# 4high.net
KiCad netlist of a schematic drawn in EAGLE
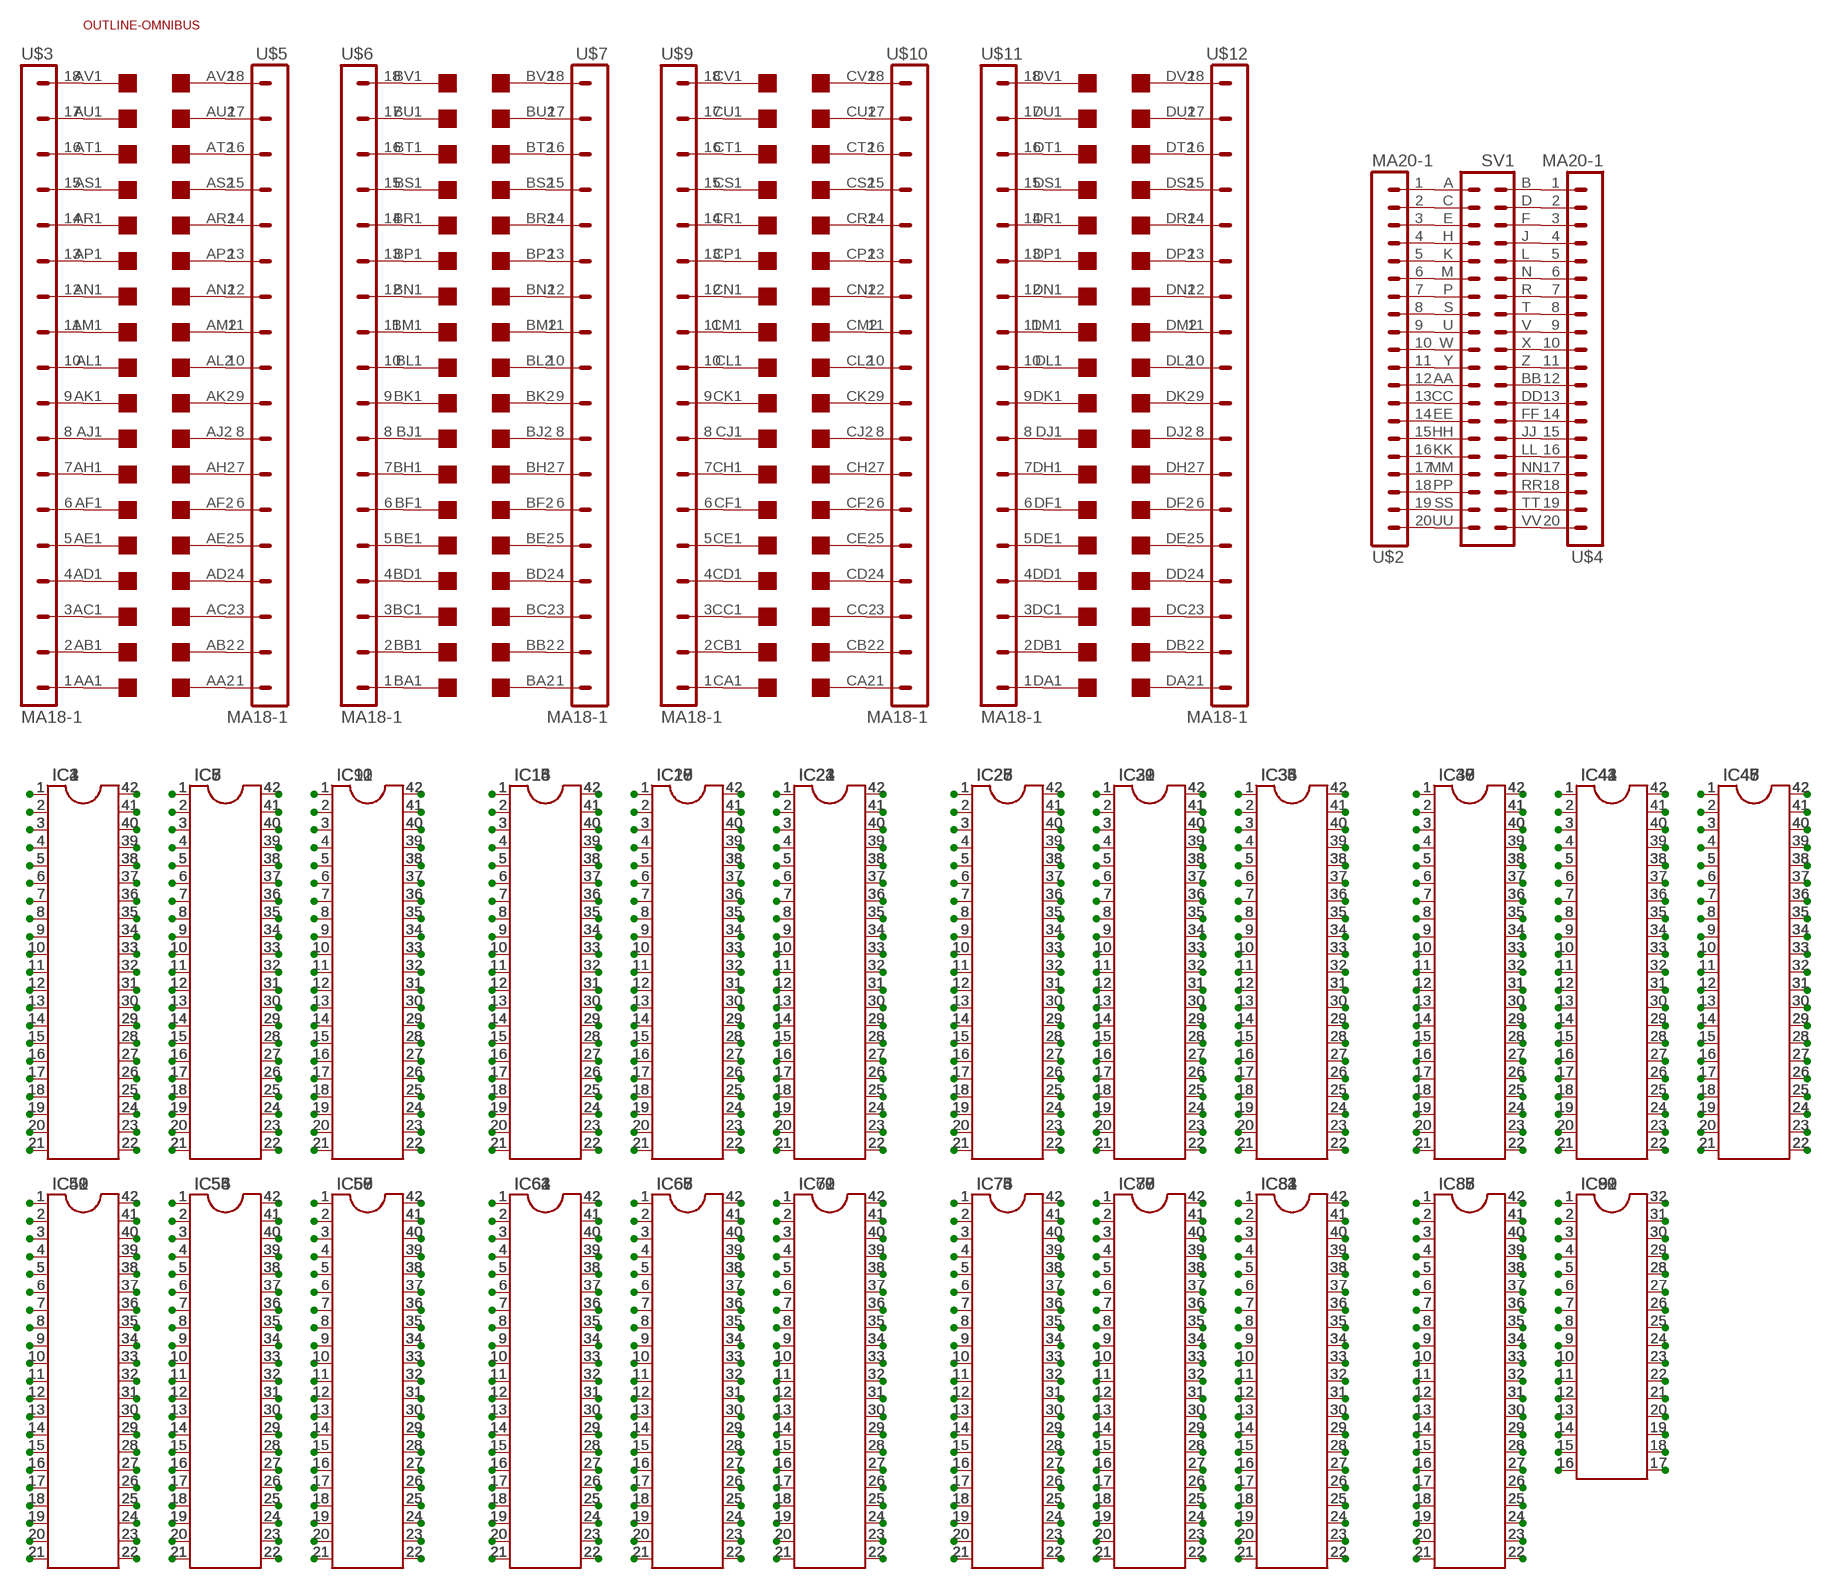
[diagram p0: schematic, sheet 1]

(export (version "E")
  (design (tool "Eeschema 10.0.6"))
  (components
    (comp (ref "IC1")
      (value "DIL42")
      (footprint "eagle-import:DIL42")
      (libsource (lib "eagle-import") (part "DIL42"))
    )
    (comp (ref "IC2")
      (value "DIL42")
      (footprint "eagle-import:DIL42")
      (libsource (lib "eagle-import") (part "DIL42"))
    )
    (comp (ref "IC3")
      (value "DIL42")
      (footprint "eagle-import:DIL42")
      (libsource (lib "eagle-import") (part "DIL42"))
    )
    (comp (ref "IC4")
      (value "DIL42")
      (footprint "eagle-import:DIL42")
      (libsource (lib "eagle-import") (part "DIL42"))
    )
    (comp (ref "IC5")
      (value "DIL42")
      (footprint "eagle-import:DIL42")
      (libsource (lib "eagle-import") (part "DIL42"))
    )
    (comp (ref "IC6")
      (value "DIL42")
      (footprint "eagle-import:DIL42")
      (libsource (lib "eagle-import") (part "DIL42"))
    )
    (comp (ref "IC7")
      (value "DIL42")
      (footprint "eagle-import:DIL42")
      (libsource (lib "eagle-import") (part "DIL42"))
    )
    (comp (ref "IC8")
      (value "DIL42")
      (footprint "eagle-import:DIL42")
      (libsource (lib "eagle-import") (part "DIL42"))
    )
    (comp (ref "IC9")
      (value "DIL42")
      (footprint "eagle-import:DIL42")
      (libsource (lib "eagle-import") (part "DIL42"))
    )
    (comp (ref "IC10")
      (value "DIL42")
      (footprint "eagle-import:DIL42")
      (libsource (lib "eagle-import") (part "DIL42"))
    )
    (comp (ref "IC11")
      (value "DIL42")
      (footprint "eagle-import:DIL42")
      (libsource (lib "eagle-import") (part "DIL42"))
    )
    (comp (ref "IC12")
      (value "DIL42")
      (footprint "eagle-import:DIL42")
      (libsource (lib "eagle-import") (part "DIL42"))
    )
    (comp (ref "IC13")
      (value "DIL42")
      (footprint "eagle-import:DIL42")
      (libsource (lib "eagle-import") (part "DIL42"))
    )
    (comp (ref "IC14")
      (value "DIL42")
      (footprint "eagle-import:DIL42")
      (libsource (lib "eagle-import") (part "DIL42"))
    )
    (comp (ref "IC15")
      (value "DIL42")
      (footprint "eagle-import:DIL42")
      (libsource (lib "eagle-import") (part "DIL42"))
    )
    (comp (ref "IC16")
      (value "DIL42")
      (footprint "eagle-import:DIL42")
      (libsource (lib "eagle-import") (part "DIL42"))
    )
    (comp (ref "IC17")
      (value "DIL42")
      (footprint "eagle-import:DIL42")
      (libsource (lib "eagle-import") (part "DIL42"))
    )
    (comp (ref "IC18")
      (value "DIL42")
      (footprint "eagle-import:DIL42")
      (libsource (lib "eagle-import") (part "DIL42"))
    )
    (comp (ref "IC19")
      (value "DIL42")
      (footprint "eagle-import:DIL42")
      (libsource (lib "eagle-import") (part "DIL42"))
    )
    (comp (ref "IC20")
      (value "DIL42")
      (footprint "eagle-import:DIL42")
      (libsource (lib "eagle-import") (part "DIL42"))
    )
    (comp (ref "IC21")
      (value "DIL42")
      (footprint "eagle-import:DIL42")
      (libsource (lib "eagle-import") (part "DIL42"))
    )
    (comp (ref "IC22")
      (value "DIL42")
      (footprint "eagle-import:DIL42")
      (libsource (lib "eagle-import") (part "DIL42"))
    )
    (comp (ref "IC23")
      (value "DIL42")
      (footprint "eagle-import:DIL42")
      (libsource (lib "eagle-import") (part "DIL42"))
    )
    (comp (ref "IC24")
      (value "DIL42")
      (footprint "eagle-import:DIL42")
      (libsource (lib "eagle-import") (part "DIL42"))
    )
    (comp (ref "IC25")
      (value "DIL42")
      (footprint "eagle-import:DIL42")
      (libsource (lib "eagle-import") (part "DIL42"))
    )
    (comp (ref "IC26")
      (value "DIL42")
      (footprint "eagle-import:DIL42")
      (libsource (lib "eagle-import") (part "DIL42"))
    )
    (comp (ref "IC27")
      (value "DIL42")
      (footprint "eagle-import:DIL42")
      (libsource (lib "eagle-import") (part "DIL42"))
    )
    (comp (ref "IC28")
      (value "DIL42")
      (footprint "eagle-import:DIL42")
      (libsource (lib "eagle-import") (part "DIL42"))
    )
    (comp (ref "IC29")
      (value "DIL42")
      (footprint "eagle-import:DIL42")
      (libsource (lib "eagle-import") (part "DIL42"))
    )
    (comp (ref "IC30")
      (value "DIL42")
      (footprint "eagle-import:DIL42")
      (libsource (lib "eagle-import") (part "DIL42"))
    )
    (comp (ref "IC31")
      (value "DIL42")
      (footprint "eagle-import:DIL42")
      (libsource (lib "eagle-import") (part "DIL42"))
    )
    (comp (ref "IC32")
      (value "DIL42")
      (footprint "eagle-import:DIL42")
      (libsource (lib "eagle-import") (part "DIL42"))
    )
    (comp (ref "IC33")
      (value "DIL42")
      (footprint "eagle-import:DIL42")
      (libsource (lib "eagle-import") (part "DIL42"))
    )
    (comp (ref "IC34")
      (value "DIL42")
      (footprint "eagle-import:DIL42")
      (libsource (lib "eagle-import") (part "DIL42"))
    )
    (comp (ref "IC35")
      (value "DIL42")
      (footprint "eagle-import:DIL42")
      (libsource (lib "eagle-import") (part "DIL42"))
    )
    (comp (ref "IC36")
      (value "DIL42")
      (footprint "eagle-import:DIL42")
      (libsource (lib "eagle-import") (part "DIL42"))
    )
    (comp (ref "IC37")
      (value "DIL42")
      (footprint "eagle-import:DIL42")
      (libsource (lib "eagle-import") (part "DIL42"))
    )
    (comp (ref "IC38")
      (value "DIL42")
      (footprint "eagle-import:DIL42")
      (libsource (lib "eagle-import") (part "DIL42"))
    )
    (comp (ref "IC39")
      (value "DIL42")
      (footprint "eagle-import:DIL42")
      (libsource (lib "eagle-import") (part "DIL42"))
    )
    (comp (ref "IC40")
      (value "DIL42")
      (footprint "eagle-import:DIL42")
      (libsource (lib "eagle-import") (part "DIL42"))
    )
    (comp (ref "IC41")
      (value "DIL42")
      (footprint "eagle-import:DIL42")
      (libsource (lib "eagle-import") (part "DIL42"))
    )
    (comp (ref "IC42")
      (value "DIL42")
      (footprint "eagle-import:DIL42")
      (libsource (lib "eagle-import") (part "DIL42"))
    )
    (comp (ref "IC43")
      (value "DIL42")
      (footprint "eagle-import:DIL42")
      (libsource (lib "eagle-import") (part "DIL42"))
    )
    (comp (ref "IC44")
      (value "DIL42")
      (footprint "eagle-import:DIL42")
      (libsource (lib "eagle-import") (part "DIL42"))
    )
    (comp (ref "IC45")
      (value "DIL42")
      (footprint "eagle-import:DIL42")
      (libsource (lib "eagle-import") (part "DIL42"))
    )
    (comp (ref "IC46")
      (value "DIL42")
      (footprint "eagle-import:DIL42")
      (libsource (lib "eagle-import") (part "DIL42"))
    )
    (comp (ref "IC47")
      (value "DIL42")
      (footprint "eagle-import:DIL42")
      (libsource (lib "eagle-import") (part "DIL42"))
    )
    (comp (ref "IC48")
      (value "DIL42")
      (footprint "eagle-import:DIL42")
      (libsource (lib "eagle-import") (part "DIL42"))
    )
    (comp (ref "IC49")
      (value "DIL42")
      (footprint "eagle-import:DIL42")
      (libsource (lib "eagle-import") (part "DIL42"))
    )
    (comp (ref "IC50")
      (value "DIL42")
      (footprint "eagle-import:DIL42")
      (libsource (lib "eagle-import") (part "DIL42"))
    )
    (comp (ref "IC51")
      (value "DIL42")
      (footprint "eagle-import:DIL42")
      (libsource (lib "eagle-import") (part "DIL42"))
    )
    (comp (ref "IC52")
      (value "DIL42")
      (footprint "eagle-import:DIL42")
      (libsource (lib "eagle-import") (part "DIL42"))
    )
    (comp (ref "IC53")
      (value "DIL42")
      (footprint "eagle-import:DIL42")
      (libsource (lib "eagle-import") (part "DIL42"))
    )
    (comp (ref "IC54")
      (value "DIL42")
      (footprint "eagle-import:DIL42")
      (libsource (lib "eagle-import") (part "DIL42"))
    )
    (comp (ref "IC55")
      (value "DIL42")
      (footprint "eagle-import:DIL42")
      (libsource (lib "eagle-import") (part "DIL42"))
    )
    (comp (ref "IC56")
      (value "DIL42")
      (footprint "eagle-import:DIL42")
      (libsource (lib "eagle-import") (part "DIL42"))
    )
    (comp (ref "IC57")
      (value "DIL42")
      (footprint "eagle-import:DIL42")
      (libsource (lib "eagle-import") (part "DIL42"))
    )
    (comp (ref "IC58")
      (value "DIL42")
      (footprint "eagle-import:DIL42")
      (libsource (lib "eagle-import") (part "DIL42"))
    )
    (comp (ref "IC59")
      (value "DIL42")
      (footprint "eagle-import:DIL42")
      (libsource (lib "eagle-import") (part "DIL42"))
    )
    (comp (ref "IC60")
      (value "DIL42")
      (footprint "eagle-import:DIL42")
      (libsource (lib "eagle-import") (part "DIL42"))
    )
    (comp (ref "IC61")
      (value "DIL42")
      (footprint "eagle-import:DIL42")
      (libsource (lib "eagle-import") (part "DIL42"))
    )
    (comp (ref "IC62")
      (value "DIL42")
      (footprint "eagle-import:DIL42")
      (libsource (lib "eagle-import") (part "DIL42"))
    )
    (comp (ref "IC63")
      (value "DIL42")
      (footprint "eagle-import:DIL42")
      (libsource (lib "eagle-import") (part "DIL42"))
    )
    (comp (ref "IC64")
      (value "DIL42")
      (footprint "eagle-import:DIL42")
      (libsource (lib "eagle-import") (part "DIL42"))
    )
    (comp (ref "IC65")
      (value "DIL42")
      (footprint "eagle-import:DIL42")
      (libsource (lib "eagle-import") (part "DIL42"))
    )
    (comp (ref "IC66")
      (value "DIL42")
      (footprint "eagle-import:DIL42")
      (libsource (lib "eagle-import") (part "DIL42"))
    )
    (comp (ref "IC67")
      (value "DIL42")
      (footprint "eagle-import:DIL42")
      (libsource (lib "eagle-import") (part "DIL42"))
    )
    (comp (ref "IC68")
      (value "DIL42")
      (footprint "eagle-import:DIL42")
      (libsource (lib "eagle-import") (part "DIL42"))
    )
    (comp (ref "IC69")
      (value "DIL42")
      (footprint "eagle-import:DIL42")
      (libsource (lib "eagle-import") (part "DIL42"))
    )
    (comp (ref "IC70")
      (value "DIL42")
      (footprint "eagle-import:DIL42")
      (libsource (lib "eagle-import") (part "DIL42"))
    )
    (comp (ref "IC71")
      (value "DIL42")
      (footprint "eagle-import:DIL42")
      (libsource (lib "eagle-import") (part "DIL42"))
    )
    (comp (ref "IC72")
      (value "DIL42")
      (footprint "eagle-import:DIL42")
      (libsource (lib "eagle-import") (part "DIL42"))
    )
    (comp (ref "IC73")
      (value "DIL42")
      (footprint "eagle-import:DIL42")
      (libsource (lib "eagle-import") (part "DIL42"))
    )
    (comp (ref "IC74")
      (value "DIL42")
      (footprint "eagle-import:DIL42")
      (libsource (lib "eagle-import") (part "DIL42"))
    )
    (comp (ref "IC75")
      (value "DIL42")
      (footprint "eagle-import:DIL42")
      (libsource (lib "eagle-import") (part "DIL42"))
    )
    (comp (ref "IC76")
      (value "DIL42")
      (footprint "eagle-import:DIL42")
      (libsource (lib "eagle-import") (part "DIL42"))
    )
    (comp (ref "IC77")
      (value "DIL42")
      (footprint "eagle-import:DIL42")
      (libsource (lib "eagle-import") (part "DIL42"))
    )
    (comp (ref "IC78")
      (value "DIL42")
      (footprint "eagle-import:DIL42")
      (libsource (lib "eagle-import") (part "DIL42"))
    )
    (comp (ref "IC79")
      (value "DIL42")
      (footprint "eagle-import:DIL42")
      (libsource (lib "eagle-import") (part "DIL42"))
    )
    (comp (ref "IC80")
      (value "DIL42")
      (footprint "eagle-import:DIL42")
      (libsource (lib "eagle-import") (part "DIL42"))
    )
    (comp (ref "IC81")
      (value "DIL42")
      (footprint "eagle-import:DIL42")
      (libsource (lib "eagle-import") (part "DIL42"))
    )
    (comp (ref "IC82")
      (value "DIL42")
      (footprint "eagle-import:DIL42")
      (libsource (lib "eagle-import") (part "DIL42"))
    )
    (comp (ref "IC83")
      (value "DIL42")
      (footprint "eagle-import:DIL42")
      (libsource (lib "eagle-import") (part "DIL42"))
    )
    (comp (ref "IC84")
      (value "DIL42")
      (footprint "eagle-import:DIL42")
      (libsource (lib "eagle-import") (part "DIL42"))
    )
    (comp (ref "IC85")
      (value "DIL42")
      (footprint "eagle-import:DIL42")
      (libsource (lib "eagle-import") (part "DIL42"))
    )
    (comp (ref "IC86")
      (value "DIL42")
      (footprint "eagle-import:DIL42")
      (libsource (lib "eagle-import") (part "DIL42"))
    )
    (comp (ref "IC87")
      (value "DIL42")
      (footprint "eagle-import:DIL42")
      (libsource (lib "eagle-import") (part "DIL42"))
    )
    (comp (ref "IC88")
      (value "DIL42")
      (footprint "eagle-import:DIL42")
      (libsource (lib "eagle-import") (part "DIL42"))
    )
    (comp (ref "IC89")
      (value "DIL32")
      (footprint "eagle-import:DIL32")
      (libsource (lib "eagle-import") (part "DIL32"))
    )
    (comp (ref "IC90")
      (value "DIL32")
      (footprint "eagle-import:DIL32")
      (libsource (lib "eagle-import") (part "DIL32"))
    )
    (comp (ref "IC91")
      (value "DIL32")
      (footprint "eagle-import:DIL32")
      (libsource (lib "eagle-import") (part "DIL32"))
    )
    (comp (ref "IC92")
      (value "DIL32")
      (footprint "eagle-import:DIL32")
      (libsource (lib "eagle-import") (part "DIL32"))
    )
    (comp (ref "SV1")
      (value "DEC40PINH")
      (footprint "eagle-import:DEC40PINH")
      (libsource (lib "eagle-import") (part "DEC40PINH"))
    )
    (comp (ref "U$1")
      (value "QUAD")
      (footprint "eagle-import:EDGE-CON8")
      (libsource (lib "eagle-import") (part "QUAD"))
    )
    (comp (ref "U$2")
      (value "MA20-1")
      (footprint "eagle-import:MA20-1")
      (libsource (lib "eagle-import") (part "MA20-1"))
    )
    (comp (ref "U$3")
      (value "MA18-1")
      (footprint "eagle-import:MA18-1")
      (libsource (lib "eagle-import") (part "MA18-1"))
    )
    (comp (ref "U$4")
      (value "MA20-1")
      (footprint "eagle-import:MA20-1")
      (libsource (lib "eagle-import") (part "MA20-1"))
    )
    (comp (ref "U$5")
      (value "MA18-1")
      (footprint "eagle-import:MA18-1")
      (libsource (lib "eagle-import") (part "MA18-1"))
    )
    (comp (ref "U$6")
      (value "MA18-1")
      (footprint "eagle-import:MA18-1")
      (libsource (lib "eagle-import") (part "MA18-1"))
    )
    (comp (ref "U$7")
      (value "MA18-1")
      (footprint "eagle-import:MA18-1")
      (libsource (lib "eagle-import") (part "MA18-1"))
    )
    (comp (ref "U$8")
      (value "OUTLINE-OMNIBUS")
      (footprint "eagle-import:OMNIBUS")
      (libsource (lib "eagle-import") (part "OUTLINE-OMNIBUS"))
    )
    (comp (ref "U$9")
      (value "MA18-1")
      (footprint "eagle-import:MA18-1")
      (libsource (lib "eagle-import") (part "MA18-1"))
    )
    (comp (ref "U$10")
      (value "MA18-1")
      (footprint "eagle-import:MA18-1")
      (libsource (lib "eagle-import") (part "MA18-1"))
    )
    (comp (ref "U$11")
      (value "MA18-1")
      (footprint "eagle-import:MA18-1")
      (libsource (lib "eagle-import") (part "MA18-1"))
    )
    (comp (ref "U$12")
      (value "MA18-1")
      (footprint "eagle-import:MA18-1")
      (libsource (lib "eagle-import") (part "MA18-1"))
    )
  )
  (nets
    (net (code "1") (name "Net-(IC1-Pad1)") (class "Default")
      (node (ref "IC1") (pin "1") (pinfunction "1_1") (pintype "passive"))
      (node (ref "IC2") (pin "1") (pinfunction "1_1") (pintype "passive"))
      (node (ref "IC3") (pin "1") (pinfunction "1_1") (pintype "passive"))
      (node (ref "IC4") (pin "1") (pinfunction "1_1") (pintype "passive"))
    )
    (net (code "2") (name "Net-(IC1-Pad2)") (class "Default")
      (node (ref "IC1") (pin "2") (pinfunction "2_2") (pintype "passive"))
      (node (ref "IC2") (pin "2") (pinfunction "2_2") (pintype "passive"))
      (node (ref "IC3") (pin "2") (pinfunction "2_2") (pintype "passive"))
      (node (ref "IC4") (pin "2") (pinfunction "2_2") (pintype "passive"))
    )
    (net (code "3") (name "Net-(IC1-Pad3)") (class "Default")
      (node (ref "IC1") (pin "3") (pinfunction "3_3") (pintype "passive"))
      (node (ref "IC2") (pin "3") (pinfunction "3_3") (pintype "passive"))
      (node (ref "IC3") (pin "3") (pinfunction "3_3") (pintype "passive"))
      (node (ref "IC4") (pin "3") (pinfunction "3_3") (pintype "passive"))
    )
    (net (code "4") (name "Net-(IC1-Pad4)") (class "Default")
      (node (ref "IC1") (pin "4") (pinfunction "4_4") (pintype "passive"))
      (node (ref "IC2") (pin "4") (pinfunction "4_4") (pintype "passive"))
      (node (ref "IC3") (pin "4") (pinfunction "4_4") (pintype "passive"))
      (node (ref "IC4") (pin "4") (pinfunction "4_4") (pintype "passive"))
    )
    (net (code "5") (name "Net-(IC1-Pad5)") (class "Default")
      (node (ref "IC1") (pin "5") (pinfunction "5_5") (pintype "passive"))
      (node (ref "IC2") (pin "5") (pinfunction "5_5") (pintype "passive"))
      (node (ref "IC3") (pin "5") (pinfunction "5_5") (pintype "passive"))
      (node (ref "IC4") (pin "5") (pinfunction "5_5") (pintype "passive"))
    )
    (net (code "6") (name "Net-(IC1-Pad6)") (class "Default")
      (node (ref "IC1") (pin "6") (pinfunction "6_6") (pintype "passive"))
      (node (ref "IC2") (pin "6") (pinfunction "6_6") (pintype "passive"))
      (node (ref "IC3") (pin "6") (pinfunction "6_6") (pintype "passive"))
      (node (ref "IC4") (pin "6") (pinfunction "6_6") (pintype "passive"))
    )
    (net (code "7") (name "Net-(IC1-Pad7)") (class "Default")
      (node (ref "IC1") (pin "7") (pinfunction "7_7") (pintype "passive"))
      (node (ref "IC2") (pin "7") (pinfunction "7_7") (pintype "passive"))
      (node (ref "IC3") (pin "7") (pinfunction "7_7") (pintype "passive"))
      (node (ref "IC4") (pin "7") (pinfunction "7_7") (pintype "passive"))
    )
    (net (code "8") (name "Net-(IC1-Pad8)") (class "Default")
      (node (ref "IC1") (pin "8") (pinfunction "8_8") (pintype "passive"))
      (node (ref "IC2") (pin "8") (pinfunction "8_8") (pintype "passive"))
      (node (ref "IC3") (pin "8") (pinfunction "8_8") (pintype "passive"))
      (node (ref "IC4") (pin "8") (pinfunction "8_8") (pintype "passive"))
    )
    (net (code "9") (name "Net-(IC1-Pad9)") (class "Default")
      (node (ref "IC1") (pin "9") (pinfunction "9_9") (pintype "passive"))
      (node (ref "IC2") (pin "9") (pinfunction "9_9") (pintype "passive"))
      (node (ref "IC3") (pin "9") (pinfunction "9_9") (pintype "passive"))
      (node (ref "IC4") (pin "9") (pinfunction "9_9") (pintype "passive"))
    )
    (net (code "10") (name "Net-(IC1-Pad10)") (class "Default")
      (node (ref "IC1") (pin "10") (pinfunction "10_10") (pintype "passive"))
      (node (ref "IC2") (pin "10") (pinfunction "10_10") (pintype "passive"))
      (node (ref "IC3") (pin "10") (pinfunction "10_10") (pintype "passive"))
      (node (ref "IC4") (pin "10") (pinfunction "10_10") (pintype "passive"))
    )
    (net (code "11") (name "Net-(IC1-Pad11)") (class "Default")
      (node (ref "IC1") (pin "11") (pinfunction "11_11") (pintype "passive"))
      (node (ref "IC2") (pin "11") (pinfunction "11_11") (pintype "passive"))
      (node (ref "IC3") (pin "11") (pinfunction "11_11") (pintype "passive"))
      (node (ref "IC4") (pin "11") (pinfunction "11_11") (pintype "passive"))
    )
    (net (code "12") (name "Net-(IC1-Pad12)") (class "Default")
      (node (ref "IC1") (pin "12") (pinfunction "12_12") (pintype "passive"))
      (node (ref "IC2") (pin "12") (pinfunction "12_12") (pintype "passive"))
      (node (ref "IC3") (pin "12") (pinfunction "12_12") (pintype "passive"))
      (node (ref "IC4") (pin "12") (pinfunction "12_12") (pintype "passive"))
    )
    (net (code "13") (name "Net-(IC1-Pad13)") (class "Default")
      (node (ref "IC1") (pin "13") (pinfunction "13_13") (pintype "passive"))
      (node (ref "IC2") (pin "13") (pinfunction "13_13") (pintype "passive"))
      (node (ref "IC3") (pin "13") (pinfunction "13_13") (pintype "passive"))
      (node (ref "IC4") (pin "13") (pinfunction "13_13") (pintype "passive"))
    )
    (net (code "14") (name "Net-(IC1-Pad14)") (class "Default")
      (node (ref "IC1") (pin "14") (pinfunction "14_14") (pintype "passive"))
      (node (ref "IC2") (pin "14") (pinfunction "14_14") (pintype "passive"))
      (node (ref "IC3") (pin "14") (pinfunction "14_14") (pintype "passive"))
      (node (ref "IC4") (pin "14") (pinfunction "14_14") (pintype "passive"))
    )
    (net (code "15") (name "Net-(IC1-Pad15)") (class "Default")
      (node (ref "IC1") (pin "15") (pinfunction "15_15") (pintype "passive"))
      (node (ref "IC2") (pin "15") (pinfunction "15_15") (pintype "passive"))
      (node (ref "IC3") (pin "15") (pinfunction "15_15") (pintype "passive"))
      (node (ref "IC4") (pin "15") (pinfunction "15_15") (pintype "passive"))
    )
    (net (code "16") (name "Net-(IC1-Pad16)") (class "Default")
      (node (ref "IC1") (pin "16") (pinfunction "16_16") (pintype "passive"))
      (node (ref "IC2") (pin "16") (pinfunction "16_16") (pintype "passive"))
      (node (ref "IC3") (pin "16") (pinfunction "16_16") (pintype "passive"))
      (node (ref "IC4") (pin "16") (pinfunction "16_16") (pintype "passive"))
    )
    (net (code "17") (name "Net-(IC1-Pad17)") (class "Default")
      (node (ref "IC1") (pin "17") (pinfunction "17_17") (pintype "passive"))
      (node (ref "IC2") (pin "17") (pinfunction "17_17") (pintype "passive"))
      (node (ref "IC3") (pin "17") (pinfunction "17_17") (pintype "passive"))
      (node (ref "IC4") (pin "17") (pinfunction "17_17") (pintype "passive"))
    )
    (net (code "18") (name "Net-(IC1-Pad18)") (class "Default")
      (node (ref "IC1") (pin "18") (pinfunction "18_18") (pintype "passive"))
      (node (ref "IC2") (pin "18") (pinfunction "18_18") (pintype "passive"))
      (node (ref "IC3") (pin "18") (pinfunction "18_18") (pintype "passive"))
      (node (ref "IC4") (pin "18") (pinfunction "18_18") (pintype "passive"))
    )
    (net (code "19") (name "Net-(IC1-Pad19)") (class "Default")
      (node (ref "IC1") (pin "19") (pinfunction "19_19") (pintype "passive"))
      (node (ref "IC2") (pin "19") (pinfunction "19_19") (pintype "passive"))
      (node (ref "IC3") (pin "19") (pinfunction "19_19") (pintype "passive"))
      (node (ref "IC4") (pin "19") (pinfunction "19_19") (pintype "passive"))
    )
    (net (code "20") (name "Net-(IC1-Pad20)") (class "Default")
      (node (ref "IC1") (pin "20") (pinfunction "20_20") (pintype "passive"))
      (node (ref "IC2") (pin "20") (pinfunction "20_20") (pintype "passive"))
      (node (ref "IC3") (pin "20") (pinfunction "20_20") (pintype "passive"))
      (node (ref "IC4") (pin "20") (pinfunction "20_20") (pintype "passive"))
    )
    (net (code "21") (name "Net-(IC1-Pad21)") (class "Default")
      (node (ref "IC1") (pin "21") (pinfunction "21_21") (pintype "passive"))
      (node (ref "IC2") (pin "21") (pinfunction "21_21") (pintype "passive"))
      (node (ref "IC3") (pin "21") (pinfunction "21_21") (pintype "passive"))
      (node (ref "IC4") (pin "21") (pinfunction "21_21") (pintype "passive"))
    )
    (net (code "22") (name "Net-(IC1-Pad22)") (class "Default")
      (node (ref "IC1") (pin "22") (pinfunction "22_22") (pintype "passive"))
      (node (ref "IC2") (pin "22") (pinfunction "22_22") (pintype "passive"))
      (node (ref "IC3") (pin "22") (pinfunction "22_22") (pintype "passive"))
      (node (ref "IC4") (pin "22") (pinfunction "22_22") (pintype "passive"))
    )
    (net (code "23") (name "Net-(IC1-Pad23)") (class "Default")
      (node (ref "IC1") (pin "23") (pinfunction "23_23") (pintype "passive"))
      (node (ref "IC2") (pin "23") (pinfunction "23_23") (pintype "passive"))
      (node (ref "IC3") (pin "23") (pinfunction "23_23") (pintype "passive"))
      (node (ref "IC4") (pin "23") (pinfunction "23_23") (pintype "passive"))
    )
    (net (code "24") (name "Net-(IC1-Pad24)") (class "Default")
      (node (ref "IC1") (pin "24") (pinfunction "24_24") (pintype "passive"))
      (node (ref "IC2") (pin "24") (pinfunction "24_24") (pintype "passive"))
      (node (ref "IC3") (pin "24") (pinfunction "24_24") (pintype "passive"))
      (node (ref "IC4") (pin "24") (pinfunction "24_24") (pintype "passive"))
    )
    (net (code "25") (name "Net-(IC1-Pad25)") (class "Default")
      (node (ref "IC1") (pin "25") (pinfunction "25_25") (pintype "passive"))
      (node (ref "IC2") (pin "25") (pinfunction "25_25") (pintype "passive"))
      (node (ref "IC3") (pin "25") (pinfunction "25_25") (pintype "passive"))
      (node (ref "IC4") (pin "25") (pinfunction "25_25") (pintype "passive"))
    )
    (net (code "26") (name "Net-(IC1-Pad26)") (class "Default")
      (node (ref "IC1") (pin "26") (pinfunction "26_26") (pintype "passive"))
      (node (ref "IC2") (pin "26") (pinfunction "26_26") (pintype "passive"))
      (node (ref "IC3") (pin "26") (pinfunction "26_26") (pintype "passive"))
      (node (ref "IC4") (pin "26") (pinfunction "26_26") (pintype "passive"))
    )
    (net (code "27") (name "Net-(IC1-Pad27)") (class "Default")
      (node (ref "IC1") (pin "27") (pinfunction "27_27") (pintype "passive"))
      (node (ref "IC2") (pin "27") (pinfunction "27_27") (pintype "passive"))
      (node (ref "IC3") (pin "27") (pinfunction "27_27") (pintype "passive"))
      (node (ref "IC4") (pin "27") (pinfunction "27_27") (pintype "passive"))
    )
    (net (code "28") (name "Net-(IC1-Pad28)") (class "Default")
      (node (ref "IC1") (pin "28") (pinfunction "28_28") (pintype "passive"))
      (node (ref "IC2") (pin "28") (pinfunction "28_28") (pintype "passive"))
      (node (ref "IC3") (pin "28") (pinfunction "28_28") (pintype "passive"))
      (node (ref "IC4") (pin "28") (pinfunction "28_28") (pintype "passive"))
    )
    (net (code "29") (name "Net-(IC1-Pad29)") (class "Default")
      (node (ref "IC1") (pin "29") (pinfunction "29_29") (pintype "passive"))
      (node (ref "IC2") (pin "29") (pinfunction "29_29") (pintype "passive"))
      (node (ref "IC3") (pin "29") (pinfunction "29_29") (pintype "passive"))
      (node (ref "IC4") (pin "29") (pinfunction "29_29") (pintype "passive"))
    )
    (net (code "30") (name "Net-(IC1-Pad30)") (class "Default")
      (node (ref "IC1") (pin "30") (pinfunction "30_30") (pintype "passive"))
      (node (ref "IC2") (pin "30") (pinfunction "30_30") (pintype "passive"))
      (node (ref "IC3") (pin "30") (pinfunction "30_30") (pintype "passive"))
      (node (ref "IC4") (pin "30") (pinfunction "30_30") (pintype "passive"))
    )
    (net (code "31") (name "Net-(IC1-Pad31)") (class "Default")
      (node (ref "IC1") (pin "31") (pinfunction "31_31") (pintype "passive"))
      (node (ref "IC2") (pin "31") (pinfunction "31_31") (pintype "passive"))
      (node (ref "IC3") (pin "31") (pinfunction "31_31") (pintype "passive"))
      (node (ref "IC4") (pin "31") (pinfunction "31_31") (pintype "passive"))
    )
    (net (code "32") (name "Net-(IC1-Pad32)") (class "Default")
      (node (ref "IC1") (pin "32") (pinfunction "32_32") (pintype "passive"))
      (node (ref "IC2") (pin "32") (pinfunction "32_32") (pintype "passive"))
      (node (ref "IC3") (pin "32") (pinfunction "32_32") (pintype "passive"))
      (node (ref "IC4") (pin "32") (pinfunction "32_32") (pintype "passive"))
    )
    (net (code "33") (name "Net-(IC1-Pad33)") (class "Default")
      (node (ref "IC1") (pin "33") (pinfunction "33_33") (pintype "passive"))
      (node (ref "IC2") (pin "33") (pinfunction "33_33") (pintype "passive"))
      (node (ref "IC3") (pin "33") (pinfunction "33_33") (pintype "passive"))
      (node (ref "IC4") (pin "33") (pinfunction "33_33") (pintype "passive"))
    )
    (net (code "34") (name "Net-(IC1-Pad34)") (class "Default")
      (node (ref "IC1") (pin "34") (pinfunction "34_34") (pintype "passive"))
      (node (ref "IC2") (pin "34") (pinfunction "34_34") (pintype "passive"))
      (node (ref "IC3") (pin "34") (pinfunction "34_34") (pintype "passive"))
      (node (ref "IC4") (pin "34") (pinfunction "34_34") (pintype "passive"))
    )
    (net (code "35") (name "Net-(IC1-Pad35)") (class "Default")
      (node (ref "IC1") (pin "35") (pinfunction "35_35") (pintype "passive"))
      (node (ref "IC2") (pin "35") (pinfunction "35_35") (pintype "passive"))
      (node (ref "IC3") (pin "35") (pinfunction "35_35") (pintype "passive"))
      (node (ref "IC4") (pin "35") (pinfunction "35_35") (pintype "passive"))
    )
    (net (code "36") (name "Net-(IC1-Pad36)") (class "Default")
      (node (ref "IC1") (pin "36") (pinfunction "36_36") (pintype "passive"))
      (node (ref "IC2") (pin "36") (pinfunction "36_36") (pintype "passive"))
      (node (ref "IC3") (pin "36") (pinfunction "36_36") (pintype "passive"))
      (node (ref "IC4") (pin "36") (pinfunction "36_36") (pintype "passive"))
    )
    (net (code "37") (name "Net-(IC1-Pad37)") (class "Default")
      (node (ref "IC1") (pin "37") (pinfunction "37_37") (pintype "passive"))
      (node (ref "IC2") (pin "37") (pinfunction "37_37") (pintype "passive"))
      (node (ref "IC3") (pin "37") (pinfunction "37_37") (pintype "passive"))
      (node (ref "IC4") (pin "37") (pinfunction "37_37") (pintype "passive"))
    )
    (net (code "38") (name "Net-(IC1-Pad38)") (class "Default")
      (node (ref "IC1") (pin "38") (pinfunction "38_38") (pintype "passive"))
      (node (ref "IC2") (pin "38") (pinfunction "38_38") (pintype "passive"))
      (node (ref "IC3") (pin "38") (pinfunction "38_38") (pintype "passive"))
      (node (ref "IC4") (pin "38") (pinfunction "38_38") (pintype "passive"))
    )
    (net (code "39") (name "Net-(IC1-Pad39)") (class "Default")
      (node (ref "IC1") (pin "39") (pinfunction "39_39") (pintype "passive"))
      (node (ref "IC2") (pin "39") (pinfunction "39_39") (pintype "passive"))
      (node (ref "IC3") (pin "39") (pinfunction "39_39") (pintype "passive"))
      (node (ref "IC4") (pin "39") (pinfunction "39_39") (pintype "passive"))
    )
    (net (code "40") (name "Net-(IC1-Pad40)") (class "Default")
      (node (ref "IC1") (pin "40") (pinfunction "40_40") (pintype "passive"))
      (node (ref "IC2") (pin "40") (pinfunction "40_40") (pintype "passive"))
      (node (ref "IC3") (pin "40") (pinfunction "40_40") (pintype "passive"))
      (node (ref "IC4") (pin "40") (pinfunction "40_40") (pintype "passive"))
    )
    (net (code "41") (name "Net-(IC1-Pad41)") (class "Default")
      (node (ref "IC1") (pin "41") (pinfunction "41_41") (pintype "passive"))
      (node (ref "IC2") (pin "41") (pinfunction "41_41") (pintype "passive"))
      (node (ref "IC3") (pin "41") (pinfunction "41_41") (pintype "passive"))
      (node (ref "IC4") (pin "41") (pinfunction "41_41") (pintype "passive"))
    )
    (net (code "42") (name "Net-(IC1-Pad42)") (class "Default")
      (node (ref "IC1") (pin "42") (pinfunction "42_42") (pintype "passive"))
      (node (ref "IC2") (pin "42") (pinfunction "42_42") (pintype "passive"))
      (node (ref "IC3") (pin "42") (pinfunction "42_42") (pintype "passive"))
      (node (ref "IC4") (pin "42") (pinfunction "42_42") (pintype "passive"))
    )
    (net (code "43") (name "Net-(IC5-Pad1)") (class "Default")
      (node (ref "IC5") (pin "1") (pinfunction "1_1") (pintype "passive"))
      (node (ref "IC6") (pin "1") (pinfunction "1_1") (pintype "passive"))
      (node (ref "IC7") (pin "1") (pinfunction "1_1") (pintype "passive"))
      (node (ref "IC8") (pin "1") (pinfunction "1_1") (pintype "passive"))
    )
    (net (code "44") (name "Net-(IC5-Pad2)") (class "Default")
      (node (ref "IC5") (pin "2") (pinfunction "2_2") (pintype "passive"))
      (node (ref "IC6") (pin "2") (pinfunction "2_2") (pintype "passive"))
      (node (ref "IC7") (pin "2") (pinfunction "2_2") (pintype "passive"))
      (node (ref "IC8") (pin "2") (pinfunction "2_2") (pintype "passive"))
    )
    (net (code "45") (name "Net-(IC5-Pad3)") (class "Default")
      (node (ref "IC5") (pin "3") (pinfunction "3_3") (pintype "passive"))
      (node (ref "IC6") (pin "3") (pinfunction "3_3") (pintype "passive"))
      (node (ref "IC7") (pin "3") (pinfunction "3_3") (pintype "passive"))
      (node (ref "IC8") (pin "3") (pinfunction "3_3") (pintype "passive"))
    )
    (net (code "46") (name "Net-(IC5-Pad4)") (class "Default")
      (node (ref "IC5") (pin "4") (pinfunction "4_4") (pintype "passive"))
      (node (ref "IC6") (pin "4") (pinfunction "4_4") (pintype "passive"))
      (node (ref "IC7") (pin "4") (pinfunction "4_4") (pintype "passive"))
      (node (ref "IC8") (pin "4") (pinfunction "4_4") (pintype "passive"))
    )
    (net (code "47") (name "Net-(IC5-Pad5)") (class "Default")
      (node (ref "IC5") (pin "5") (pinfunction "5_5") (pintype "passive"))
      (node (ref "IC6") (pin "5") (pinfunction "5_5") (pintype "passive"))
      (node (ref "IC7") (pin "5") (pinfunction "5_5") (pintype "passive"))
      (node (ref "IC8") (pin "5") (pinfunction "5_5") (pintype "passive"))
    )
    (net (code "48") (name "Net-(IC5-Pad6)") (class "Default")
      (node (ref "IC5") (pin "6") (pinfunction "6_6") (pintype "passive"))
      (node (ref "IC6") (pin "6") (pinfunction "6_6") (pintype "passive"))
      (node (ref "IC7") (pin "6") (pinfunction "6_6") (pintype "passive"))
      (node (ref "IC8") (pin "6") (pinfunction "6_6") (pintype "passive"))
    )
    (net (code "49") (name "Net-(IC5-Pad7)") (class "Default")
      (node (ref "IC5") (pin "7") (pinfunction "7_7") (pintype "passive"))
      (node (ref "IC6") (pin "7") (pinfunction "7_7") (pintype "passive"))
      (node (ref "IC7") (pin "7") (pinfunction "7_7") (pintype "passive"))
      (node (ref "IC8") (pin "7") (pinfunction "7_7") (pintype "passive"))
    )
    (net (code "50") (name "Net-(IC5-Pad8)") (class "Default")
      (node (ref "IC5") (pin "8") (pinfunction "8_8") (pintype "passive"))
      (node (ref "IC6") (pin "8") (pinfunction "8_8") (pintype "passive"))
      (node (ref "IC7") (pin "8") (pinfunction "8_8") (pintype "passive"))
      (node (ref "IC8") (pin "8") (pinfunction "8_8") (pintype "passive"))
    )
    (net (code "51") (name "Net-(IC5-Pad9)") (class "Default")
      (node (ref "IC5") (pin "9") (pinfunction "9_9") (pintype "passive"))
      (node (ref "IC6") (pin "9") (pinfunction "9_9") (pintype "passive"))
      (node (ref "IC7") (pin "9") (pinfunction "9_9") (pintype "passive"))
      (node (ref "IC8") (pin "9") (pinfunction "9_9") (pintype "passive"))
    )
    (net (code "52") (name "Net-(IC5-Pad10)") (class "Default")
      (node (ref "IC5") (pin "10") (pinfunction "10_10") (pintype "passive"))
      (node (ref "IC6") (pin "10") (pinfunction "10_10") (pintype "passive"))
      (node (ref "IC7") (pin "10") (pinfunction "10_10") (pintype "passive"))
      (node (ref "IC8") (pin "10") (pinfunction "10_10") (pintype "passive"))
    )
    (net (code "53") (name "Net-(IC5-Pad11)") (class "Default")
      (node (ref "IC5") (pin "11") (pinfunction "11_11") (pintype "passive"))
      (node (ref "IC6") (pin "11") (pinfunction "11_11") (pintype "passive"))
      (node (ref "IC7") (pin "11") (pinfunction "11_11") (pintype "passive"))
      (node (ref "IC8") (pin "11") (pinfunction "11_11") (pintype "passive"))
    )
    (net (code "54") (name "Net-(IC5-Pad12)") (class "Default")
      (node (ref "IC5") (pin "12") (pinfunction "12_12") (pintype "passive"))
      (node (ref "IC6") (pin "12") (pinfunction "12_12") (pintype "passive"))
      (node (ref "IC7") (pin "12") (pinfunction "12_12") (pintype "passive"))
      (node (ref "IC8") (pin "12") (pinfunction "12_12") (pintype "passive"))
    )
    (net (code "55") (name "Net-(IC5-Pad13)") (class "Default")
      (node (ref "IC5") (pin "13") (pinfunction "13_13") (pintype "passive"))
      (node (ref "IC6") (pin "13") (pinfunction "13_13") (pintype "passive"))
      (node (ref "IC7") (pin "13") (pinfunction "13_13") (pintype "passive"))
      (node (ref "IC8") (pin "13") (pinfunction "13_13") (pintype "passive"))
    )
    (net (code "56") (name "Net-(IC5-Pad14)") (class "Default")
      (node (ref "IC5") (pin "14") (pinfunction "14_14") (pintype "passive"))
      (node (ref "IC6") (pin "14") (pinfunction "14_14") (pintype "passive"))
      (node (ref "IC7") (pin "14") (pinfunction "14_14") (pintype "passive"))
      (node (ref "IC8") (pin "14") (pinfunction "14_14") (pintype "passive"))
    )
    (net (code "57") (name "Net-(IC5-Pad15)") (class "Default")
      (node (ref "IC5") (pin "15") (pinfunction "15_15") (pintype "passive"))
      (node (ref "IC6") (pin "15") (pinfunction "15_15") (pintype "passive"))
      (node (ref "IC7") (pin "15") (pinfunction "15_15") (pintype "passive"))
      (node (ref "IC8") (pin "15") (pinfunction "15_15") (pintype "passive"))
    )
    (net (code "58") (name "Net-(IC5-Pad16)") (class "Default")
      (node (ref "IC5") (pin "16") (pinfunction "16_16") (pintype "passive"))
      (node (ref "IC6") (pin "16") (pinfunction "16_16") (pintype "passive"))
      (node (ref "IC7") (pin "16") (pinfunction "16_16") (pintype "passive"))
      (node (ref "IC8") (pin "16") (pinfunction "16_16") (pintype "passive"))
    )
    (net (code "59") (name "Net-(IC5-Pad17)") (class "Default")
      (node (ref "IC5") (pin "17") (pinfunction "17_17") (pintype "passive"))
      (node (ref "IC6") (pin "17") (pinfunction "17_17") (pintype "passive"))
      (node (ref "IC7") (pin "17") (pinfunction "17_17") (pintype "passive"))
      (node (ref "IC8") (pin "17") (pinfunction "17_17") (pintype "passive"))
    )
    (net (code "60") (name "Net-(IC5-Pad18)") (class "Default")
      (node (ref "IC5") (pin "18") (pinfunction "18_18") (pintype "passive"))
      (node (ref "IC6") (pin "18") (pinfunction "18_18") (pintype "passive"))
      (node (ref "IC7") (pin "18") (pinfunction "18_18") (pintype "passive"))
      (node (ref "IC8") (pin "18") (pinfunction "18_18") (pintype "passive"))
    )
    (net (code "61") (name "Net-(IC5-Pad19)") (class "Default")
      (node (ref "IC5") (pin "19") (pinfunction "19_19") (pintype "passive"))
      (node (ref "IC6") (pin "19") (pinfunction "19_19") (pintype "passive"))
      (node (ref "IC7") (pin "19") (pinfunction "19_19") (pintype "passive"))
      (node (ref "IC8") (pin "19") (pinfunction "19_19") (pintype "passive"))
    )
    (net (code "62") (name "Net-(IC5-Pad20)") (class "Default")
      (node (ref "IC5") (pin "20") (pinfunction "20_20") (pintype "passive"))
      (node (ref "IC6") (pin "20") (pinfunction "20_20") (pintype "passive"))
      (node (ref "IC7") (pin "20") (pinfunction "20_20") (pintype "passive"))
      (node (ref "IC8") (pin "20") (pinfunction "20_20") (pintype "passive"))
    )
    (net (code "63") (name "Net-(IC5-Pad21)") (class "Default")
      (node (ref "IC5") (pin "21") (pinfunction "21_21") (pintype "passive"))
      (node (ref "IC6") (pin "21") (pinfunction "21_21") (pintype "passive"))
      (node (ref "IC7") (pin "21") (pinfunction "21_21") (pintype "passive"))
      (node (ref "IC8") (pin "21") (pinfunction "21_21") (pintype "passive"))
    )
    (net (code "64") (name "Net-(IC5-Pad22)") (class "Default")
      (node (ref "IC5") (pin "22") (pinfunction "22_22") (pintype "passive"))
      (node (ref "IC6") (pin "22") (pinfunction "22_22") (pintype "passive"))
      (node (ref "IC7") (pin "22") (pinfunction "22_22") (pintype "passive"))
      (node (ref "IC8") (pin "22") (pinfunction "22_22") (pintype "passive"))
    )
    (net (code "65") (name "Net-(IC5-Pad23)") (class "Default")
      (node (ref "IC5") (pin "23") (pinfunction "23_23") (pintype "passive"))
      (node (ref "IC6") (pin "23") (pinfunction "23_23") (pintype "passive"))
      (node (ref "IC7") (pin "23") (pinfunction "23_23") (pintype "passive"))
      (node (ref "IC8") (pin "23") (pinfunction "23_23") (pintype "passive"))
    )
    (net (code "66") (name "Net-(IC5-Pad24)") (class "Default")
      (node (ref "IC5") (pin "24") (pinfunction "24_24") (pintype "passive"))
      (node (ref "IC6") (pin "24") (pinfunction "24_24") (pintype "passive"))
      (node (ref "IC7") (pin "24") (pinfunction "24_24") (pintype "passive"))
      (node (ref "IC8") (pin "24") (pinfunction "24_24") (pintype "passive"))
    )
    (net (code "67") (name "Net-(IC5-Pad25)") (class "Default")
      (node (ref "IC5") (pin "25") (pinfunction "25_25") (pintype "passive"))
      (node (ref "IC6") (pin "25") (pinfunction "25_25") (pintype "passive"))
      (node (ref "IC7") (pin "25") (pinfunction "25_25") (pintype "passive"))
      (node (ref "IC8") (pin "25") (pinfunction "25_25") (pintype "passive"))
    )
    (net (code "68") (name "Net-(IC5-Pad26)") (class "Default")
      (node (ref "IC5") (pin "26") (pinfunction "26_26") (pintype "passive"))
      (node (ref "IC6") (pin "26") (pinfunction "26_26") (pintype "passive"))
      (node (ref "IC7") (pin "26") (pinfunction "26_26") (pintype "passive"))
      (node (ref "IC8") (pin "26") (pinfunction "26_26") (pintype "passive"))
    )
    (net (code "69") (name "Net-(IC5-Pad27)") (class "Default")
      (node (ref "IC5") (pin "27") (pinfunction "27_27") (pintype "passive"))
      (node (ref "IC6") (pin "27") (pinfunction "27_27") (pintype "passive"))
      (node (ref "IC7") (pin "27") (pinfunction "27_27") (pintype "passive"))
      (node (ref "IC8") (pin "27") (pinfunction "27_27") (pintype "passive"))
    )
    (net (code "70") (name "Net-(IC5-Pad28)") (class "Default")
      (node (ref "IC5") (pin "28") (pinfunction "28_28") (pintype "passive"))
      (node (ref "IC6") (pin "28") (pinfunction "28_28") (pintype "passive"))
      (node (ref "IC7") (pin "28") (pinfunction "28_28") (pintype "passive"))
      (node (ref "IC8") (pin "28") (pinfunction "28_28") (pintype "passive"))
    )
    (net (code "71") (name "Net-(IC5-Pad29)") (class "Default")
      (node (ref "IC5") (pin "29") (pinfunction "29_29") (pintype "passive"))
      (node (ref "IC6") (pin "29") (pinfunction "29_29") (pintype "passive"))
      (node (ref "IC7") (pin "29") (pinfunction "29_29") (pintype "passive"))
      (node (ref "IC8") (pin "29") (pinfunction "29_29") (pintype "passive"))
    )
    (net (code "72") (name "Net-(IC5-Pad30)") (class "Default")
      (node (ref "IC5") (pin "30") (pinfunction "30_30") (pintype "passive"))
      (node (ref "IC6") (pin "30") (pinfunction "30_30") (pintype "passive"))
      (node (ref "IC7") (pin "30") (pinfunction "30_30") (pintype "passive"))
      (node (ref "IC8") (pin "30") (pinfunction "30_30") (pintype "passive"))
    )
    (net (code "73") (name "Net-(IC5-Pad31)") (class "Default")
      (node (ref "IC5") (pin "31") (pinfunction "31_31") (pintype "passive"))
      (node (ref "IC6") (pin "31") (pinfunction "31_31") (pintype "passive"))
      (node (ref "IC7") (pin "31") (pinfunction "31_31") (pintype "passive"))
      (node (ref "IC8") (pin "31") (pinfunction "31_31") (pintype "passive"))
    )
    (net (code "74") (name "Net-(IC5-Pad32)") (class "Default")
      (node (ref "IC5") (pin "32") (pinfunction "32_32") (pintype "passive"))
      (node (ref "IC6") (pin "32") (pinfunction "32_32") (pintype "passive"))
      (node (ref "IC7") (pin "32") (pinfunction "32_32") (pintype "passive"))
      (node (ref "IC8") (pin "32") (pinfunction "32_32") (pintype "passive"))
    )
    (net (code "75") (name "Net-(IC5-Pad33)") (class "Default")
      (node (ref "IC5") (pin "33") (pinfunction "33_33") (pintype "passive"))
      (node (ref "IC6") (pin "33") (pinfunction "33_33") (pintype "passive"))
      (node (ref "IC7") (pin "33") (pinfunction "33_33") (pintype "passive"))
      (node (ref "IC8") (pin "33") (pinfunction "33_33") (pintype "passive"))
    )
    (net (code "76") (name "Net-(IC5-Pad34)") (class "Default")
      (node (ref "IC5") (pin "34") (pinfunction "34_34") (pintype "passive"))
      (node (ref "IC6") (pin "34") (pinfunction "34_34") (pintype "passive"))
      (node (ref "IC7") (pin "34") (pinfunction "34_34") (pintype "passive"))
      (node (ref "IC8") (pin "34") (pinfunction "34_34") (pintype "passive"))
    )
    (net (code "77") (name "Net-(IC5-Pad35)") (class "Default")
      (node (ref "IC5") (pin "35") (pinfunction "35_35") (pintype "passive"))
      (node (ref "IC6") (pin "35") (pinfunction "35_35") (pintype "passive"))
      (node (ref "IC7") (pin "35") (pinfunction "35_35") (pintype "passive"))
      (node (ref "IC8") (pin "35") (pinfunction "35_35") (pintype "passive"))
    )
    (net (code "78") (name "Net-(IC5-Pad36)") (class "Default")
      (node (ref "IC5") (pin "36") (pinfunction "36_36") (pintype "passive"))
      (node (ref "IC6") (pin "36") (pinfunction "36_36") (pintype "passive"))
      (node (ref "IC7") (pin "36") (pinfunction "36_36") (pintype "passive"))
      (node (ref "IC8") (pin "36") (pinfunction "36_36") (pintype "passive"))
    )
    (net (code "79") (name "Net-(IC5-Pad37)") (class "Default")
      (node (ref "IC5") (pin "37") (pinfunction "37_37") (pintype "passive"))
      (node (ref "IC6") (pin "37") (pinfunction "37_37") (pintype "passive"))
      (node (ref "IC7") (pin "37") (pinfunction "37_37") (pintype "passive"))
      (node (ref "IC8") (pin "37") (pinfunction "37_37") (pintype "passive"))
    )
    (net (code "80") (name "Net-(IC5-Pad38)") (class "Default")
      (node (ref "IC5") (pin "38") (pinfunction "38_38") (pintype "passive"))
      (node (ref "IC6") (pin "38") (pinfunction "38_38") (pintype "passive"))
      (node (ref "IC7") (pin "38") (pinfunction "38_38") (pintype "passive"))
      (node (ref "IC8") (pin "38") (pinfunction "38_38") (pintype "passive"))
    )
    (net (code "81") (name "Net-(IC5-Pad39)") (class "Default")
      (node (ref "IC5") (pin "39") (pinfunction "39_39") (pintype "passive"))
      (node (ref "IC6") (pin "39") (pinfunction "39_39") (pintype "passive"))
      (node (ref "IC7") (pin "39") (pinfunction "39_39") (pintype "passive"))
      (node (ref "IC8") (pin "39") (pinfunction "39_39") (pintype "passive"))
    )
    (net (code "82") (name "Net-(IC5-Pad40)") (class "Default")
      (node (ref "IC5") (pin "40") (pinfunction "40_40") (pintype "passive"))
      (node (ref "IC6") (pin "40") (pinfunction "40_40") (pintype "passive"))
      (node (ref "IC7") (pin "40") (pinfunction "40_40") (pintype "passive"))
      (node (ref "IC8") (pin "40") (pinfunction "40_40") (pintype "passive"))
    )
    (net (code "83") (name "Net-(IC5-Pad41)") (class "Default")
      (node (ref "IC5") (pin "41") (pinfunction "41_41") (pintype "passive"))
      (node (ref "IC6") (pin "41") (pinfunction "41_41") (pintype "passive"))
      (node (ref "IC7") (pin "41") (pinfunction "41_41") (pintype "passive"))
      (node (ref "IC8") (pin "41") (pinfunction "41_41") (pintype "passive"))
    )
    (net (code "84") (name "Net-(IC5-Pad42)") (class "Default")
      (node (ref "IC5") (pin "42") (pinfunction "42_42") (pintype "passive"))
      (node (ref "IC6") (pin "42") (pinfunction "42_42") (pintype "passive"))
      (node (ref "IC7") (pin "42") (pinfunction "42_42") (pintype "passive"))
      (node (ref "IC8") (pin "42") (pinfunction "42_42") (pintype "passive"))
    )
    (net (code "85") (name "Net-(IC10-Pad1)") (class "Default")
      (node (ref "IC10") (pin "1") (pinfunction "1_1") (pintype "passive"))
      (node (ref "IC11") (pin "1") (pinfunction "1_1") (pintype "passive"))
      (node (ref "IC12") (pin "1") (pinfunction "1_1") (pintype "passive"))
      (node (ref "IC9") (pin "1") (pinfunction "1_1") (pintype "passive"))
    )
    (net (code "86") (name "Net-(IC10-Pad2)") (class "Default")
      (node (ref "IC10") (pin "2") (pinfunction "2_2") (pintype "passive"))
      (node (ref "IC11") (pin "2") (pinfunction "2_2") (pintype "passive"))
      (node (ref "IC12") (pin "2") (pinfunction "2_2") (pintype "passive"))
      (node (ref "IC9") (pin "2") (pinfunction "2_2") (pintype "passive"))
    )
    (net (code "87") (name "Net-(IC10-Pad3)") (class "Default")
      (node (ref "IC10") (pin "3") (pinfunction "3_3") (pintype "passive"))
      (node (ref "IC11") (pin "3") (pinfunction "3_3") (pintype "passive"))
      (node (ref "IC12") (pin "3") (pinfunction "3_3") (pintype "passive"))
      (node (ref "IC9") (pin "3") (pinfunction "3_3") (pintype "passive"))
    )
    (net (code "88") (name "Net-(IC10-Pad4)") (class "Default")
      (node (ref "IC10") (pin "4") (pinfunction "4_4") (pintype "passive"))
      (node (ref "IC11") (pin "4") (pinfunction "4_4") (pintype "passive"))
      (node (ref "IC12") (pin "4") (pinfunction "4_4") (pintype "passive"))
      (node (ref "IC9") (pin "4") (pinfunction "4_4") (pintype "passive"))
    )
    (net (code "89") (name "Net-(IC10-Pad5)") (class "Default")
      (node (ref "IC10") (pin "5") (pinfunction "5_5") (pintype "passive"))
      (node (ref "IC11") (pin "5") (pinfunction "5_5") (pintype "passive"))
      (node (ref "IC12") (pin "5") (pinfunction "5_5") (pintype "passive"))
      (node (ref "IC9") (pin "5") (pinfunction "5_5") (pintype "passive"))
    )
    (net (code "90") (name "Net-(IC10-Pad6)") (class "Default")
      (node (ref "IC10") (pin "6") (pinfunction "6_6") (pintype "passive"))
      (node (ref "IC11") (pin "6") (pinfunction "6_6") (pintype "passive"))
      (node (ref "IC12") (pin "6") (pinfunction "6_6") (pintype "passive"))
      (node (ref "IC9") (pin "6") (pinfunction "6_6") (pintype "passive"))
    )
    (net (code "91") (name "Net-(IC10-Pad7)") (class "Default")
      (node (ref "IC10") (pin "7") (pinfunction "7_7") (pintype "passive"))
      (node (ref "IC11") (pin "7") (pinfunction "7_7") (pintype "passive"))
      (node (ref "IC12") (pin "7") (pinfunction "7_7") (pintype "passive"))
      (node (ref "IC9") (pin "7") (pinfunction "7_7") (pintype "passive"))
    )
    (net (code "92") (name "Net-(IC10-Pad8)") (class "Default")
      (node (ref "IC10") (pin "8") (pinfunction "8_8") (pintype "passive"))
      (node (ref "IC11") (pin "8") (pinfunction "8_8") (pintype "passive"))
      (node (ref "IC12") (pin "8") (pinfunction "8_8") (pintype "passive"))
      (node (ref "IC9") (pin "8") (pinfunction "8_8") (pintype "passive"))
    )
    (net (code "93") (name "Net-(IC10-Pad9)") (class "Default")
      (node (ref "IC10") (pin "9") (pinfunction "9_9") (pintype "passive"))
      (node (ref "IC11") (pin "9") (pinfunction "9_9") (pintype "passive"))
      (node (ref "IC12") (pin "9") (pinfunction "9_9") (pintype "passive"))
      (node (ref "IC9") (pin "9") (pinfunction "9_9") (pintype "passive"))
    )
    (net (code "94") (name "Net-(IC10-Pad10)") (class "Default")
      (node (ref "IC10") (pin "10") (pinfunction "10_10") (pintype "passive"))
      (node (ref "IC11") (pin "10") (pinfunction "10_10") (pintype "passive"))
      (node (ref "IC12") (pin "10") (pinfunction "10_10") (pintype "passive"))
      (node (ref "IC9") (pin "10") (pinfunction "10_10") (pintype "passive"))
    )
    (net (code "95") (name "Net-(IC10-Pad11)") (class "Default")
      (node (ref "IC10") (pin "11") (pinfunction "11_11") (pintype "passive"))
      (node (ref "IC11") (pin "11") (pinfunction "11_11") (pintype "passive"))
      (node (ref "IC12") (pin "11") (pinfunction "11_11") (pintype "passive"))
      (node (ref "IC9") (pin "11") (pinfunction "11_11") (pintype "passive"))
    )
    (net (code "96") (name "Net-(IC10-Pad12)") (class "Default")
      (node (ref "IC10") (pin "12") (pinfunction "12_12") (pintype "passive"))
      (node (ref "IC11") (pin "12") (pinfunction "12_12") (pintype "passive"))
      (node (ref "IC12") (pin "12") (pinfunction "12_12") (pintype "passive"))
      (node (ref "IC9") (pin "12") (pinfunction "12_12") (pintype "passive"))
    )
    (net (code "97") (name "Net-(IC10-Pad13)") (class "Default")
      (node (ref "IC10") (pin "13") (pinfunction "13_13") (pintype "passive"))
      (node (ref "IC11") (pin "13") (pinfunction "13_13") (pintype "passive"))
      (node (ref "IC12") (pin "13") (pinfunction "13_13") (pintype "passive"))
      (node (ref "IC9") (pin "13") (pinfunction "13_13") (pintype "passive"))
    )
    (net (code "98") (name "Net-(IC10-Pad14)") (class "Default")
      (node (ref "IC10") (pin "14") (pinfunction "14_14") (pintype "passive"))
      (node (ref "IC11") (pin "14") (pinfunction "14_14") (pintype "passive"))
      (node (ref "IC12") (pin "14") (pinfunction "14_14") (pintype "passive"))
      (node (ref "IC9") (pin "14") (pinfunction "14_14") (pintype "passive"))
    )
    (net (code "99") (name "Net-(IC10-Pad15)") (class "Default")
      (node (ref "IC10") (pin "15") (pinfunction "15_15") (pintype "passive"))
      (node (ref "IC11") (pin "15") (pinfunction "15_15") (pintype "passive"))
      (node (ref "IC12") (pin "15") (pinfunction "15_15") (pintype "passive"))
      (node (ref "IC9") (pin "15") (pinfunction "15_15") (pintype "passive"))
    )
    (net (code "100") (name "Net-(IC10-Pad16)") (class "Default")
      (node (ref "IC10") (pin "16") (pinfunction "16_16") (pintype "passive"))
      (node (ref "IC11") (pin "16") (pinfunction "16_16") (pintype "passive"))
      (node (ref "IC12") (pin "16") (pinfunction "16_16") (pintype "passive"))
      (node (ref "IC9") (pin "16") (pinfunction "16_16") (pintype "passive"))
    )
    (net (code "101") (name "Net-(IC10-Pad17)") (class "Default")
      (node (ref "IC10") (pin "17") (pinfunction "17_17") (pintype "passive"))
      (node (ref "IC11") (pin "17") (pinfunction "17_17") (pintype "passive"))
      (node (ref "IC12") (pin "17") (pinfunction "17_17") (pintype "passive"))
      (node (ref "IC9") (pin "17") (pinfunction "17_17") (pintype "passive"))
    )
    (net (code "102") (name "Net-(IC10-Pad18)") (class "Default")
      (node (ref "IC10") (pin "18") (pinfunction "18_18") (pintype "passive"))
      (node (ref "IC11") (pin "18") (pinfunction "18_18") (pintype "passive"))
      (node (ref "IC12") (pin "18") (pinfunction "18_18") (pintype "passive"))
      (node (ref "IC9") (pin "18") (pinfunction "18_18") (pintype "passive"))
    )
    (net (code "103") (name "Net-(IC10-Pad19)") (class "Default")
      (node (ref "IC10") (pin "19") (pinfunction "19_19") (pintype "passive"))
      (node (ref "IC11") (pin "19") (pinfunction "19_19") (pintype "passive"))
      (node (ref "IC12") (pin "19") (pinfunction "19_19") (pintype "passive"))
      (node (ref "IC9") (pin "19") (pinfunction "19_19") (pintype "passive"))
    )
    (net (code "104") (name "Net-(IC10-Pad20)") (class "Default")
      (node (ref "IC10") (pin "20") (pinfunction "20_20") (pintype "passive"))
      (node (ref "IC11") (pin "20") (pinfunction "20_20") (pintype "passive"))
      (node (ref "IC12") (pin "20") (pinfunction "20_20") (pintype "passive"))
      (node (ref "IC9") (pin "20") (pinfunction "20_20") (pintype "passive"))
    )
    (net (code "105") (name "Net-(IC10-Pad21)") (class "Default")
      (node (ref "IC10") (pin "21") (pinfunction "21_21") (pintype "passive"))
      (node (ref "IC11") (pin "21") (pinfunction "21_21") (pintype "passive"))
      (node (ref "IC12") (pin "21") (pinfunction "21_21") (pintype "passive"))
      (node (ref "IC9") (pin "21") (pinfunction "21_21") (pintype "passive"))
    )
    (net (code "106") (name "Net-(IC10-Pad22)") (class "Default")
      (node (ref "IC10") (pin "22") (pinfunction "22_22") (pintype "passive"))
      (node (ref "IC11") (pin "22") (pinfunction "22_22") (pintype "passive"))
      (node (ref "IC12") (pin "22") (pinfunction "22_22") (pintype "passive"))
      (node (ref "IC9") (pin "22") (pinfunction "22_22") (pintype "passive"))
    )
    (net (code "107") (name "Net-(IC10-Pad23)") (class "Default")
      (node (ref "IC10") (pin "23") (pinfunction "23_23") (pintype "passive"))
      (node (ref "IC11") (pin "23") (pinfunction "23_23") (pintype "passive"))
      (node (ref "IC12") (pin "23") (pinfunction "23_23") (pintype "passive"))
      (node (ref "IC9") (pin "23") (pinfunction "23_23") (pintype "passive"))
    )
    (net (code "108") (name "Net-(IC10-Pad24)") (class "Default")
      (node (ref "IC10") (pin "24") (pinfunction "24_24") (pintype "passive"))
      (node (ref "IC11") (pin "24") (pinfunction "24_24") (pintype "passive"))
      (node (ref "IC12") (pin "24") (pinfunction "24_24") (pintype "passive"))
      (node (ref "IC9") (pin "24") (pinfunction "24_24") (pintype "passive"))
    )
    (net (code "109") (name "Net-(IC10-Pad25)") (class "Default")
      (node (ref "IC10") (pin "25") (pinfunction "25_25") (pintype "passive"))
      (node (ref "IC11") (pin "25") (pinfunction "25_25") (pintype "passive"))
      (node (ref "IC12") (pin "25") (pinfunction "25_25") (pintype "passive"))
      (node (ref "IC9") (pin "25") (pinfunction "25_25") (pintype "passive"))
    )
    (net (code "110") (name "Net-(IC10-Pad26)") (class "Default")
      (node (ref "IC10") (pin "26") (pinfunction "26_26") (pintype "passive"))
      (node (ref "IC11") (pin "26") (pinfunction "26_26") (pintype "passive"))
      (node (ref "IC12") (pin "26") (pinfunction "26_26") (pintype "passive"))
      (node (ref "IC9") (pin "26") (pinfunction "26_26") (pintype "passive"))
    )
    (net (code "111") (name "Net-(IC10-Pad27)") (class "Default")
      (node (ref "IC10") (pin "27") (pinfunction "27_27") (pintype "passive"))
      (node (ref "IC11") (pin "27") (pinfunction "27_27") (pintype "passive"))
      (node (ref "IC12") (pin "27") (pinfunction "27_27") (pintype "passive"))
      (node (ref "IC9") (pin "27") (pinfunction "27_27") (pintype "passive"))
    )
    (net (code "112") (name "Net-(IC10-Pad28)") (class "Default")
      (node (ref "IC10") (pin "28") (pinfunction "28_28") (pintype "passive"))
      (node (ref "IC11") (pin "28") (pinfunction "28_28") (pintype "passive"))
      (node (ref "IC12") (pin "28") (pinfunction "28_28") (pintype "passive"))
      (node (ref "IC9") (pin "28") (pinfunction "28_28") (pintype "passive"))
    )
    (net (code "113") (name "Net-(IC10-Pad29)") (class "Default")
      (node (ref "IC10") (pin "29") (pinfunction "29_29") (pintype "passive"))
      (node (ref "IC11") (pin "29") (pinfunction "29_29") (pintype "passive"))
      (node (ref "IC12") (pin "29") (pinfunction "29_29") (pintype "passive"))
      (node (ref "IC9") (pin "29") (pinfunction "29_29") (pintype "passive"))
    )
    (net (code "114") (name "Net-(IC10-Pad30)") (class "Default")
      (node (ref "IC10") (pin "30") (pinfunction "30_30") (pintype "passive"))
      (node (ref "IC11") (pin "30") (pinfunction "30_30") (pintype "passive"))
      (node (ref "IC12") (pin "30") (pinfunction "30_30") (pintype "passive"))
      (node (ref "IC9") (pin "30") (pinfunction "30_30") (pintype "passive"))
    )
    (net (code "115") (name "Net-(IC10-Pad31)") (class "Default")
      (node (ref "IC10") (pin "31") (pinfunction "31_31") (pintype "passive"))
      (node (ref "IC11") (pin "31") (pinfunction "31_31") (pintype "passive"))
      (node (ref "IC12") (pin "31") (pinfunction "31_31") (pintype "passive"))
      (node (ref "IC9") (pin "31") (pinfunction "31_31") (pintype "passive"))
    )
    (net (code "116") (name "Net-(IC10-Pad32)") (class "Default")
      (node (ref "IC10") (pin "32") (pinfunction "32_32") (pintype "passive"))
      (node (ref "IC11") (pin "32") (pinfunction "32_32") (pintype "passive"))
      (node (ref "IC12") (pin "32") (pinfunction "32_32") (pintype "passive"))
      (node (ref "IC9") (pin "32") (pinfunction "32_32") (pintype "passive"))
    )
    (net (code "117") (name "Net-(IC10-Pad33)") (class "Default")
      (node (ref "IC10") (pin "33") (pinfunction "33_33") (pintype "passive"))
      (node (ref "IC11") (pin "33") (pinfunction "33_33") (pintype "passive"))
      (node (ref "IC12") (pin "33") (pinfunction "33_33") (pintype "passive"))
      (node (ref "IC9") (pin "33") (pinfunction "33_33") (pintype "passive"))
    )
    (net (code "118") (name "Net-(IC10-Pad34)") (class "Default")
      (node (ref "IC10") (pin "34") (pinfunction "34_34") (pintype "passive"))
      (node (ref "IC11") (pin "34") (pinfunction "34_34") (pintype "passive"))
      (node (ref "IC12") (pin "34") (pinfunction "34_34") (pintype "passive"))
      (node (ref "IC9") (pin "34") (pinfunction "34_34") (pintype "passive"))
    )
    (net (code "119") (name "Net-(IC10-Pad35)") (class "Default")
      (node (ref "IC10") (pin "35") (pinfunction "35_35") (pintype "passive"))
      (node (ref "IC11") (pin "35") (pinfunction "35_35") (pintype "passive"))
      (node (ref "IC12") (pin "35") (pinfunction "35_35") (pintype "passive"))
      (node (ref "IC9") (pin "35") (pinfunction "35_35") (pintype "passive"))
    )
    (net (code "120") (name "Net-(IC10-Pad36)") (class "Default")
      (node (ref "IC10") (pin "36") (pinfunction "36_36") (pintype "passive"))
      (node (ref "IC11") (pin "36") (pinfunction "36_36") (pintype "passive"))
      (node (ref "IC12") (pin "36") (pinfunction "36_36") (pintype "passive"))
      (node (ref "IC9") (pin "36") (pinfunction "36_36") (pintype "passive"))
    )
    (net (code "121") (name "Net-(IC10-Pad37)") (class "Default")
      (node (ref "IC10") (pin "37") (pinfunction "37_37") (pintype "passive"))
      (node (ref "IC11") (pin "37") (pinfunction "37_37") (pintype "passive"))
      (node (ref "IC12") (pin "37") (pinfunction "37_37") (pintype "passive"))
      (node (ref "IC9") (pin "37") (pinfunction "37_37") (pintype "passive"))
    )
    (net (code "122") (name "Net-(IC10-Pad38)") (class "Default")
      (node (ref "IC10") (pin "38") (pinfunction "38_38") (pintype "passive"))
      (node (ref "IC11") (pin "38") (pinfunction "38_38") (pintype "passive"))
      (node (ref "IC12") (pin "38") (pinfunction "38_38") (pintype "passive"))
      (node (ref "IC9") (pin "38") (pinfunction "38_38") (pintype "passive"))
    )
    (net (code "123") (name "Net-(IC10-Pad39)") (class "Default")
      (node (ref "IC10") (pin "39") (pinfunction "39_39") (pintype "passive"))
      (node (ref "IC11") (pin "39") (pinfunction "39_39") (pintype "passive"))
      (node (ref "IC12") (pin "39") (pinfunction "39_39") (pintype "passive"))
      (node (ref "IC9") (pin "39") (pinfunction "39_39") (pintype "passive"))
    )
    (net (code "124") (name "Net-(IC10-Pad40)") (class "Default")
      (node (ref "IC10") (pin "40") (pinfunction "40_40") (pintype "passive"))
      (node (ref "IC11") (pin "40") (pinfunction "40_40") (pintype "passive"))
      (node (ref "IC12") (pin "40") (pinfunction "40_40") (pintype "passive"))
      (node (ref "IC9") (pin "40") (pinfunction "40_40") (pintype "passive"))
    )
    (net (code "125") (name "Net-(IC10-Pad41)") (class "Default")
      (node (ref "IC10") (pin "41") (pinfunction "41_41") (pintype "passive"))
      (node (ref "IC11") (pin "41") (pinfunction "41_41") (pintype "passive"))
      (node (ref "IC12") (pin "41") (pinfunction "41_41") (pintype "passive"))
      (node (ref "IC9") (pin "41") (pinfunction "41_41") (pintype "passive"))
    )
    (net (code "126") (name "Net-(IC10-Pad42)") (class "Default")
      (node (ref "IC10") (pin "42") (pinfunction "42_42") (pintype "passive"))
      (node (ref "IC11") (pin "42") (pinfunction "42_42") (pintype "passive"))
      (node (ref "IC12") (pin "42") (pinfunction "42_42") (pintype "passive"))
      (node (ref "IC9") (pin "42") (pinfunction "42_42") (pintype "passive"))
    )
    (net (code "127") (name "Net-(IC13-Pad1)") (class "Default")
      (node (ref "IC13") (pin "1") (pinfunction "1_1") (pintype "passive"))
      (node (ref "IC14") (pin "1") (pinfunction "1_1") (pintype "passive"))
      (node (ref "IC15") (pin "1") (pinfunction "1_1") (pintype "passive"))
      (node (ref "IC16") (pin "1") (pinfunction "1_1") (pintype "passive"))
    )
    (net (code "128") (name "Net-(IC13-Pad2)") (class "Default")
      (node (ref "IC13") (pin "2") (pinfunction "2_2") (pintype "passive"))
      (node (ref "IC14") (pin "2") (pinfunction "2_2") (pintype "passive"))
      (node (ref "IC15") (pin "2") (pinfunction "2_2") (pintype "passive"))
      (node (ref "IC16") (pin "2") (pinfunction "2_2") (pintype "passive"))
    )
    (net (code "129") (name "Net-(IC13-Pad3)") (class "Default")
      (node (ref "IC13") (pin "3") (pinfunction "3_3") (pintype "passive"))
      (node (ref "IC14") (pin "3") (pinfunction "3_3") (pintype "passive"))
      (node (ref "IC15") (pin "3") (pinfunction "3_3") (pintype "passive"))
      (node (ref "IC16") (pin "3") (pinfunction "3_3") (pintype "passive"))
    )
    (net (code "130") (name "Net-(IC13-Pad4)") (class "Default")
      (node (ref "IC13") (pin "4") (pinfunction "4_4") (pintype "passive"))
      (node (ref "IC14") (pin "4") (pinfunction "4_4") (pintype "passive"))
      (node (ref "IC15") (pin "4") (pinfunction "4_4") (pintype "passive"))
      (node (ref "IC16") (pin "4") (pinfunction "4_4") (pintype "passive"))
    )
    (net (code "131") (name "Net-(IC13-Pad5)") (class "Default")
      (node (ref "IC13") (pin "5") (pinfunction "5_5") (pintype "passive"))
      (node (ref "IC14") (pin "5") (pinfunction "5_5") (pintype "passive"))
      (node (ref "IC15") (pin "5") (pinfunction "5_5") (pintype "passive"))
      (node (ref "IC16") (pin "5") (pinfunction "5_5") (pintype "passive"))
    )
    (net (code "132") (name "Net-(IC13-Pad6)") (class "Default")
      (node (ref "IC13") (pin "6") (pinfunction "6_6") (pintype "passive"))
      (node (ref "IC14") (pin "6") (pinfunction "6_6") (pintype "passive"))
      (node (ref "IC15") (pin "6") (pinfunction "6_6") (pintype "passive"))
      (node (ref "IC16") (pin "6") (pinfunction "6_6") (pintype "passive"))
    )
    (net (code "133") (name "Net-(IC13-Pad7)") (class "Default")
      (node (ref "IC13") (pin "7") (pinfunction "7_7") (pintype "passive"))
      (node (ref "IC14") (pin "7") (pinfunction "7_7") (pintype "passive"))
      (node (ref "IC15") (pin "7") (pinfunction "7_7") (pintype "passive"))
      (node (ref "IC16") (pin "7") (pinfunction "7_7") (pintype "passive"))
    )
    (net (code "134") (name "Net-(IC13-Pad8)") (class "Default")
      (node (ref "IC13") (pin "8") (pinfunction "8_8") (pintype "passive"))
      (node (ref "IC14") (pin "8") (pinfunction "8_8") (pintype "passive"))
      (node (ref "IC15") (pin "8") (pinfunction "8_8") (pintype "passive"))
      (node (ref "IC16") (pin "8") (pinfunction "8_8") (pintype "passive"))
    )
    (net (code "135") (name "Net-(IC13-Pad9)") (class "Default")
      (node (ref "IC13") (pin "9") (pinfunction "9_9") (pintype "passive"))
      (node (ref "IC14") (pin "9") (pinfunction "9_9") (pintype "passive"))
      (node (ref "IC15") (pin "9") (pinfunction "9_9") (pintype "passive"))
      (node (ref "IC16") (pin "9") (pinfunction "9_9") (pintype "passive"))
    )
    (net (code "136") (name "Net-(IC13-Pad10)") (class "Default")
      (node (ref "IC13") (pin "10") (pinfunction "10_10") (pintype "passive"))
      (node (ref "IC14") (pin "10") (pinfunction "10_10") (pintype "passive"))
      (node (ref "IC15") (pin "10") (pinfunction "10_10") (pintype "passive"))
      (node (ref "IC16") (pin "10") (pinfunction "10_10") (pintype "passive"))
    )
    (net (code "137") (name "Net-(IC13-Pad11)") (class "Default")
      (node (ref "IC13") (pin "11") (pinfunction "11_11") (pintype "passive"))
      (node (ref "IC14") (pin "11") (pinfunction "11_11") (pintype "passive"))
      (node (ref "IC15") (pin "11") (pinfunction "11_11") (pintype "passive"))
      (node (ref "IC16") (pin "11") (pinfunction "11_11") (pintype "passive"))
    )
    (net (code "138") (name "Net-(IC13-Pad12)") (class "Default")
      (node (ref "IC13") (pin "12") (pinfunction "12_12") (pintype "passive"))
      (node (ref "IC14") (pin "12") (pinfunction "12_12") (pintype "passive"))
      (node (ref "IC15") (pin "12") (pinfunction "12_12") (pintype "passive"))
      (node (ref "IC16") (pin "12") (pinfunction "12_12") (pintype "passive"))
    )
    (net (code "139") (name "Net-(IC13-Pad13)") (class "Default")
      (node (ref "IC13") (pin "13") (pinfunction "13_13") (pintype "passive"))
      (node (ref "IC14") (pin "13") (pinfunction "13_13") (pintype "passive"))
      (node (ref "IC15") (pin "13") (pinfunction "13_13") (pintype "passive"))
      (node (ref "IC16") (pin "13") (pinfunction "13_13") (pintype "passive"))
    )
    (net (code "140") (name "Net-(IC13-Pad14)") (class "Default")
      (node (ref "IC13") (pin "14") (pinfunction "14_14") (pintype "passive"))
      (node (ref "IC14") (pin "14") (pinfunction "14_14") (pintype "passive"))
      (node (ref "IC15") (pin "14") (pinfunction "14_14") (pintype "passive"))
      (node (ref "IC16") (pin "14") (pinfunction "14_14") (pintype "passive"))
    )
    (net (code "141") (name "Net-(IC13-Pad15)") (class "Default")
      (node (ref "IC13") (pin "15") (pinfunction "15_15") (pintype "passive"))
      (node (ref "IC14") (pin "15") (pinfunction "15_15") (pintype "passive"))
      (node (ref "IC15") (pin "15") (pinfunction "15_15") (pintype "passive"))
      (node (ref "IC16") (pin "15") (pinfunction "15_15") (pintype "passive"))
    )
    (net (code "142") (name "Net-(IC13-Pad16)") (class "Default")
      (node (ref "IC13") (pin "16") (pinfunction "16_16") (pintype "passive"))
      (node (ref "IC14") (pin "16") (pinfunction "16_16") (pintype "passive"))
      (node (ref "IC15") (pin "16") (pinfunction "16_16") (pintype "passive"))
      (node (ref "IC16") (pin "16") (pinfunction "16_16") (pintype "passive"))
    )
    (net (code "143") (name "Net-(IC13-Pad17)") (class "Default")
      (node (ref "IC13") (pin "17") (pinfunction "17_17") (pintype "passive"))
      (node (ref "IC14") (pin "17") (pinfunction "17_17") (pintype "passive"))
      (node (ref "IC15") (pin "17") (pinfunction "17_17") (pintype "passive"))
      (node (ref "IC16") (pin "17") (pinfunction "17_17") (pintype "passive"))
    )
    (net (code "144") (name "Net-(IC13-Pad18)") (class "Default")
      (node (ref "IC13") (pin "18") (pinfunction "18_18") (pintype "passive"))
      (node (ref "IC14") (pin "18") (pinfunction "18_18") (pintype "passive"))
      (node (ref "IC15") (pin "18") (pinfunction "18_18") (pintype "passive"))
      (node (ref "IC16") (pin "18") (pinfunction "18_18") (pintype "passive"))
    )
    (net (code "145") (name "Net-(IC13-Pad19)") (class "Default")
      (node (ref "IC13") (pin "19") (pinfunction "19_19") (pintype "passive"))
      (node (ref "IC14") (pin "19") (pinfunction "19_19") (pintype "passive"))
      (node (ref "IC15") (pin "19") (pinfunction "19_19") (pintype "passive"))
      (node (ref "IC16") (pin "19") (pinfunction "19_19") (pintype "passive"))
    )
    (net (code "146") (name "Net-(IC13-Pad20)") (class "Default")
      (node (ref "IC13") (pin "20") (pinfunction "20_20") (pintype "passive"))
      (node (ref "IC14") (pin "20") (pinfunction "20_20") (pintype "passive"))
      (node (ref "IC15") (pin "20") (pinfunction "20_20") (pintype "passive"))
      (node (ref "IC16") (pin "20") (pinfunction "20_20") (pintype "passive"))
    )
    (net (code "147") (name "Net-(IC13-Pad21)") (class "Default")
      (node (ref "IC13") (pin "21") (pinfunction "21_21") (pintype "passive"))
      (node (ref "IC14") (pin "21") (pinfunction "21_21") (pintype "passive"))
      (node (ref "IC15") (pin "21") (pinfunction "21_21") (pintype "passive"))
      (node (ref "IC16") (pin "21") (pinfunction "21_21") (pintype "passive"))
    )
    (net (code "148") (name "Net-(IC13-Pad22)") (class "Default")
      (node (ref "IC13") (pin "22") (pinfunction "22_22") (pintype "passive"))
      (node (ref "IC14") (pin "22") (pinfunction "22_22") (pintype "passive"))
      (node (ref "IC15") (pin "22") (pinfunction "22_22") (pintype "passive"))
      (node (ref "IC16") (pin "22") (pinfunction "22_22") (pintype "passive"))
    )
    (net (code "149") (name "Net-(IC13-Pad23)") (class "Default")
      (node (ref "IC13") (pin "23") (pinfunction "23_23") (pintype "passive"))
      (node (ref "IC14") (pin "23") (pinfunction "23_23") (pintype "passive"))
      (node (ref "IC15") (pin "23") (pinfunction "23_23") (pintype "passive"))
      (node (ref "IC16") (pin "23") (pinfunction "23_23") (pintype "passive"))
    )
    (net (code "150") (name "Net-(IC13-Pad24)") (class "Default")
      (node (ref "IC13") (pin "24") (pinfunction "24_24") (pintype "passive"))
      (node (ref "IC14") (pin "24") (pinfunction "24_24") (pintype "passive"))
      (node (ref "IC15") (pin "24") (pinfunction "24_24") (pintype "passive"))
      (node (ref "IC16") (pin "24") (pinfunction "24_24") (pintype "passive"))
    )
    (net (code "151") (name "Net-(IC13-Pad25)") (class "Default")
      (node (ref "IC13") (pin "25") (pinfunction "25_25") (pintype "passive"))
      (node (ref "IC14") (pin "25") (pinfunction "25_25") (pintype "passive"))
      (node (ref "IC15") (pin "25") (pinfunction "25_25") (pintype "passive"))
      (node (ref "IC16") (pin "25") (pinfunction "25_25") (pintype "passive"))
    )
    (net (code "152") (name "Net-(IC13-Pad26)") (class "Default")
      (node (ref "IC13") (pin "26") (pinfunction "26_26") (pintype "passive"))
      (node (ref "IC14") (pin "26") (pinfunction "26_26") (pintype "passive"))
      (node (ref "IC15") (pin "26") (pinfunction "26_26") (pintype "passive"))
      (node (ref "IC16") (pin "26") (pinfunction "26_26") (pintype "passive"))
    )
    (net (code "153") (name "Net-(IC13-Pad27)") (class "Default")
      (node (ref "IC13") (pin "27") (pinfunction "27_27") (pintype "passive"))
      (node (ref "IC14") (pin "27") (pinfunction "27_27") (pintype "passive"))
      (node (ref "IC15") (pin "27") (pinfunction "27_27") (pintype "passive"))
      (node (ref "IC16") (pin "27") (pinfunction "27_27") (pintype "passive"))
    )
    (net (code "154") (name "Net-(IC13-Pad28)") (class "Default")
      (node (ref "IC13") (pin "28") (pinfunction "28_28") (pintype "passive"))
      (node (ref "IC14") (pin "28") (pinfunction "28_28") (pintype "passive"))
      (node (ref "IC15") (pin "28") (pinfunction "28_28") (pintype "passive"))
      (node (ref "IC16") (pin "28") (pinfunction "28_28") (pintype "passive"))
    )
    (net (code "155") (name "Net-(IC13-Pad29)") (class "Default")
      (node (ref "IC13") (pin "29") (pinfunction "29_29") (pintype "passive"))
      (node (ref "IC14") (pin "29") (pinfunction "29_29") (pintype "passive"))
      (node (ref "IC15") (pin "29") (pinfunction "29_29") (pintype "passive"))
      (node (ref "IC16") (pin "29") (pinfunction "29_29") (pintype "passive"))
    )
    (net (code "156") (name "Net-(IC13-Pad30)") (class "Default")
      (node (ref "IC13") (pin "30") (pinfunction "30_30") (pintype "passive"))
      (node (ref "IC14") (pin "30") (pinfunction "30_30") (pintype "passive"))
      (node (ref "IC15") (pin "30") (pinfunction "30_30") (pintype "passive"))
      (node (ref "IC16") (pin "30") (pinfunction "30_30") (pintype "passive"))
    )
    (net (code "157") (name "Net-(IC13-Pad31)") (class "Default")
      (node (ref "IC13") (pin "31") (pinfunction "31_31") (pintype "passive"))
      (node (ref "IC14") (pin "31") (pinfunction "31_31") (pintype "passive"))
      (node (ref "IC15") (pin "31") (pinfunction "31_31") (pintype "passive"))
      (node (ref "IC16") (pin "31") (pinfunction "31_31") (pintype "passive"))
    )
    (net (code "158") (name "Net-(IC13-Pad32)") (class "Default")
      (node (ref "IC13") (pin "32") (pinfunction "32_32") (pintype "passive"))
      (node (ref "IC14") (pin "32") (pinfunction "32_32") (pintype "passive"))
      (node (ref "IC15") (pin "32") (pinfunction "32_32") (pintype "passive"))
      (node (ref "IC16") (pin "32") (pinfunction "32_32") (pintype "passive"))
    )
    (net (code "159") (name "Net-(IC13-Pad33)") (class "Default")
      (node (ref "IC13") (pin "33") (pinfunction "33_33") (pintype "passive"))
      (node (ref "IC14") (pin "33") (pinfunction "33_33") (pintype "passive"))
      (node (ref "IC15") (pin "33") (pinfunction "33_33") (pintype "passive"))
      (node (ref "IC16") (pin "33") (pinfunction "33_33") (pintype "passive"))
    )
    (net (code "160") (name "Net-(IC13-Pad34)") (class "Default")
      (node (ref "IC13") (pin "34") (pinfunction "34_34") (pintype "passive"))
      (node (ref "IC14") (pin "34") (pinfunction "34_34") (pintype "passive"))
      (node (ref "IC15") (pin "34") (pinfunction "34_34") (pintype "passive"))
      (node (ref "IC16") (pin "34") (pinfunction "34_34") (pintype "passive"))
    )
    (net (code "161") (name "Net-(IC13-Pad35)") (class "Default")
      (node (ref "IC13") (pin "35") (pinfunction "35_35") (pintype "passive"))
      (node (ref "IC14") (pin "35") (pinfunction "35_35") (pintype "passive"))
      (node (ref "IC15") (pin "35") (pinfunction "35_35") (pintype "passive"))
      (node (ref "IC16") (pin "35") (pinfunction "35_35") (pintype "passive"))
    )
    (net (code "162") (name "Net-(IC13-Pad36)") (class "Default")
      (node (ref "IC13") (pin "36") (pinfunction "36_36") (pintype "passive"))
      (node (ref "IC14") (pin "36") (pinfunction "36_36") (pintype "passive"))
      (node (ref "IC15") (pin "36") (pinfunction "36_36") (pintype "passive"))
      (node (ref "IC16") (pin "36") (pinfunction "36_36") (pintype "passive"))
    )
    (net (code "163") (name "Net-(IC13-Pad37)") (class "Default")
      (node (ref "IC13") (pin "37") (pinfunction "37_37") (pintype "passive"))
      (node (ref "IC14") (pin "37") (pinfunction "37_37") (pintype "passive"))
      (node (ref "IC15") (pin "37") (pinfunction "37_37") (pintype "passive"))
      (node (ref "IC16") (pin "37") (pinfunction "37_37") (pintype "passive"))
    )
    (net (code "164") (name "Net-(IC13-Pad38)") (class "Default")
      (node (ref "IC13") (pin "38") (pinfunction "38_38") (pintype "passive"))
      (node (ref "IC14") (pin "38") (pinfunction "38_38") (pintype "passive"))
      (node (ref "IC15") (pin "38") (pinfunction "38_38") (pintype "passive"))
      (node (ref "IC16") (pin "38") (pinfunction "38_38") (pintype "passive"))
    )
    (net (code "165") (name "Net-(IC13-Pad39)") (class "Default")
      (node (ref "IC13") (pin "39") (pinfunction "39_39") (pintype "passive"))
      (node (ref "IC14") (pin "39") (pinfunction "39_39") (pintype "passive"))
      (node (ref "IC15") (pin "39") (pinfunction "39_39") (pintype "passive"))
      (node (ref "IC16") (pin "39") (pinfunction "39_39") (pintype "passive"))
    )
    (net (code "166") (name "Net-(IC13-Pad40)") (class "Default")
      (node (ref "IC13") (pin "40") (pinfunction "40_40") (pintype "passive"))
      (node (ref "IC14") (pin "40") (pinfunction "40_40") (pintype "passive"))
      (node (ref "IC15") (pin "40") (pinfunction "40_40") (pintype "passive"))
      (node (ref "IC16") (pin "40") (pinfunction "40_40") (pintype "passive"))
    )
    (net (code "167") (name "Net-(IC13-Pad41)") (class "Default")
      (node (ref "IC13") (pin "41") (pinfunction "41_41") (pintype "passive"))
      (node (ref "IC14") (pin "41") (pinfunction "41_41") (pintype "passive"))
      (node (ref "IC15") (pin "41") (pinfunction "41_41") (pintype "passive"))
      (node (ref "IC16") (pin "41") (pinfunction "41_41") (pintype "passive"))
    )
    (net (code "168") (name "Net-(IC13-Pad42)") (class "Default")
      (node (ref "IC13") (pin "42") (pinfunction "42_42") (pintype "passive"))
      (node (ref "IC14") (pin "42") (pinfunction "42_42") (pintype "passive"))
      (node (ref "IC15") (pin "42") (pinfunction "42_42") (pintype "passive"))
      (node (ref "IC16") (pin "42") (pinfunction "42_42") (pintype "passive"))
    )
    (net (code "169") (name "Net-(IC17-Pad1)") (class "Default")
      (node (ref "IC17") (pin "1") (pinfunction "1_1") (pintype "passive"))
      (node (ref "IC18") (pin "1") (pinfunction "1_1") (pintype "passive"))
      (node (ref "IC19") (pin "1") (pinfunction "1_1") (pintype "passive"))
      (node (ref "IC20") (pin "1") (pinfunction "1_1") (pintype "passive"))
    )
    (net (code "170") (name "Net-(IC17-Pad2)") (class "Default")
      (node (ref "IC17") (pin "2") (pinfunction "2_2") (pintype "passive"))
      (node (ref "IC18") (pin "2") (pinfunction "2_2") (pintype "passive"))
      (node (ref "IC19") (pin "2") (pinfunction "2_2") (pintype "passive"))
      (node (ref "IC20") (pin "2") (pinfunction "2_2") (pintype "passive"))
    )
    (net (code "171") (name "Net-(IC17-Pad3)") (class "Default")
      (node (ref "IC17") (pin "3") (pinfunction "3_3") (pintype "passive"))
      (node (ref "IC18") (pin "3") (pinfunction "3_3") (pintype "passive"))
      (node (ref "IC19") (pin "3") (pinfunction "3_3") (pintype "passive"))
      (node (ref "IC20") (pin "3") (pinfunction "3_3") (pintype "passive"))
    )
    (net (code "172") (name "Net-(IC17-Pad4)") (class "Default")
      (node (ref "IC17") (pin "4") (pinfunction "4_4") (pintype "passive"))
      (node (ref "IC18") (pin "4") (pinfunction "4_4") (pintype "passive"))
      (node (ref "IC19") (pin "4") (pinfunction "4_4") (pintype "passive"))
      (node (ref "IC20") (pin "4") (pinfunction "4_4") (pintype "passive"))
    )
    (net (code "173") (name "Net-(IC17-Pad5)") (class "Default")
      (node (ref "IC17") (pin "5") (pinfunction "5_5") (pintype "passive"))
      (node (ref "IC18") (pin "5") (pinfunction "5_5") (pintype "passive"))
      (node (ref "IC19") (pin "5") (pinfunction "5_5") (pintype "passive"))
      (node (ref "IC20") (pin "5") (pinfunction "5_5") (pintype "passive"))
    )
    (net (code "174") (name "Net-(IC17-Pad6)") (class "Default")
      (node (ref "IC17") (pin "6") (pinfunction "6_6") (pintype "passive"))
      (node (ref "IC18") (pin "6") (pinfunction "6_6") (pintype "passive"))
      (node (ref "IC19") (pin "6") (pinfunction "6_6") (pintype "passive"))
      (node (ref "IC20") (pin "6") (pinfunction "6_6") (pintype "passive"))
    )
    (net (code "175") (name "Net-(IC17-Pad7)") (class "Default")
      (node (ref "IC17") (pin "7") (pinfunction "7_7") (pintype "passive"))
      (node (ref "IC18") (pin "7") (pinfunction "7_7") (pintype "passive"))
      (node (ref "IC19") (pin "7") (pinfunction "7_7") (pintype "passive"))
      (node (ref "IC20") (pin "7") (pinfunction "7_7") (pintype "passive"))
    )
    (net (code "176") (name "Net-(IC17-Pad8)") (class "Default")
      (node (ref "IC17") (pin "8") (pinfunction "8_8") (pintype "passive"))
      (node (ref "IC18") (pin "8") (pinfunction "8_8") (pintype "passive"))
      (node (ref "IC19") (pin "8") (pinfunction "8_8") (pintype "passive"))
      (node (ref "IC20") (pin "8") (pinfunction "8_8") (pintype "passive"))
    )
    (net (code "177") (name "Net-(IC17-Pad9)") (class "Default")
      (node (ref "IC17") (pin "9") (pinfunction "9_9") (pintype "passive"))
      (node (ref "IC18") (pin "9") (pinfunction "9_9") (pintype "passive"))
      (node (ref "IC19") (pin "9") (pinfunction "9_9") (pintype "passive"))
      (node (ref "IC20") (pin "9") (pinfunction "9_9") (pintype "passive"))
    )
    (net (code "178") (name "Net-(IC17-Pad10)") (class "Default")
      (node (ref "IC17") (pin "10") (pinfunction "10_10") (pintype "passive"))
      (node (ref "IC18") (pin "10") (pinfunction "10_10") (pintype "passive"))
      (node (ref "IC19") (pin "10") (pinfunction "10_10") (pintype "passive"))
      (node (ref "IC20") (pin "10") (pinfunction "10_10") (pintype "passive"))
    )
    (net (code "179") (name "Net-(IC17-Pad11)") (class "Default")
      (node (ref "IC17") (pin "11") (pinfunction "11_11") (pintype "passive"))
      (node (ref "IC18") (pin "11") (pinfunction "11_11") (pintype "passive"))
      (node (ref "IC19") (pin "11") (pinfunction "11_11") (pintype "passive"))
      (node (ref "IC20") (pin "11") (pinfunction "11_11") (pintype "passive"))
    )
    (net (code "180") (name "Net-(IC17-Pad12)") (class "Default")
      (node (ref "IC17") (pin "12") (pinfunction "12_12") (pintype "passive"))
      (node (ref "IC18") (pin "12") (pinfunction "12_12") (pintype "passive"))
      (node (ref "IC19") (pin "12") (pinfunction "12_12") (pintype "passive"))
      (node (ref "IC20") (pin "12") (pinfunction "12_12") (pintype "passive"))
    )
    (net (code "181") (name "Net-(IC17-Pad13)") (class "Default")
      (node (ref "IC17") (pin "13") (pinfunction "13_13") (pintype "passive"))
      (node (ref "IC18") (pin "13") (pinfunction "13_13") (pintype "passive"))
      (node (ref "IC19") (pin "13") (pinfunction "13_13") (pintype "passive"))
      (node (ref "IC20") (pin "13") (pinfunction "13_13") (pintype "passive"))
    )
    (net (code "182") (name "Net-(IC17-Pad14)") (class "Default")
      (node (ref "IC17") (pin "14") (pinfunction "14_14") (pintype "passive"))
      (node (ref "IC18") (pin "14") (pinfunction "14_14") (pintype "passive"))
      (node (ref "IC19") (pin "14") (pinfunction "14_14") (pintype "passive"))
      (node (ref "IC20") (pin "14") (pinfunction "14_14") (pintype "passive"))
    )
    (net (code "183") (name "Net-(IC17-Pad15)") (class "Default")
      (node (ref "IC17") (pin "15") (pinfunction "15_15") (pintype "passive"))
      (node (ref "IC18") (pin "15") (pinfunction "15_15") (pintype "passive"))
      (node (ref "IC19") (pin "15") (pinfunction "15_15") (pintype "passive"))
      (node (ref "IC20") (pin "15") (pinfunction "15_15") (pintype "passive"))
    )
    (net (code "184") (name "Net-(IC17-Pad16)") (class "Default")
      (node (ref "IC17") (pin "16") (pinfunction "16_16") (pintype "passive"))
      (node (ref "IC18") (pin "16") (pinfunction "16_16") (pintype "passive"))
      (node (ref "IC19") (pin "16") (pinfunction "16_16") (pintype "passive"))
      (node (ref "IC20") (pin "16") (pinfunction "16_16") (pintype "passive"))
    )
    (net (code "185") (name "Net-(IC17-Pad17)") (class "Default")
      (node (ref "IC17") (pin "17") (pinfunction "17_17") (pintype "passive"))
      (node (ref "IC18") (pin "17") (pinfunction "17_17") (pintype "passive"))
      (node (ref "IC19") (pin "17") (pinfunction "17_17") (pintype "passive"))
      (node (ref "IC20") (pin "17") (pinfunction "17_17") (pintype "passive"))
    )
    (net (code "186") (name "Net-(IC17-Pad18)") (class "Default")
      (node (ref "IC17") (pin "18") (pinfunction "18_18") (pintype "passive"))
      (node (ref "IC18") (pin "18") (pinfunction "18_18") (pintype "passive"))
      (node (ref "IC19") (pin "18") (pinfunction "18_18") (pintype "passive"))
      (node (ref "IC20") (pin "18") (pinfunction "18_18") (pintype "passive"))
    )
    (net (code "187") (name "Net-(IC17-Pad19)") (class "Default")
      (node (ref "IC17") (pin "19") (pinfunction "19_19") (pintype "passive"))
      (node (ref "IC18") (pin "19") (pinfunction "19_19") (pintype "passive"))
      (node (ref "IC19") (pin "19") (pinfunction "19_19") (pintype "passive"))
      (node (ref "IC20") (pin "19") (pinfunction "19_19") (pintype "passive"))
    )
    (net (code "188") (name "Net-(IC17-Pad20)") (class "Default")
      (node (ref "IC17") (pin "20") (pinfunction "20_20") (pintype "passive"))
      (node (ref "IC18") (pin "20") (pinfunction "20_20") (pintype "passive"))
      (node (ref "IC19") (pin "20") (pinfunction "20_20") (pintype "passive"))
      (node (ref "IC20") (pin "20") (pinfunction "20_20") (pintype "passive"))
    )
    (net (code "189") (name "Net-(IC17-Pad21)") (class "Default")
      (node (ref "IC17") (pin "21") (pinfunction "21_21") (pintype "passive"))
      (node (ref "IC18") (pin "21") (pinfunction "21_21") (pintype "passive"))
      (node (ref "IC19") (pin "21") (pinfunction "21_21") (pintype "passive"))
      (node (ref "IC20") (pin "21") (pinfunction "21_21") (pintype "passive"))
    )
    (net (code "190") (name "Net-(IC17-Pad22)") (class "Default")
      (node (ref "IC17") (pin "22") (pinfunction "22_22") (pintype "passive"))
      (node (ref "IC18") (pin "22") (pinfunction "22_22") (pintype "passive"))
      (node (ref "IC19") (pin "22") (pinfunction "22_22") (pintype "passive"))
      (node (ref "IC20") (pin "22") (pinfunction "22_22") (pintype "passive"))
    )
    (net (code "191") (name "Net-(IC17-Pad23)") (class "Default")
      (node (ref "IC17") (pin "23") (pinfunction "23_23") (pintype "passive"))
      (node (ref "IC18") (pin "23") (pinfunction "23_23") (pintype "passive"))
      (node (ref "IC19") (pin "23") (pinfunction "23_23") (pintype "passive"))
      (node (ref "IC20") (pin "23") (pinfunction "23_23") (pintype "passive"))
    )
    (net (code "192") (name "Net-(IC17-Pad24)") (class "Default")
      (node (ref "IC17") (pin "24") (pinfunction "24_24") (pintype "passive"))
      (node (ref "IC18") (pin "24") (pinfunction "24_24") (pintype "passive"))
      (node (ref "IC19") (pin "24") (pinfunction "24_24") (pintype "passive"))
      (node (ref "IC20") (pin "24") (pinfunction "24_24") (pintype "passive"))
    )
    (net (code "193") (name "Net-(IC17-Pad25)") (class "Default")
      (node (ref "IC17") (pin "25") (pinfunction "25_25") (pintype "passive"))
      (node (ref "IC18") (pin "25") (pinfunction "25_25") (pintype "passive"))
      (node (ref "IC19") (pin "25") (pinfunction "25_25") (pintype "passive"))
      (node (ref "IC20") (pin "25") (pinfunction "25_25") (pintype "passive"))
    )
    (net (code "194") (name "Net-(IC17-Pad26)") (class "Default")
      (node (ref "IC17") (pin "26") (pinfunction "26_26") (pintype "passive"))
      (node (ref "IC18") (pin "26") (pinfunction "26_26") (pintype "passive"))
      (node (ref "IC19") (pin "26") (pinfunction "26_26") (pintype "passive"))
      (node (ref "IC20") (pin "26") (pinfunction "26_26") (pintype "passive"))
    )
    (net (code "195") (name "Net-(IC17-Pad27)") (class "Default")
      (node (ref "IC17") (pin "27") (pinfunction "27_27") (pintype "passive"))
      (node (ref "IC18") (pin "27") (pinfunction "27_27") (pintype "passive"))
      (node (ref "IC19") (pin "27") (pinfunction "27_27") (pintype "passive"))
      (node (ref "IC20") (pin "27") (pinfunction "27_27") (pintype "passive"))
    )
    (net (code "196") (name "Net-(IC17-Pad28)") (class "Default")
      (node (ref "IC17") (pin "28") (pinfunction "28_28") (pintype "passive"))
      (node (ref "IC18") (pin "28") (pinfunction "28_28") (pintype "passive"))
      (node (ref "IC19") (pin "28") (pinfunction "28_28") (pintype "passive"))
      (node (ref "IC20") (pin "28") (pinfunction "28_28") (pintype "passive"))
    )
    (net (code "197") (name "Net-(IC17-Pad29)") (class "Default")
      (node (ref "IC17") (pin "29") (pinfunction "29_29") (pintype "passive"))
      (node (ref "IC18") (pin "29") (pinfunction "29_29") (pintype "passive"))
      (node (ref "IC19") (pin "29") (pinfunction "29_29") (pintype "passive"))
      (node (ref "IC20") (pin "29") (pinfunction "29_29") (pintype "passive"))
    )
    (net (code "198") (name "Net-(IC17-Pad30)") (class "Default")
      (node (ref "IC17") (pin "30") (pinfunction "30_30") (pintype "passive"))
      (node (ref "IC18") (pin "30") (pinfunction "30_30") (pintype "passive"))
      (node (ref "IC19") (pin "30") (pinfunction "30_30") (pintype "passive"))
      (node (ref "IC20") (pin "30") (pinfunction "30_30") (pintype "passive"))
    )
    (net (code "199") (name "Net-(IC17-Pad31)") (class "Default")
      (node (ref "IC17") (pin "31") (pinfunction "31_31") (pintype "passive"))
      (node (ref "IC18") (pin "31") (pinfunction "31_31") (pintype "passive"))
      (node (ref "IC19") (pin "31") (pinfunction "31_31") (pintype "passive"))
      (node (ref "IC20") (pin "31") (pinfunction "31_31") (pintype "passive"))
    )
    (net (code "200") (name "Net-(IC17-Pad32)") (class "Default")
      (node (ref "IC17") (pin "32") (pinfunction "32_32") (pintype "passive"))
      (node (ref "IC18") (pin "32") (pinfunction "32_32") (pintype "passive"))
      (node (ref "IC19") (pin "32") (pinfunction "32_32") (pintype "passive"))
      (node (ref "IC20") (pin "32") (pinfunction "32_32") (pintype "passive"))
    )
    (net (code "201") (name "Net-(IC17-Pad33)") (class "Default")
      (node (ref "IC17") (pin "33") (pinfunction "33_33") (pintype "passive"))
      (node (ref "IC18") (pin "33") (pinfunction "33_33") (pintype "passive"))
      (node (ref "IC19") (pin "33") (pinfunction "33_33") (pintype "passive"))
      (node (ref "IC20") (pin "33") (pinfunction "33_33") (pintype "passive"))
    )
    (net (code "202") (name "Net-(IC17-Pad34)") (class "Default")
      (node (ref "IC17") (pin "34") (pinfunction "34_34") (pintype "passive"))
      (node (ref "IC18") (pin "34") (pinfunction "34_34") (pintype "passive"))
      (node (ref "IC19") (pin "34") (pinfunction "34_34") (pintype "passive"))
      (node (ref "IC20") (pin "34") (pinfunction "34_34") (pintype "passive"))
    )
    (net (code "203") (name "Net-(IC17-Pad35)") (class "Default")
      (node (ref "IC17") (pin "35") (pinfunction "35_35") (pintype "passive"))
      (node (ref "IC18") (pin "35") (pinfunction "35_35") (pintype "passive"))
      (node (ref "IC19") (pin "35") (pinfunction "35_35") (pintype "passive"))
      (node (ref "IC20") (pin "35") (pinfunction "35_35") (pintype "passive"))
    )
    (net (code "204") (name "Net-(IC17-Pad36)") (class "Default")
      (node (ref "IC17") (pin "36") (pinfunction "36_36") (pintype "passive"))
      (node (ref "IC18") (pin "36") (pinfunction "36_36") (pintype "passive"))
      (node (ref "IC19") (pin "36") (pinfunction "36_36") (pintype "passive"))
      (node (ref "IC20") (pin "36") (pinfunction "36_36") (pintype "passive"))
    )
    (net (code "205") (name "Net-(IC17-Pad37)") (class "Default")
      (node (ref "IC17") (pin "37") (pinfunction "37_37") (pintype "passive"))
      (node (ref "IC18") (pin "37") (pinfunction "37_37") (pintype "passive"))
      (node (ref "IC19") (pin "37") (pinfunction "37_37") (pintype "passive"))
      (node (ref "IC20") (pin "37") (pinfunction "37_37") (pintype "passive"))
    )
    (net (code "206") (name "Net-(IC17-Pad38)") (class "Default")
      (node (ref "IC17") (pin "38") (pinfunction "38_38") (pintype "passive"))
      (node (ref "IC18") (pin "38") (pinfunction "38_38") (pintype "passive"))
      (node (ref "IC19") (pin "38") (pinfunction "38_38") (pintype "passive"))
      (node (ref "IC20") (pin "38") (pinfunction "38_38") (pintype "passive"))
    )
    (net (code "207") (name "Net-(IC17-Pad39)") (class "Default")
      (node (ref "IC17") (pin "39") (pinfunction "39_39") (pintype "passive"))
      (node (ref "IC18") (pin "39") (pinfunction "39_39") (pintype "passive"))
      (node (ref "IC19") (pin "39") (pinfunction "39_39") (pintype "passive"))
      (node (ref "IC20") (pin "39") (pinfunction "39_39") (pintype "passive"))
    )
    (net (code "208") (name "Net-(IC17-Pad40)") (class "Default")
      (node (ref "IC17") (pin "40") (pinfunction "40_40") (pintype "passive"))
      (node (ref "IC18") (pin "40") (pinfunction "40_40") (pintype "passive"))
      (node (ref "IC19") (pin "40") (pinfunction "40_40") (pintype "passive"))
      (node (ref "IC20") (pin "40") (pinfunction "40_40") (pintype "passive"))
    )
    (net (code "209") (name "Net-(IC17-Pad41)") (class "Default")
      (node (ref "IC17") (pin "41") (pinfunction "41_41") (pintype "passive"))
      (node (ref "IC18") (pin "41") (pinfunction "41_41") (pintype "passive"))
      (node (ref "IC19") (pin "41") (pinfunction "41_41") (pintype "passive"))
      (node (ref "IC20") (pin "41") (pinfunction "41_41") (pintype "passive"))
    )
    (net (code "210") (name "Net-(IC17-Pad42)") (class "Default")
      (node (ref "IC17") (pin "42") (pinfunction "42_42") (pintype "passive"))
      (node (ref "IC18") (pin "42") (pinfunction "42_42") (pintype "passive"))
      (node (ref "IC19") (pin "42") (pinfunction "42_42") (pintype "passive"))
      (node (ref "IC20") (pin "42") (pinfunction "42_42") (pintype "passive"))
    )
    (net (code "211") (name "Net-(IC21-Pad1)") (class "Default")
      (node (ref "IC21") (pin "1") (pinfunction "1_1") (pintype "passive"))
      (node (ref "IC22") (pin "1") (pinfunction "1_1") (pintype "passive"))
      (node (ref "IC23") (pin "1") (pinfunction "1_1") (pintype "passive"))
      (node (ref "IC24") (pin "1") (pinfunction "1_1") (pintype "passive"))
    )
    (net (code "212") (name "Net-(IC21-Pad2)") (class "Default")
      (node (ref "IC21") (pin "2") (pinfunction "2_2") (pintype "passive"))
      (node (ref "IC22") (pin "2") (pinfunction "2_2") (pintype "passive"))
      (node (ref "IC23") (pin "2") (pinfunction "2_2") (pintype "passive"))
      (node (ref "IC24") (pin "2") (pinfunction "2_2") (pintype "passive"))
    )
    (net (code "213") (name "Net-(IC21-Pad3)") (class "Default")
      (node (ref "IC21") (pin "3") (pinfunction "3_3") (pintype "passive"))
      (node (ref "IC22") (pin "3") (pinfunction "3_3") (pintype "passive"))
      (node (ref "IC23") (pin "3") (pinfunction "3_3") (pintype "passive"))
      (node (ref "IC24") (pin "3") (pinfunction "3_3") (pintype "passive"))
    )
    (net (code "214") (name "Net-(IC21-Pad4)") (class "Default")
      (node (ref "IC21") (pin "4") (pinfunction "4_4") (pintype "passive"))
      (node (ref "IC22") (pin "4") (pinfunction "4_4") (pintype "passive"))
      (node (ref "IC23") (pin "4") (pinfunction "4_4") (pintype "passive"))
      (node (ref "IC24") (pin "4") (pinfunction "4_4") (pintype "passive"))
    )
    (net (code "215") (name "Net-(IC21-Pad5)") (class "Default")
      (node (ref "IC21") (pin "5") (pinfunction "5_5") (pintype "passive"))
      (node (ref "IC22") (pin "5") (pinfunction "5_5") (pintype "passive"))
      (node (ref "IC23") (pin "5") (pinfunction "5_5") (pintype "passive"))
      (node (ref "IC24") (pin "5") (pinfunction "5_5") (pintype "passive"))
    )
    (net (code "216") (name "Net-(IC21-Pad6)") (class "Default")
      (node (ref "IC21") (pin "6") (pinfunction "6_6") (pintype "passive"))
      (node (ref "IC22") (pin "6") (pinfunction "6_6") (pintype "passive"))
      (node (ref "IC23") (pin "6") (pinfunction "6_6") (pintype "passive"))
      (node (ref "IC24") (pin "6") (pinfunction "6_6") (pintype "passive"))
    )
    (net (code "217") (name "Net-(IC21-Pad7)") (class "Default")
      (node (ref "IC21") (pin "7") (pinfunction "7_7") (pintype "passive"))
      (node (ref "IC22") (pin "7") (pinfunction "7_7") (pintype "passive"))
      (node (ref "IC23") (pin "7") (pinfunction "7_7") (pintype "passive"))
      (node (ref "IC24") (pin "7") (pinfunction "7_7") (pintype "passive"))
    )
    (net (code "218") (name "Net-(IC21-Pad8)") (class "Default")
      (node (ref "IC21") (pin "8") (pinfunction "8_8") (pintype "passive"))
      (node (ref "IC22") (pin "8") (pinfunction "8_8") (pintype "passive"))
      (node (ref "IC23") (pin "8") (pinfunction "8_8") (pintype "passive"))
      (node (ref "IC24") (pin "8") (pinfunction "8_8") (pintype "passive"))
    )
    (net (code "219") (name "Net-(IC21-Pad9)") (class "Default")
      (node (ref "IC21") (pin "9") (pinfunction "9_9") (pintype "passive"))
      (node (ref "IC22") (pin "9") (pinfunction "9_9") (pintype "passive"))
      (node (ref "IC23") (pin "9") (pinfunction "9_9") (pintype "passive"))
      (node (ref "IC24") (pin "9") (pinfunction "9_9") (pintype "passive"))
    )
    (net (code "220") (name "Net-(IC21-Pad10)") (class "Default")
      (node (ref "IC21") (pin "10") (pinfunction "10_10") (pintype "passive"))
      (node (ref "IC22") (pin "10") (pinfunction "10_10") (pintype "passive"))
      (node (ref "IC23") (pin "10") (pinfunction "10_10") (pintype "passive"))
      (node (ref "IC24") (pin "10") (pinfunction "10_10") (pintype "passive"))
    )
    (net (code "221") (name "Net-(IC21-Pad11)") (class "Default")
      (node (ref "IC21") (pin "11") (pinfunction "11_11") (pintype "passive"))
      (node (ref "IC22") (pin "11") (pinfunction "11_11") (pintype "passive"))
      (node (ref "IC23") (pin "11") (pinfunction "11_11") (pintype "passive"))
      (node (ref "IC24") (pin "11") (pinfunction "11_11") (pintype "passive"))
    )
    (net (code "222") (name "Net-(IC21-Pad12)") (class "Default")
      (node (ref "IC21") (pin "12") (pinfunction "12_12") (pintype "passive"))
      (node (ref "IC22") (pin "12") (pinfunction "12_12") (pintype "passive"))
      (node (ref "IC23") (pin "12") (pinfunction "12_12") (pintype "passive"))
      (node (ref "IC24") (pin "12") (pinfunction "12_12") (pintype "passive"))
    )
    (net (code "223") (name "Net-(IC21-Pad13)") (class "Default")
      (node (ref "IC21") (pin "13") (pinfunction "13_13") (pintype "passive"))
      (node (ref "IC22") (pin "13") (pinfunction "13_13") (pintype "passive"))
      (node (ref "IC23") (pin "13") (pinfunction "13_13") (pintype "passive"))
      (node (ref "IC24") (pin "13") (pinfunction "13_13") (pintype "passive"))
    )
    (net (code "224") (name "Net-(IC21-Pad14)") (class "Default")
      (node (ref "IC21") (pin "14") (pinfunction "14_14") (pintype "passive"))
      (node (ref "IC22") (pin "14") (pinfunction "14_14") (pintype "passive"))
      (node (ref "IC23") (pin "14") (pinfunction "14_14") (pintype "passive"))
      (node (ref "IC24") (pin "14") (pinfunction "14_14") (pintype "passive"))
    )
    (net (code "225") (name "Net-(IC21-Pad15)") (class "Default")
      (node (ref "IC21") (pin "15") (pinfunction "15_15") (pintype "passive"))
      (node (ref "IC22") (pin "15") (pinfunction "15_15") (pintype "passive"))
      (node (ref "IC23") (pin "15") (pinfunction "15_15") (pintype "passive"))
      (node (ref "IC24") (pin "15") (pinfunction "15_15") (pintype "passive"))
    )
    (net (code "226") (name "Net-(IC21-Pad16)") (class "Default")
      (node (ref "IC21") (pin "16") (pinfunction "16_16") (pintype "passive"))
      (node (ref "IC22") (pin "16") (pinfunction "16_16") (pintype "passive"))
      (node (ref "IC23") (pin "16") (pinfunction "16_16") (pintype "passive"))
      (node (ref "IC24") (pin "16") (pinfunction "16_16") (pintype "passive"))
    )
    (net (code "227") (name "Net-(IC21-Pad17)") (class "Default")
      (node (ref "IC21") (pin "17") (pinfunction "17_17") (pintype "passive"))
      (node (ref "IC22") (pin "17") (pinfunction "17_17") (pintype "passive"))
      (node (ref "IC23") (pin "17") (pinfunction "17_17") (pintype "passive"))
      (node (ref "IC24") (pin "17") (pinfunction "17_17") (pintype "passive"))
    )
    (net (code "228") (name "Net-(IC21-Pad18)") (class "Default")
      (node (ref "IC21") (pin "18") (pinfunction "18_18") (pintype "passive"))
      (node (ref "IC22") (pin "18") (pinfunction "18_18") (pintype "passive"))
      (node (ref "IC23") (pin "18") (pinfunction "18_18") (pintype "passive"))
      (node (ref "IC24") (pin "18") (pinfunction "18_18") (pintype "passive"))
    )
    (net (code "229") (name "Net-(IC21-Pad19)") (class "Default")
      (node (ref "IC21") (pin "19") (pinfunction "19_19") (pintype "passive"))
      (node (ref "IC22") (pin "19") (pinfunction "19_19") (pintype "passive"))
      (node (ref "IC23") (pin "19") (pinfunction "19_19") (pintype "passive"))
      (node (ref "IC24") (pin "19") (pinfunction "19_19") (pintype "passive"))
    )
    (net (code "230") (name "Net-(IC21-Pad20)") (class "Default")
      (node (ref "IC21") (pin "20") (pinfunction "20_20") (pintype "passive"))
      (node (ref "IC22") (pin "20") (pinfunction "20_20") (pintype "passive"))
      (node (ref "IC23") (pin "20") (pinfunction "20_20") (pintype "passive"))
      (node (ref "IC24") (pin "20") (pinfunction "20_20") (pintype "passive"))
    )
    (net (code "231") (name "Net-(IC21-Pad21)") (class "Default")
      (node (ref "IC21") (pin "21") (pinfunction "21_21") (pintype "passive"))
      (node (ref "IC22") (pin "21") (pinfunction "21_21") (pintype "passive"))
      (node (ref "IC23") (pin "21") (pinfunction "21_21") (pintype "passive"))
      (node (ref "IC24") (pin "21") (pinfunction "21_21") (pintype "passive"))
    )
    (net (code "232") (name "Net-(IC21-Pad22)") (class "Default")
      (node (ref "IC21") (pin "22") (pinfunction "22_22") (pintype "passive"))
      (node (ref "IC22") (pin "22") (pinfunction "22_22") (pintype "passive"))
      (node (ref "IC23") (pin "22") (pinfunction "22_22") (pintype "passive"))
      (node (ref "IC24") (pin "22") (pinfunction "22_22") (pintype "passive"))
    )
    (net (code "233") (name "Net-(IC21-Pad23)") (class "Default")
      (node (ref "IC21") (pin "23") (pinfunction "23_23") (pintype "passive"))
      (node (ref "IC22") (pin "23") (pinfunction "23_23") (pintype "passive"))
      (node (ref "IC23") (pin "23") (pinfunction "23_23") (pintype "passive"))
      (node (ref "IC24") (pin "23") (pinfunction "23_23") (pintype "passive"))
    )
    (net (code "234") (name "Net-(IC21-Pad24)") (class "Default")
      (node (ref "IC21") (pin "24") (pinfunction "24_24") (pintype "passive"))
      (node (ref "IC22") (pin "24") (pinfunction "24_24") (pintype "passive"))
      (node (ref "IC23") (pin "24") (pinfunction "24_24") (pintype "passive"))
      (node (ref "IC24") (pin "24") (pinfunction "24_24") (pintype "passive"))
    )
    (net (code "235") (name "Net-(IC21-Pad25)") (class "Default")
      (node (ref "IC21") (pin "25") (pinfunction "25_25") (pintype "passive"))
      (node (ref "IC22") (pin "25") (pinfunction "25_25") (pintype "passive"))
      (node (ref "IC23") (pin "25") (pinfunction "25_25") (pintype "passive"))
      (node (ref "IC24") (pin "25") (pinfunction "25_25") (pintype "passive"))
    )
    (net (code "236") (name "Net-(IC21-Pad26)") (class "Default")
      (node (ref "IC21") (pin "26") (pinfunction "26_26") (pintype "passive"))
      (node (ref "IC22") (pin "26") (pinfunction "26_26") (pintype "passive"))
      (node (ref "IC23") (pin "26") (pinfunction "26_26") (pintype "passive"))
      (node (ref "IC24") (pin "26") (pinfunction "26_26") (pintype "passive"))
    )
    (net (code "237") (name "Net-(IC21-Pad27)") (class "Default")
      (node (ref "IC21") (pin "27") (pinfunction "27_27") (pintype "passive"))
      (node (ref "IC22") (pin "27") (pinfunction "27_27") (pintype "passive"))
      (node (ref "IC23") (pin "27") (pinfunction "27_27") (pintype "passive"))
      (node (ref "IC24") (pin "27") (pinfunction "27_27") (pintype "passive"))
    )
    (net (code "238") (name "Net-(IC21-Pad28)") (class "Default")
      (node (ref "IC21") (pin "28") (pinfunction "28_28") (pintype "passive"))
      (node (ref "IC22") (pin "28") (pinfunction "28_28") (pintype "passive"))
      (node (ref "IC23") (pin "28") (pinfunction "28_28") (pintype "passive"))
      (node (ref "IC24") (pin "28") (pinfunction "28_28") (pintype "passive"))
    )
    (net (code "239") (name "Net-(IC21-Pad29)") (class "Default")
      (node (ref "IC21") (pin "29") (pinfunction "29_29") (pintype "passive"))
      (node (ref "IC22") (pin "29") (pinfunction "29_29") (pintype "passive"))
      (node (ref "IC23") (pin "29") (pinfunction "29_29") (pintype "passive"))
      (node (ref "IC24") (pin "29") (pinfunction "29_29") (pintype "passive"))
    )
    (net (code "240") (name "Net-(IC21-Pad30)") (class "Default")
      (node (ref "IC21") (pin "30") (pinfunction "30_30") (pintype "passive"))
      (node (ref "IC22") (pin "30") (pinfunction "30_30") (pintype "passive"))
      (node (ref "IC23") (pin "30") (pinfunction "30_30") (pintype "passive"))
      (node (ref "IC24") (pin "30") (pinfunction "30_30") (pintype "passive"))
    )
    (net (code "241") (name "Net-(IC21-Pad31)") (class "Default")
      (node (ref "IC21") (pin "31") (pinfunction "31_31") (pintype "passive"))
      (node (ref "IC22") (pin "31") (pinfunction "31_31") (pintype "passive"))
      (node (ref "IC23") (pin "31") (pinfunction "31_31") (pintype "passive"))
      (node (ref "IC24") (pin "31") (pinfunction "31_31") (pintype "passive"))
    )
    (net (code "242") (name "Net-(IC21-Pad32)") (class "Default")
      (node (ref "IC21") (pin "32") (pinfunction "32_32") (pintype "passive"))
      (node (ref "IC22") (pin "32") (pinfunction "32_32") (pintype "passive"))
      (node (ref "IC23") (pin "32") (pinfunction "32_32") (pintype "passive"))
      (node (ref "IC24") (pin "32") (pinfunction "32_32") (pintype "passive"))
    )
    (net (code "243") (name "Net-(IC21-Pad33)") (class "Default")
      (node (ref "IC21") (pin "33") (pinfunction "33_33") (pintype "passive"))
      (node (ref "IC22") (pin "33") (pinfunction "33_33") (pintype "passive"))
      (node (ref "IC23") (pin "33") (pinfunction "33_33") (pintype "passive"))
      (node (ref "IC24") (pin "33") (pinfunction "33_33") (pintype "passive"))
    )
    (net (code "244") (name "Net-(IC21-Pad34)") (class "Default")
      (node (ref "IC21") (pin "34") (pinfunction "34_34") (pintype "passive"))
      (node (ref "IC22") (pin "34") (pinfunction "34_34") (pintype "passive"))
      (node (ref "IC23") (pin "34") (pinfunction "34_34") (pintype "passive"))
      (node (ref "IC24") (pin "34") (pinfunction "34_34") (pintype "passive"))
    )
    (net (code "245") (name "Net-(IC21-Pad35)") (class "Default")
      (node (ref "IC21") (pin "35") (pinfunction "35_35") (pintype "passive"))
      (node (ref "IC22") (pin "35") (pinfunction "35_35") (pintype "passive"))
      (node (ref "IC23") (pin "35") (pinfunction "35_35") (pintype "passive"))
      (node (ref "IC24") (pin "35") (pinfunction "35_35") (pintype "passive"))
    )
    (net (code "246") (name "Net-(IC21-Pad36)") (class "Default")
      (node (ref "IC21") (pin "36") (pinfunction "36_36") (pintype "passive"))
      (node (ref "IC22") (pin "36") (pinfunction "36_36") (pintype "passive"))
      (node (ref "IC23") (pin "36") (pinfunction "36_36") (pintype "passive"))
      (node (ref "IC24") (pin "36") (pinfunction "36_36") (pintype "passive"))
    )
    (net (code "247") (name "Net-(IC21-Pad37)") (class "Default")
      (node (ref "IC21") (pin "37") (pinfunction "37_37") (pintype "passive"))
      (node (ref "IC22") (pin "37") (pinfunction "37_37") (pintype "passive"))
      (node (ref "IC23") (pin "37") (pinfunction "37_37") (pintype "passive"))
      (node (ref "IC24") (pin "37") (pinfunction "37_37") (pintype "passive"))
    )
    (net (code "248") (name "Net-(IC21-Pad38)") (class "Default")
      (node (ref "IC21") (pin "38") (pinfunction "38_38") (pintype "passive"))
      (node (ref "IC22") (pin "38") (pinfunction "38_38") (pintype "passive"))
      (node (ref "IC23") (pin "38") (pinfunction "38_38") (pintype "passive"))
      (node (ref "IC24") (pin "38") (pinfunction "38_38") (pintype "passive"))
    )
    (net (code "249") (name "Net-(IC21-Pad39)") (class "Default")
      (node (ref "IC21") (pin "39") (pinfunction "39_39") (pintype "passive"))
      (node (ref "IC22") (pin "39") (pinfunction "39_39") (pintype "passive"))
      (node (ref "IC23") (pin "39") (pinfunction "39_39") (pintype "passive"))
      (node (ref "IC24") (pin "39") (pinfunction "39_39") (pintype "passive"))
    )
    (net (code "250") (name "Net-(IC21-Pad40)") (class "Default")
      (node (ref "IC21") (pin "40") (pinfunction "40_40") (pintype "passive"))
      (node (ref "IC22") (pin "40") (pinfunction "40_40") (pintype "passive"))
      (node (ref "IC23") (pin "40") (pinfunction "40_40") (pintype "passive"))
      (node (ref "IC24") (pin "40") (pinfunction "40_40") (pintype "passive"))
    )
    (net (code "251") (name "Net-(IC21-Pad41)") (class "Default")
      (node (ref "IC21") (pin "41") (pinfunction "41_41") (pintype "passive"))
      (node (ref "IC22") (pin "41") (pinfunction "41_41") (pintype "passive"))
      (node (ref "IC23") (pin "41") (pinfunction "41_41") (pintype "passive"))
      (node (ref "IC24") (pin "41") (pinfunction "41_41") (pintype "passive"))
    )
    (net (code "252") (name "Net-(IC21-Pad42)") (class "Default")
      (node (ref "IC21") (pin "42") (pinfunction "42_42") (pintype "passive"))
      (node (ref "IC22") (pin "42") (pinfunction "42_42") (pintype "passive"))
      (node (ref "IC23") (pin "42") (pinfunction "42_42") (pintype "passive"))
      (node (ref "IC24") (pin "42") (pinfunction "42_42") (pintype "passive"))
    )
    (net (code "253") (name "Net-(IC25-Pad1)") (class "Default")
      (node (ref "IC25") (pin "1") (pinfunction "1_1") (pintype "passive"))
      (node (ref "IC26") (pin "1") (pinfunction "1_1") (pintype "passive"))
      (node (ref "IC27") (pin "1") (pinfunction "1_1") (pintype "passive"))
      (node (ref "IC28") (pin "1") (pinfunction "1_1") (pintype "passive"))
    )
    (net (code "254") (name "Net-(IC25-Pad2)") (class "Default")
      (node (ref "IC25") (pin "2") (pinfunction "2_2") (pintype "passive"))
      (node (ref "IC26") (pin "2") (pinfunction "2_2") (pintype "passive"))
      (node (ref "IC27") (pin "2") (pinfunction "2_2") (pintype "passive"))
      (node (ref "IC28") (pin "2") (pinfunction "2_2") (pintype "passive"))
    )
    (net (code "255") (name "Net-(IC25-Pad3)") (class "Default")
      (node (ref "IC25") (pin "3") (pinfunction "3_3") (pintype "passive"))
      (node (ref "IC26") (pin "3") (pinfunction "3_3") (pintype "passive"))
      (node (ref "IC27") (pin "3") (pinfunction "3_3") (pintype "passive"))
      (node (ref "IC28") (pin "3") (pinfunction "3_3") (pintype "passive"))
    )
    (net (code "256") (name "Net-(IC25-Pad4)") (class "Default")
      (node (ref "IC25") (pin "4") (pinfunction "4_4") (pintype "passive"))
      (node (ref "IC26") (pin "4") (pinfunction "4_4") (pintype "passive"))
      (node (ref "IC27") (pin "4") (pinfunction "4_4") (pintype "passive"))
      (node (ref "IC28") (pin "4") (pinfunction "4_4") (pintype "passive"))
    )
    (net (code "257") (name "Net-(IC25-Pad5)") (class "Default")
      (node (ref "IC25") (pin "5") (pinfunction "5_5") (pintype "passive"))
      (node (ref "IC26") (pin "5") (pinfunction "5_5") (pintype "passive"))
      (node (ref "IC27") (pin "5") (pinfunction "5_5") (pintype "passive"))
      (node (ref "IC28") (pin "5") (pinfunction "5_5") (pintype "passive"))
    )
    (net (code "258") (name "Net-(IC25-Pad6)") (class "Default")
      (node (ref "IC25") (pin "6") (pinfunction "6_6") (pintype "passive"))
      (node (ref "IC26") (pin "6") (pinfunction "6_6") (pintype "passive"))
      (node (ref "IC27") (pin "6") (pinfunction "6_6") (pintype "passive"))
      (node (ref "IC28") (pin "6") (pinfunction "6_6") (pintype "passive"))
    )
    (net (code "259") (name "Net-(IC25-Pad7)") (class "Default")
      (node (ref "IC25") (pin "7") (pinfunction "7_7") (pintype "passive"))
      (node (ref "IC26") (pin "7") (pinfunction "7_7") (pintype "passive"))
      (node (ref "IC27") (pin "7") (pinfunction "7_7") (pintype "passive"))
      (node (ref "IC28") (pin "7") (pinfunction "7_7") (pintype "passive"))
    )
    (net (code "260") (name "Net-(IC25-Pad8)") (class "Default")
      (node (ref "IC25") (pin "8") (pinfunction "8_8") (pintype "passive"))
      (node (ref "IC26") (pin "8") (pinfunction "8_8") (pintype "passive"))
      (node (ref "IC27") (pin "8") (pinfunction "8_8") (pintype "passive"))
      (node (ref "IC28") (pin "8") (pinfunction "8_8") (pintype "passive"))
    )
    (net (code "261") (name "Net-(IC25-Pad9)") (class "Default")
      (node (ref "IC25") (pin "9") (pinfunction "9_9") (pintype "passive"))
      (node (ref "IC26") (pin "9") (pinfunction "9_9") (pintype "passive"))
      (node (ref "IC27") (pin "9") (pinfunction "9_9") (pintype "passive"))
      (node (ref "IC28") (pin "9") (pinfunction "9_9") (pintype "passive"))
    )
    (net (code "262") (name "Net-(IC25-Pad10)") (class "Default")
      (node (ref "IC25") (pin "10") (pinfunction "10_10") (pintype "passive"))
      (node (ref "IC26") (pin "10") (pinfunction "10_10") (pintype "passive"))
      (node (ref "IC27") (pin "10") (pinfunction "10_10") (pintype "passive"))
      (node (ref "IC28") (pin "10") (pinfunction "10_10") (pintype "passive"))
    )
    (net (code "263") (name "Net-(IC25-Pad11)") (class "Default")
      (node (ref "IC25") (pin "11") (pinfunction "11_11") (pintype "passive"))
      (node (ref "IC26") (pin "11") (pinfunction "11_11") (pintype "passive"))
      (node (ref "IC27") (pin "11") (pinfunction "11_11") (pintype "passive"))
      (node (ref "IC28") (pin "11") (pinfunction "11_11") (pintype "passive"))
    )
    (net (code "264") (name "Net-(IC25-Pad12)") (class "Default")
      (node (ref "IC25") (pin "12") (pinfunction "12_12") (pintype "passive"))
      (node (ref "IC26") (pin "12") (pinfunction "12_12") (pintype "passive"))
      (node (ref "IC27") (pin "12") (pinfunction "12_12") (pintype "passive"))
      (node (ref "IC28") (pin "12") (pinfunction "12_12") (pintype "passive"))
    )
    (net (code "265") (name "Net-(IC25-Pad13)") (class "Default")
      (node (ref "IC25") (pin "13") (pinfunction "13_13") (pintype "passive"))
      (node (ref "IC26") (pin "13") (pinfunction "13_13") (pintype "passive"))
      (node (ref "IC27") (pin "13") (pinfunction "13_13") (pintype "passive"))
      (node (ref "IC28") (pin "13") (pinfunction "13_13") (pintype "passive"))
    )
    (net (code "266") (name "Net-(IC25-Pad14)") (class "Default")
      (node (ref "IC25") (pin "14") (pinfunction "14_14") (pintype "passive"))
      (node (ref "IC26") (pin "14") (pinfunction "14_14") (pintype "passive"))
      (node (ref "IC27") (pin "14") (pinfunction "14_14") (pintype "passive"))
      (node (ref "IC28") (pin "14") (pinfunction "14_14") (pintype "passive"))
    )
    (net (code "267") (name "Net-(IC25-Pad15)") (class "Default")
      (node (ref "IC25") (pin "15") (pinfunction "15_15") (pintype "passive"))
      (node (ref "IC26") (pin "15") (pinfunction "15_15") (pintype "passive"))
      (node (ref "IC27") (pin "15") (pinfunction "15_15") (pintype "passive"))
      (node (ref "IC28") (pin "15") (pinfunction "15_15") (pintype "passive"))
    )
    (net (code "268") (name "Net-(IC25-Pad16)") (class "Default")
      (node (ref "IC25") (pin "16") (pinfunction "16_16") (pintype "passive"))
      (node (ref "IC26") (pin "16") (pinfunction "16_16") (pintype "passive"))
      (node (ref "IC27") (pin "16") (pinfunction "16_16") (pintype "passive"))
      (node (ref "IC28") (pin "16") (pinfunction "16_16") (pintype "passive"))
    )
    (net (code "269") (name "Net-(IC25-Pad17)") (class "Default")
      (node (ref "IC25") (pin "17") (pinfunction "17_17") (pintype "passive"))
      (node (ref "IC26") (pin "17") (pinfunction "17_17") (pintype "passive"))
      (node (ref "IC27") (pin "17") (pinfunction "17_17") (pintype "passive"))
      (node (ref "IC28") (pin "17") (pinfunction "17_17") (pintype "passive"))
    )
    (net (code "270") (name "Net-(IC25-Pad18)") (class "Default")
      (node (ref "IC25") (pin "18") (pinfunction "18_18") (pintype "passive"))
      (node (ref "IC26") (pin "18") (pinfunction "18_18") (pintype "passive"))
      (node (ref "IC27") (pin "18") (pinfunction "18_18") (pintype "passive"))
      (node (ref "IC28") (pin "18") (pinfunction "18_18") (pintype "passive"))
    )
    (net (code "271") (name "Net-(IC25-Pad19)") (class "Default")
      (node (ref "IC25") (pin "19") (pinfunction "19_19") (pintype "passive"))
      (node (ref "IC26") (pin "19") (pinfunction "19_19") (pintype "passive"))
      (node (ref "IC27") (pin "19") (pinfunction "19_19") (pintype "passive"))
      (node (ref "IC28") (pin "19") (pinfunction "19_19") (pintype "passive"))
    )
    (net (code "272") (name "Net-(IC25-Pad20)") (class "Default")
      (node (ref "IC25") (pin "20") (pinfunction "20_20") (pintype "passive"))
      (node (ref "IC26") (pin "20") (pinfunction "20_20") (pintype "passive"))
      (node (ref "IC27") (pin "20") (pinfunction "20_20") (pintype "passive"))
      (node (ref "IC28") (pin "20") (pinfunction "20_20") (pintype "passive"))
    )
    (net (code "273") (name "Net-(IC25-Pad21)") (class "Default")
      (node (ref "IC25") (pin "21") (pinfunction "21_21") (pintype "passive"))
      (node (ref "IC26") (pin "21") (pinfunction "21_21") (pintype "passive"))
      (node (ref "IC27") (pin "21") (pinfunction "21_21") (pintype "passive"))
      (node (ref "IC28") (pin "21") (pinfunction "21_21") (pintype "passive"))
    )
    (net (code "274") (name "Net-(IC25-Pad22)") (class "Default")
      (node (ref "IC25") (pin "22") (pinfunction "22_22") (pintype "passive"))
      (node (ref "IC26") (pin "22") (pinfunction "22_22") (pintype "passive"))
      (node (ref "IC27") (pin "22") (pinfunction "22_22") (pintype "passive"))
      (node (ref "IC28") (pin "22") (pinfunction "22_22") (pintype "passive"))
    )
    (net (code "275") (name "Net-(IC25-Pad23)") (class "Default")
      (node (ref "IC25") (pin "23") (pinfunction "23_23") (pintype "passive"))
      (node (ref "IC26") (pin "23") (pinfunction "23_23") (pintype "passive"))
      (node (ref "IC27") (pin "23") (pinfunction "23_23") (pintype "passive"))
      (node (ref "IC28") (pin "23") (pinfunction "23_23") (pintype "passive"))
    )
    (net (code "276") (name "Net-(IC25-Pad24)") (class "Default")
      (node (ref "IC25") (pin "24") (pinfunction "24_24") (pintype "passive"))
      (node (ref "IC26") (pin "24") (pinfunction "24_24") (pintype "passive"))
      (node (ref "IC27") (pin "24") (pinfunction "24_24") (pintype "passive"))
      (node (ref "IC28") (pin "24") (pinfunction "24_24") (pintype "passive"))
    )
    (net (code "277") (name "Net-(IC25-Pad25)") (class "Default")
      (node (ref "IC25") (pin "25") (pinfunction "25_25") (pintype "passive"))
      (node (ref "IC26") (pin "25") (pinfunction "25_25") (pintype "passive"))
      (node (ref "IC27") (pin "25") (pinfunction "25_25") (pintype "passive"))
      (node (ref "IC28") (pin "25") (pinfunction "25_25") (pintype "passive"))
    )
    (net (code "278") (name "Net-(IC25-Pad26)") (class "Default")
      (node (ref "IC25") (pin "26") (pinfunction "26_26") (pintype "passive"))
      (node (ref "IC26") (pin "26") (pinfunction "26_26") (pintype "passive"))
      (node (ref "IC27") (pin "26") (pinfunction "26_26") (pintype "passive"))
      (node (ref "IC28") (pin "26") (pinfunction "26_26") (pintype "passive"))
    )
    (net (code "279") (name "Net-(IC25-Pad27)") (class "Default")
      (node (ref "IC25") (pin "27") (pinfunction "27_27") (pintype "passive"))
      (node (ref "IC26") (pin "27") (pinfunction "27_27") (pintype "passive"))
      (node (ref "IC27") (pin "27") (pinfunction "27_27") (pintype "passive"))
      (node (ref "IC28") (pin "27") (pinfunction "27_27") (pintype "passive"))
    )
    (net (code "280") (name "Net-(IC25-Pad28)") (class "Default")
      (node (ref "IC25") (pin "28") (pinfunction "28_28") (pintype "passive"))
      (node (ref "IC26") (pin "28") (pinfunction "28_28") (pintype "passive"))
      (node (ref "IC27") (pin "28") (pinfunction "28_28") (pintype "passive"))
      (node (ref "IC28") (pin "28") (pinfunction "28_28") (pintype "passive"))
    )
    (net (code "281") (name "Net-(IC25-Pad29)") (class "Default")
      (node (ref "IC25") (pin "29") (pinfunction "29_29") (pintype "passive"))
      (node (ref "IC26") (pin "29") (pinfunction "29_29") (pintype "passive"))
      (node (ref "IC27") (pin "29") (pinfunction "29_29") (pintype "passive"))
      (node (ref "IC28") (pin "29") (pinfunction "29_29") (pintype "passive"))
    )
    (net (code "282") (name "Net-(IC25-Pad30)") (class "Default")
      (node (ref "IC25") (pin "30") (pinfunction "30_30") (pintype "passive"))
      (node (ref "IC26") (pin "30") (pinfunction "30_30") (pintype "passive"))
      (node (ref "IC27") (pin "30") (pinfunction "30_30") (pintype "passive"))
      (node (ref "IC28") (pin "30") (pinfunction "30_30") (pintype "passive"))
    )
    (net (code "283") (name "Net-(IC25-Pad31)") (class "Default")
      (node (ref "IC25") (pin "31") (pinfunction "31_31") (pintype "passive"))
      (node (ref "IC26") (pin "31") (pinfunction "31_31") (pintype "passive"))
      (node (ref "IC27") (pin "31") (pinfunction "31_31") (pintype "passive"))
      (node (ref "IC28") (pin "31") (pinfunction "31_31") (pintype "passive"))
    )
    (net (code "284") (name "Net-(IC25-Pad32)") (class "Default")
      (node (ref "IC25") (pin "32") (pinfunction "32_32") (pintype "passive"))
      (node (ref "IC26") (pin "32") (pinfunction "32_32") (pintype "passive"))
      (node (ref "IC27") (pin "32") (pinfunction "32_32") (pintype "passive"))
      (node (ref "IC28") (pin "32") (pinfunction "32_32") (pintype "passive"))
    )
    (net (code "285") (name "Net-(IC25-Pad33)") (class "Default")
      (node (ref "IC25") (pin "33") (pinfunction "33_33") (pintype "passive"))
      (node (ref "IC26") (pin "33") (pinfunction "33_33") (pintype "passive"))
      (node (ref "IC27") (pin "33") (pinfunction "33_33") (pintype "passive"))
      (node (ref "IC28") (pin "33") (pinfunction "33_33") (pintype "passive"))
    )
    (net (code "286") (name "Net-(IC25-Pad34)") (class "Default")
      (node (ref "IC25") (pin "34") (pinfunction "34_34") (pintype "passive"))
      (node (ref "IC26") (pin "34") (pinfunction "34_34") (pintype "passive"))
      (node (ref "IC27") (pin "34") (pinfunction "34_34") (pintype "passive"))
      (node (ref "IC28") (pin "34") (pinfunction "34_34") (pintype "passive"))
    )
    (net (code "287") (name "Net-(IC25-Pad35)") (class "Default")
      (node (ref "IC25") (pin "35") (pinfunction "35_35") (pintype "passive"))
      (node (ref "IC26") (pin "35") (pinfunction "35_35") (pintype "passive"))
      (node (ref "IC27") (pin "35") (pinfunction "35_35") (pintype "passive"))
      (node (ref "IC28") (pin "35") (pinfunction "35_35") (pintype "passive"))
    )
    (net (code "288") (name "Net-(IC25-Pad36)") (class "Default")
      (node (ref "IC25") (pin "36") (pinfunction "36_36") (pintype "passive"))
      (node (ref "IC26") (pin "36") (pinfunction "36_36") (pintype "passive"))
      (node (ref "IC27") (pin "36") (pinfunction "36_36") (pintype "passive"))
      (node (ref "IC28") (pin "36") (pinfunction "36_36") (pintype "passive"))
    )
    (net (code "289") (name "Net-(IC25-Pad37)") (class "Default")
      (node (ref "IC25") (pin "37") (pinfunction "37_37") (pintype "passive"))
      (node (ref "IC26") (pin "37") (pinfunction "37_37") (pintype "passive"))
      (node (ref "IC27") (pin "37") (pinfunction "37_37") (pintype "passive"))
      (node (ref "IC28") (pin "37") (pinfunction "37_37") (pintype "passive"))
    )
    (net (code "290") (name "Net-(IC25-Pad38)") (class "Default")
      (node (ref "IC25") (pin "38") (pinfunction "38_38") (pintype "passive"))
      (node (ref "IC26") (pin "38") (pinfunction "38_38") (pintype "passive"))
      (node (ref "IC27") (pin "38") (pinfunction "38_38") (pintype "passive"))
      (node (ref "IC28") (pin "38") (pinfunction "38_38") (pintype "passive"))
    )
    (net (code "291") (name "Net-(IC25-Pad39)") (class "Default")
      (node (ref "IC25") (pin "39") (pinfunction "39_39") (pintype "passive"))
      (node (ref "IC26") (pin "39") (pinfunction "39_39") (pintype "passive"))
      (node (ref "IC27") (pin "39") (pinfunction "39_39") (pintype "passive"))
      (node (ref "IC28") (pin "39") (pinfunction "39_39") (pintype "passive"))
    )
    (net (code "292") (name "Net-(IC25-Pad40)") (class "Default")
      (node (ref "IC25") (pin "40") (pinfunction "40_40") (pintype "passive"))
      (node (ref "IC26") (pin "40") (pinfunction "40_40") (pintype "passive"))
      (node (ref "IC27") (pin "40") (pinfunction "40_40") (pintype "passive"))
      (node (ref "IC28") (pin "40") (pinfunction "40_40") (pintype "passive"))
    )
    (net (code "293") (name "Net-(IC25-Pad41)") (class "Default")
      (node (ref "IC25") (pin "41") (pinfunction "41_41") (pintype "passive"))
      (node (ref "IC26") (pin "41") (pinfunction "41_41") (pintype "passive"))
      (node (ref "IC27") (pin "41") (pinfunction "41_41") (pintype "passive"))
      (node (ref "IC28") (pin "41") (pinfunction "41_41") (pintype "passive"))
    )
    (net (code "294") (name "Net-(IC25-Pad42)") (class "Default")
      (node (ref "IC25") (pin "42") (pinfunction "42_42") (pintype "passive"))
      (node (ref "IC26") (pin "42") (pinfunction "42_42") (pintype "passive"))
      (node (ref "IC27") (pin "42") (pinfunction "42_42") (pintype "passive"))
      (node (ref "IC28") (pin "42") (pinfunction "42_42") (pintype "passive"))
    )
    (net (code "295") (name "Net-(IC29-Pad1)") (class "Default")
      (node (ref "IC29") (pin "1") (pinfunction "1_1") (pintype "passive"))
      (node (ref "IC30") (pin "1") (pinfunction "1_1") (pintype "passive"))
      (node (ref "IC31") (pin "1") (pinfunction "1_1") (pintype "passive"))
      (node (ref "IC32") (pin "1") (pinfunction "1_1") (pintype "passive"))
    )
    (net (code "296") (name "Net-(IC29-Pad2)") (class "Default")
      (node (ref "IC29") (pin "2") (pinfunction "2_2") (pintype "passive"))
      (node (ref "IC30") (pin "2") (pinfunction "2_2") (pintype "passive"))
      (node (ref "IC31") (pin "2") (pinfunction "2_2") (pintype "passive"))
      (node (ref "IC32") (pin "2") (pinfunction "2_2") (pintype "passive"))
    )
    (net (code "297") (name "Net-(IC29-Pad3)") (class "Default")
      (node (ref "IC29") (pin "3") (pinfunction "3_3") (pintype "passive"))
      (node (ref "IC30") (pin "3") (pinfunction "3_3") (pintype "passive"))
      (node (ref "IC31") (pin "3") (pinfunction "3_3") (pintype "passive"))
      (node (ref "IC32") (pin "3") (pinfunction "3_3") (pintype "passive"))
    )
    (net (code "298") (name "Net-(IC29-Pad4)") (class "Default")
      (node (ref "IC29") (pin "4") (pinfunction "4_4") (pintype "passive"))
      (node (ref "IC30") (pin "4") (pinfunction "4_4") (pintype "passive"))
      (node (ref "IC31") (pin "4") (pinfunction "4_4") (pintype "passive"))
      (node (ref "IC32") (pin "4") (pinfunction "4_4") (pintype "passive"))
    )
    (net (code "299") (name "Net-(IC29-Pad5)") (class "Default")
      (node (ref "IC29") (pin "5") (pinfunction "5_5") (pintype "passive"))
      (node (ref "IC30") (pin "5") (pinfunction "5_5") (pintype "passive"))
      (node (ref "IC31") (pin "5") (pinfunction "5_5") (pintype "passive"))
      (node (ref "IC32") (pin "5") (pinfunction "5_5") (pintype "passive"))
    )
    (net (code "300") (name "Net-(IC29-Pad6)") (class "Default")
      (node (ref "IC29") (pin "6") (pinfunction "6_6") (pintype "passive"))
      (node (ref "IC30") (pin "6") (pinfunction "6_6") (pintype "passive"))
      (node (ref "IC31") (pin "6") (pinfunction "6_6") (pintype "passive"))
      (node (ref "IC32") (pin "6") (pinfunction "6_6") (pintype "passive"))
    )
    (net (code "301") (name "Net-(IC29-Pad7)") (class "Default")
      (node (ref "IC29") (pin "7") (pinfunction "7_7") (pintype "passive"))
      (node (ref "IC30") (pin "7") (pinfunction "7_7") (pintype "passive"))
      (node (ref "IC31") (pin "7") (pinfunction "7_7") (pintype "passive"))
      (node (ref "IC32") (pin "7") (pinfunction "7_7") (pintype "passive"))
    )
    (net (code "302") (name "Net-(IC29-Pad8)") (class "Default")
      (node (ref "IC29") (pin "8") (pinfunction "8_8") (pintype "passive"))
      (node (ref "IC30") (pin "8") (pinfunction "8_8") (pintype "passive"))
      (node (ref "IC31") (pin "8") (pinfunction "8_8") (pintype "passive"))
      (node (ref "IC32") (pin "8") (pinfunction "8_8") (pintype "passive"))
    )
    (net (code "303") (name "Net-(IC29-Pad9)") (class "Default")
      (node (ref "IC29") (pin "9") (pinfunction "9_9") (pintype "passive"))
      (node (ref "IC30") (pin "9") (pinfunction "9_9") (pintype "passive"))
      (node (ref "IC31") (pin "9") (pinfunction "9_9") (pintype "passive"))
      (node (ref "IC32") (pin "9") (pinfunction "9_9") (pintype "passive"))
    )
    (net (code "304") (name "Net-(IC29-Pad10)") (class "Default")
      (node (ref "IC29") (pin "10") (pinfunction "10_10") (pintype "passive"))
      (node (ref "IC30") (pin "10") (pinfunction "10_10") (pintype "passive"))
      (node (ref "IC31") (pin "10") (pinfunction "10_10") (pintype "passive"))
      (node (ref "IC32") (pin "10") (pinfunction "10_10") (pintype "passive"))
    )
    (net (code "305") (name "Net-(IC29-Pad11)") (class "Default")
      (node (ref "IC29") (pin "11") (pinfunction "11_11") (pintype "passive"))
      (node (ref "IC30") (pin "11") (pinfunction "11_11") (pintype "passive"))
      (node (ref "IC31") (pin "11") (pinfunction "11_11") (pintype "passive"))
      (node (ref "IC32") (pin "11") (pinfunction "11_11") (pintype "passive"))
    )
    (net (code "306") (name "Net-(IC29-Pad12)") (class "Default")
      (node (ref "IC29") (pin "12") (pinfunction "12_12") (pintype "passive"))
      (node (ref "IC30") (pin "12") (pinfunction "12_12") (pintype "passive"))
      (node (ref "IC31") (pin "12") (pinfunction "12_12") (pintype "passive"))
      (node (ref "IC32") (pin "12") (pinfunction "12_12") (pintype "passive"))
    )
    (net (code "307") (name "Net-(IC29-Pad13)") (class "Default")
      (node (ref "IC29") (pin "13") (pinfunction "13_13") (pintype "passive"))
      (node (ref "IC30") (pin "13") (pinfunction "13_13") (pintype "passive"))
      (node (ref "IC31") (pin "13") (pinfunction "13_13") (pintype "passive"))
      (node (ref "IC32") (pin "13") (pinfunction "13_13") (pintype "passive"))
    )
    (net (code "308") (name "Net-(IC29-Pad14)") (class "Default")
      (node (ref "IC29") (pin "14") (pinfunction "14_14") (pintype "passive"))
      (node (ref "IC30") (pin "14") (pinfunction "14_14") (pintype "passive"))
      (node (ref "IC31") (pin "14") (pinfunction "14_14") (pintype "passive"))
      (node (ref "IC32") (pin "14") (pinfunction "14_14") (pintype "passive"))
    )
    (net (code "309") (name "Net-(IC29-Pad15)") (class "Default")
      (node (ref "IC29") (pin "15") (pinfunction "15_15") (pintype "passive"))
      (node (ref "IC30") (pin "15") (pinfunction "15_15") (pintype "passive"))
      (node (ref "IC31") (pin "15") (pinfunction "15_15") (pintype "passive"))
      (node (ref "IC32") (pin "15") (pinfunction "15_15") (pintype "passive"))
    )
    (net (code "310") (name "Net-(IC29-Pad16)") (class "Default")
      (node (ref "IC29") (pin "16") (pinfunction "16_16") (pintype "passive"))
      (node (ref "IC30") (pin "16") (pinfunction "16_16") (pintype "passive"))
      (node (ref "IC31") (pin "16") (pinfunction "16_16") (pintype "passive"))
      (node (ref "IC32") (pin "16") (pinfunction "16_16") (pintype "passive"))
    )
    (net (code "311") (name "Net-(IC29-Pad17)") (class "Default")
      (node (ref "IC29") (pin "17") (pinfunction "17_17") (pintype "passive"))
      (node (ref "IC30") (pin "17") (pinfunction "17_17") (pintype "passive"))
      (node (ref "IC31") (pin "17") (pinfunction "17_17") (pintype "passive"))
      (node (ref "IC32") (pin "17") (pinfunction "17_17") (pintype "passive"))
    )
    (net (code "312") (name "Net-(IC29-Pad18)") (class "Default")
      (node (ref "IC29") (pin "18") (pinfunction "18_18") (pintype "passive"))
      (node (ref "IC30") (pin "18") (pinfunction "18_18") (pintype "passive"))
      (node (ref "IC31") (pin "18") (pinfunction "18_18") (pintype "passive"))
      (node (ref "IC32") (pin "18") (pinfunction "18_18") (pintype "passive"))
    )
    (net (code "313") (name "Net-(IC29-Pad19)") (class "Default")
      (node (ref "IC29") (pin "19") (pinfunction "19_19") (pintype "passive"))
      (node (ref "IC30") (pin "19") (pinfunction "19_19") (pintype "passive"))
      (node (ref "IC31") (pin "19") (pinfunction "19_19") (pintype "passive"))
      (node (ref "IC32") (pin "19") (pinfunction "19_19") (pintype "passive"))
    )
    (net (code "314") (name "Net-(IC29-Pad20)") (class "Default")
      (node (ref "IC29") (pin "20") (pinfunction "20_20") (pintype "passive"))
      (node (ref "IC30") (pin "20") (pinfunction "20_20") (pintype "passive"))
      (node (ref "IC31") (pin "20") (pinfunction "20_20") (pintype "passive"))
      (node (ref "IC32") (pin "20") (pinfunction "20_20") (pintype "passive"))
    )
    (net (code "315") (name "Net-(IC29-Pad21)") (class "Default")
      (node (ref "IC29") (pin "21") (pinfunction "21_21") (pintype "passive"))
      (node (ref "IC30") (pin "21") (pinfunction "21_21") (pintype "passive"))
      (node (ref "IC31") (pin "21") (pinfunction "21_21") (pintype "passive"))
      (node (ref "IC32") (pin "21") (pinfunction "21_21") (pintype "passive"))
    )
    (net (code "316") (name "Net-(IC29-Pad22)") (class "Default")
      (node (ref "IC29") (pin "22") (pinfunction "22_22") (pintype "passive"))
      (node (ref "IC30") (pin "22") (pinfunction "22_22") (pintype "passive"))
      (node (ref "IC31") (pin "22") (pinfunction "22_22") (pintype "passive"))
      (node (ref "IC32") (pin "22") (pinfunction "22_22") (pintype "passive"))
    )
    (net (code "317") (name "Net-(IC29-Pad23)") (class "Default")
      (node (ref "IC29") (pin "23") (pinfunction "23_23") (pintype "passive"))
      (node (ref "IC30") (pin "23") (pinfunction "23_23") (pintype "passive"))
      (node (ref "IC31") (pin "23") (pinfunction "23_23") (pintype "passive"))
      (node (ref "IC32") (pin "23") (pinfunction "23_23") (pintype "passive"))
    )
    (net (code "318") (name "Net-(IC29-Pad24)") (class "Default")
      (node (ref "IC29") (pin "24") (pinfunction "24_24") (pintype "passive"))
      (node (ref "IC30") (pin "24") (pinfunction "24_24") (pintype "passive"))
      (node (ref "IC31") (pin "24") (pinfunction "24_24") (pintype "passive"))
      (node (ref "IC32") (pin "24") (pinfunction "24_24") (pintype "passive"))
    )
    (net (code "319") (name "Net-(IC29-Pad25)") (class "Default")
      (node (ref "IC29") (pin "25") (pinfunction "25_25") (pintype "passive"))
      (node (ref "IC30") (pin "25") (pinfunction "25_25") (pintype "passive"))
      (node (ref "IC31") (pin "25") (pinfunction "25_25") (pintype "passive"))
      (node (ref "IC32") (pin "25") (pinfunction "25_25") (pintype "passive"))
    )
    (net (code "320") (name "Net-(IC29-Pad26)") (class "Default")
      (node (ref "IC29") (pin "26") (pinfunction "26_26") (pintype "passive"))
      (node (ref "IC30") (pin "26") (pinfunction "26_26") (pintype "passive"))
      (node (ref "IC31") (pin "26") (pinfunction "26_26") (pintype "passive"))
      (node (ref "IC32") (pin "26") (pinfunction "26_26") (pintype "passive"))
    )
    (net (code "321") (name "Net-(IC29-Pad27)") (class "Default")
      (node (ref "IC29") (pin "27") (pinfunction "27_27") (pintype "passive"))
      (node (ref "IC30") (pin "27") (pinfunction "27_27") (pintype "passive"))
      (node (ref "IC31") (pin "27") (pinfunction "27_27") (pintype "passive"))
      (node (ref "IC32") (pin "27") (pinfunction "27_27") (pintype "passive"))
    )
    (net (code "322") (name "Net-(IC29-Pad28)") (class "Default")
      (node (ref "IC29") (pin "28") (pinfunction "28_28") (pintype "passive"))
      (node (ref "IC30") (pin "28") (pinfunction "28_28") (pintype "passive"))
      (node (ref "IC31") (pin "28") (pinfunction "28_28") (pintype "passive"))
      (node (ref "IC32") (pin "28") (pinfunction "28_28") (pintype "passive"))
    )
    (net (code "323") (name "Net-(IC29-Pad29)") (class "Default")
      (node (ref "IC29") (pin "29") (pinfunction "29_29") (pintype "passive"))
      (node (ref "IC30") (pin "29") (pinfunction "29_29") (pintype "passive"))
      (node (ref "IC31") (pin "29") (pinfunction "29_29") (pintype "passive"))
      (node (ref "IC32") (pin "29") (pinfunction "29_29") (pintype "passive"))
    )
    (net (code "324") (name "Net-(IC29-Pad30)") (class "Default")
      (node (ref "IC29") (pin "30") (pinfunction "30_30") (pintype "passive"))
      (node (ref "IC30") (pin "30") (pinfunction "30_30") (pintype "passive"))
      (node (ref "IC31") (pin "30") (pinfunction "30_30") (pintype "passive"))
      (node (ref "IC32") (pin "30") (pinfunction "30_30") (pintype "passive"))
    )
    (net (code "325") (name "Net-(IC29-Pad31)") (class "Default")
      (node (ref "IC29") (pin "31") (pinfunction "31_31") (pintype "passive"))
      (node (ref "IC30") (pin "31") (pinfunction "31_31") (pintype "passive"))
      (node (ref "IC31") (pin "31") (pinfunction "31_31") (pintype "passive"))
      (node (ref "IC32") (pin "31") (pinfunction "31_31") (pintype "passive"))
    )
    (net (code "326") (name "Net-(IC29-Pad32)") (class "Default")
      (node (ref "IC29") (pin "32") (pinfunction "32_32") (pintype "passive"))
      (node (ref "IC30") (pin "32") (pinfunction "32_32") (pintype "passive"))
      (node (ref "IC31") (pin "32") (pinfunction "32_32") (pintype "passive"))
      (node (ref "IC32") (pin "32") (pinfunction "32_32") (pintype "passive"))
    )
    (net (code "327") (name "Net-(IC29-Pad33)") (class "Default")
      (node (ref "IC29") (pin "33") (pinfunction "33_33") (pintype "passive"))
      (node (ref "IC30") (pin "33") (pinfunction "33_33") (pintype "passive"))
      (node (ref "IC31") (pin "33") (pinfunction "33_33") (pintype "passive"))
      (node (ref "IC32") (pin "33") (pinfunction "33_33") (pintype "passive"))
    )
    (net (code "328") (name "Net-(IC29-Pad34)") (class "Default")
      (node (ref "IC29") (pin "34") (pinfunction "34_34") (pintype "passive"))
      (node (ref "IC30") (pin "34") (pinfunction "34_34") (pintype "passive"))
      (node (ref "IC31") (pin "34") (pinfunction "34_34") (pintype "passive"))
      (node (ref "IC32") (pin "34") (pinfunction "34_34") (pintype "passive"))
    )
    (net (code "329") (name "Net-(IC29-Pad35)") (class "Default")
      (node (ref "IC29") (pin "35") (pinfunction "35_35") (pintype "passive"))
      (node (ref "IC30") (pin "35") (pinfunction "35_35") (pintype "passive"))
      (node (ref "IC31") (pin "35") (pinfunction "35_35") (pintype "passive"))
      (node (ref "IC32") (pin "35") (pinfunction "35_35") (pintype "passive"))
    )
    (net (code "330") (name "Net-(IC29-Pad36)") (class "Default")
      (node (ref "IC29") (pin "36") (pinfunction "36_36") (pintype "passive"))
      (node (ref "IC30") (pin "36") (pinfunction "36_36") (pintype "passive"))
      (node (ref "IC31") (pin "36") (pinfunction "36_36") (pintype "passive"))
      (node (ref "IC32") (pin "36") (pinfunction "36_36") (pintype "passive"))
    )
    (net (code "331") (name "Net-(IC29-Pad37)") (class "Default")
      (node (ref "IC29") (pin "37") (pinfunction "37_37") (pintype "passive"))
      (node (ref "IC30") (pin "37") (pinfunction "37_37") (pintype "passive"))
      (node (ref "IC31") (pin "37") (pinfunction "37_37") (pintype "passive"))
      (node (ref "IC32") (pin "37") (pinfunction "37_37") (pintype "passive"))
    )
    (net (code "332") (name "Net-(IC29-Pad38)") (class "Default")
      (node (ref "IC29") (pin "38") (pinfunction "38_38") (pintype "passive"))
      (node (ref "IC30") (pin "38") (pinfunction "38_38") (pintype "passive"))
      (node (ref "IC31") (pin "38") (pinfunction "38_38") (pintype "passive"))
      (node (ref "IC32") (pin "38") (pinfunction "38_38") (pintype "passive"))
    )
    (net (code "333") (name "Net-(IC29-Pad39)") (class "Default")
      (node (ref "IC29") (pin "39") (pinfunction "39_39") (pintype "passive"))
      (node (ref "IC30") (pin "39") (pinfunction "39_39") (pintype "passive"))
      (node (ref "IC31") (pin "39") (pinfunction "39_39") (pintype "passive"))
      (node (ref "IC32") (pin "39") (pinfunction "39_39") (pintype "passive"))
    )
    (net (code "334") (name "Net-(IC29-Pad40)") (class "Default")
      (node (ref "IC29") (pin "40") (pinfunction "40_40") (pintype "passive"))
      (node (ref "IC30") (pin "40") (pinfunction "40_40") (pintype "passive"))
      (node (ref "IC31") (pin "40") (pinfunction "40_40") (pintype "passive"))
      (node (ref "IC32") (pin "40") (pinfunction "40_40") (pintype "passive"))
    )
    (net (code "335") (name "Net-(IC29-Pad41)") (class "Default")
      (node (ref "IC29") (pin "41") (pinfunction "41_41") (pintype "passive"))
      (node (ref "IC30") (pin "41") (pinfunction "41_41") (pintype "passive"))
      (node (ref "IC31") (pin "41") (pinfunction "41_41") (pintype "passive"))
      (node (ref "IC32") (pin "41") (pinfunction "41_41") (pintype "passive"))
    )
    (net (code "336") (name "Net-(IC29-Pad42)") (class "Default")
      (node (ref "IC29") (pin "42") (pinfunction "42_42") (pintype "passive"))
      (node (ref "IC30") (pin "42") (pinfunction "42_42") (pintype "passive"))
      (node (ref "IC31") (pin "42") (pinfunction "42_42") (pintype "passive"))
      (node (ref "IC32") (pin "42") (pinfunction "42_42") (pintype "passive"))
    )
    (net (code "337") (name "Net-(IC33-Pad1)") (class "Default")
      (node (ref "IC33") (pin "1") (pinfunction "1_1") (pintype "passive"))
      (node (ref "IC34") (pin "1") (pinfunction "1_1") (pintype "passive"))
      (node (ref "IC35") (pin "1") (pinfunction "1_1") (pintype "passive"))
      (node (ref "IC36") (pin "1") (pinfunction "1_1") (pintype "passive"))
    )
    (net (code "338") (name "Net-(IC33-Pad2)") (class "Default")
      (node (ref "IC33") (pin "2") (pinfunction "2_2") (pintype "passive"))
      (node (ref "IC34") (pin "2") (pinfunction "2_2") (pintype "passive"))
      (node (ref "IC35") (pin "2") (pinfunction "2_2") (pintype "passive"))
      (node (ref "IC36") (pin "2") (pinfunction "2_2") (pintype "passive"))
    )
    (net (code "339") (name "Net-(IC33-Pad3)") (class "Default")
      (node (ref "IC33") (pin "3") (pinfunction "3_3") (pintype "passive"))
      (node (ref "IC34") (pin "3") (pinfunction "3_3") (pintype "passive"))
      (node (ref "IC35") (pin "3") (pinfunction "3_3") (pintype "passive"))
      (node (ref "IC36") (pin "3") (pinfunction "3_3") (pintype "passive"))
    )
    (net (code "340") (name "Net-(IC33-Pad4)") (class "Default")
      (node (ref "IC33") (pin "4") (pinfunction "4_4") (pintype "passive"))
      (node (ref "IC34") (pin "4") (pinfunction "4_4") (pintype "passive"))
      (node (ref "IC35") (pin "4") (pinfunction "4_4") (pintype "passive"))
      (node (ref "IC36") (pin "4") (pinfunction "4_4") (pintype "passive"))
    )
    (net (code "341") (name "Net-(IC33-Pad5)") (class "Default")
      (node (ref "IC33") (pin "5") (pinfunction "5_5") (pintype "passive"))
      (node (ref "IC34") (pin "5") (pinfunction "5_5") (pintype "passive"))
      (node (ref "IC35") (pin "5") (pinfunction "5_5") (pintype "passive"))
      (node (ref "IC36") (pin "5") (pinfunction "5_5") (pintype "passive"))
    )
    (net (code "342") (name "Net-(IC33-Pad6)") (class "Default")
      (node (ref "IC33") (pin "6") (pinfunction "6_6") (pintype "passive"))
      (node (ref "IC34") (pin "6") (pinfunction "6_6") (pintype "passive"))
      (node (ref "IC35") (pin "6") (pinfunction "6_6") (pintype "passive"))
      (node (ref "IC36") (pin "6") (pinfunction "6_6") (pintype "passive"))
    )
    (net (code "343") (name "Net-(IC33-Pad7)") (class "Default")
      (node (ref "IC33") (pin "7") (pinfunction "7_7") (pintype "passive"))
      (node (ref "IC34") (pin "7") (pinfunction "7_7") (pintype "passive"))
      (node (ref "IC35") (pin "7") (pinfunction "7_7") (pintype "passive"))
      (node (ref "IC36") (pin "7") (pinfunction "7_7") (pintype "passive"))
    )
    (net (code "344") (name "Net-(IC33-Pad8)") (class "Default")
      (node (ref "IC33") (pin "8") (pinfunction "8_8") (pintype "passive"))
      (node (ref "IC34") (pin "8") (pinfunction "8_8") (pintype "passive"))
      (node (ref "IC35") (pin "8") (pinfunction "8_8") (pintype "passive"))
      (node (ref "IC36") (pin "8") (pinfunction "8_8") (pintype "passive"))
    )
    (net (code "345") (name "Net-(IC33-Pad9)") (class "Default")
      (node (ref "IC33") (pin "9") (pinfunction "9_9") (pintype "passive"))
      (node (ref "IC34") (pin "9") (pinfunction "9_9") (pintype "passive"))
      (node (ref "IC35") (pin "9") (pinfunction "9_9") (pintype "passive"))
      (node (ref "IC36") (pin "9") (pinfunction "9_9") (pintype "passive"))
    )
    (net (code "346") (name "Net-(IC33-Pad10)") (class "Default")
      (node (ref "IC33") (pin "10") (pinfunction "10_10") (pintype "passive"))
      (node (ref "IC34") (pin "10") (pinfunction "10_10") (pintype "passive"))
      (node (ref "IC35") (pin "10") (pinfunction "10_10") (pintype "passive"))
      (node (ref "IC36") (pin "10") (pinfunction "10_10") (pintype "passive"))
    )
    (net (code "347") (name "Net-(IC33-Pad11)") (class "Default")
      (node (ref "IC33") (pin "11") (pinfunction "11_11") (pintype "passive"))
      (node (ref "IC34") (pin "11") (pinfunction "11_11") (pintype "passive"))
      (node (ref "IC35") (pin "11") (pinfunction "11_11") (pintype "passive"))
      (node (ref "IC36") (pin "11") (pinfunction "11_11") (pintype "passive"))
    )
    (net (code "348") (name "Net-(IC33-Pad12)") (class "Default")
      (node (ref "IC33") (pin "12") (pinfunction "12_12") (pintype "passive"))
      (node (ref "IC34") (pin "12") (pinfunction "12_12") (pintype "passive"))
      (node (ref "IC35") (pin "12") (pinfunction "12_12") (pintype "passive"))
      (node (ref "IC36") (pin "12") (pinfunction "12_12") (pintype "passive"))
    )
    (net (code "349") (name "Net-(IC33-Pad13)") (class "Default")
      (node (ref "IC33") (pin "13") (pinfunction "13_13") (pintype "passive"))
      (node (ref "IC34") (pin "13") (pinfunction "13_13") (pintype "passive"))
      (node (ref "IC35") (pin "13") (pinfunction "13_13") (pintype "passive"))
      (node (ref "IC36") (pin "13") (pinfunction "13_13") (pintype "passive"))
    )
    (net (code "350") (name "Net-(IC33-Pad14)") (class "Default")
      (node (ref "IC33") (pin "14") (pinfunction "14_14") (pintype "passive"))
      (node (ref "IC34") (pin "14") (pinfunction "14_14") (pintype "passive"))
      (node (ref "IC35") (pin "14") (pinfunction "14_14") (pintype "passive"))
      (node (ref "IC36") (pin "14") (pinfunction "14_14") (pintype "passive"))
    )
    (net (code "351") (name "Net-(IC33-Pad15)") (class "Default")
      (node (ref "IC33") (pin "15") (pinfunction "15_15") (pintype "passive"))
      (node (ref "IC34") (pin "15") (pinfunction "15_15") (pintype "passive"))
      (node (ref "IC35") (pin "15") (pinfunction "15_15") (pintype "passive"))
      (node (ref "IC36") (pin "15") (pinfunction "15_15") (pintype "passive"))
    )
    (net (code "352") (name "Net-(IC33-Pad16)") (class "Default")
      (node (ref "IC33") (pin "16") (pinfunction "16_16") (pintype "passive"))
      (node (ref "IC34") (pin "16") (pinfunction "16_16") (pintype "passive"))
      (node (ref "IC35") (pin "16") (pinfunction "16_16") (pintype "passive"))
      (node (ref "IC36") (pin "16") (pinfunction "16_16") (pintype "passive"))
    )
    (net (code "353") (name "Net-(IC33-Pad17)") (class "Default")
      (node (ref "IC33") (pin "17") (pinfunction "17_17") (pintype "passive"))
      (node (ref "IC34") (pin "17") (pinfunction "17_17") (pintype "passive"))
      (node (ref "IC35") (pin "17") (pinfunction "17_17") (pintype "passive"))
      (node (ref "IC36") (pin "17") (pinfunction "17_17") (pintype "passive"))
    )
    (net (code "354") (name "Net-(IC33-Pad18)") (class "Default")
      (node (ref "IC33") (pin "18") (pinfunction "18_18") (pintype "passive"))
      (node (ref "IC34") (pin "18") (pinfunction "18_18") (pintype "passive"))
      (node (ref "IC35") (pin "18") (pinfunction "18_18") (pintype "passive"))
      (node (ref "IC36") (pin "18") (pinfunction "18_18") (pintype "passive"))
    )
    (net (code "355") (name "Net-(IC33-Pad19)") (class "Default")
      (node (ref "IC33") (pin "19") (pinfunction "19_19") (pintype "passive"))
      (node (ref "IC34") (pin "19") (pinfunction "19_19") (pintype "passive"))
      (node (ref "IC35") (pin "19") (pinfunction "19_19") (pintype "passive"))
      (node (ref "IC36") (pin "19") (pinfunction "19_19") (pintype "passive"))
    )
    (net (code "356") (name "Net-(IC33-Pad20)") (class "Default")
      (node (ref "IC33") (pin "20") (pinfunction "20_20") (pintype "passive"))
      (node (ref "IC34") (pin "20") (pinfunction "20_20") (pintype "passive"))
      (node (ref "IC35") (pin "20") (pinfunction "20_20") (pintype "passive"))
      (node (ref "IC36") (pin "20") (pinfunction "20_20") (pintype "passive"))
    )
    (net (code "357") (name "Net-(IC33-Pad21)") (class "Default")
      (node (ref "IC33") (pin "21") (pinfunction "21_21") (pintype "passive"))
      (node (ref "IC34") (pin "21") (pinfunction "21_21") (pintype "passive"))
      (node (ref "IC35") (pin "21") (pinfunction "21_21") (pintype "passive"))
      (node (ref "IC36") (pin "21") (pinfunction "21_21") (pintype "passive"))
    )
    (net (code "358") (name "Net-(IC33-Pad22)") (class "Default")
      (node (ref "IC33") (pin "22") (pinfunction "22_22") (pintype "passive"))
      (node (ref "IC34") (pin "22") (pinfunction "22_22") (pintype "passive"))
      (node (ref "IC35") (pin "22") (pinfunction "22_22") (pintype "passive"))
      (node (ref "IC36") (pin "22") (pinfunction "22_22") (pintype "passive"))
    )
    (net (code "359") (name "Net-(IC33-Pad23)") (class "Default")
      (node (ref "IC33") (pin "23") (pinfunction "23_23") (pintype "passive"))
      (node (ref "IC34") (pin "23") (pinfunction "23_23") (pintype "passive"))
      (node (ref "IC35") (pin "23") (pinfunction "23_23") (pintype "passive"))
      (node (ref "IC36") (pin "23") (pinfunction "23_23") (pintype "passive"))
    )
    (net (code "360") (name "Net-(IC33-Pad24)") (class "Default")
      (node (ref "IC33") (pin "24") (pinfunction "24_24") (pintype "passive"))
      (node (ref "IC34") (pin "24") (pinfunction "24_24") (pintype "passive"))
      (node (ref "IC35") (pin "24") (pinfunction "24_24") (pintype "passive"))
      (node (ref "IC36") (pin "24") (pinfunction "24_24") (pintype "passive"))
    )
    (net (code "361") (name "Net-(IC33-Pad25)") (class "Default")
      (node (ref "IC33") (pin "25") (pinfunction "25_25") (pintype "passive"))
      (node (ref "IC34") (pin "25") (pinfunction "25_25") (pintype "passive"))
      (node (ref "IC35") (pin "25") (pinfunction "25_25") (pintype "passive"))
      (node (ref "IC36") (pin "25") (pinfunction "25_25") (pintype "passive"))
    )
    (net (code "362") (name "Net-(IC33-Pad26)") (class "Default")
      (node (ref "IC33") (pin "26") (pinfunction "26_26") (pintype "passive"))
      (node (ref "IC34") (pin "26") (pinfunction "26_26") (pintype "passive"))
      (node (ref "IC35") (pin "26") (pinfunction "26_26") (pintype "passive"))
      (node (ref "IC36") (pin "26") (pinfunction "26_26") (pintype "passive"))
    )
    (net (code "363") (name "Net-(IC33-Pad27)") (class "Default")
      (node (ref "IC33") (pin "27") (pinfunction "27_27") (pintype "passive"))
      (node (ref "IC34") (pin "27") (pinfunction "27_27") (pintype "passive"))
      (node (ref "IC35") (pin "27") (pinfunction "27_27") (pintype "passive"))
      (node (ref "IC36") (pin "27") (pinfunction "27_27") (pintype "passive"))
    )
    (net (code "364") (name "Net-(IC33-Pad28)") (class "Default")
      (node (ref "IC33") (pin "28") (pinfunction "28_28") (pintype "passive"))
      (node (ref "IC34") (pin "28") (pinfunction "28_28") (pintype "passive"))
      (node (ref "IC35") (pin "28") (pinfunction "28_28") (pintype "passive"))
      (node (ref "IC36") (pin "28") (pinfunction "28_28") (pintype "passive"))
    )
    (net (code "365") (name "Net-(IC33-Pad29)") (class "Default")
      (node (ref "IC33") (pin "29") (pinfunction "29_29") (pintype "passive"))
      (node (ref "IC34") (pin "29") (pinfunction "29_29") (pintype "passive"))
      (node (ref "IC35") (pin "29") (pinfunction "29_29") (pintype "passive"))
      (node (ref "IC36") (pin "29") (pinfunction "29_29") (pintype "passive"))
    )
    (net (code "366") (name "Net-(IC33-Pad30)") (class "Default")
      (node (ref "IC33") (pin "30") (pinfunction "30_30") (pintype "passive"))
      (node (ref "IC34") (pin "30") (pinfunction "30_30") (pintype "passive"))
      (node (ref "IC35") (pin "30") (pinfunction "30_30") (pintype "passive"))
      (node (ref "IC36") (pin "30") (pinfunction "30_30") (pintype "passive"))
    )
    (net (code "367") (name "Net-(IC33-Pad31)") (class "Default")
      (node (ref "IC33") (pin "31") (pinfunction "31_31") (pintype "passive"))
      (node (ref "IC34") (pin "31") (pinfunction "31_31") (pintype "passive"))
      (node (ref "IC35") (pin "31") (pinfunction "31_31") (pintype "passive"))
      (node (ref "IC36") (pin "31") (pinfunction "31_31") (pintype "passive"))
    )
    (net (code "368") (name "Net-(IC33-Pad32)") (class "Default")
      (node (ref "IC33") (pin "32") (pinfunction "32_32") (pintype "passive"))
      (node (ref "IC34") (pin "32") (pinfunction "32_32") (pintype "passive"))
      (node (ref "IC35") (pin "32") (pinfunction "32_32") (pintype "passive"))
      (node (ref "IC36") (pin "32") (pinfunction "32_32") (pintype "passive"))
    )
    (net (code "369") (name "Net-(IC33-Pad33)") (class "Default")
      (node (ref "IC33") (pin "33") (pinfunction "33_33") (pintype "passive"))
      (node (ref "IC34") (pin "33") (pinfunction "33_33") (pintype "passive"))
      (node (ref "IC35") (pin "33") (pinfunction "33_33") (pintype "passive"))
      (node (ref "IC36") (pin "33") (pinfunction "33_33") (pintype "passive"))
    )
    (net (code "370") (name "Net-(IC33-Pad34)") (class "Default")
      (node (ref "IC33") (pin "34") (pinfunction "34_34") (pintype "passive"))
      (node (ref "IC34") (pin "34") (pinfunction "34_34") (pintype "passive"))
      (node (ref "IC35") (pin "34") (pinfunction "34_34") (pintype "passive"))
      (node (ref "IC36") (pin "34") (pinfunction "34_34") (pintype "passive"))
    )
    (net (code "371") (name "Net-(IC33-Pad35)") (class "Default")
      (node (ref "IC33") (pin "35") (pinfunction "35_35") (pintype "passive"))
      (node (ref "IC34") (pin "35") (pinfunction "35_35") (pintype "passive"))
      (node (ref "IC35") (pin "35") (pinfunction "35_35") (pintype "passive"))
      (node (ref "IC36") (pin "35") (pinfunction "35_35") (pintype "passive"))
    )
    (net (code "372") (name "Net-(IC33-Pad36)") (class "Default")
      (node (ref "IC33") (pin "36") (pinfunction "36_36") (pintype "passive"))
      (node (ref "IC34") (pin "36") (pinfunction "36_36") (pintype "passive"))
      (node (ref "IC35") (pin "36") (pinfunction "36_36") (pintype "passive"))
      (node (ref "IC36") (pin "36") (pinfunction "36_36") (pintype "passive"))
    )
    (net (code "373") (name "Net-(IC33-Pad37)") (class "Default")
      (node (ref "IC33") (pin "37") (pinfunction "37_37") (pintype "passive"))
      (node (ref "IC34") (pin "37") (pinfunction "37_37") (pintype "passive"))
      (node (ref "IC35") (pin "37") (pinfunction "37_37") (pintype "passive"))
      (node (ref "IC36") (pin "37") (pinfunction "37_37") (pintype "passive"))
    )
    (net (code "374") (name "Net-(IC33-Pad38)") (class "Default")
      (node (ref "IC33") (pin "38") (pinfunction "38_38") (pintype "passive"))
      (node (ref "IC34") (pin "38") (pinfunction "38_38") (pintype "passive"))
      (node (ref "IC35") (pin "38") (pinfunction "38_38") (pintype "passive"))
      (node (ref "IC36") (pin "38") (pinfunction "38_38") (pintype "passive"))
    )
    (net (code "375") (name "Net-(IC33-Pad39)") (class "Default")
      (node (ref "IC33") (pin "39") (pinfunction "39_39") (pintype "passive"))
      (node (ref "IC34") (pin "39") (pinfunction "39_39") (pintype "passive"))
      (node (ref "IC35") (pin "39") (pinfunction "39_39") (pintype "passive"))
      (node (ref "IC36") (pin "39") (pinfunction "39_39") (pintype "passive"))
    )
    (net (code "376") (name "Net-(IC33-Pad40)") (class "Default")
      (node (ref "IC33") (pin "40") (pinfunction "40_40") (pintype "passive"))
      (node (ref "IC34") (pin "40") (pinfunction "40_40") (pintype "passive"))
      (node (ref "IC35") (pin "40") (pinfunction "40_40") (pintype "passive"))
      (node (ref "IC36") (pin "40") (pinfunction "40_40") (pintype "passive"))
    )
    (net (code "377") (name "Net-(IC33-Pad41)") (class "Default")
      (node (ref "IC33") (pin "41") (pinfunction "41_41") (pintype "passive"))
      (node (ref "IC34") (pin "41") (pinfunction "41_41") (pintype "passive"))
      (node (ref "IC35") (pin "41") (pinfunction "41_41") (pintype "passive"))
      (node (ref "IC36") (pin "41") (pinfunction "41_41") (pintype "passive"))
    )
    (net (code "378") (name "Net-(IC33-Pad42)") (class "Default")
      (node (ref "IC33") (pin "42") (pinfunction "42_42") (pintype "passive"))
      (node (ref "IC34") (pin "42") (pinfunction "42_42") (pintype "passive"))
      (node (ref "IC35") (pin "42") (pinfunction "42_42") (pintype "passive"))
      (node (ref "IC36") (pin "42") (pinfunction "42_42") (pintype "passive"))
    )
    (net (code "379") (name "Net-(IC37-Pad1)") (class "Default")
      (node (ref "IC37") (pin "1") (pinfunction "1_1") (pintype "passive"))
      (node (ref "IC38") (pin "1") (pinfunction "1_1") (pintype "passive"))
      (node (ref "IC39") (pin "1") (pinfunction "1_1") (pintype "passive"))
      (node (ref "IC40") (pin "1") (pinfunction "1_1") (pintype "passive"))
    )
    (net (code "380") (name "Net-(IC37-Pad2)") (class "Default")
      (node (ref "IC37") (pin "2") (pinfunction "2_2") (pintype "passive"))
      (node (ref "IC38") (pin "2") (pinfunction "2_2") (pintype "passive"))
      (node (ref "IC39") (pin "2") (pinfunction "2_2") (pintype "passive"))
      (node (ref "IC40") (pin "2") (pinfunction "2_2") (pintype "passive"))
    )
    (net (code "381") (name "Net-(IC37-Pad3)") (class "Default")
      (node (ref "IC37") (pin "3") (pinfunction "3_3") (pintype "passive"))
      (node (ref "IC38") (pin "3") (pinfunction "3_3") (pintype "passive"))
      (node (ref "IC39") (pin "3") (pinfunction "3_3") (pintype "passive"))
      (node (ref "IC40") (pin "3") (pinfunction "3_3") (pintype "passive"))
    )
    (net (code "382") (name "Net-(IC37-Pad4)") (class "Default")
      (node (ref "IC37") (pin "4") (pinfunction "4_4") (pintype "passive"))
      (node (ref "IC38") (pin "4") (pinfunction "4_4") (pintype "passive"))
      (node (ref "IC39") (pin "4") (pinfunction "4_4") (pintype "passive"))
      (node (ref "IC40") (pin "4") (pinfunction "4_4") (pintype "passive"))
    )
    (net (code "383") (name "Net-(IC37-Pad5)") (class "Default")
      (node (ref "IC37") (pin "5") (pinfunction "5_5") (pintype "passive"))
      (node (ref "IC38") (pin "5") (pinfunction "5_5") (pintype "passive"))
      (node (ref "IC39") (pin "5") (pinfunction "5_5") (pintype "passive"))
      (node (ref "IC40") (pin "5") (pinfunction "5_5") (pintype "passive"))
    )
    (net (code "384") (name "Net-(IC37-Pad6)") (class "Default")
      (node (ref "IC37") (pin "6") (pinfunction "6_6") (pintype "passive"))
      (node (ref "IC38") (pin "6") (pinfunction "6_6") (pintype "passive"))
      (node (ref "IC39") (pin "6") (pinfunction "6_6") (pintype "passive"))
      (node (ref "IC40") (pin "6") (pinfunction "6_6") (pintype "passive"))
    )
    (net (code "385") (name "Net-(IC37-Pad7)") (class "Default")
      (node (ref "IC37") (pin "7") (pinfunction "7_7") (pintype "passive"))
      (node (ref "IC38") (pin "7") (pinfunction "7_7") (pintype "passive"))
      (node (ref "IC39") (pin "7") (pinfunction "7_7") (pintype "passive"))
      (node (ref "IC40") (pin "7") (pinfunction "7_7") (pintype "passive"))
    )
    (net (code "386") (name "Net-(IC37-Pad8)") (class "Default")
      (node (ref "IC37") (pin "8") (pinfunction "8_8") (pintype "passive"))
      (node (ref "IC38") (pin "8") (pinfunction "8_8") (pintype "passive"))
      (node (ref "IC39") (pin "8") (pinfunction "8_8") (pintype "passive"))
      (node (ref "IC40") (pin "8") (pinfunction "8_8") (pintype "passive"))
    )
    (net (code "387") (name "Net-(IC37-Pad9)") (class "Default")
      (node (ref "IC37") (pin "9") (pinfunction "9_9") (pintype "passive"))
      (node (ref "IC38") (pin "9") (pinfunction "9_9") (pintype "passive"))
      (node (ref "IC39") (pin "9") (pinfunction "9_9") (pintype "passive"))
      (node (ref "IC40") (pin "9") (pinfunction "9_9") (pintype "passive"))
    )
    (net (code "388") (name "Net-(IC37-Pad10)") (class "Default")
      (node (ref "IC37") (pin "10") (pinfunction "10_10") (pintype "passive"))
      (node (ref "IC38") (pin "10") (pinfunction "10_10") (pintype "passive"))
      (node (ref "IC39") (pin "10") (pinfunction "10_10") (pintype "passive"))
      (node (ref "IC40") (pin "10") (pinfunction "10_10") (pintype "passive"))
    )
    (net (code "389") (name "Net-(IC37-Pad11)") (class "Default")
      (node (ref "IC37") (pin "11") (pinfunction "11_11") (pintype "passive"))
      (node (ref "IC38") (pin "11") (pinfunction "11_11") (pintype "passive"))
      (node (ref "IC39") (pin "11") (pinfunction "11_11") (pintype "passive"))
      (node (ref "IC40") (pin "11") (pinfunction "11_11") (pintype "passive"))
    )
    (net (code "390") (name "Net-(IC37-Pad12)") (class "Default")
      (node (ref "IC37") (pin "12") (pinfunction "12_12") (pintype "passive"))
      (node (ref "IC38") (pin "12") (pinfunction "12_12") (pintype "passive"))
      (node (ref "IC39") (pin "12") (pinfunction "12_12") (pintype "passive"))
      (node (ref "IC40") (pin "12") (pinfunction "12_12") (pintype "passive"))
    )
    (net (code "391") (name "Net-(IC37-Pad13)") (class "Default")
      (node (ref "IC37") (pin "13") (pinfunction "13_13") (pintype "passive"))
      (node (ref "IC38") (pin "13") (pinfunction "13_13") (pintype "passive"))
      (node (ref "IC39") (pin "13") (pinfunction "13_13") (pintype "passive"))
      (node (ref "IC40") (pin "13") (pinfunction "13_13") (pintype "passive"))
    )
    (net (code "392") (name "Net-(IC37-Pad14)") (class "Default")
      (node (ref "IC37") (pin "14") (pinfunction "14_14") (pintype "passive"))
      (node (ref "IC38") (pin "14") (pinfunction "14_14") (pintype "passive"))
      (node (ref "IC39") (pin "14") (pinfunction "14_14") (pintype "passive"))
      (node (ref "IC40") (pin "14") (pinfunction "14_14") (pintype "passive"))
    )
    (net (code "393") (name "Net-(IC37-Pad15)") (class "Default")
      (node (ref "IC37") (pin "15") (pinfunction "15_15") (pintype "passive"))
      (node (ref "IC38") (pin "15") (pinfunction "15_15") (pintype "passive"))
      (node (ref "IC39") (pin "15") (pinfunction "15_15") (pintype "passive"))
      (node (ref "IC40") (pin "15") (pinfunction "15_15") (pintype "passive"))
    )
    (net (code "394") (name "Net-(IC37-Pad16)") (class "Default")
      (node (ref "IC37") (pin "16") (pinfunction "16_16") (pintype "passive"))
      (node (ref "IC38") (pin "16") (pinfunction "16_16") (pintype "passive"))
      (node (ref "IC39") (pin "16") (pinfunction "16_16") (pintype "passive"))
      (node (ref "IC40") (pin "16") (pinfunction "16_16") (pintype "passive"))
    )
    (net (code "395") (name "Net-(IC37-Pad17)") (class "Default")
      (node (ref "IC37") (pin "17") (pinfunction "17_17") (pintype "passive"))
      (node (ref "IC38") (pin "17") (pinfunction "17_17") (pintype "passive"))
      (node (ref "IC39") (pin "17") (pinfunction "17_17") (pintype "passive"))
      (node (ref "IC40") (pin "17") (pinfunction "17_17") (pintype "passive"))
    )
    (net (code "396") (name "Net-(IC37-Pad18)") (class "Default")
      (node (ref "IC37") (pin "18") (pinfunction "18_18") (pintype "passive"))
      (node (ref "IC38") (pin "18") (pinfunction "18_18") (pintype "passive"))
      (node (ref "IC39") (pin "18") (pinfunction "18_18") (pintype "passive"))
      (node (ref "IC40") (pin "18") (pinfunction "18_18") (pintype "passive"))
    )
    (net (code "397") (name "Net-(IC37-Pad19)") (class "Default")
      (node (ref "IC37") (pin "19") (pinfunction "19_19") (pintype "passive"))
      (node (ref "IC38") (pin "19") (pinfunction "19_19") (pintype "passive"))
      (node (ref "IC39") (pin "19") (pinfunction "19_19") (pintype "passive"))
      (node (ref "IC40") (pin "19") (pinfunction "19_19") (pintype "passive"))
    )
    (net (code "398") (name "Net-(IC37-Pad20)") (class "Default")
      (node (ref "IC37") (pin "20") (pinfunction "20_20") (pintype "passive"))
      (node (ref "IC38") (pin "20") (pinfunction "20_20") (pintype "passive"))
      (node (ref "IC39") (pin "20") (pinfunction "20_20") (pintype "passive"))
      (node (ref "IC40") (pin "20") (pinfunction "20_20") (pintype "passive"))
    )
    (net (code "399") (name "Net-(IC37-Pad21)") (class "Default")
      (node (ref "IC37") (pin "21") (pinfunction "21_21") (pintype "passive"))
      (node (ref "IC38") (pin "21") (pinfunction "21_21") (pintype "passive"))
      (node (ref "IC39") (pin "21") (pinfunction "21_21") (pintype "passive"))
      (node (ref "IC40") (pin "21") (pinfunction "21_21") (pintype "passive"))
    )
    (net (code "400") (name "Net-(IC37-Pad22)") (class "Default")
      (node (ref "IC37") (pin "22") (pinfunction "22_22") (pintype "passive"))
      (node (ref "IC38") (pin "22") (pinfunction "22_22") (pintype "passive"))
      (node (ref "IC39") (pin "22") (pinfunction "22_22") (pintype "passive"))
      (node (ref "IC40") (pin "22") (pinfunction "22_22") (pintype "passive"))
    )
    (net (code "401") (name "Net-(IC37-Pad23)") (class "Default")
      (node (ref "IC37") (pin "23") (pinfunction "23_23") (pintype "passive"))
      (node (ref "IC38") (pin "23") (pinfunction "23_23") (pintype "passive"))
      (node (ref "IC39") (pin "23") (pinfunction "23_23") (pintype "passive"))
      (node (ref "IC40") (pin "23") (pinfunction "23_23") (pintype "passive"))
    )
    (net (code "402") (name "Net-(IC37-Pad24)") (class "Default")
      (node (ref "IC37") (pin "24") (pinfunction "24_24") (pintype "passive"))
      (node (ref "IC38") (pin "24") (pinfunction "24_24") (pintype "passive"))
      (node (ref "IC39") (pin "24") (pinfunction "24_24") (pintype "passive"))
      (node (ref "IC40") (pin "24") (pinfunction "24_24") (pintype "passive"))
    )
    (net (code "403") (name "Net-(IC37-Pad25)") (class "Default")
      (node (ref "IC37") (pin "25") (pinfunction "25_25") (pintype "passive"))
      (node (ref "IC38") (pin "25") (pinfunction "25_25") (pintype "passive"))
      (node (ref "IC39") (pin "25") (pinfunction "25_25") (pintype "passive"))
      (node (ref "IC40") (pin "25") (pinfunction "25_25") (pintype "passive"))
    )
    (net (code "404") (name "Net-(IC37-Pad26)") (class "Default")
      (node (ref "IC37") (pin "26") (pinfunction "26_26") (pintype "passive"))
      (node (ref "IC38") (pin "26") (pinfunction "26_26") (pintype "passive"))
      (node (ref "IC39") (pin "26") (pinfunction "26_26") (pintype "passive"))
      (node (ref "IC40") (pin "26") (pinfunction "26_26") (pintype "passive"))
    )
    (net (code "405") (name "Net-(IC37-Pad27)") (class "Default")
      (node (ref "IC37") (pin "27") (pinfunction "27_27") (pintype "passive"))
      (node (ref "IC38") (pin "27") (pinfunction "27_27") (pintype "passive"))
      (node (ref "IC39") (pin "27") (pinfunction "27_27") (pintype "passive"))
      (node (ref "IC40") (pin "27") (pinfunction "27_27") (pintype "passive"))
    )
    (net (code "406") (name "Net-(IC37-Pad28)") (class "Default")
      (node (ref "IC37") (pin "28") (pinfunction "28_28") (pintype "passive"))
      (node (ref "IC38") (pin "28") (pinfunction "28_28") (pintype "passive"))
      (node (ref "IC39") (pin "28") (pinfunction "28_28") (pintype "passive"))
      (node (ref "IC40") (pin "28") (pinfunction "28_28") (pintype "passive"))
    )
    (net (code "407") (name "Net-(IC37-Pad29)") (class "Default")
      (node (ref "IC37") (pin "29") (pinfunction "29_29") (pintype "passive"))
      (node (ref "IC38") (pin "29") (pinfunction "29_29") (pintype "passive"))
      (node (ref "IC39") (pin "29") (pinfunction "29_29") (pintype "passive"))
      (node (ref "IC40") (pin "29") (pinfunction "29_29") (pintype "passive"))
    )
    (net (code "408") (name "Net-(IC37-Pad30)") (class "Default")
      (node (ref "IC37") (pin "30") (pinfunction "30_30") (pintype "passive"))
      (node (ref "IC38") (pin "30") (pinfunction "30_30") (pintype "passive"))
      (node (ref "IC39") (pin "30") (pinfunction "30_30") (pintype "passive"))
      (node (ref "IC40") (pin "30") (pinfunction "30_30") (pintype "passive"))
    )
    (net (code "409") (name "Net-(IC37-Pad31)") (class "Default")
      (node (ref "IC37") (pin "31") (pinfunction "31_31") (pintype "passive"))
      (node (ref "IC38") (pin "31") (pinfunction "31_31") (pintype "passive"))
      (node (ref "IC39") (pin "31") (pinfunction "31_31") (pintype "passive"))
      (node (ref "IC40") (pin "31") (pinfunction "31_31") (pintype "passive"))
    )
    (net (code "410") (name "Net-(IC37-Pad32)") (class "Default")
      (node (ref "IC37") (pin "32") (pinfunction "32_32") (pintype "passive"))
      (node (ref "IC38") (pin "32") (pinfunction "32_32") (pintype "passive"))
      (node (ref "IC39") (pin "32") (pinfunction "32_32") (pintype "passive"))
      (node (ref "IC40") (pin "32") (pinfunction "32_32") (pintype "passive"))
    )
    (net (code "411") (name "Net-(IC37-Pad33)") (class "Default")
      (node (ref "IC37") (pin "33") (pinfunction "33_33") (pintype "passive"))
      (node (ref "IC38") (pin "33") (pinfunction "33_33") (pintype "passive"))
      (node (ref "IC39") (pin "33") (pinfunction "33_33") (pintype "passive"))
      (node (ref "IC40") (pin "33") (pinfunction "33_33") (pintype "passive"))
    )
    (net (code "412") (name "Net-(IC37-Pad34)") (class "Default")
      (node (ref "IC37") (pin "34") (pinfunction "34_34") (pintype "passive"))
      (node (ref "IC38") (pin "34") (pinfunction "34_34") (pintype "passive"))
      (node (ref "IC39") (pin "34") (pinfunction "34_34") (pintype "passive"))
      (node (ref "IC40") (pin "34") (pinfunction "34_34") (pintype "passive"))
    )
    (net (code "413") (name "Net-(IC37-Pad35)") (class "Default")
      (node (ref "IC37") (pin "35") (pinfunction "35_35") (pintype "passive"))
      (node (ref "IC38") (pin "35") (pinfunction "35_35") (pintype "passive"))
      (node (ref "IC39") (pin "35") (pinfunction "35_35") (pintype "passive"))
      (node (ref "IC40") (pin "35") (pinfunction "35_35") (pintype "passive"))
    )
    (net (code "414") (name "Net-(IC37-Pad36)") (class "Default")
      (node (ref "IC37") (pin "36") (pinfunction "36_36") (pintype "passive"))
      (node (ref "IC38") (pin "36") (pinfunction "36_36") (pintype "passive"))
      (node (ref "IC39") (pin "36") (pinfunction "36_36") (pintype "passive"))
      (node (ref "IC40") (pin "36") (pinfunction "36_36") (pintype "passive"))
    )
    (net (code "415") (name "Net-(IC37-Pad37)") (class "Default")
      (node (ref "IC37") (pin "37") (pinfunction "37_37") (pintype "passive"))
      (node (ref "IC38") (pin "37") (pinfunction "37_37") (pintype "passive"))
      (node (ref "IC39") (pin "37") (pinfunction "37_37") (pintype "passive"))
      (node (ref "IC40") (pin "37") (pinfunction "37_37") (pintype "passive"))
    )
    (net (code "416") (name "Net-(IC37-Pad38)") (class "Default")
      (node (ref "IC37") (pin "38") (pinfunction "38_38") (pintype "passive"))
      (node (ref "IC38") (pin "38") (pinfunction "38_38") (pintype "passive"))
      (node (ref "IC39") (pin "38") (pinfunction "38_38") (pintype "passive"))
      (node (ref "IC40") (pin "38") (pinfunction "38_38") (pintype "passive"))
    )
    (net (code "417") (name "Net-(IC37-Pad39)") (class "Default")
      (node (ref "IC37") (pin "39") (pinfunction "39_39") (pintype "passive"))
      (node (ref "IC38") (pin "39") (pinfunction "39_39") (pintype "passive"))
      (node (ref "IC39") (pin "39") (pinfunction "39_39") (pintype "passive"))
      (node (ref "IC40") (pin "39") (pinfunction "39_39") (pintype "passive"))
    )
    (net (code "418") (name "Net-(IC37-Pad40)") (class "Default")
      (node (ref "IC37") (pin "40") (pinfunction "40_40") (pintype "passive"))
      (node (ref "IC38") (pin "40") (pinfunction "40_40") (pintype "passive"))
      (node (ref "IC39") (pin "40") (pinfunction "40_40") (pintype "passive"))
      (node (ref "IC40") (pin "40") (pinfunction "40_40") (pintype "passive"))
    )
    (net (code "419") (name "Net-(IC37-Pad41)") (class "Default")
      (node (ref "IC37") (pin "41") (pinfunction "41_41") (pintype "passive"))
      (node (ref "IC38") (pin "41") (pinfunction "41_41") (pintype "passive"))
      (node (ref "IC39") (pin "41") (pinfunction "41_41") (pintype "passive"))
      (node (ref "IC40") (pin "41") (pinfunction "41_41") (pintype "passive"))
    )
    (net (code "420") (name "Net-(IC37-Pad42)") (class "Default")
      (node (ref "IC37") (pin "42") (pinfunction "42_42") (pintype "passive"))
      (node (ref "IC38") (pin "42") (pinfunction "42_42") (pintype "passive"))
      (node (ref "IC39") (pin "42") (pinfunction "42_42") (pintype "passive"))
      (node (ref "IC40") (pin "42") (pinfunction "42_42") (pintype "passive"))
    )
    (net (code "421") (name "Net-(IC41-Pad1)") (class "Default")
      (node (ref "IC41") (pin "1") (pinfunction "1_1") (pintype "passive"))
      (node (ref "IC42") (pin "1") (pinfunction "1_1") (pintype "passive"))
      (node (ref "IC43") (pin "1") (pinfunction "1_1") (pintype "passive"))
      (node (ref "IC44") (pin "1") (pinfunction "1_1") (pintype "passive"))
    )
    (net (code "422") (name "Net-(IC41-Pad2)") (class "Default")
      (node (ref "IC41") (pin "2") (pinfunction "2_2") (pintype "passive"))
      (node (ref "IC42") (pin "2") (pinfunction "2_2") (pintype "passive"))
      (node (ref "IC43") (pin "2") (pinfunction "2_2") (pintype "passive"))
      (node (ref "IC44") (pin "2") (pinfunction "2_2") (pintype "passive"))
    )
    (net (code "423") (name "Net-(IC41-Pad3)") (class "Default")
      (node (ref "IC41") (pin "3") (pinfunction "3_3") (pintype "passive"))
      (node (ref "IC42") (pin "3") (pinfunction "3_3") (pintype "passive"))
      (node (ref "IC43") (pin "3") (pinfunction "3_3") (pintype "passive"))
      (node (ref "IC44") (pin "3") (pinfunction "3_3") (pintype "passive"))
    )
    (net (code "424") (name "Net-(IC41-Pad4)") (class "Default")
      (node (ref "IC41") (pin "4") (pinfunction "4_4") (pintype "passive"))
      (node (ref "IC42") (pin "4") (pinfunction "4_4") (pintype "passive"))
      (node (ref "IC43") (pin "4") (pinfunction "4_4") (pintype "passive"))
      (node (ref "IC44") (pin "4") (pinfunction "4_4") (pintype "passive"))
    )
    (net (code "425") (name "Net-(IC41-Pad5)") (class "Default")
      (node (ref "IC41") (pin "5") (pinfunction "5_5") (pintype "passive"))
      (node (ref "IC42") (pin "5") (pinfunction "5_5") (pintype "passive"))
      (node (ref "IC43") (pin "5") (pinfunction "5_5") (pintype "passive"))
      (node (ref "IC44") (pin "5") (pinfunction "5_5") (pintype "passive"))
    )
    (net (code "426") (name "Net-(IC41-Pad6)") (class "Default")
      (node (ref "IC41") (pin "6") (pinfunction "6_6") (pintype "passive"))
      (node (ref "IC42") (pin "6") (pinfunction "6_6") (pintype "passive"))
      (node (ref "IC43") (pin "6") (pinfunction "6_6") (pintype "passive"))
      (node (ref "IC44") (pin "6") (pinfunction "6_6") (pintype "passive"))
    )
    (net (code "427") (name "Net-(IC41-Pad7)") (class "Default")
      (node (ref "IC41") (pin "7") (pinfunction "7_7") (pintype "passive"))
      (node (ref "IC42") (pin "7") (pinfunction "7_7") (pintype "passive"))
      (node (ref "IC43") (pin "7") (pinfunction "7_7") (pintype "passive"))
      (node (ref "IC44") (pin "7") (pinfunction "7_7") (pintype "passive"))
    )
    (net (code "428") (name "Net-(IC41-Pad8)") (class "Default")
      (node (ref "IC41") (pin "8") (pinfunction "8_8") (pintype "passive"))
      (node (ref "IC42") (pin "8") (pinfunction "8_8") (pintype "passive"))
      (node (ref "IC43") (pin "8") (pinfunction "8_8") (pintype "passive"))
      (node (ref "IC44") (pin "8") (pinfunction "8_8") (pintype "passive"))
    )
    (net (code "429") (name "Net-(IC41-Pad9)") (class "Default")
      (node (ref "IC41") (pin "9") (pinfunction "9_9") (pintype "passive"))
      (node (ref "IC42") (pin "9") (pinfunction "9_9") (pintype "passive"))
      (node (ref "IC43") (pin "9") (pinfunction "9_9") (pintype "passive"))
      (node (ref "IC44") (pin "9") (pinfunction "9_9") (pintype "passive"))
    )
    (net (code "430") (name "Net-(IC41-Pad10)") (class "Default")
      (node (ref "IC41") (pin "10") (pinfunction "10_10") (pintype "passive"))
      (node (ref "IC42") (pin "10") (pinfunction "10_10") (pintype "passive"))
      (node (ref "IC43") (pin "10") (pinfunction "10_10") (pintype "passive"))
      (node (ref "IC44") (pin "10") (pinfunction "10_10") (pintype "passive"))
    )
    (net (code "431") (name "Net-(IC41-Pad11)") (class "Default")
      (node (ref "IC41") (pin "11") (pinfunction "11_11") (pintype "passive"))
      (node (ref "IC42") (pin "11") (pinfunction "11_11") (pintype "passive"))
      (node (ref "IC43") (pin "11") (pinfunction "11_11") (pintype "passive"))
      (node (ref "IC44") (pin "11") (pinfunction "11_11") (pintype "passive"))
    )
    (net (code "432") (name "Net-(IC41-Pad12)") (class "Default")
      (node (ref "IC41") (pin "12") (pinfunction "12_12") (pintype "passive"))
      (node (ref "IC42") (pin "12") (pinfunction "12_12") (pintype "passive"))
      (node (ref "IC43") (pin "12") (pinfunction "12_12") (pintype "passive"))
      (node (ref "IC44") (pin "12") (pinfunction "12_12") (pintype "passive"))
    )
    (net (code "433") (name "Net-(IC41-Pad13)") (class "Default")
      (node (ref "IC41") (pin "13") (pinfunction "13_13") (pintype "passive"))
      (node (ref "IC42") (pin "13") (pinfunction "13_13") (pintype "passive"))
      (node (ref "IC43") (pin "13") (pinfunction "13_13") (pintype "passive"))
      (node (ref "IC44") (pin "13") (pinfunction "13_13") (pintype "passive"))
    )
    (net (code "434") (name "Net-(IC41-Pad14)") (class "Default")
      (node (ref "IC41") (pin "14") (pinfunction "14_14") (pintype "passive"))
      (node (ref "IC42") (pin "14") (pinfunction "14_14") (pintype "passive"))
      (node (ref "IC43") (pin "14") (pinfunction "14_14") (pintype "passive"))
      (node (ref "IC44") (pin "14") (pinfunction "14_14") (pintype "passive"))
    )
    (net (code "435") (name "Net-(IC41-Pad15)") (class "Default")
      (node (ref "IC41") (pin "15") (pinfunction "15_15") (pintype "passive"))
      (node (ref "IC42") (pin "15") (pinfunction "15_15") (pintype "passive"))
      (node (ref "IC43") (pin "15") (pinfunction "15_15") (pintype "passive"))
      (node (ref "IC44") (pin "15") (pinfunction "15_15") (pintype "passive"))
    )
    (net (code "436") (name "Net-(IC41-Pad16)") (class "Default")
      (node (ref "IC41") (pin "16") (pinfunction "16_16") (pintype "passive"))
      (node (ref "IC42") (pin "16") (pinfunction "16_16") (pintype "passive"))
      (node (ref "IC43") (pin "16") (pinfunction "16_16") (pintype "passive"))
      (node (ref "IC44") (pin "16") (pinfunction "16_16") (pintype "passive"))
    )
    (net (code "437") (name "Net-(IC41-Pad17)") (class "Default")
      (node (ref "IC41") (pin "17") (pinfunction "17_17") (pintype "passive"))
      (node (ref "IC42") (pin "17") (pinfunction "17_17") (pintype "passive"))
      (node (ref "IC43") (pin "17") (pinfunction "17_17") (pintype "passive"))
      (node (ref "IC44") (pin "17") (pinfunction "17_17") (pintype "passive"))
    )
    (net (code "438") (name "Net-(IC41-Pad18)") (class "Default")
      (node (ref "IC41") (pin "18") (pinfunction "18_18") (pintype "passive"))
      (node (ref "IC42") (pin "18") (pinfunction "18_18") (pintype "passive"))
      (node (ref "IC43") (pin "18") (pinfunction "18_18") (pintype "passive"))
      (node (ref "IC44") (pin "18") (pinfunction "18_18") (pintype "passive"))
    )
    (net (code "439") (name "Net-(IC41-Pad19)") (class "Default")
      (node (ref "IC41") (pin "19") (pinfunction "19_19") (pintype "passive"))
      (node (ref "IC42") (pin "19") (pinfunction "19_19") (pintype "passive"))
      (node (ref "IC43") (pin "19") (pinfunction "19_19") (pintype "passive"))
      (node (ref "IC44") (pin "19") (pinfunction "19_19") (pintype "passive"))
    )
    (net (code "440") (name "Net-(IC41-Pad20)") (class "Default")
      (node (ref "IC41") (pin "20") (pinfunction "20_20") (pintype "passive"))
      (node (ref "IC42") (pin "20") (pinfunction "20_20") (pintype "passive"))
      (node (ref "IC43") (pin "20") (pinfunction "20_20") (pintype "passive"))
      (node (ref "IC44") (pin "20") (pinfunction "20_20") (pintype "passive"))
    )
    (net (code "441") (name "Net-(IC41-Pad21)") (class "Default")
      (node (ref "IC41") (pin "21") (pinfunction "21_21") (pintype "passive"))
      (node (ref "IC42") (pin "21") (pinfunction "21_21") (pintype "passive"))
      (node (ref "IC43") (pin "21") (pinfunction "21_21") (pintype "passive"))
      (node (ref "IC44") (pin "21") (pinfunction "21_21") (pintype "passive"))
    )
    (net (code "442") (name "Net-(IC41-Pad22)") (class "Default")
      (node (ref "IC41") (pin "22") (pinfunction "22_22") (pintype "passive"))
      (node (ref "IC42") (pin "22") (pinfunction "22_22") (pintype "passive"))
      (node (ref "IC43") (pin "22") (pinfunction "22_22") (pintype "passive"))
      (node (ref "IC44") (pin "22") (pinfunction "22_22") (pintype "passive"))
    )
    (net (code "443") (name "Net-(IC41-Pad23)") (class "Default")
      (node (ref "IC41") (pin "23") (pinfunction "23_23") (pintype "passive"))
      (node (ref "IC42") (pin "23") (pinfunction "23_23") (pintype "passive"))
      (node (ref "IC43") (pin "23") (pinfunction "23_23") (pintype "passive"))
      (node (ref "IC44") (pin "23") (pinfunction "23_23") (pintype "passive"))
    )
    (net (code "444") (name "Net-(IC41-Pad24)") (class "Default")
      (node (ref "IC41") (pin "24") (pinfunction "24_24") (pintype "passive"))
      (node (ref "IC42") (pin "24") (pinfunction "24_24") (pintype "passive"))
      (node (ref "IC43") (pin "24") (pinfunction "24_24") (pintype "passive"))
      (node (ref "IC44") (pin "24") (pinfunction "24_24") (pintype "passive"))
    )
    (net (code "445") (name "Net-(IC41-Pad25)") (class "Default")
      (node (ref "IC41") (pin "25") (pinfunction "25_25") (pintype "passive"))
      (node (ref "IC42") (pin "25") (pinfunction "25_25") (pintype "passive"))
      (node (ref "IC43") (pin "25") (pinfunction "25_25") (pintype "passive"))
      (node (ref "IC44") (pin "25") (pinfunction "25_25") (pintype "passive"))
    )
    (net (code "446") (name "Net-(IC41-Pad26)") (class "Default")
      (node (ref "IC41") (pin "26") (pinfunction "26_26") (pintype "passive"))
      (node (ref "IC42") (pin "26") (pinfunction "26_26") (pintype "passive"))
      (node (ref "IC43") (pin "26") (pinfunction "26_26") (pintype "passive"))
      (node (ref "IC44") (pin "26") (pinfunction "26_26") (pintype "passive"))
    )
    (net (code "447") (name "Net-(IC41-Pad27)") (class "Default")
      (node (ref "IC41") (pin "27") (pinfunction "27_27") (pintype "passive"))
      (node (ref "IC42") (pin "27") (pinfunction "27_27") (pintype "passive"))
      (node (ref "IC43") (pin "27") (pinfunction "27_27") (pintype "passive"))
      (node (ref "IC44") (pin "27") (pinfunction "27_27") (pintype "passive"))
    )
    (net (code "448") (name "Net-(IC41-Pad28)") (class "Default")
      (node (ref "IC41") (pin "28") (pinfunction "28_28") (pintype "passive"))
      (node (ref "IC42") (pin "28") (pinfunction "28_28") (pintype "passive"))
      (node (ref "IC43") (pin "28") (pinfunction "28_28") (pintype "passive"))
      (node (ref "IC44") (pin "28") (pinfunction "28_28") (pintype "passive"))
    )
    (net (code "449") (name "Net-(IC41-Pad29)") (class "Default")
      (node (ref "IC41") (pin "29") (pinfunction "29_29") (pintype "passive"))
      (node (ref "IC42") (pin "29") (pinfunction "29_29") (pintype "passive"))
      (node (ref "IC43") (pin "29") (pinfunction "29_29") (pintype "passive"))
      (node (ref "IC44") (pin "29") (pinfunction "29_29") (pintype "passive"))
    )
    (net (code "450") (name "Net-(IC41-Pad30)") (class "Default")
      (node (ref "IC41") (pin "30") (pinfunction "30_30") (pintype "passive"))
      (node (ref "IC42") (pin "30") (pinfunction "30_30") (pintype "passive"))
      (node (ref "IC43") (pin "30") (pinfunction "30_30") (pintype "passive"))
      (node (ref "IC44") (pin "30") (pinfunction "30_30") (pintype "passive"))
    )
    (net (code "451") (name "Net-(IC41-Pad31)") (class "Default")
      (node (ref "IC41") (pin "31") (pinfunction "31_31") (pintype "passive"))
      (node (ref "IC42") (pin "31") (pinfunction "31_31") (pintype "passive"))
      (node (ref "IC43") (pin "31") (pinfunction "31_31") (pintype "passive"))
      (node (ref "IC44") (pin "31") (pinfunction "31_31") (pintype "passive"))
    )
    (net (code "452") (name "Net-(IC41-Pad32)") (class "Default")
      (node (ref "IC41") (pin "32") (pinfunction "32_32") (pintype "passive"))
      (node (ref "IC42") (pin "32") (pinfunction "32_32") (pintype "passive"))
      (node (ref "IC43") (pin "32") (pinfunction "32_32") (pintype "passive"))
      (node (ref "IC44") (pin "32") (pinfunction "32_32") (pintype "passive"))
    )
    (net (code "453") (name "Net-(IC41-Pad33)") (class "Default")
      (node (ref "IC41") (pin "33") (pinfunction "33_33") (pintype "passive"))
      (node (ref "IC42") (pin "33") (pinfunction "33_33") (pintype "passive"))
      (node (ref "IC43") (pin "33") (pinfunction "33_33") (pintype "passive"))
      (node (ref "IC44") (pin "33") (pinfunction "33_33") (pintype "passive"))
    )
    (net (code "454") (name "Net-(IC41-Pad34)") (class "Default")
      (node (ref "IC41") (pin "34") (pinfunction "34_34") (pintype "passive"))
      (node (ref "IC42") (pin "34") (pinfunction "34_34") (pintype "passive"))
      (node (ref "IC43") (pin "34") (pinfunction "34_34") (pintype "passive"))
      (node (ref "IC44") (pin "34") (pinfunction "34_34") (pintype "passive"))
    )
    (net (code "455") (name "Net-(IC41-Pad35)") (class "Default")
      (node (ref "IC41") (pin "35") (pinfunction "35_35") (pintype "passive"))
      (node (ref "IC42") (pin "35") (pinfunction "35_35") (pintype "passive"))
      (node (ref "IC43") (pin "35") (pinfunction "35_35") (pintype "passive"))
      (node (ref "IC44") (pin "35") (pinfunction "35_35") (pintype "passive"))
    )
    (net (code "456") (name "Net-(IC41-Pad36)") (class "Default")
      (node (ref "IC41") (pin "36") (pinfunction "36_36") (pintype "passive"))
      (node (ref "IC42") (pin "36") (pinfunction "36_36") (pintype "passive"))
      (node (ref "IC43") (pin "36") (pinfunction "36_36") (pintype "passive"))
      (node (ref "IC44") (pin "36") (pinfunction "36_36") (pintype "passive"))
    )
    (net (code "457") (name "Net-(IC41-Pad37)") (class "Default")
      (node (ref "IC41") (pin "37") (pinfunction "37_37") (pintype "passive"))
      (node (ref "IC42") (pin "37") (pinfunction "37_37") (pintype "passive"))
      (node (ref "IC43") (pin "37") (pinfunction "37_37") (pintype "passive"))
      (node (ref "IC44") (pin "37") (pinfunction "37_37") (pintype "passive"))
    )
    (net (code "458") (name "Net-(IC41-Pad38)") (class "Default")
      (node (ref "IC41") (pin "38") (pinfunction "38_38") (pintype "passive"))
      (node (ref "IC42") (pin "38") (pinfunction "38_38") (pintype "passive"))
      (node (ref "IC43") (pin "38") (pinfunction "38_38") (pintype "passive"))
      (node (ref "IC44") (pin "38") (pinfunction "38_38") (pintype "passive"))
    )
    (net (code "459") (name "Net-(IC41-Pad39)") (class "Default")
      (node (ref "IC41") (pin "39") (pinfunction "39_39") (pintype "passive"))
      (node (ref "IC42") (pin "39") (pinfunction "39_39") (pintype "passive"))
      (node (ref "IC43") (pin "39") (pinfunction "39_39") (pintype "passive"))
      (node (ref "IC44") (pin "39") (pinfunction "39_39") (pintype "passive"))
    )
    (net (code "460") (name "Net-(IC41-Pad40)") (class "Default")
      (node (ref "IC41") (pin "40") (pinfunction "40_40") (pintype "passive"))
      (node (ref "IC42") (pin "40") (pinfunction "40_40") (pintype "passive"))
      (node (ref "IC43") (pin "40") (pinfunction "40_40") (pintype "passive"))
      (node (ref "IC44") (pin "40") (pinfunction "40_40") (pintype "passive"))
    )
    (net (code "461") (name "Net-(IC41-Pad41)") (class "Default")
      (node (ref "IC41") (pin "41") (pinfunction "41_41") (pintype "passive"))
      (node (ref "IC42") (pin "41") (pinfunction "41_41") (pintype "passive"))
      (node (ref "IC43") (pin "41") (pinfunction "41_41") (pintype "passive"))
      (node (ref "IC44") (pin "41") (pinfunction "41_41") (pintype "passive"))
    )
    (net (code "462") (name "Net-(IC41-Pad42)") (class "Default")
      (node (ref "IC41") (pin "42") (pinfunction "42_42") (pintype "passive"))
      (node (ref "IC42") (pin "42") (pinfunction "42_42") (pintype "passive"))
      (node (ref "IC43") (pin "42") (pinfunction "42_42") (pintype "passive"))
      (node (ref "IC44") (pin "42") (pinfunction "42_42") (pintype "passive"))
    )
    (net (code "463") (name "Net-(IC45-Pad1)") (class "Default")
      (node (ref "IC45") (pin "1") (pinfunction "1_1") (pintype "passive"))
      (node (ref "IC46") (pin "1") (pinfunction "1_1") (pintype "passive"))
      (node (ref "IC47") (pin "1") (pinfunction "1_1") (pintype "passive"))
      (node (ref "IC48") (pin "1") (pinfunction "1_1") (pintype "passive"))
    )
    (net (code "464") (name "Net-(IC45-Pad2)") (class "Default")
      (node (ref "IC45") (pin "2") (pinfunction "2_2") (pintype "passive"))
      (node (ref "IC46") (pin "2") (pinfunction "2_2") (pintype "passive"))
      (node (ref "IC47") (pin "2") (pinfunction "2_2") (pintype "passive"))
      (node (ref "IC48") (pin "2") (pinfunction "2_2") (pintype "passive"))
    )
    (net (code "465") (name "Net-(IC45-Pad3)") (class "Default")
      (node (ref "IC45") (pin "3") (pinfunction "3_3") (pintype "passive"))
      (node (ref "IC46") (pin "3") (pinfunction "3_3") (pintype "passive"))
      (node (ref "IC47") (pin "3") (pinfunction "3_3") (pintype "passive"))
      (node (ref "IC48") (pin "3") (pinfunction "3_3") (pintype "passive"))
    )
    (net (code "466") (name "Net-(IC45-Pad4)") (class "Default")
      (node (ref "IC45") (pin "4") (pinfunction "4_4") (pintype "passive"))
      (node (ref "IC46") (pin "4") (pinfunction "4_4") (pintype "passive"))
      (node (ref "IC47") (pin "4") (pinfunction "4_4") (pintype "passive"))
      (node (ref "IC48") (pin "4") (pinfunction "4_4") (pintype "passive"))
    )
    (net (code "467") (name "Net-(IC45-Pad5)") (class "Default")
      (node (ref "IC45") (pin "5") (pinfunction "5_5") (pintype "passive"))
      (node (ref "IC46") (pin "5") (pinfunction "5_5") (pintype "passive"))
      (node (ref "IC47") (pin "5") (pinfunction "5_5") (pintype "passive"))
      (node (ref "IC48") (pin "5") (pinfunction "5_5") (pintype "passive"))
    )
    (net (code "468") (name "Net-(IC45-Pad6)") (class "Default")
      (node (ref "IC45") (pin "6") (pinfunction "6_6") (pintype "passive"))
      (node (ref "IC46") (pin "6") (pinfunction "6_6") (pintype "passive"))
      (node (ref "IC47") (pin "6") (pinfunction "6_6") (pintype "passive"))
      (node (ref "IC48") (pin "6") (pinfunction "6_6") (pintype "passive"))
    )
    (net (code "469") (name "Net-(IC45-Pad7)") (class "Default")
      (node (ref "IC45") (pin "7") (pinfunction "7_7") (pintype "passive"))
      (node (ref "IC46") (pin "7") (pinfunction "7_7") (pintype "passive"))
      (node (ref "IC47") (pin "7") (pinfunction "7_7") (pintype "passive"))
      (node (ref "IC48") (pin "7") (pinfunction "7_7") (pintype "passive"))
    )
    (net (code "470") (name "Net-(IC45-Pad8)") (class "Default")
      (node (ref "IC45") (pin "8") (pinfunction "8_8") (pintype "passive"))
      (node (ref "IC46") (pin "8") (pinfunction "8_8") (pintype "passive"))
      (node (ref "IC47") (pin "8") (pinfunction "8_8") (pintype "passive"))
      (node (ref "IC48") (pin "8") (pinfunction "8_8") (pintype "passive"))
    )
    (net (code "471") (name "Net-(IC45-Pad9)") (class "Default")
      (node (ref "IC45") (pin "9") (pinfunction "9_9") (pintype "passive"))
      (node (ref "IC46") (pin "9") (pinfunction "9_9") (pintype "passive"))
      (node (ref "IC47") (pin "9") (pinfunction "9_9") (pintype "passive"))
      (node (ref "IC48") (pin "9") (pinfunction "9_9") (pintype "passive"))
    )
    (net (code "472") (name "Net-(IC45-Pad10)") (class "Default")
      (node (ref "IC45") (pin "10") (pinfunction "10_10") (pintype "passive"))
      (node (ref "IC46") (pin "10") (pinfunction "10_10") (pintype "passive"))
      (node (ref "IC47") (pin "10") (pinfunction "10_10") (pintype "passive"))
      (node (ref "IC48") (pin "10") (pinfunction "10_10") (pintype "passive"))
    )
    (net (code "473") (name "Net-(IC45-Pad11)") (class "Default")
      (node (ref "IC45") (pin "11") (pinfunction "11_11") (pintype "passive"))
      (node (ref "IC46") (pin "11") (pinfunction "11_11") (pintype "passive"))
      (node (ref "IC47") (pin "11") (pinfunction "11_11") (pintype "passive"))
      (node (ref "IC48") (pin "11") (pinfunction "11_11") (pintype "passive"))
    )
    (net (code "474") (name "Net-(IC45-Pad12)") (class "Default")
      (node (ref "IC45") (pin "12") (pinfunction "12_12") (pintype "passive"))
      (node (ref "IC46") (pin "12") (pinfunction "12_12") (pintype "passive"))
      (node (ref "IC47") (pin "12") (pinfunction "12_12") (pintype "passive"))
      (node (ref "IC48") (pin "12") (pinfunction "12_12") (pintype "passive"))
    )
    (net (code "475") (name "Net-(IC45-Pad13)") (class "Default")
      (node (ref "IC45") (pin "13") (pinfunction "13_13") (pintype "passive"))
      (node (ref "IC46") (pin "13") (pinfunction "13_13") (pintype "passive"))
      (node (ref "IC47") (pin "13") (pinfunction "13_13") (pintype "passive"))
      (node (ref "IC48") (pin "13") (pinfunction "13_13") (pintype "passive"))
    )
    (net (code "476") (name "Net-(IC45-Pad14)") (class "Default")
      (node (ref "IC45") (pin "14") (pinfunction "14_14") (pintype "passive"))
      (node (ref "IC46") (pin "14") (pinfunction "14_14") (pintype "passive"))
      (node (ref "IC47") (pin "14") (pinfunction "14_14") (pintype "passive"))
      (node (ref "IC48") (pin "14") (pinfunction "14_14") (pintype "passive"))
    )
    (net (code "477") (name "Net-(IC45-Pad15)") (class "Default")
      (node (ref "IC45") (pin "15") (pinfunction "15_15") (pintype "passive"))
      (node (ref "IC46") (pin "15") (pinfunction "15_15") (pintype "passive"))
      (node (ref "IC47") (pin "15") (pinfunction "15_15") (pintype "passive"))
      (node (ref "IC48") (pin "15") (pinfunction "15_15") (pintype "passive"))
    )
    (net (code "478") (name "Net-(IC45-Pad16)") (class "Default")
      (node (ref "IC45") (pin "16") (pinfunction "16_16") (pintype "passive"))
      (node (ref "IC46") (pin "16") (pinfunction "16_16") (pintype "passive"))
      (node (ref "IC47") (pin "16") (pinfunction "16_16") (pintype "passive"))
      (node (ref "IC48") (pin "16") (pinfunction "16_16") (pintype "passive"))
    )
    (net (code "479") (name "Net-(IC45-Pad17)") (class "Default")
      (node (ref "IC45") (pin "17") (pinfunction "17_17") (pintype "passive"))
      (node (ref "IC46") (pin "17") (pinfunction "17_17") (pintype "passive"))
      (node (ref "IC47") (pin "17") (pinfunction "17_17") (pintype "passive"))
      (node (ref "IC48") (pin "17") (pinfunction "17_17") (pintype "passive"))
    )
    (net (code "480") (name "Net-(IC45-Pad18)") (class "Default")
      (node (ref "IC45") (pin "18") (pinfunction "18_18") (pintype "passive"))
      (node (ref "IC46") (pin "18") (pinfunction "18_18") (pintype "passive"))
      (node (ref "IC47") (pin "18") (pinfunction "18_18") (pintype "passive"))
      (node (ref "IC48") (pin "18") (pinfunction "18_18") (pintype "passive"))
    )
    (net (code "481") (name "Net-(IC45-Pad19)") (class "Default")
      (node (ref "IC45") (pin "19") (pinfunction "19_19") (pintype "passive"))
      (node (ref "IC46") (pin "19") (pinfunction "19_19") (pintype "passive"))
      (node (ref "IC47") (pin "19") (pinfunction "19_19") (pintype "passive"))
      (node (ref "IC48") (pin "19") (pinfunction "19_19") (pintype "passive"))
    )
    (net (code "482") (name "Net-(IC45-Pad20)") (class "Default")
      (node (ref "IC45") (pin "20") (pinfunction "20_20") (pintype "passive"))
      (node (ref "IC46") (pin "20") (pinfunction "20_20") (pintype "passive"))
      (node (ref "IC47") (pin "20") (pinfunction "20_20") (pintype "passive"))
      (node (ref "IC48") (pin "20") (pinfunction "20_20") (pintype "passive"))
    )
    (net (code "483") (name "Net-(IC45-Pad21)") (class "Default")
      (node (ref "IC45") (pin "21") (pinfunction "21_21") (pintype "passive"))
      (node (ref "IC46") (pin "21") (pinfunction "21_21") (pintype "passive"))
      (node (ref "IC47") (pin "21") (pinfunction "21_21") (pintype "passive"))
      (node (ref "IC48") (pin "21") (pinfunction "21_21") (pintype "passive"))
    )
    (net (code "484") (name "Net-(IC45-Pad22)") (class "Default")
      (node (ref "IC45") (pin "22") (pinfunction "22_22") (pintype "passive"))
      (node (ref "IC46") (pin "22") (pinfunction "22_22") (pintype "passive"))
      (node (ref "IC47") (pin "22") (pinfunction "22_22") (pintype "passive"))
      (node (ref "IC48") (pin "22") (pinfunction "22_22") (pintype "passive"))
    )
    (net (code "485") (name "Net-(IC45-Pad23)") (class "Default")
      (node (ref "IC45") (pin "23") (pinfunction "23_23") (pintype "passive"))
      (node (ref "IC46") (pin "23") (pinfunction "23_23") (pintype "passive"))
      (node (ref "IC47") (pin "23") (pinfunction "23_23") (pintype "passive"))
      (node (ref "IC48") (pin "23") (pinfunction "23_23") (pintype "passive"))
    )
    (net (code "486") (name "Net-(IC45-Pad24)") (class "Default")
      (node (ref "IC45") (pin "24") (pinfunction "24_24") (pintype "passive"))
      (node (ref "IC46") (pin "24") (pinfunction "24_24") (pintype "passive"))
      (node (ref "IC47") (pin "24") (pinfunction "24_24") (pintype "passive"))
      (node (ref "IC48") (pin "24") (pinfunction "24_24") (pintype "passive"))
    )
    (net (code "487") (name "Net-(IC45-Pad25)") (class "Default")
      (node (ref "IC45") (pin "25") (pinfunction "25_25") (pintype "passive"))
      (node (ref "IC46") (pin "25") (pinfunction "25_25") (pintype "passive"))
      (node (ref "IC47") (pin "25") (pinfunction "25_25") (pintype "passive"))
      (node (ref "IC48") (pin "25") (pinfunction "25_25") (pintype "passive"))
    )
    (net (code "488") (name "Net-(IC45-Pad26)") (class "Default")
      (node (ref "IC45") (pin "26") (pinfunction "26_26") (pintype "passive"))
      (node (ref "IC46") (pin "26") (pinfunction "26_26") (pintype "passive"))
      (node (ref "IC47") (pin "26") (pinfunction "26_26") (pintype "passive"))
      (node (ref "IC48") (pin "26") (pinfunction "26_26") (pintype "passive"))
    )
    (net (code "489") (name "Net-(IC45-Pad27)") (class "Default")
      (node (ref "IC45") (pin "27") (pinfunction "27_27") (pintype "passive"))
      (node (ref "IC46") (pin "27") (pinfunction "27_27") (pintype "passive"))
      (node (ref "IC47") (pin "27") (pinfunction "27_27") (pintype "passive"))
      (node (ref "IC48") (pin "27") (pinfunction "27_27") (pintype "passive"))
    )
    (net (code "490") (name "Net-(IC45-Pad28)") (class "Default")
      (node (ref "IC45") (pin "28") (pinfunction "28_28") (pintype "passive"))
      (node (ref "IC46") (pin "28") (pinfunction "28_28") (pintype "passive"))
      (node (ref "IC47") (pin "28") (pinfunction "28_28") (pintype "passive"))
      (node (ref "IC48") (pin "28") (pinfunction "28_28") (pintype "passive"))
    )
    (net (code "491") (name "Net-(IC45-Pad29)") (class "Default")
      (node (ref "IC45") (pin "29") (pinfunction "29_29") (pintype "passive"))
      (node (ref "IC46") (pin "29") (pinfunction "29_29") (pintype "passive"))
      (node (ref "IC47") (pin "29") (pinfunction "29_29") (pintype "passive"))
      (node (ref "IC48") (pin "29") (pinfunction "29_29") (pintype "passive"))
    )
    (net (code "492") (name "Net-(IC45-Pad30)") (class "Default")
      (node (ref "IC45") (pin "30") (pinfunction "30_30") (pintype "passive"))
      (node (ref "IC46") (pin "30") (pinfunction "30_30") (pintype "passive"))
      (node (ref "IC47") (pin "30") (pinfunction "30_30") (pintype "passive"))
      (node (ref "IC48") (pin "30") (pinfunction "30_30") (pintype "passive"))
    )
    (net (code "493") (name "Net-(IC45-Pad31)") (class "Default")
      (node (ref "IC45") (pin "31") (pinfunction "31_31") (pintype "passive"))
      (node (ref "IC46") (pin "31") (pinfunction "31_31") (pintype "passive"))
      (node (ref "IC47") (pin "31") (pinfunction "31_31") (pintype "passive"))
      (node (ref "IC48") (pin "31") (pinfunction "31_31") (pintype "passive"))
    )
    (net (code "494") (name "Net-(IC45-Pad32)") (class "Default")
      (node (ref "IC45") (pin "32") (pinfunction "32_32") (pintype "passive"))
      (node (ref "IC46") (pin "32") (pinfunction "32_32") (pintype "passive"))
      (node (ref "IC47") (pin "32") (pinfunction "32_32") (pintype "passive"))
      (node (ref "IC48") (pin "32") (pinfunction "32_32") (pintype "passive"))
    )
    (net (code "495") (name "Net-(IC45-Pad33)") (class "Default")
      (node (ref "IC45") (pin "33") (pinfunction "33_33") (pintype "passive"))
      (node (ref "IC46") (pin "33") (pinfunction "33_33") (pintype "passive"))
      (node (ref "IC47") (pin "33") (pinfunction "33_33") (pintype "passive"))
      (node (ref "IC48") (pin "33") (pinfunction "33_33") (pintype "passive"))
    )
    (net (code "496") (name "Net-(IC45-Pad34)") (class "Default")
      (node (ref "IC45") (pin "34") (pinfunction "34_34") (pintype "passive"))
      (node (ref "IC46") (pin "34") (pinfunction "34_34") (pintype "passive"))
      (node (ref "IC47") (pin "34") (pinfunction "34_34") (pintype "passive"))
      (node (ref "IC48") (pin "34") (pinfunction "34_34") (pintype "passive"))
    )
    (net (code "497") (name "Net-(IC45-Pad35)") (class "Default")
      (node (ref "IC45") (pin "35") (pinfunction "35_35") (pintype "passive"))
      (node (ref "IC46") (pin "35") (pinfunction "35_35") (pintype "passive"))
      (node (ref "IC47") (pin "35") (pinfunction "35_35") (pintype "passive"))
      (node (ref "IC48") (pin "35") (pinfunction "35_35") (pintype "passive"))
    )
    (net (code "498") (name "Net-(IC45-Pad36)") (class "Default")
      (node (ref "IC45") (pin "36") (pinfunction "36_36") (pintype "passive"))
      (node (ref "IC46") (pin "36") (pinfunction "36_36") (pintype "passive"))
      (node (ref "IC47") (pin "36") (pinfunction "36_36") (pintype "passive"))
      (node (ref "IC48") (pin "36") (pinfunction "36_36") (pintype "passive"))
    )
    (net (code "499") (name "Net-(IC45-Pad37)") (class "Default")
      (node (ref "IC45") (pin "37") (pinfunction "37_37") (pintype "passive"))
      (node (ref "IC46") (pin "37") (pinfunction "37_37") (pintype "passive"))
      (node (ref "IC47") (pin "37") (pinfunction "37_37") (pintype "passive"))
      (node (ref "IC48") (pin "37") (pinfunction "37_37") (pintype "passive"))
    )
    (net (code "500") (name "Net-(IC45-Pad38)") (class "Default")
      (node (ref "IC45") (pin "38") (pinfunction "38_38") (pintype "passive"))
      (node (ref "IC46") (pin "38") (pinfunction "38_38") (pintype "passive"))
      (node (ref "IC47") (pin "38") (pinfunction "38_38") (pintype "passive"))
      (node (ref "IC48") (pin "38") (pinfunction "38_38") (pintype "passive"))
    )
    (net (code "501") (name "Net-(IC45-Pad39)") (class "Default")
      (node (ref "IC45") (pin "39") (pinfunction "39_39") (pintype "passive"))
      (node (ref "IC46") (pin "39") (pinfunction "39_39") (pintype "passive"))
      (node (ref "IC47") (pin "39") (pinfunction "39_39") (pintype "passive"))
      (node (ref "IC48") (pin "39") (pinfunction "39_39") (pintype "passive"))
    )
    (net (code "502") (name "Net-(IC45-Pad40)") (class "Default")
      (node (ref "IC45") (pin "40") (pinfunction "40_40") (pintype "passive"))
      (node (ref "IC46") (pin "40") (pinfunction "40_40") (pintype "passive"))
      (node (ref "IC47") (pin "40") (pinfunction "40_40") (pintype "passive"))
      (node (ref "IC48") (pin "40") (pinfunction "40_40") (pintype "passive"))
    )
    (net (code "503") (name "Net-(IC45-Pad41)") (class "Default")
      (node (ref "IC45") (pin "41") (pinfunction "41_41") (pintype "passive"))
      (node (ref "IC46") (pin "41") (pinfunction "41_41") (pintype "passive"))
      (node (ref "IC47") (pin "41") (pinfunction "41_41") (pintype "passive"))
      (node (ref "IC48") (pin "41") (pinfunction "41_41") (pintype "passive"))
    )
    (net (code "504") (name "Net-(IC45-Pad42)") (class "Default")
      (node (ref "IC45") (pin "42") (pinfunction "42_42") (pintype "passive"))
      (node (ref "IC46") (pin "42") (pinfunction "42_42") (pintype "passive"))
      (node (ref "IC47") (pin "42") (pinfunction "42_42") (pintype "passive"))
      (node (ref "IC48") (pin "42") (pinfunction "42_42") (pintype "passive"))
    )
    (net (code "505") (name "Net-(IC49-Pad1)") (class "Default")
      (node (ref "IC49") (pin "1") (pinfunction "1_1") (pintype "passive"))
      (node (ref "IC50") (pin "1") (pinfunction "1_1") (pintype "passive"))
      (node (ref "IC51") (pin "1") (pinfunction "1_1") (pintype "passive"))
      (node (ref "IC52") (pin "1") (pinfunction "1_1") (pintype "passive"))
    )
    (net (code "506") (name "Net-(IC49-Pad2)") (class "Default")
      (node (ref "IC49") (pin "2") (pinfunction "2_2") (pintype "passive"))
      (node (ref "IC50") (pin "2") (pinfunction "2_2") (pintype "passive"))
      (node (ref "IC51") (pin "2") (pinfunction "2_2") (pintype "passive"))
      (node (ref "IC52") (pin "2") (pinfunction "2_2") (pintype "passive"))
    )
    (net (code "507") (name "Net-(IC49-Pad3)") (class "Default")
      (node (ref "IC49") (pin "3") (pinfunction "3_3") (pintype "passive"))
      (node (ref "IC50") (pin "3") (pinfunction "3_3") (pintype "passive"))
      (node (ref "IC51") (pin "3") (pinfunction "3_3") (pintype "passive"))
      (node (ref "IC52") (pin "3") (pinfunction "3_3") (pintype "passive"))
    )
    (net (code "508") (name "Net-(IC49-Pad4)") (class "Default")
      (node (ref "IC49") (pin "4") (pinfunction "4_4") (pintype "passive"))
      (node (ref "IC50") (pin "4") (pinfunction "4_4") (pintype "passive"))
      (node (ref "IC51") (pin "4") (pinfunction "4_4") (pintype "passive"))
      (node (ref "IC52") (pin "4") (pinfunction "4_4") (pintype "passive"))
    )
    (net (code "509") (name "Net-(IC49-Pad5)") (class "Default")
      (node (ref "IC49") (pin "5") (pinfunction "5_5") (pintype "passive"))
      (node (ref "IC50") (pin "5") (pinfunction "5_5") (pintype "passive"))
      (node (ref "IC51") (pin "5") (pinfunction "5_5") (pintype "passive"))
      (node (ref "IC52") (pin "5") (pinfunction "5_5") (pintype "passive"))
    )
    (net (code "510") (name "Net-(IC49-Pad6)") (class "Default")
      (node (ref "IC49") (pin "6") (pinfunction "6_6") (pintype "passive"))
      (node (ref "IC50") (pin "6") (pinfunction "6_6") (pintype "passive"))
      (node (ref "IC51") (pin "6") (pinfunction "6_6") (pintype "passive"))
      (node (ref "IC52") (pin "6") (pinfunction "6_6") (pintype "passive"))
    )
    (net (code "511") (name "Net-(IC49-Pad7)") (class "Default")
      (node (ref "IC49") (pin "7") (pinfunction "7_7") (pintype "passive"))
      (node (ref "IC50") (pin "7") (pinfunction "7_7") (pintype "passive"))
      (node (ref "IC51") (pin "7") (pinfunction "7_7") (pintype "passive"))
      (node (ref "IC52") (pin "7") (pinfunction "7_7") (pintype "passive"))
    )
    (net (code "512") (name "Net-(IC49-Pad8)") (class "Default")
      (node (ref "IC49") (pin "8") (pinfunction "8_8") (pintype "passive"))
      (node (ref "IC50") (pin "8") (pinfunction "8_8") (pintype "passive"))
      (node (ref "IC51") (pin "8") (pinfunction "8_8") (pintype "passive"))
      (node (ref "IC52") (pin "8") (pinfunction "8_8") (pintype "passive"))
    )
    (net (code "513") (name "Net-(IC49-Pad9)") (class "Default")
      (node (ref "IC49") (pin "9") (pinfunction "9_9") (pintype "passive"))
      (node (ref "IC50") (pin "9") (pinfunction "9_9") (pintype "passive"))
      (node (ref "IC51") (pin "9") (pinfunction "9_9") (pintype "passive"))
      (node (ref "IC52") (pin "9") (pinfunction "9_9") (pintype "passive"))
    )
    (net (code "514") (name "Net-(IC49-Pad10)") (class "Default")
      (node (ref "IC49") (pin "10") (pinfunction "10_10") (pintype "passive"))
      (node (ref "IC50") (pin "10") (pinfunction "10_10") (pintype "passive"))
      (node (ref "IC51") (pin "10") (pinfunction "10_10") (pintype "passive"))
      (node (ref "IC52") (pin "10") (pinfunction "10_10") (pintype "passive"))
    )
    (net (code "515") (name "Net-(IC49-Pad11)") (class "Default")
      (node (ref "IC49") (pin "11") (pinfunction "11_11") (pintype "passive"))
      (node (ref "IC50") (pin "11") (pinfunction "11_11") (pintype "passive"))
      (node (ref "IC51") (pin "11") (pinfunction "11_11") (pintype "passive"))
      (node (ref "IC52") (pin "11") (pinfunction "11_11") (pintype "passive"))
    )
    (net (code "516") (name "Net-(IC49-Pad12)") (class "Default")
      (node (ref "IC49") (pin "12") (pinfunction "12_12") (pintype "passive"))
      (node (ref "IC50") (pin "12") (pinfunction "12_12") (pintype "passive"))
      (node (ref "IC51") (pin "12") (pinfunction "12_12") (pintype "passive"))
      (node (ref "IC52") (pin "12") (pinfunction "12_12") (pintype "passive"))
    )
    (net (code "517") (name "Net-(IC49-Pad13)") (class "Default")
      (node (ref "IC49") (pin "13") (pinfunction "13_13") (pintype "passive"))
      (node (ref "IC50") (pin "13") (pinfunction "13_13") (pintype "passive"))
      (node (ref "IC51") (pin "13") (pinfunction "13_13") (pintype "passive"))
      (node (ref "IC52") (pin "13") (pinfunction "13_13") (pintype "passive"))
    )
    (net (code "518") (name "Net-(IC49-Pad14)") (class "Default")
      (node (ref "IC49") (pin "14") (pinfunction "14_14") (pintype "passive"))
      (node (ref "IC50") (pin "14") (pinfunction "14_14") (pintype "passive"))
      (node (ref "IC51") (pin "14") (pinfunction "14_14") (pintype "passive"))
      (node (ref "IC52") (pin "14") (pinfunction "14_14") (pintype "passive"))
    )
    (net (code "519") (name "Net-(IC49-Pad15)") (class "Default")
      (node (ref "IC49") (pin "15") (pinfunction "15_15") (pintype "passive"))
      (node (ref "IC50") (pin "15") (pinfunction "15_15") (pintype "passive"))
      (node (ref "IC51") (pin "15") (pinfunction "15_15") (pintype "passive"))
      (node (ref "IC52") (pin "15") (pinfunction "15_15") (pintype "passive"))
    )
    (net (code "520") (name "Net-(IC49-Pad16)") (class "Default")
      (node (ref "IC49") (pin "16") (pinfunction "16_16") (pintype "passive"))
      (node (ref "IC50") (pin "16") (pinfunction "16_16") (pintype "passive"))
      (node (ref "IC51") (pin "16") (pinfunction "16_16") (pintype "passive"))
      (node (ref "IC52") (pin "16") (pinfunction "16_16") (pintype "passive"))
    )
    (net (code "521") (name "Net-(IC49-Pad17)") (class "Default")
      (node (ref "IC49") (pin "17") (pinfunction "17_17") (pintype "passive"))
      (node (ref "IC50") (pin "17") (pinfunction "17_17") (pintype "passive"))
      (node (ref "IC51") (pin "17") (pinfunction "17_17") (pintype "passive"))
      (node (ref "IC52") (pin "17") (pinfunction "17_17") (pintype "passive"))
    )
    (net (code "522") (name "Net-(IC49-Pad18)") (class "Default")
      (node (ref "IC49") (pin "18") (pinfunction "18_18") (pintype "passive"))
      (node (ref "IC50") (pin "18") (pinfunction "18_18") (pintype "passive"))
      (node (ref "IC51") (pin "18") (pinfunction "18_18") (pintype "passive"))
      (node (ref "IC52") (pin "18") (pinfunction "18_18") (pintype "passive"))
    )
    (net (code "523") (name "Net-(IC49-Pad19)") (class "Default")
      (node (ref "IC49") (pin "19") (pinfunction "19_19") (pintype "passive"))
      (node (ref "IC50") (pin "19") (pinfunction "19_19") (pintype "passive"))
      (node (ref "IC51") (pin "19") (pinfunction "19_19") (pintype "passive"))
      (node (ref "IC52") (pin "19") (pinfunction "19_19") (pintype "passive"))
    )
    (net (code "524") (name "Net-(IC49-Pad20)") (class "Default")
      (node (ref "IC49") (pin "20") (pinfunction "20_20") (pintype "passive"))
      (node (ref "IC50") (pin "20") (pinfunction "20_20") (pintype "passive"))
      (node (ref "IC51") (pin "20") (pinfunction "20_20") (pintype "passive"))
      (node (ref "IC52") (pin "20") (pinfunction "20_20") (pintype "passive"))
    )
    (net (code "525") (name "Net-(IC49-Pad21)") (class "Default")
      (node (ref "IC49") (pin "21") (pinfunction "21_21") (pintype "passive"))
      (node (ref "IC50") (pin "21") (pinfunction "21_21") (pintype "passive"))
      (node (ref "IC51") (pin "21") (pinfunction "21_21") (pintype "passive"))
      (node (ref "IC52") (pin "21") (pinfunction "21_21") (pintype "passive"))
    )
    (net (code "526") (name "Net-(IC49-Pad22)") (class "Default")
      (node (ref "IC49") (pin "22") (pinfunction "22_22") (pintype "passive"))
      (node (ref "IC50") (pin "22") (pinfunction "22_22") (pintype "passive"))
      (node (ref "IC51") (pin "22") (pinfunction "22_22") (pintype "passive"))
      (node (ref "IC52") (pin "22") (pinfunction "22_22") (pintype "passive"))
    )
    (net (code "527") (name "Net-(IC49-Pad23)") (class "Default")
      (node (ref "IC49") (pin "23") (pinfunction "23_23") (pintype "passive"))
      (node (ref "IC50") (pin "23") (pinfunction "23_23") (pintype "passive"))
      (node (ref "IC51") (pin "23") (pinfunction "23_23") (pintype "passive"))
      (node (ref "IC52") (pin "23") (pinfunction "23_23") (pintype "passive"))
    )
    (net (code "528") (name "Net-(IC49-Pad24)") (class "Default")
      (node (ref "IC49") (pin "24") (pinfunction "24_24") (pintype "passive"))
      (node (ref "IC50") (pin "24") (pinfunction "24_24") (pintype "passive"))
      (node (ref "IC51") (pin "24") (pinfunction "24_24") (pintype "passive"))
      (node (ref "IC52") (pin "24") (pinfunction "24_24") (pintype "passive"))
    )
    (net (code "529") (name "Net-(IC49-Pad25)") (class "Default")
      (node (ref "IC49") (pin "25") (pinfunction "25_25") (pintype "passive"))
      (node (ref "IC50") (pin "25") (pinfunction "25_25") (pintype "passive"))
      (node (ref "IC51") (pin "25") (pinfunction "25_25") (pintype "passive"))
      (node (ref "IC52") (pin "25") (pinfunction "25_25") (pintype "passive"))
    )
    (net (code "530") (name "Net-(IC49-Pad26)") (class "Default")
      (node (ref "IC49") (pin "26") (pinfunction "26_26") (pintype "passive"))
      (node (ref "IC50") (pin "26") (pinfunction "26_26") (pintype "passive"))
      (node (ref "IC51") (pin "26") (pinfunction "26_26") (pintype "passive"))
      (node (ref "IC52") (pin "26") (pinfunction "26_26") (pintype "passive"))
    )
    (net (code "531") (name "Net-(IC49-Pad27)") (class "Default")
      (node (ref "IC49") (pin "27") (pinfunction "27_27") (pintype "passive"))
      (node (ref "IC50") (pin "27") (pinfunction "27_27") (pintype "passive"))
      (node (ref "IC51") (pin "27") (pinfunction "27_27") (pintype "passive"))
      (node (ref "IC52") (pin "27") (pinfunction "27_27") (pintype "passive"))
    )
    (net (code "532") (name "Net-(IC49-Pad28)") (class "Default")
      (node (ref "IC49") (pin "28") (pinfunction "28_28") (pintype "passive"))
      (node (ref "IC50") (pin "28") (pinfunction "28_28") (pintype "passive"))
      (node (ref "IC51") (pin "28") (pinfunction "28_28") (pintype "passive"))
      (node (ref "IC52") (pin "28") (pinfunction "28_28") (pintype "passive"))
    )
    (net (code "533") (name "Net-(IC49-Pad29)") (class "Default")
      (node (ref "IC49") (pin "29") (pinfunction "29_29") (pintype "passive"))
      (node (ref "IC50") (pin "29") (pinfunction "29_29") (pintype "passive"))
      (node (ref "IC51") (pin "29") (pinfunction "29_29") (pintype "passive"))
      (node (ref "IC52") (pin "29") (pinfunction "29_29") (pintype "passive"))
    )
    (net (code "534") (name "Net-(IC49-Pad30)") (class "Default")
      (node (ref "IC49") (pin "30") (pinfunction "30_30") (pintype "passive"))
      (node (ref "IC50") (pin "30") (pinfunction "30_30") (pintype "passive"))
      (node (ref "IC51") (pin "30") (pinfunction "30_30") (pintype "passive"))
      (node (ref "IC52") (pin "30") (pinfunction "30_30") (pintype "passive"))
    )
    (net (code "535") (name "Net-(IC49-Pad31)") (class "Default")
      (node (ref "IC49") (pin "31") (pinfunction "31_31") (pintype "passive"))
      (node (ref "IC50") (pin "31") (pinfunction "31_31") (pintype "passive"))
      (node (ref "IC51") (pin "31") (pinfunction "31_31") (pintype "passive"))
      (node (ref "IC52") (pin "31") (pinfunction "31_31") (pintype "passive"))
    )
    (net (code "536") (name "Net-(IC49-Pad32)") (class "Default")
      (node (ref "IC49") (pin "32") (pinfunction "32_32") (pintype "passive"))
      (node (ref "IC50") (pin "32") (pinfunction "32_32") (pintype "passive"))
      (node (ref "IC51") (pin "32") (pinfunction "32_32") (pintype "passive"))
      (node (ref "IC52") (pin "32") (pinfunction "32_32") (pintype "passive"))
    )
    (net (code "537") (name "Net-(IC49-Pad33)") (class "Default")
      (node (ref "IC49") (pin "33") (pinfunction "33_33") (pintype "passive"))
      (node (ref "IC50") (pin "33") (pinfunction "33_33") (pintype "passive"))
      (node (ref "IC51") (pin "33") (pinfunction "33_33") (pintype "passive"))
      (node (ref "IC52") (pin "33") (pinfunction "33_33") (pintype "passive"))
    )
    (net (code "538") (name "Net-(IC49-Pad34)") (class "Default")
      (node (ref "IC49") (pin "34") (pinfunction "34_34") (pintype "passive"))
      (node (ref "IC50") (pin "34") (pinfunction "34_34") (pintype "passive"))
      (node (ref "IC51") (pin "34") (pinfunction "34_34") (pintype "passive"))
      (node (ref "IC52") (pin "34") (pinfunction "34_34") (pintype "passive"))
    )
    (net (code "539") (name "Net-(IC49-Pad35)") (class "Default")
      (node (ref "IC49") (pin "35") (pinfunction "35_35") (pintype "passive"))
      (node (ref "IC50") (pin "35") (pinfunction "35_35") (pintype "passive"))
      (node (ref "IC51") (pin "35") (pinfunction "35_35") (pintype "passive"))
      (node (ref "IC52") (pin "35") (pinfunction "35_35") (pintype "passive"))
    )
    (net (code "540") (name "Net-(IC49-Pad36)") (class "Default")
      (node (ref "IC49") (pin "36") (pinfunction "36_36") (pintype "passive"))
      (node (ref "IC50") (pin "36") (pinfunction "36_36") (pintype "passive"))
      (node (ref "IC51") (pin "36") (pinfunction "36_36") (pintype "passive"))
      (node (ref "IC52") (pin "36") (pinfunction "36_36") (pintype "passive"))
    )
    (net (code "541") (name "Net-(IC49-Pad37)") (class "Default")
      (node (ref "IC49") (pin "37") (pinfunction "37_37") (pintype "passive"))
      (node (ref "IC50") (pin "37") (pinfunction "37_37") (pintype "passive"))
      (node (ref "IC51") (pin "37") (pinfunction "37_37") (pintype "passive"))
      (node (ref "IC52") (pin "37") (pinfunction "37_37") (pintype "passive"))
    )
    (net (code "542") (name "Net-(IC49-Pad38)") (class "Default")
      (node (ref "IC49") (pin "38") (pinfunction "38_38") (pintype "passive"))
      (node (ref "IC50") (pin "38") (pinfunction "38_38") (pintype "passive"))
      (node (ref "IC51") (pin "38") (pinfunction "38_38") (pintype "passive"))
      (node (ref "IC52") (pin "38") (pinfunction "38_38") (pintype "passive"))
    )
    (net (code "543") (name "Net-(IC49-Pad39)") (class "Default")
      (node (ref "IC49") (pin "39") (pinfunction "39_39") (pintype "passive"))
      (node (ref "IC50") (pin "39") (pinfunction "39_39") (pintype "passive"))
      (node (ref "IC51") (pin "39") (pinfunction "39_39") (pintype "passive"))
      (node (ref "IC52") (pin "39") (pinfunction "39_39") (pintype "passive"))
    )
    (net (code "544") (name "Net-(IC49-Pad40)") (class "Default")
      (node (ref "IC49") (pin "40") (pinfunction "40_40") (pintype "passive"))
      (node (ref "IC50") (pin "40") (pinfunction "40_40") (pintype "passive"))
      (node (ref "IC51") (pin "40") (pinfunction "40_40") (pintype "passive"))
      (node (ref "IC52") (pin "40") (pinfunction "40_40") (pintype "passive"))
    )
    (net (code "545") (name "Net-(IC49-Pad41)") (class "Default")
      (node (ref "IC49") (pin "41") (pinfunction "41_41") (pintype "passive"))
      (node (ref "IC50") (pin "41") (pinfunction "41_41") (pintype "passive"))
      (node (ref "IC51") (pin "41") (pinfunction "41_41") (pintype "passive"))
      (node (ref "IC52") (pin "41") (pinfunction "41_41") (pintype "passive"))
    )
    (net (code "546") (name "Net-(IC49-Pad42)") (class "Default")
      (node (ref "IC49") (pin "42") (pinfunction "42_42") (pintype "passive"))
      (node (ref "IC50") (pin "42") (pinfunction "42_42") (pintype "passive"))
      (node (ref "IC51") (pin "42") (pinfunction "42_42") (pintype "passive"))
      (node (ref "IC52") (pin "42") (pinfunction "42_42") (pintype "passive"))
    )
    (net (code "547") (name "Net-(IC53-Pad1)") (class "Default")
      (node (ref "IC53") (pin "1") (pinfunction "1_1") (pintype "passive"))
      (node (ref "IC54") (pin "1") (pinfunction "1_1") (pintype "passive"))
      (node (ref "IC55") (pin "1") (pinfunction "1_1") (pintype "passive"))
      (node (ref "IC56") (pin "1") (pinfunction "1_1") (pintype "passive"))
    )
    (net (code "548") (name "Net-(IC53-Pad2)") (class "Default")
      (node (ref "IC53") (pin "2") (pinfunction "2_2") (pintype "passive"))
      (node (ref "IC54") (pin "2") (pinfunction "2_2") (pintype "passive"))
      (node (ref "IC55") (pin "2") (pinfunction "2_2") (pintype "passive"))
      (node (ref "IC56") (pin "2") (pinfunction "2_2") (pintype "passive"))
    )
    (net (code "549") (name "Net-(IC53-Pad3)") (class "Default")
      (node (ref "IC53") (pin "3") (pinfunction "3_3") (pintype "passive"))
      (node (ref "IC54") (pin "3") (pinfunction "3_3") (pintype "passive"))
      (node (ref "IC55") (pin "3") (pinfunction "3_3") (pintype "passive"))
      (node (ref "IC56") (pin "3") (pinfunction "3_3") (pintype "passive"))
    )
    (net (code "550") (name "Net-(IC53-Pad4)") (class "Default")
      (node (ref "IC53") (pin "4") (pinfunction "4_4") (pintype "passive"))
      (node (ref "IC54") (pin "4") (pinfunction "4_4") (pintype "passive"))
      (node (ref "IC55") (pin "4") (pinfunction "4_4") (pintype "passive"))
      (node (ref "IC56") (pin "4") (pinfunction "4_4") (pintype "passive"))
    )
    (net (code "551") (name "Net-(IC53-Pad5)") (class "Default")
      (node (ref "IC53") (pin "5") (pinfunction "5_5") (pintype "passive"))
      (node (ref "IC54") (pin "5") (pinfunction "5_5") (pintype "passive"))
      (node (ref "IC55") (pin "5") (pinfunction "5_5") (pintype "passive"))
      (node (ref "IC56") (pin "5") (pinfunction "5_5") (pintype "passive"))
    )
    (net (code "552") (name "Net-(IC53-Pad6)") (class "Default")
      (node (ref "IC53") (pin "6") (pinfunction "6_6") (pintype "passive"))
      (node (ref "IC54") (pin "6") (pinfunction "6_6") (pintype "passive"))
      (node (ref "IC55") (pin "6") (pinfunction "6_6") (pintype "passive"))
      (node (ref "IC56") (pin "6") (pinfunction "6_6") (pintype "passive"))
    )
    (net (code "553") (name "Net-(IC53-Pad7)") (class "Default")
      (node (ref "IC53") (pin "7") (pinfunction "7_7") (pintype "passive"))
      (node (ref "IC54") (pin "7") (pinfunction "7_7") (pintype "passive"))
      (node (ref "IC55") (pin "7") (pinfunction "7_7") (pintype "passive"))
      (node (ref "IC56") (pin "7") (pinfunction "7_7") (pintype "passive"))
    )
    (net (code "554") (name "Net-(IC53-Pad8)") (class "Default")
      (node (ref "IC53") (pin "8") (pinfunction "8_8") (pintype "passive"))
      (node (ref "IC54") (pin "8") (pinfunction "8_8") (pintype "passive"))
      (node (ref "IC55") (pin "8") (pinfunction "8_8") (pintype "passive"))
      (node (ref "IC56") (pin "8") (pinfunction "8_8") (pintype "passive"))
    )
    (net (code "555") (name "Net-(IC53-Pad9)") (class "Default")
      (node (ref "IC53") (pin "9") (pinfunction "9_9") (pintype "passive"))
      (node (ref "IC54") (pin "9") (pinfunction "9_9") (pintype "passive"))
      (node (ref "IC55") (pin "9") (pinfunction "9_9") (pintype "passive"))
      (node (ref "IC56") (pin "9") (pinfunction "9_9") (pintype "passive"))
    )
    (net (code "556") (name "Net-(IC53-Pad10)") (class "Default")
      (node (ref "IC53") (pin "10") (pinfunction "10_10") (pintype "passive"))
      (node (ref "IC54") (pin "10") (pinfunction "10_10") (pintype "passive"))
      (node (ref "IC55") (pin "10") (pinfunction "10_10") (pintype "passive"))
      (node (ref "IC56") (pin "10") (pinfunction "10_10") (pintype "passive"))
    )
    (net (code "557") (name "Net-(IC53-Pad11)") (class "Default")
      (node (ref "IC53") (pin "11") (pinfunction "11_11") (pintype "passive"))
      (node (ref "IC54") (pin "11") (pinfunction "11_11") (pintype "passive"))
      (node (ref "IC55") (pin "11") (pinfunction "11_11") (pintype "passive"))
      (node (ref "IC56") (pin "11") (pinfunction "11_11") (pintype "passive"))
    )
    (net (code "558") (name "Net-(IC53-Pad12)") (class "Default")
      (node (ref "IC53") (pin "12") (pinfunction "12_12") (pintype "passive"))
      (node (ref "IC54") (pin "12") (pinfunction "12_12") (pintype "passive"))
      (node (ref "IC55") (pin "12") (pinfunction "12_12") (pintype "passive"))
      (node (ref "IC56") (pin "12") (pinfunction "12_12") (pintype "passive"))
    )
    (net (code "559") (name "Net-(IC53-Pad13)") (class "Default")
      (node (ref "IC53") (pin "13") (pinfunction "13_13") (pintype "passive"))
      (node (ref "IC54") (pin "13") (pinfunction "13_13") (pintype "passive"))
      (node (ref "IC55") (pin "13") (pinfunction "13_13") (pintype "passive"))
      (node (ref "IC56") (pin "13") (pinfunction "13_13") (pintype "passive"))
    )
    (net (code "560") (name "Net-(IC53-Pad14)") (class "Default")
      (node (ref "IC53") (pin "14") (pinfunction "14_14") (pintype "passive"))
      (node (ref "IC54") (pin "14") (pinfunction "14_14") (pintype "passive"))
      (node (ref "IC55") (pin "14") (pinfunction "14_14") (pintype "passive"))
      (node (ref "IC56") (pin "14") (pinfunction "14_14") (pintype "passive"))
    )
    (net (code "561") (name "Net-(IC53-Pad15)") (class "Default")
      (node (ref "IC53") (pin "15") (pinfunction "15_15") (pintype "passive"))
      (node (ref "IC54") (pin "15") (pinfunction "15_15") (pintype "passive"))
      (node (ref "IC55") (pin "15") (pinfunction "15_15") (pintype "passive"))
      (node (ref "IC56") (pin "15") (pinfunction "15_15") (pintype "passive"))
    )
    (net (code "562") (name "Net-(IC53-Pad16)") (class "Default")
      (node (ref "IC53") (pin "16") (pinfunction "16_16") (pintype "passive"))
      (node (ref "IC54") (pin "16") (pinfunction "16_16") (pintype "passive"))
      (node (ref "IC55") (pin "16") (pinfunction "16_16") (pintype "passive"))
      (node (ref "IC56") (pin "16") (pinfunction "16_16") (pintype "passive"))
    )
    (net (code "563") (name "Net-(IC53-Pad17)") (class "Default")
      (node (ref "IC53") (pin "17") (pinfunction "17_17") (pintype "passive"))
      (node (ref "IC54") (pin "17") (pinfunction "17_17") (pintype "passive"))
      (node (ref "IC55") (pin "17") (pinfunction "17_17") (pintype "passive"))
      (node (ref "IC56") (pin "17") (pinfunction "17_17") (pintype "passive"))
    )
    (net (code "564") (name "Net-(IC53-Pad18)") (class "Default")
      (node (ref "IC53") (pin "18") (pinfunction "18_18") (pintype "passive"))
      (node (ref "IC54") (pin "18") (pinfunction "18_18") (pintype "passive"))
      (node (ref "IC55") (pin "18") (pinfunction "18_18") (pintype "passive"))
      (node (ref "IC56") (pin "18") (pinfunction "18_18") (pintype "passive"))
    )
    (net (code "565") (name "Net-(IC53-Pad19)") (class "Default")
      (node (ref "IC53") (pin "19") (pinfunction "19_19") (pintype "passive"))
      (node (ref "IC54") (pin "19") (pinfunction "19_19") (pintype "passive"))
      (node (ref "IC55") (pin "19") (pinfunction "19_19") (pintype "passive"))
      (node (ref "IC56") (pin "19") (pinfunction "19_19") (pintype "passive"))
    )
    (net (code "566") (name "Net-(IC53-Pad20)") (class "Default")
      (node (ref "IC53") (pin "20") (pinfunction "20_20") (pintype "passive"))
      (node (ref "IC54") (pin "20") (pinfunction "20_20") (pintype "passive"))
      (node (ref "IC55") (pin "20") (pinfunction "20_20") (pintype "passive"))
      (node (ref "IC56") (pin "20") (pinfunction "20_20") (pintype "passive"))
    )
    (net (code "567") (name "Net-(IC53-Pad21)") (class "Default")
      (node (ref "IC53") (pin "21") (pinfunction "21_21") (pintype "passive"))
      (node (ref "IC54") (pin "21") (pinfunction "21_21") (pintype "passive"))
      (node (ref "IC55") (pin "21") (pinfunction "21_21") (pintype "passive"))
      (node (ref "IC56") (pin "21") (pinfunction "21_21") (pintype "passive"))
    )
    (net (code "568") (name "Net-(IC53-Pad22)") (class "Default")
      (node (ref "IC53") (pin "22") (pinfunction "22_22") (pintype "passive"))
      (node (ref "IC54") (pin "22") (pinfunction "22_22") (pintype "passive"))
      (node (ref "IC55") (pin "22") (pinfunction "22_22") (pintype "passive"))
      (node (ref "IC56") (pin "22") (pinfunction "22_22") (pintype "passive"))
    )
    (net (code "569") (name "Net-(IC53-Pad23)") (class "Default")
      (node (ref "IC53") (pin "23") (pinfunction "23_23") (pintype "passive"))
      (node (ref "IC54") (pin "23") (pinfunction "23_23") (pintype "passive"))
      (node (ref "IC55") (pin "23") (pinfunction "23_23") (pintype "passive"))
      (node (ref "IC56") (pin "23") (pinfunction "23_23") (pintype "passive"))
    )
    (net (code "570") (name "Net-(IC53-Pad24)") (class "Default")
      (node (ref "IC53") (pin "24") (pinfunction "24_24") (pintype "passive"))
      (node (ref "IC54") (pin "24") (pinfunction "24_24") (pintype "passive"))
      (node (ref "IC55") (pin "24") (pinfunction "24_24") (pintype "passive"))
      (node (ref "IC56") (pin "24") (pinfunction "24_24") (pintype "passive"))
    )
    (net (code "571") (name "Net-(IC53-Pad25)") (class "Default")
      (node (ref "IC53") (pin "25") (pinfunction "25_25") (pintype "passive"))
      (node (ref "IC54") (pin "25") (pinfunction "25_25") (pintype "passive"))
      (node (ref "IC55") (pin "25") (pinfunction "25_25") (pintype "passive"))
      (node (ref "IC56") (pin "25") (pinfunction "25_25") (pintype "passive"))
    )
    (net (code "572") (name "Net-(IC53-Pad26)") (class "Default")
      (node (ref "IC53") (pin "26") (pinfunction "26_26") (pintype "passive"))
      (node (ref "IC54") (pin "26") (pinfunction "26_26") (pintype "passive"))
      (node (ref "IC55") (pin "26") (pinfunction "26_26") (pintype "passive"))
      (node (ref "IC56") (pin "26") (pinfunction "26_26") (pintype "passive"))
    )
    (net (code "573") (name "Net-(IC53-Pad27)") (class "Default")
      (node (ref "IC53") (pin "27") (pinfunction "27_27") (pintype "passive"))
      (node (ref "IC54") (pin "27") (pinfunction "27_27") (pintype "passive"))
      (node (ref "IC55") (pin "27") (pinfunction "27_27") (pintype "passive"))
      (node (ref "IC56") (pin "27") (pinfunction "27_27") (pintype "passive"))
    )
    (net (code "574") (name "Net-(IC53-Pad28)") (class "Default")
      (node (ref "IC53") (pin "28") (pinfunction "28_28") (pintype "passive"))
      (node (ref "IC54") (pin "28") (pinfunction "28_28") (pintype "passive"))
      (node (ref "IC55") (pin "28") (pinfunction "28_28") (pintype "passive"))
      (node (ref "IC56") (pin "28") (pinfunction "28_28") (pintype "passive"))
    )
    (net (code "575") (name "Net-(IC53-Pad29)") (class "Default")
      (node (ref "IC53") (pin "29") (pinfunction "29_29") (pintype "passive"))
      (node (ref "IC54") (pin "29") (pinfunction "29_29") (pintype "passive"))
      (node (ref "IC55") (pin "29") (pinfunction "29_29") (pintype "passive"))
      (node (ref "IC56") (pin "29") (pinfunction "29_29") (pintype "passive"))
    )
    (net (code "576") (name "Net-(IC53-Pad30)") (class "Default")
      (node (ref "IC53") (pin "30") (pinfunction "30_30") (pintype "passive"))
      (node (ref "IC54") (pin "30") (pinfunction "30_30") (pintype "passive"))
      (node (ref "IC55") (pin "30") (pinfunction "30_30") (pintype "passive"))
      (node (ref "IC56") (pin "30") (pinfunction "30_30") (pintype "passive"))
    )
    (net (code "577") (name "Net-(IC53-Pad31)") (class "Default")
      (node (ref "IC53") (pin "31") (pinfunction "31_31") (pintype "passive"))
      (node (ref "IC54") (pin "31") (pinfunction "31_31") (pintype "passive"))
      (node (ref "IC55") (pin "31") (pinfunction "31_31") (pintype "passive"))
      (node (ref "IC56") (pin "31") (pinfunction "31_31") (pintype "passive"))
    )
    (net (code "578") (name "Net-(IC53-Pad32)") (class "Default")
      (node (ref "IC53") (pin "32") (pinfunction "32_32") (pintype "passive"))
      (node (ref "IC54") (pin "32") (pinfunction "32_32") (pintype "passive"))
      (node (ref "IC55") (pin "32") (pinfunction "32_32") (pintype "passive"))
      (node (ref "IC56") (pin "32") (pinfunction "32_32") (pintype "passive"))
    )
    (net (code "579") (name "Net-(IC53-Pad33)") (class "Default")
      (node (ref "IC53") (pin "33") (pinfunction "33_33") (pintype "passive"))
      (node (ref "IC54") (pin "33") (pinfunction "33_33") (pintype "passive"))
      (node (ref "IC55") (pin "33") (pinfunction "33_33") (pintype "passive"))
      (node (ref "IC56") (pin "33") (pinfunction "33_33") (pintype "passive"))
    )
    (net (code "580") (name "Net-(IC53-Pad34)") (class "Default")
      (node (ref "IC53") (pin "34") (pinfunction "34_34") (pintype "passive"))
      (node (ref "IC54") (pin "34") (pinfunction "34_34") (pintype "passive"))
      (node (ref "IC55") (pin "34") (pinfunction "34_34") (pintype "passive"))
      (node (ref "IC56") (pin "34") (pinfunction "34_34") (pintype "passive"))
    )
    (net (code "581") (name "Net-(IC53-Pad35)") (class "Default")
      (node (ref "IC53") (pin "35") (pinfunction "35_35") (pintype "passive"))
      (node (ref "IC54") (pin "35") (pinfunction "35_35") (pintype "passive"))
      (node (ref "IC55") (pin "35") (pinfunction "35_35") (pintype "passive"))
      (node (ref "IC56") (pin "35") (pinfunction "35_35") (pintype "passive"))
    )
    (net (code "582") (name "Net-(IC53-Pad36)") (class "Default")
      (node (ref "IC53") (pin "36") (pinfunction "36_36") (pintype "passive"))
      (node (ref "IC54") (pin "36") (pinfunction "36_36") (pintype "passive"))
      (node (ref "IC55") (pin "36") (pinfunction "36_36") (pintype "passive"))
      (node (ref "IC56") (pin "36") (pinfunction "36_36") (pintype "passive"))
    )
    (net (code "583") (name "Net-(IC53-Pad37)") (class "Default")
      (node (ref "IC53") (pin "37") (pinfunction "37_37") (pintype "passive"))
      (node (ref "IC54") (pin "37") (pinfunction "37_37") (pintype "passive"))
      (node (ref "IC55") (pin "37") (pinfunction "37_37") (pintype "passive"))
      (node (ref "IC56") (pin "37") (pinfunction "37_37") (pintype "passive"))
    )
    (net (code "584") (name "Net-(IC53-Pad38)") (class "Default")
      (node (ref "IC53") (pin "38") (pinfunction "38_38") (pintype "passive"))
      (node (ref "IC54") (pin "38") (pinfunction "38_38") (pintype "passive"))
      (node (ref "IC55") (pin "38") (pinfunction "38_38") (pintype "passive"))
      (node (ref "IC56") (pin "38") (pinfunction "38_38") (pintype "passive"))
    )
    (net (code "585") (name "Net-(IC53-Pad39)") (class "Default")
      (node (ref "IC53") (pin "39") (pinfunction "39_39") (pintype "passive"))
      (node (ref "IC54") (pin "39") (pinfunction "39_39") (pintype "passive"))
      (node (ref "IC55") (pin "39") (pinfunction "39_39") (pintype "passive"))
      (node (ref "IC56") (pin "39") (pinfunction "39_39") (pintype "passive"))
    )
    (net (code "586") (name "Net-(IC53-Pad40)") (class "Default")
      (node (ref "IC53") (pin "40") (pinfunction "40_40") (pintype "passive"))
      (node (ref "IC54") (pin "40") (pinfunction "40_40") (pintype "passive"))
      (node (ref "IC55") (pin "40") (pinfunction "40_40") (pintype "passive"))
      (node (ref "IC56") (pin "40") (pinfunction "40_40") (pintype "passive"))
    )
    (net (code "587") (name "Net-(IC53-Pad41)") (class "Default")
      (node (ref "IC53") (pin "41") (pinfunction "41_41") (pintype "passive"))
      (node (ref "IC54") (pin "41") (pinfunction "41_41") (pintype "passive"))
      (node (ref "IC55") (pin "41") (pinfunction "41_41") (pintype "passive"))
      (node (ref "IC56") (pin "41") (pinfunction "41_41") (pintype "passive"))
    )
    (net (code "588") (name "Net-(IC53-Pad42)") (class "Default")
      (node (ref "IC53") (pin "42") (pinfunction "42_42") (pintype "passive"))
      (node (ref "IC54") (pin "42") (pinfunction "42_42") (pintype "passive"))
      (node (ref "IC55") (pin "42") (pinfunction "42_42") (pintype "passive"))
      (node (ref "IC56") (pin "42") (pinfunction "42_42") (pintype "passive"))
    )
    (net (code "589") (name "Net-(IC57-Pad1)") (class "Default")
      (node (ref "IC57") (pin "1") (pinfunction "1_1") (pintype "passive"))
      (node (ref "IC58") (pin "1") (pinfunction "1_1") (pintype "passive"))
      (node (ref "IC59") (pin "1") (pinfunction "1_1") (pintype "passive"))
      (node (ref "IC60") (pin "1") (pinfunction "1_1") (pintype "passive"))
    )
    (net (code "590") (name "Net-(IC57-Pad2)") (class "Default")
      (node (ref "IC57") (pin "2") (pinfunction "2_2") (pintype "passive"))
      (node (ref "IC58") (pin "2") (pinfunction "2_2") (pintype "passive"))
      (node (ref "IC59") (pin "2") (pinfunction "2_2") (pintype "passive"))
      (node (ref "IC60") (pin "2") (pinfunction "2_2") (pintype "passive"))
    )
    (net (code "591") (name "Net-(IC57-Pad3)") (class "Default")
      (node (ref "IC57") (pin "3") (pinfunction "3_3") (pintype "passive"))
      (node (ref "IC58") (pin "3") (pinfunction "3_3") (pintype "passive"))
      (node (ref "IC59") (pin "3") (pinfunction "3_3") (pintype "passive"))
      (node (ref "IC60") (pin "3") (pinfunction "3_3") (pintype "passive"))
    )
    (net (code "592") (name "Net-(IC57-Pad4)") (class "Default")
      (node (ref "IC57") (pin "4") (pinfunction "4_4") (pintype "passive"))
      (node (ref "IC58") (pin "4") (pinfunction "4_4") (pintype "passive"))
      (node (ref "IC59") (pin "4") (pinfunction "4_4") (pintype "passive"))
      (node (ref "IC60") (pin "4") (pinfunction "4_4") (pintype "passive"))
    )
    (net (code "593") (name "Net-(IC57-Pad5)") (class "Default")
      (node (ref "IC57") (pin "5") (pinfunction "5_5") (pintype "passive"))
      (node (ref "IC58") (pin "5") (pinfunction "5_5") (pintype "passive"))
      (node (ref "IC59") (pin "5") (pinfunction "5_5") (pintype "passive"))
      (node (ref "IC60") (pin "5") (pinfunction "5_5") (pintype "passive"))
    )
    (net (code "594") (name "Net-(IC57-Pad6)") (class "Default")
      (node (ref "IC57") (pin "6") (pinfunction "6_6") (pintype "passive"))
      (node (ref "IC58") (pin "6") (pinfunction "6_6") (pintype "passive"))
      (node (ref "IC59") (pin "6") (pinfunction "6_6") (pintype "passive"))
      (node (ref "IC60") (pin "6") (pinfunction "6_6") (pintype "passive"))
    )
    (net (code "595") (name "Net-(IC57-Pad7)") (class "Default")
      (node (ref "IC57") (pin "7") (pinfunction "7_7") (pintype "passive"))
      (node (ref "IC58") (pin "7") (pinfunction "7_7") (pintype "passive"))
      (node (ref "IC59") (pin "7") (pinfunction "7_7") (pintype "passive"))
      (node (ref "IC60") (pin "7") (pinfunction "7_7") (pintype "passive"))
    )
    (net (code "596") (name "Net-(IC57-Pad8)") (class "Default")
      (node (ref "IC57") (pin "8") (pinfunction "8_8") (pintype "passive"))
      (node (ref "IC58") (pin "8") (pinfunction "8_8") (pintype "passive"))
      (node (ref "IC59") (pin "8") (pinfunction "8_8") (pintype "passive"))
      (node (ref "IC60") (pin "8") (pinfunction "8_8") (pintype "passive"))
    )
    (net (code "597") (name "Net-(IC57-Pad9)") (class "Default")
      (node (ref "IC57") (pin "9") (pinfunction "9_9") (pintype "passive"))
      (node (ref "IC58") (pin "9") (pinfunction "9_9") (pintype "passive"))
      (node (ref "IC59") (pin "9") (pinfunction "9_9") (pintype "passive"))
      (node (ref "IC60") (pin "9") (pinfunction "9_9") (pintype "passive"))
    )
    (net (code "598") (name "Net-(IC57-Pad10)") (class "Default")
      (node (ref "IC57") (pin "10") (pinfunction "10_10") (pintype "passive"))
      (node (ref "IC58") (pin "10") (pinfunction "10_10") (pintype "passive"))
      (node (ref "IC59") (pin "10") (pinfunction "10_10") (pintype "passive"))
      (node (ref "IC60") (pin "10") (pinfunction "10_10") (pintype "passive"))
    )
    (net (code "599") (name "Net-(IC57-Pad11)") (class "Default")
      (node (ref "IC57") (pin "11") (pinfunction "11_11") (pintype "passive"))
      (node (ref "IC58") (pin "11") (pinfunction "11_11") (pintype "passive"))
      (node (ref "IC59") (pin "11") (pinfunction "11_11") (pintype "passive"))
      (node (ref "IC60") (pin "11") (pinfunction "11_11") (pintype "passive"))
    )
    (net (code "600") (name "Net-(IC57-Pad12)") (class "Default")
      (node (ref "IC57") (pin "12") (pinfunction "12_12") (pintype "passive"))
      (node (ref "IC58") (pin "12") (pinfunction "12_12") (pintype "passive"))
      (node (ref "IC59") (pin "12") (pinfunction "12_12") (pintype "passive"))
      (node (ref "IC60") (pin "12") (pinfunction "12_12") (pintype "passive"))
    )
    (net (code "601") (name "Net-(IC57-Pad13)") (class "Default")
      (node (ref "IC57") (pin "13") (pinfunction "13_13") (pintype "passive"))
      (node (ref "IC58") (pin "13") (pinfunction "13_13") (pintype "passive"))
      (node (ref "IC59") (pin "13") (pinfunction "13_13") (pintype "passive"))
      (node (ref "IC60") (pin "13") (pinfunction "13_13") (pintype "passive"))
    )
    (net (code "602") (name "Net-(IC57-Pad14)") (class "Default")
      (node (ref "IC57") (pin "14") (pinfunction "14_14") (pintype "passive"))
      (node (ref "IC58") (pin "14") (pinfunction "14_14") (pintype "passive"))
      (node (ref "IC59") (pin "14") (pinfunction "14_14") (pintype "passive"))
      (node (ref "IC60") (pin "14") (pinfunction "14_14") (pintype "passive"))
    )
    (net (code "603") (name "Net-(IC57-Pad15)") (class "Default")
      (node (ref "IC57") (pin "15") (pinfunction "15_15") (pintype "passive"))
      (node (ref "IC58") (pin "15") (pinfunction "15_15") (pintype "passive"))
      (node (ref "IC59") (pin "15") (pinfunction "15_15") (pintype "passive"))
      (node (ref "IC60") (pin "15") (pinfunction "15_15") (pintype "passive"))
    )
    (net (code "604") (name "Net-(IC57-Pad16)") (class "Default")
      (node (ref "IC57") (pin "16") (pinfunction "16_16") (pintype "passive"))
      (node (ref "IC58") (pin "16") (pinfunction "16_16") (pintype "passive"))
      (node (ref "IC59") (pin "16") (pinfunction "16_16") (pintype "passive"))
      (node (ref "IC60") (pin "16") (pinfunction "16_16") (pintype "passive"))
    )
    (net (code "605") (name "Net-(IC57-Pad17)") (class "Default")
      (node (ref "IC57") (pin "17") (pinfunction "17_17") (pintype "passive"))
      (node (ref "IC58") (pin "17") (pinfunction "17_17") (pintype "passive"))
      (node (ref "IC59") (pin "17") (pinfunction "17_17") (pintype "passive"))
      (node (ref "IC60") (pin "17") (pinfunction "17_17") (pintype "passive"))
    )
    (net (code "606") (name "Net-(IC57-Pad18)") (class "Default")
      (node (ref "IC57") (pin "18") (pinfunction "18_18") (pintype "passive"))
      (node (ref "IC58") (pin "18") (pinfunction "18_18") (pintype "passive"))
      (node (ref "IC59") (pin "18") (pinfunction "18_18") (pintype "passive"))
      (node (ref "IC60") (pin "18") (pinfunction "18_18") (pintype "passive"))
    )
    (net (code "607") (name "Net-(IC57-Pad19)") (class "Default")
      (node (ref "IC57") (pin "19") (pinfunction "19_19") (pintype "passive"))
      (node (ref "IC58") (pin "19") (pinfunction "19_19") (pintype "passive"))
      (node (ref "IC59") (pin "19") (pinfunction "19_19") (pintype "passive"))
      (node (ref "IC60") (pin "19") (pinfunction "19_19") (pintype "passive"))
    )
    (net (code "608") (name "Net-(IC57-Pad20)") (class "Default")
      (node (ref "IC57") (pin "20") (pinfunction "20_20") (pintype "passive"))
      (node (ref "IC58") (pin "20") (pinfunction "20_20") (pintype "passive"))
      (node (ref "IC59") (pin "20") (pinfunction "20_20") (pintype "passive"))
      (node (ref "IC60") (pin "20") (pinfunction "20_20") (pintype "passive"))
    )
    (net (code "609") (name "Net-(IC57-Pad21)") (class "Default")
      (node (ref "IC57") (pin "21") (pinfunction "21_21") (pintype "passive"))
      (node (ref "IC58") (pin "21") (pinfunction "21_21") (pintype "passive"))
      (node (ref "IC59") (pin "21") (pinfunction "21_21") (pintype "passive"))
      (node (ref "IC60") (pin "21") (pinfunction "21_21") (pintype "passive"))
    )
    (net (code "610") (name "Net-(IC57-Pad22)") (class "Default")
      (node (ref "IC57") (pin "22") (pinfunction "22_22") (pintype "passive"))
      (node (ref "IC58") (pin "22") (pinfunction "22_22") (pintype "passive"))
      (node (ref "IC59") (pin "22") (pinfunction "22_22") (pintype "passive"))
      (node (ref "IC60") (pin "22") (pinfunction "22_22") (pintype "passive"))
    )
    (net (code "611") (name "Net-(IC57-Pad23)") (class "Default")
      (node (ref "IC57") (pin "23") (pinfunction "23_23") (pintype "passive"))
      (node (ref "IC58") (pin "23") (pinfunction "23_23") (pintype "passive"))
      (node (ref "IC59") (pin "23") (pinfunction "23_23") (pintype "passive"))
      (node (ref "IC60") (pin "23") (pinfunction "23_23") (pintype "passive"))
    )
    (net (code "612") (name "Net-(IC57-Pad24)") (class "Default")
      (node (ref "IC57") (pin "24") (pinfunction "24_24") (pintype "passive"))
      (node (ref "IC58") (pin "24") (pinfunction "24_24") (pintype "passive"))
      (node (ref "IC59") (pin "24") (pinfunction "24_24") (pintype "passive"))
      (node (ref "IC60") (pin "24") (pinfunction "24_24") (pintype "passive"))
    )
    (net (code "613") (name "Net-(IC57-Pad25)") (class "Default")
      (node (ref "IC57") (pin "25") (pinfunction "25_25") (pintype "passive"))
      (node (ref "IC58") (pin "25") (pinfunction "25_25") (pintype "passive"))
      (node (ref "IC59") (pin "25") (pinfunction "25_25") (pintype "passive"))
      (node (ref "IC60") (pin "25") (pinfunction "25_25") (pintype "passive"))
    )
    (net (code "614") (name "Net-(IC57-Pad26)") (class "Default")
      (node (ref "IC57") (pin "26") (pinfunction "26_26") (pintype "passive"))
      (node (ref "IC58") (pin "26") (pinfunction "26_26") (pintype "passive"))
      (node (ref "IC59") (pin "26") (pinfunction "26_26") (pintype "passive"))
      (node (ref "IC60") (pin "26") (pinfunction "26_26") (pintype "passive"))
    )
    (net (code "615") (name "Net-(IC57-Pad27)") (class "Default")
      (node (ref "IC57") (pin "27") (pinfunction "27_27") (pintype "passive"))
      (node (ref "IC58") (pin "27") (pinfunction "27_27") (pintype "passive"))
      (node (ref "IC59") (pin "27") (pinfunction "27_27") (pintype "passive"))
      (node (ref "IC60") (pin "27") (pinfunction "27_27") (pintype "passive"))
    )
    (net (code "616") (name "Net-(IC57-Pad28)") (class "Default")
      (node (ref "IC57") (pin "28") (pinfunction "28_28") (pintype "passive"))
      (node (ref "IC58") (pin "28") (pinfunction "28_28") (pintype "passive"))
      (node (ref "IC59") (pin "28") (pinfunction "28_28") (pintype "passive"))
      (node (ref "IC60") (pin "28") (pinfunction "28_28") (pintype "passive"))
    )
    (net (code "617") (name "Net-(IC57-Pad29)") (class "Default")
      (node (ref "IC57") (pin "29") (pinfunction "29_29") (pintype "passive"))
      (node (ref "IC58") (pin "29") (pinfunction "29_29") (pintype "passive"))
      (node (ref "IC59") (pin "29") (pinfunction "29_29") (pintype "passive"))
      (node (ref "IC60") (pin "29") (pinfunction "29_29") (pintype "passive"))
    )
    (net (code "618") (name "Net-(IC57-Pad30)") (class "Default")
      (node (ref "IC57") (pin "30") (pinfunction "30_30") (pintype "passive"))
      (node (ref "IC58") (pin "30") (pinfunction "30_30") (pintype "passive"))
      (node (ref "IC59") (pin "30") (pinfunction "30_30") (pintype "passive"))
      (node (ref "IC60") (pin "30") (pinfunction "30_30") (pintype "passive"))
    )
    (net (code "619") (name "Net-(IC57-Pad31)") (class "Default")
      (node (ref "IC57") (pin "31") (pinfunction "31_31") (pintype "passive"))
      (node (ref "IC58") (pin "31") (pinfunction "31_31") (pintype "passive"))
      (node (ref "IC59") (pin "31") (pinfunction "31_31") (pintype "passive"))
      (node (ref "IC60") (pin "31") (pinfunction "31_31") (pintype "passive"))
    )
    (net (code "620") (name "Net-(IC57-Pad32)") (class "Default")
      (node (ref "IC57") (pin "32") (pinfunction "32_32") (pintype "passive"))
      (node (ref "IC58") (pin "32") (pinfunction "32_32") (pintype "passive"))
      (node (ref "IC59") (pin "32") (pinfunction "32_32") (pintype "passive"))
      (node (ref "IC60") (pin "32") (pinfunction "32_32") (pintype "passive"))
    )
    (net (code "621") (name "Net-(IC57-Pad33)") (class "Default")
      (node (ref "IC57") (pin "33") (pinfunction "33_33") (pintype "passive"))
      (node (ref "IC58") (pin "33") (pinfunction "33_33") (pintype "passive"))
      (node (ref "IC59") (pin "33") (pinfunction "33_33") (pintype "passive"))
      (node (ref "IC60") (pin "33") (pinfunction "33_33") (pintype "passive"))
    )
    (net (code "622") (name "Net-(IC57-Pad34)") (class "Default")
      (node (ref "IC57") (pin "34") (pinfunction "34_34") (pintype "passive"))
      (node (ref "IC58") (pin "34") (pinfunction "34_34") (pintype "passive"))
      (node (ref "IC59") (pin "34") (pinfunction "34_34") (pintype "passive"))
      (node (ref "IC60") (pin "34") (pinfunction "34_34") (pintype "passive"))
    )
    (net (code "623") (name "Net-(IC57-Pad35)") (class "Default")
      (node (ref "IC57") (pin "35") (pinfunction "35_35") (pintype "passive"))
      (node (ref "IC58") (pin "35") (pinfunction "35_35") (pintype "passive"))
      (node (ref "IC59") (pin "35") (pinfunction "35_35") (pintype "passive"))
      (node (ref "IC60") (pin "35") (pinfunction "35_35") (pintype "passive"))
    )
    (net (code "624") (name "Net-(IC57-Pad36)") (class "Default")
      (node (ref "IC57") (pin "36") (pinfunction "36_36") (pintype "passive"))
      (node (ref "IC58") (pin "36") (pinfunction "36_36") (pintype "passive"))
      (node (ref "IC59") (pin "36") (pinfunction "36_36") (pintype "passive"))
      (node (ref "IC60") (pin "36") (pinfunction "36_36") (pintype "passive"))
    )
    (net (code "625") (name "Net-(IC57-Pad37)") (class "Default")
      (node (ref "IC57") (pin "37") (pinfunction "37_37") (pintype "passive"))
      (node (ref "IC58") (pin "37") (pinfunction "37_37") (pintype "passive"))
      (node (ref "IC59") (pin "37") (pinfunction "37_37") (pintype "passive"))
      (node (ref "IC60") (pin "37") (pinfunction "37_37") (pintype "passive"))
    )
    (net (code "626") (name "Net-(IC57-Pad38)") (class "Default")
      (node (ref "IC57") (pin "38") (pinfunction "38_38") (pintype "passive"))
      (node (ref "IC58") (pin "38") (pinfunction "38_38") (pintype "passive"))
      (node (ref "IC59") (pin "38") (pinfunction "38_38") (pintype "passive"))
      (node (ref "IC60") (pin "38") (pinfunction "38_38") (pintype "passive"))
    )
    (net (code "627") (name "Net-(IC57-Pad39)") (class "Default")
      (node (ref "IC57") (pin "39") (pinfunction "39_39") (pintype "passive"))
      (node (ref "IC58") (pin "39") (pinfunction "39_39") (pintype "passive"))
      (node (ref "IC59") (pin "39") (pinfunction "39_39") (pintype "passive"))
      (node (ref "IC60") (pin "39") (pinfunction "39_39") (pintype "passive"))
    )
    (net (code "628") (name "Net-(IC57-Pad40)") (class "Default")
      (node (ref "IC57") (pin "40") (pinfunction "40_40") (pintype "passive"))
      (node (ref "IC58") (pin "40") (pinfunction "40_40") (pintype "passive"))
      (node (ref "IC59") (pin "40") (pinfunction "40_40") (pintype "passive"))
      (node (ref "IC60") (pin "40") (pinfunction "40_40") (pintype "passive"))
    )
    (net (code "629") (name "Net-(IC57-Pad41)") (class "Default")
      (node (ref "IC57") (pin "41") (pinfunction "41_41") (pintype "passive"))
      (node (ref "IC58") (pin "41") (pinfunction "41_41") (pintype "passive"))
      (node (ref "IC59") (pin "41") (pinfunction "41_41") (pintype "passive"))
      (node (ref "IC60") (pin "41") (pinfunction "41_41") (pintype "passive"))
    )
    (net (code "630") (name "Net-(IC57-Pad42)") (class "Default")
      (node (ref "IC57") (pin "42") (pinfunction "42_42") (pintype "passive"))
      (node (ref "IC58") (pin "42") (pinfunction "42_42") (pintype "passive"))
      (node (ref "IC59") (pin "42") (pinfunction "42_42") (pintype "passive"))
      (node (ref "IC60") (pin "42") (pinfunction "42_42") (pintype "passive"))
    )
    (net (code "631") (name "Net-(IC61-Pad1)") (class "Default")
      (node (ref "IC61") (pin "1") (pinfunction "1_1") (pintype "passive"))
      (node (ref "IC62") (pin "1") (pinfunction "1_1") (pintype "passive"))
      (node (ref "IC63") (pin "1") (pinfunction "1_1") (pintype "passive"))
      (node (ref "IC64") (pin "1") (pinfunction "1_1") (pintype "passive"))
    )
    (net (code "632") (name "Net-(IC61-Pad2)") (class "Default")
      (node (ref "IC61") (pin "2") (pinfunction "2_2") (pintype "passive"))
      (node (ref "IC62") (pin "2") (pinfunction "2_2") (pintype "passive"))
      (node (ref "IC63") (pin "2") (pinfunction "2_2") (pintype "passive"))
      (node (ref "IC64") (pin "2") (pinfunction "2_2") (pintype "passive"))
    )
    (net (code "633") (name "Net-(IC61-Pad3)") (class "Default")
      (node (ref "IC61") (pin "3") (pinfunction "3_3") (pintype "passive"))
      (node (ref "IC62") (pin "3") (pinfunction "3_3") (pintype "passive"))
      (node (ref "IC63") (pin "3") (pinfunction "3_3") (pintype "passive"))
      (node (ref "IC64") (pin "3") (pinfunction "3_3") (pintype "passive"))
    )
    (net (code "634") (name "Net-(IC61-Pad4)") (class "Default")
      (node (ref "IC61") (pin "4") (pinfunction "4_4") (pintype "passive"))
      (node (ref "IC62") (pin "4") (pinfunction "4_4") (pintype "passive"))
      (node (ref "IC63") (pin "4") (pinfunction "4_4") (pintype "passive"))
      (node (ref "IC64") (pin "4") (pinfunction "4_4") (pintype "passive"))
    )
    (net (code "635") (name "Net-(IC61-Pad5)") (class "Default")
      (node (ref "IC61") (pin "5") (pinfunction "5_5") (pintype "passive"))
      (node (ref "IC62") (pin "5") (pinfunction "5_5") (pintype "passive"))
      (node (ref "IC63") (pin "5") (pinfunction "5_5") (pintype "passive"))
      (node (ref "IC64") (pin "5") (pinfunction "5_5") (pintype "passive"))
    )
    (net (code "636") (name "Net-(IC61-Pad6)") (class "Default")
      (node (ref "IC61") (pin "6") (pinfunction "6_6") (pintype "passive"))
      (node (ref "IC62") (pin "6") (pinfunction "6_6") (pintype "passive"))
      (node (ref "IC63") (pin "6") (pinfunction "6_6") (pintype "passive"))
      (node (ref "IC64") (pin "6") (pinfunction "6_6") (pintype "passive"))
    )
    (net (code "637") (name "Net-(IC61-Pad7)") (class "Default")
      (node (ref "IC61") (pin "7") (pinfunction "7_7") (pintype "passive"))
      (node (ref "IC62") (pin "7") (pinfunction "7_7") (pintype "passive"))
      (node (ref "IC63") (pin "7") (pinfunction "7_7") (pintype "passive"))
      (node (ref "IC64") (pin "7") (pinfunction "7_7") (pintype "passive"))
    )
    (net (code "638") (name "Net-(IC61-Pad8)") (class "Default")
      (node (ref "IC61") (pin "8") (pinfunction "8_8") (pintype "passive"))
      (node (ref "IC62") (pin "8") (pinfunction "8_8") (pintype "passive"))
      (node (ref "IC63") (pin "8") (pinfunction "8_8") (pintype "passive"))
      (node (ref "IC64") (pin "8") (pinfunction "8_8") (pintype "passive"))
    )
    (net (code "639") (name "Net-(IC61-Pad9)") (class "Default")
      (node (ref "IC61") (pin "9") (pinfunction "9_9") (pintype "passive"))
      (node (ref "IC62") (pin "9") (pinfunction "9_9") (pintype "passive"))
      (node (ref "IC63") (pin "9") (pinfunction "9_9") (pintype "passive"))
      (node (ref "IC64") (pin "9") (pinfunction "9_9") (pintype "passive"))
    )
    (net (code "640") (name "Net-(IC61-Pad10)") (class "Default")
      (node (ref "IC61") (pin "10") (pinfunction "10_10") (pintype "passive"))
      (node (ref "IC62") (pin "10") (pinfunction "10_10") (pintype "passive"))
      (node (ref "IC63") (pin "10") (pinfunction "10_10") (pintype "passive"))
      (node (ref "IC64") (pin "10") (pinfunction "10_10") (pintype "passive"))
    )
    (net (code "641") (name "Net-(IC61-Pad11)") (class "Default")
      (node (ref "IC61") (pin "11") (pinfunction "11_11") (pintype "passive"))
      (node (ref "IC62") (pin "11") (pinfunction "11_11") (pintype "passive"))
      (node (ref "IC63") (pin "11") (pinfunction "11_11") (pintype "passive"))
      (node (ref "IC64") (pin "11") (pinfunction "11_11") (pintype "passive"))
    )
    (net (code "642") (name "Net-(IC61-Pad12)") (class "Default")
      (node (ref "IC61") (pin "12") (pinfunction "12_12") (pintype "passive"))
      (node (ref "IC62") (pin "12") (pinfunction "12_12") (pintype "passive"))
      (node (ref "IC63") (pin "12") (pinfunction "12_12") (pintype "passive"))
      (node (ref "IC64") (pin "12") (pinfunction "12_12") (pintype "passive"))
    )
    (net (code "643") (name "Net-(IC61-Pad13)") (class "Default")
      (node (ref "IC61") (pin "13") (pinfunction "13_13") (pintype "passive"))
      (node (ref "IC62") (pin "13") (pinfunction "13_13") (pintype "passive"))
      (node (ref "IC63") (pin "13") (pinfunction "13_13") (pintype "passive"))
      (node (ref "IC64") (pin "13") (pinfunction "13_13") (pintype "passive"))
    )
    (net (code "644") (name "Net-(IC61-Pad14)") (class "Default")
      (node (ref "IC61") (pin "14") (pinfunction "14_14") (pintype "passive"))
      (node (ref "IC62") (pin "14") (pinfunction "14_14") (pintype "passive"))
      (node (ref "IC63") (pin "14") (pinfunction "14_14") (pintype "passive"))
      (node (ref "IC64") (pin "14") (pinfunction "14_14") (pintype "passive"))
    )
    (net (code "645") (name "Net-(IC61-Pad15)") (class "Default")
      (node (ref "IC61") (pin "15") (pinfunction "15_15") (pintype "passive"))
      (node (ref "IC62") (pin "15") (pinfunction "15_15") (pintype "passive"))
      (node (ref "IC63") (pin "15") (pinfunction "15_15") (pintype "passive"))
      (node (ref "IC64") (pin "15") (pinfunction "15_15") (pintype "passive"))
    )
    (net (code "646") (name "Net-(IC61-Pad16)") (class "Default")
      (node (ref "IC61") (pin "16") (pinfunction "16_16") (pintype "passive"))
      (node (ref "IC62") (pin "16") (pinfunction "16_16") (pintype "passive"))
      (node (ref "IC63") (pin "16") (pinfunction "16_16") (pintype "passive"))
      (node (ref "IC64") (pin "16") (pinfunction "16_16") (pintype "passive"))
    )
    (net (code "647") (name "Net-(IC61-Pad17)") (class "Default")
      (node (ref "IC61") (pin "17") (pinfunction "17_17") (pintype "passive"))
      (node (ref "IC62") (pin "17") (pinfunction "17_17") (pintype "passive"))
      (node (ref "IC63") (pin "17") (pinfunction "17_17") (pintype "passive"))
      (node (ref "IC64") (pin "17") (pinfunction "17_17") (pintype "passive"))
    )
    (net (code "648") (name "Net-(IC61-Pad18)") (class "Default")
      (node (ref "IC61") (pin "18") (pinfunction "18_18") (pintype "passive"))
      (node (ref "IC62") (pin "18") (pinfunction "18_18") (pintype "passive"))
      (node (ref "IC63") (pin "18") (pinfunction "18_18") (pintype "passive"))
      (node (ref "IC64") (pin "18") (pinfunction "18_18") (pintype "passive"))
    )
    (net (code "649") (name "Net-(IC61-Pad19)") (class "Default")
      (node (ref "IC61") (pin "19") (pinfunction "19_19") (pintype "passive"))
      (node (ref "IC62") (pin "19") (pinfunction "19_19") (pintype "passive"))
      (node (ref "IC63") (pin "19") (pinfunction "19_19") (pintype "passive"))
      (node (ref "IC64") (pin "19") (pinfunction "19_19") (pintype "passive"))
    )
    (net (code "650") (name "Net-(IC61-Pad20)") (class "Default")
      (node (ref "IC61") (pin "20") (pinfunction "20_20") (pintype "passive"))
      (node (ref "IC62") (pin "20") (pinfunction "20_20") (pintype "passive"))
      (node (ref "IC63") (pin "20") (pinfunction "20_20") (pintype "passive"))
      (node (ref "IC64") (pin "20") (pinfunction "20_20") (pintype "passive"))
    )
    (net (code "651") (name "Net-(IC61-Pad21)") (class "Default")
      (node (ref "IC61") (pin "21") (pinfunction "21_21") (pintype "passive"))
      (node (ref "IC62") (pin "21") (pinfunction "21_21") (pintype "passive"))
      (node (ref "IC63") (pin "21") (pinfunction "21_21") (pintype "passive"))
      (node (ref "IC64") (pin "21") (pinfunction "21_21") (pintype "passive"))
    )
    (net (code "652") (name "Net-(IC61-Pad22)") (class "Default")
      (node (ref "IC61") (pin "22") (pinfunction "22_22") (pintype "passive"))
      (node (ref "IC62") (pin "22") (pinfunction "22_22") (pintype "passive"))
      (node (ref "IC63") (pin "22") (pinfunction "22_22") (pintype "passive"))
      (node (ref "IC64") (pin "22") (pinfunction "22_22") (pintype "passive"))
    )
    (net (code "653") (name "Net-(IC61-Pad23)") (class "Default")
      (node (ref "IC61") (pin "23") (pinfunction "23_23") (pintype "passive"))
      (node (ref "IC62") (pin "23") (pinfunction "23_23") (pintype "passive"))
      (node (ref "IC63") (pin "23") (pinfunction "23_23") (pintype "passive"))
      (node (ref "IC64") (pin "23") (pinfunction "23_23") (pintype "passive"))
    )
    (net (code "654") (name "Net-(IC61-Pad24)") (class "Default")
      (node (ref "IC61") (pin "24") (pinfunction "24_24") (pintype "passive"))
      (node (ref "IC62") (pin "24") (pinfunction "24_24") (pintype "passive"))
      (node (ref "IC63") (pin "24") (pinfunction "24_24") (pintype "passive"))
      (node (ref "IC64") (pin "24") (pinfunction "24_24") (pintype "passive"))
    )
    (net (code "655") (name "Net-(IC61-Pad25)") (class "Default")
      (node (ref "IC61") (pin "25") (pinfunction "25_25") (pintype "passive"))
      (node (ref "IC62") (pin "25") (pinfunction "25_25") (pintype "passive"))
      (node (ref "IC63") (pin "25") (pinfunction "25_25") (pintype "passive"))
      (node (ref "IC64") (pin "25") (pinfunction "25_25") (pintype "passive"))
    )
    (net (code "656") (name "Net-(IC61-Pad26)") (class "Default")
      (node (ref "IC61") (pin "26") (pinfunction "26_26") (pintype "passive"))
      (node (ref "IC62") (pin "26") (pinfunction "26_26") (pintype "passive"))
      (node (ref "IC63") (pin "26") (pinfunction "26_26") (pintype "passive"))
      (node (ref "IC64") (pin "26") (pinfunction "26_26") (pintype "passive"))
    )
    (net (code "657") (name "Net-(IC61-Pad27)") (class "Default")
      (node (ref "IC61") (pin "27") (pinfunction "27_27") (pintype "passive"))
      (node (ref "IC62") (pin "27") (pinfunction "27_27") (pintype "passive"))
      (node (ref "IC63") (pin "27") (pinfunction "27_27") (pintype "passive"))
      (node (ref "IC64") (pin "27") (pinfunction "27_27") (pintype "passive"))
    )
    (net (code "658") (name "Net-(IC61-Pad28)") (class "Default")
      (node (ref "IC61") (pin "28") (pinfunction "28_28") (pintype "passive"))
      (node (ref "IC62") (pin "28") (pinfunction "28_28") (pintype "passive"))
      (node (ref "IC63") (pin "28") (pinfunction "28_28") (pintype "passive"))
      (node (ref "IC64") (pin "28") (pinfunction "28_28") (pintype "passive"))
    )
    (net (code "659") (name "Net-(IC61-Pad29)") (class "Default")
      (node (ref "IC61") (pin "29") (pinfunction "29_29") (pintype "passive"))
      (node (ref "IC62") (pin "29") (pinfunction "29_29") (pintype "passive"))
      (node (ref "IC63") (pin "29") (pinfunction "29_29") (pintype "passive"))
      (node (ref "IC64") (pin "29") (pinfunction "29_29") (pintype "passive"))
    )
    (net (code "660") (name "Net-(IC61-Pad30)") (class "Default")
      (node (ref "IC61") (pin "30") (pinfunction "30_30") (pintype "passive"))
      (node (ref "IC62") (pin "30") (pinfunction "30_30") (pintype "passive"))
      (node (ref "IC63") (pin "30") (pinfunction "30_30") (pintype "passive"))
      (node (ref "IC64") (pin "30") (pinfunction "30_30") (pintype "passive"))
    )
    (net (code "661") (name "Net-(IC61-Pad31)") (class "Default")
      (node (ref "IC61") (pin "31") (pinfunction "31_31") (pintype "passive"))
      (node (ref "IC62") (pin "31") (pinfunction "31_31") (pintype "passive"))
      (node (ref "IC63") (pin "31") (pinfunction "31_31") (pintype "passive"))
      (node (ref "IC64") (pin "31") (pinfunction "31_31") (pintype "passive"))
    )
    (net (code "662") (name "Net-(IC61-Pad32)") (class "Default")
      (node (ref "IC61") (pin "32") (pinfunction "32_32") (pintype "passive"))
      (node (ref "IC62") (pin "32") (pinfunction "32_32") (pintype "passive"))
      (node (ref "IC63") (pin "32") (pinfunction "32_32") (pintype "passive"))
      (node (ref "IC64") (pin "32") (pinfunction "32_32") (pintype "passive"))
    )
    (net (code "663") (name "Net-(IC61-Pad33)") (class "Default")
      (node (ref "IC61") (pin "33") (pinfunction "33_33") (pintype "passive"))
      (node (ref "IC62") (pin "33") (pinfunction "33_33") (pintype "passive"))
      (node (ref "IC63") (pin "33") (pinfunction "33_33") (pintype "passive"))
      (node (ref "IC64") (pin "33") (pinfunction "33_33") (pintype "passive"))
    )
    (net (code "664") (name "Net-(IC61-Pad34)") (class "Default")
      (node (ref "IC61") (pin "34") (pinfunction "34_34") (pintype "passive"))
      (node (ref "IC62") (pin "34") (pinfunction "34_34") (pintype "passive"))
      (node (ref "IC63") (pin "34") (pinfunction "34_34") (pintype "passive"))
      (node (ref "IC64") (pin "34") (pinfunction "34_34") (pintype "passive"))
    )
    (net (code "665") (name "Net-(IC61-Pad35)") (class "Default")
      (node (ref "IC61") (pin "35") (pinfunction "35_35") (pintype "passive"))
      (node (ref "IC62") (pin "35") (pinfunction "35_35") (pintype "passive"))
      (node (ref "IC63") (pin "35") (pinfunction "35_35") (pintype "passive"))
      (node (ref "IC64") (pin "35") (pinfunction "35_35") (pintype "passive"))
    )
    (net (code "666") (name "Net-(IC61-Pad36)") (class "Default")
      (node (ref "IC61") (pin "36") (pinfunction "36_36") (pintype "passive"))
      (node (ref "IC62") (pin "36") (pinfunction "36_36") (pintype "passive"))
      (node (ref "IC63") (pin "36") (pinfunction "36_36") (pintype "passive"))
      (node (ref "IC64") (pin "36") (pinfunction "36_36") (pintype "passive"))
    )
    (net (code "667") (name "Net-(IC61-Pad37)") (class "Default")
      (node (ref "IC61") (pin "37") (pinfunction "37_37") (pintype "passive"))
      (node (ref "IC62") (pin "37") (pinfunction "37_37") (pintype "passive"))
      (node (ref "IC63") (pin "37") (pinfunction "37_37") (pintype "passive"))
      (node (ref "IC64") (pin "37") (pinfunction "37_37") (pintype "passive"))
    )
    (net (code "668") (name "Net-(IC61-Pad38)") (class "Default")
      (node (ref "IC61") (pin "38") (pinfunction "38_38") (pintype "passive"))
      (node (ref "IC62") (pin "38") (pinfunction "38_38") (pintype "passive"))
      (node (ref "IC63") (pin "38") (pinfunction "38_38") (pintype "passive"))
      (node (ref "IC64") (pin "38") (pinfunction "38_38") (pintype "passive"))
    )
    (net (code "669") (name "Net-(IC61-Pad39)") (class "Default")
      (node (ref "IC61") (pin "39") (pinfunction "39_39") (pintype "passive"))
      (node (ref "IC62") (pin "39") (pinfunction "39_39") (pintype "passive"))
      (node (ref "IC63") (pin "39") (pinfunction "39_39") (pintype "passive"))
      (node (ref "IC64") (pin "39") (pinfunction "39_39") (pintype "passive"))
    )
    (net (code "670") (name "Net-(IC61-Pad40)") (class "Default")
      (node (ref "IC61") (pin "40") (pinfunction "40_40") (pintype "passive"))
      (node (ref "IC62") (pin "40") (pinfunction "40_40") (pintype "passive"))
      (node (ref "IC63") (pin "40") (pinfunction "40_40") (pintype "passive"))
      (node (ref "IC64") (pin "40") (pinfunction "40_40") (pintype "passive"))
    )
    (net (code "671") (name "Net-(IC61-Pad41)") (class "Default")
      (node (ref "IC61") (pin "41") (pinfunction "41_41") (pintype "passive"))
      (node (ref "IC62") (pin "41") (pinfunction "41_41") (pintype "passive"))
      (node (ref "IC63") (pin "41") (pinfunction "41_41") (pintype "passive"))
      (node (ref "IC64") (pin "41") (pinfunction "41_41") (pintype "passive"))
    )
    (net (code "672") (name "Net-(IC61-Pad42)") (class "Default")
      (node (ref "IC61") (pin "42") (pinfunction "42_42") (pintype "passive"))
      (node (ref "IC62") (pin "42") (pinfunction "42_42") (pintype "passive"))
      (node (ref "IC63") (pin "42") (pinfunction "42_42") (pintype "passive"))
      (node (ref "IC64") (pin "42") (pinfunction "42_42") (pintype "passive"))
    )
    (net (code "673") (name "Net-(IC65-Pad1)") (class "Default")
      (node (ref "IC65") (pin "1") (pinfunction "1_1") (pintype "passive"))
      (node (ref "IC66") (pin "1") (pinfunction "1_1") (pintype "passive"))
      (node (ref "IC67") (pin "1") (pinfunction "1_1") (pintype "passive"))
      (node (ref "IC68") (pin "1") (pinfunction "1_1") (pintype "passive"))
    )
    (net (code "674") (name "Net-(IC65-Pad2)") (class "Default")
      (node (ref "IC65") (pin "2") (pinfunction "2_2") (pintype "passive"))
      (node (ref "IC66") (pin "2") (pinfunction "2_2") (pintype "passive"))
      (node (ref "IC67") (pin "2") (pinfunction "2_2") (pintype "passive"))
      (node (ref "IC68") (pin "2") (pinfunction "2_2") (pintype "passive"))
    )
    (net (code "675") (name "Net-(IC65-Pad3)") (class "Default")
      (node (ref "IC65") (pin "3") (pinfunction "3_3") (pintype "passive"))
      (node (ref "IC66") (pin "3") (pinfunction "3_3") (pintype "passive"))
      (node (ref "IC67") (pin "3") (pinfunction "3_3") (pintype "passive"))
      (node (ref "IC68") (pin "3") (pinfunction "3_3") (pintype "passive"))
    )
    (net (code "676") (name "Net-(IC65-Pad4)") (class "Default")
      (node (ref "IC65") (pin "4") (pinfunction "4_4") (pintype "passive"))
      (node (ref "IC66") (pin "4") (pinfunction "4_4") (pintype "passive"))
      (node (ref "IC67") (pin "4") (pinfunction "4_4") (pintype "passive"))
      (node (ref "IC68") (pin "4") (pinfunction "4_4") (pintype "passive"))
    )
    (net (code "677") (name "Net-(IC65-Pad5)") (class "Default")
      (node (ref "IC65") (pin "5") (pinfunction "5_5") (pintype "passive"))
      (node (ref "IC66") (pin "5") (pinfunction "5_5") (pintype "passive"))
      (node (ref "IC67") (pin "5") (pinfunction "5_5") (pintype "passive"))
      (node (ref "IC68") (pin "5") (pinfunction "5_5") (pintype "passive"))
    )
    (net (code "678") (name "Net-(IC65-Pad6)") (class "Default")
      (node (ref "IC65") (pin "6") (pinfunction "6_6") (pintype "passive"))
      (node (ref "IC66") (pin "6") (pinfunction "6_6") (pintype "passive"))
      (node (ref "IC67") (pin "6") (pinfunction "6_6") (pintype "passive"))
      (node (ref "IC68") (pin "6") (pinfunction "6_6") (pintype "passive"))
    )
    (net (code "679") (name "Net-(IC65-Pad7)") (class "Default")
      (node (ref "IC65") (pin "7") (pinfunction "7_7") (pintype "passive"))
      (node (ref "IC66") (pin "7") (pinfunction "7_7") (pintype "passive"))
      (node (ref "IC67") (pin "7") (pinfunction "7_7") (pintype "passive"))
      (node (ref "IC68") (pin "7") (pinfunction "7_7") (pintype "passive"))
    )
    (net (code "680") (name "Net-(IC65-Pad8)") (class "Default")
      (node (ref "IC65") (pin "8") (pinfunction "8_8") (pintype "passive"))
      (node (ref "IC66") (pin "8") (pinfunction "8_8") (pintype "passive"))
      (node (ref "IC67") (pin "8") (pinfunction "8_8") (pintype "passive"))
      (node (ref "IC68") (pin "8") (pinfunction "8_8") (pintype "passive"))
    )
    (net (code "681") (name "Net-(IC65-Pad9)") (class "Default")
      (node (ref "IC65") (pin "9") (pinfunction "9_9") (pintype "passive"))
      (node (ref "IC66") (pin "9") (pinfunction "9_9") (pintype "passive"))
      (node (ref "IC67") (pin "9") (pinfunction "9_9") (pintype "passive"))
      (node (ref "IC68") (pin "9") (pinfunction "9_9") (pintype "passive"))
    )
    (net (code "682") (name "Net-(IC65-Pad10)") (class "Default")
      (node (ref "IC65") (pin "10") (pinfunction "10_10") (pintype "passive"))
      (node (ref "IC66") (pin "10") (pinfunction "10_10") (pintype "passive"))
      (node (ref "IC67") (pin "10") (pinfunction "10_10") (pintype "passive"))
      (node (ref "IC68") (pin "10") (pinfunction "10_10") (pintype "passive"))
    )
    (net (code "683") (name "Net-(IC65-Pad11)") (class "Default")
      (node (ref "IC65") (pin "11") (pinfunction "11_11") (pintype "passive"))
      (node (ref "IC66") (pin "11") (pinfunction "11_11") (pintype "passive"))
      (node (ref "IC67") (pin "11") (pinfunction "11_11") (pintype "passive"))
      (node (ref "IC68") (pin "11") (pinfunction "11_11") (pintype "passive"))
    )
    (net (code "684") (name "Net-(IC65-Pad12)") (class "Default")
      (node (ref "IC65") (pin "12") (pinfunction "12_12") (pintype "passive"))
      (node (ref "IC66") (pin "12") (pinfunction "12_12") (pintype "passive"))
      (node (ref "IC67") (pin "12") (pinfunction "12_12") (pintype "passive"))
      (node (ref "IC68") (pin "12") (pinfunction "12_12") (pintype "passive"))
    )
    (net (code "685") (name "Net-(IC65-Pad13)") (class "Default")
      (node (ref "IC65") (pin "13") (pinfunction "13_13") (pintype "passive"))
      (node (ref "IC66") (pin "13") (pinfunction "13_13") (pintype "passive"))
      (node (ref "IC67") (pin "13") (pinfunction "13_13") (pintype "passive"))
      (node (ref "IC68") (pin "13") (pinfunction "13_13") (pintype "passive"))
    )
    (net (code "686") (name "Net-(IC65-Pad14)") (class "Default")
      (node (ref "IC65") (pin "14") (pinfunction "14_14") (pintype "passive"))
      (node (ref "IC66") (pin "14") (pinfunction "14_14") (pintype "passive"))
      (node (ref "IC67") (pin "14") (pinfunction "14_14") (pintype "passive"))
      (node (ref "IC68") (pin "14") (pinfunction "14_14") (pintype "passive"))
    )
    (net (code "687") (name "Net-(IC65-Pad15)") (class "Default")
      (node (ref "IC65") (pin "15") (pinfunction "15_15") (pintype "passive"))
      (node (ref "IC66") (pin "15") (pinfunction "15_15") (pintype "passive"))
      (node (ref "IC67") (pin "15") (pinfunction "15_15") (pintype "passive"))
      (node (ref "IC68") (pin "15") (pinfunction "15_15") (pintype "passive"))
    )
    (net (code "688") (name "Net-(IC65-Pad16)") (class "Default")
      (node (ref "IC65") (pin "16") (pinfunction "16_16") (pintype "passive"))
      (node (ref "IC66") (pin "16") (pinfunction "16_16") (pintype "passive"))
      (node (ref "IC67") (pin "16") (pinfunction "16_16") (pintype "passive"))
      (node (ref "IC68") (pin "16") (pinfunction "16_16") (pintype "passive"))
    )
    (net (code "689") (name "Net-(IC65-Pad17)") (class "Default")
      (node (ref "IC65") (pin "17") (pinfunction "17_17") (pintype "passive"))
      (node (ref "IC66") (pin "17") (pinfunction "17_17") (pintype "passive"))
      (node (ref "IC67") (pin "17") (pinfunction "17_17") (pintype "passive"))
      (node (ref "IC68") (pin "17") (pinfunction "17_17") (pintype "passive"))
    )
    (net (code "690") (name "Net-(IC65-Pad18)") (class "Default")
      (node (ref "IC65") (pin "18") (pinfunction "18_18") (pintype "passive"))
      (node (ref "IC66") (pin "18") (pinfunction "18_18") (pintype "passive"))
      (node (ref "IC67") (pin "18") (pinfunction "18_18") (pintype "passive"))
      (node (ref "IC68") (pin "18") (pinfunction "18_18") (pintype "passive"))
    )
    (net (code "691") (name "Net-(IC65-Pad19)") (class "Default")
      (node (ref "IC65") (pin "19") (pinfunction "19_19") (pintype "passive"))
      (node (ref "IC66") (pin "19") (pinfunction "19_19") (pintype "passive"))
      (node (ref "IC67") (pin "19") (pinfunction "19_19") (pintype "passive"))
      (node (ref "IC68") (pin "19") (pinfunction "19_19") (pintype "passive"))
    )
    (net (code "692") (name "Net-(IC65-Pad20)") (class "Default")
      (node (ref "IC65") (pin "20") (pinfunction "20_20") (pintype "passive"))
      (node (ref "IC66") (pin "20") (pinfunction "20_20") (pintype "passive"))
      (node (ref "IC67") (pin "20") (pinfunction "20_20") (pintype "passive"))
      (node (ref "IC68") (pin "20") (pinfunction "20_20") (pintype "passive"))
    )
    (net (code "693") (name "Net-(IC65-Pad21)") (class "Default")
      (node (ref "IC65") (pin "21") (pinfunction "21_21") (pintype "passive"))
      (node (ref "IC66") (pin "21") (pinfunction "21_21") (pintype "passive"))
      (node (ref "IC67") (pin "21") (pinfunction "21_21") (pintype "passive"))
      (node (ref "IC68") (pin "21") (pinfunction "21_21") (pintype "passive"))
    )
    (net (code "694") (name "Net-(IC65-Pad22)") (class "Default")
      (node (ref "IC65") (pin "22") (pinfunction "22_22") (pintype "passive"))
      (node (ref "IC66") (pin "22") (pinfunction "22_22") (pintype "passive"))
      (node (ref "IC67") (pin "22") (pinfunction "22_22") (pintype "passive"))
      (node (ref "IC68") (pin "22") (pinfunction "22_22") (pintype "passive"))
    )
    (net (code "695") (name "Net-(IC65-Pad23)") (class "Default")
      (node (ref "IC65") (pin "23") (pinfunction "23_23") (pintype "passive"))
      (node (ref "IC66") (pin "23") (pinfunction "23_23") (pintype "passive"))
      (node (ref "IC67") (pin "23") (pinfunction "23_23") (pintype "passive"))
      (node (ref "IC68") (pin "23") (pinfunction "23_23") (pintype "passive"))
    )
    (net (code "696") (name "Net-(IC65-Pad24)") (class "Default")
      (node (ref "IC65") (pin "24") (pinfunction "24_24") (pintype "passive"))
      (node (ref "IC66") (pin "24") (pinfunction "24_24") (pintype "passive"))
      (node (ref "IC67") (pin "24") (pinfunction "24_24") (pintype "passive"))
      (node (ref "IC68") (pin "24") (pinfunction "24_24") (pintype "passive"))
    )
    (net (code "697") (name "Net-(IC65-Pad25)") (class "Default")
      (node (ref "IC65") (pin "25") (pinfunction "25_25") (pintype "passive"))
      (node (ref "IC66") (pin "25") (pinfunction "25_25") (pintype "passive"))
      (node (ref "IC67") (pin "25") (pinfunction "25_25") (pintype "passive"))
      (node (ref "IC68") (pin "25") (pinfunction "25_25") (pintype "passive"))
    )
    (net (code "698") (name "Net-(IC65-Pad26)") (class "Default")
      (node (ref "IC65") (pin "26") (pinfunction "26_26") (pintype "passive"))
      (node (ref "IC66") (pin "26") (pinfunction "26_26") (pintype "passive"))
      (node (ref "IC67") (pin "26") (pinfunction "26_26") (pintype "passive"))
      (node (ref "IC68") (pin "26") (pinfunction "26_26") (pintype "passive"))
    )
    (net (code "699") (name "Net-(IC65-Pad27)") (class "Default")
      (node (ref "IC65") (pin "27") (pinfunction "27_27") (pintype "passive"))
      (node (ref "IC66") (pin "27") (pinfunction "27_27") (pintype "passive"))
      (node (ref "IC67") (pin "27") (pinfunction "27_27") (pintype "passive"))
      (node (ref "IC68") (pin "27") (pinfunction "27_27") (pintype "passive"))
    )
    (net (code "700") (name "Net-(IC65-Pad28)") (class "Default")
      (node (ref "IC65") (pin "28") (pinfunction "28_28") (pintype "passive"))
      (node (ref "IC66") (pin "28") (pinfunction "28_28") (pintype "passive"))
      (node (ref "IC67") (pin "28") (pinfunction "28_28") (pintype "passive"))
      (node (ref "IC68") (pin "28") (pinfunction "28_28") (pintype "passive"))
    )
    (net (code "701") (name "Net-(IC65-Pad29)") (class "Default")
      (node (ref "IC65") (pin "29") (pinfunction "29_29") (pintype "passive"))
      (node (ref "IC66") (pin "29") (pinfunction "29_29") (pintype "passive"))
      (node (ref "IC67") (pin "29") (pinfunction "29_29") (pintype "passive"))
      (node (ref "IC68") (pin "29") (pinfunction "29_29") (pintype "passive"))
    )
    (net (code "702") (name "Net-(IC65-Pad30)") (class "Default")
      (node (ref "IC65") (pin "30") (pinfunction "30_30") (pintype "passive"))
      (node (ref "IC66") (pin "30") (pinfunction "30_30") (pintype "passive"))
      (node (ref "IC67") (pin "30") (pinfunction "30_30") (pintype "passive"))
      (node (ref "IC68") (pin "30") (pinfunction "30_30") (pintype "passive"))
    )
    (net (code "703") (name "Net-(IC65-Pad31)") (class "Default")
      (node (ref "IC65") (pin "31") (pinfunction "31_31") (pintype "passive"))
      (node (ref "IC66") (pin "31") (pinfunction "31_31") (pintype "passive"))
      (node (ref "IC67") (pin "31") (pinfunction "31_31") (pintype "passive"))
      (node (ref "IC68") (pin "31") (pinfunction "31_31") (pintype "passive"))
    )
    (net (code "704") (name "Net-(IC65-Pad32)") (class "Default")
      (node (ref "IC65") (pin "32") (pinfunction "32_32") (pintype "passive"))
      (node (ref "IC66") (pin "32") (pinfunction "32_32") (pintype "passive"))
      (node (ref "IC67") (pin "32") (pinfunction "32_32") (pintype "passive"))
      (node (ref "IC68") (pin "32") (pinfunction "32_32") (pintype "passive"))
    )
    (net (code "705") (name "Net-(IC65-Pad33)") (class "Default")
      (node (ref "IC65") (pin "33") (pinfunction "33_33") (pintype "passive"))
      (node (ref "IC66") (pin "33") (pinfunction "33_33") (pintype "passive"))
      (node (ref "IC67") (pin "33") (pinfunction "33_33") (pintype "passive"))
      (node (ref "IC68") (pin "33") (pinfunction "33_33") (pintype "passive"))
    )
    (net (code "706") (name "Net-(IC65-Pad34)") (class "Default")
      (node (ref "IC65") (pin "34") (pinfunction "34_34") (pintype "passive"))
      (node (ref "IC66") (pin "34") (pinfunction "34_34") (pintype "passive"))
      (node (ref "IC67") (pin "34") (pinfunction "34_34") (pintype "passive"))
      (node (ref "IC68") (pin "34") (pinfunction "34_34") (pintype "passive"))
    )
    (net (code "707") (name "Net-(IC65-Pad35)") (class "Default")
      (node (ref "IC65") (pin "35") (pinfunction "35_35") (pintype "passive"))
      (node (ref "IC66") (pin "35") (pinfunction "35_35") (pintype "passive"))
      (node (ref "IC67") (pin "35") (pinfunction "35_35") (pintype "passive"))
      (node (ref "IC68") (pin "35") (pinfunction "35_35") (pintype "passive"))
    )
    (net (code "708") (name "Net-(IC65-Pad36)") (class "Default")
      (node (ref "IC65") (pin "36") (pinfunction "36_36") (pintype "passive"))
      (node (ref "IC66") (pin "36") (pinfunction "36_36") (pintype "passive"))
      (node (ref "IC67") (pin "36") (pinfunction "36_36") (pintype "passive"))
      (node (ref "IC68") (pin "36") (pinfunction "36_36") (pintype "passive"))
    )
    (net (code "709") (name "Net-(IC65-Pad37)") (class "Default")
      (node (ref "IC65") (pin "37") (pinfunction "37_37") (pintype "passive"))
      (node (ref "IC66") (pin "37") (pinfunction "37_37") (pintype "passive"))
      (node (ref "IC67") (pin "37") (pinfunction "37_37") (pintype "passive"))
      (node (ref "IC68") (pin "37") (pinfunction "37_37") (pintype "passive"))
    )
    (net (code "710") (name "Net-(IC65-Pad38)") (class "Default")
      (node (ref "IC65") (pin "38") (pinfunction "38_38") (pintype "passive"))
      (node (ref "IC66") (pin "38") (pinfunction "38_38") (pintype "passive"))
      (node (ref "IC67") (pin "38") (pinfunction "38_38") (pintype "passive"))
      (node (ref "IC68") (pin "38") (pinfunction "38_38") (pintype "passive"))
    )
    (net (code "711") (name "Net-(IC65-Pad39)") (class "Default")
      (node (ref "IC65") (pin "39") (pinfunction "39_39") (pintype "passive"))
      (node (ref "IC66") (pin "39") (pinfunction "39_39") (pintype "passive"))
      (node (ref "IC67") (pin "39") (pinfunction "39_39") (pintype "passive"))
      (node (ref "IC68") (pin "39") (pinfunction "39_39") (pintype "passive"))
    )
    (net (code "712") (name "Net-(IC65-Pad40)") (class "Default")
      (node (ref "IC65") (pin "40") (pinfunction "40_40") (pintype "passive"))
      (node (ref "IC66") (pin "40") (pinfunction "40_40") (pintype "passive"))
      (node (ref "IC67") (pin "40") (pinfunction "40_40") (pintype "passive"))
      (node (ref "IC68") (pin "40") (pinfunction "40_40") (pintype "passive"))
    )
    (net (code "713") (name "Net-(IC65-Pad41)") (class "Default")
      (node (ref "IC65") (pin "41") (pinfunction "41_41") (pintype "passive"))
      (node (ref "IC66") (pin "41") (pinfunction "41_41") (pintype "passive"))
      (node (ref "IC67") (pin "41") (pinfunction "41_41") (pintype "passive"))
      (node (ref "IC68") (pin "41") (pinfunction "41_41") (pintype "passive"))
    )
    (net (code "714") (name "Net-(IC65-Pad42)") (class "Default")
      (node (ref "IC65") (pin "42") (pinfunction "42_42") (pintype "passive"))
      (node (ref "IC66") (pin "42") (pinfunction "42_42") (pintype "passive"))
      (node (ref "IC67") (pin "42") (pinfunction "42_42") (pintype "passive"))
      (node (ref "IC68") (pin "42") (pinfunction "42_42") (pintype "passive"))
    )
    (net (code "715") (name "Net-(IC69-Pad1)") (class "Default")
      (node (ref "IC69") (pin "1") (pinfunction "1_1") (pintype "passive"))
      (node (ref "IC70") (pin "1") (pinfunction "1_1") (pintype "passive"))
      (node (ref "IC71") (pin "1") (pinfunction "1_1") (pintype "passive"))
      (node (ref "IC72") (pin "1") (pinfunction "1_1") (pintype "passive"))
    )
    (net (code "716") (name "Net-(IC69-Pad2)") (class "Default")
      (node (ref "IC69") (pin "2") (pinfunction "2_2") (pintype "passive"))
      (node (ref "IC70") (pin "2") (pinfunction "2_2") (pintype "passive"))
      (node (ref "IC71") (pin "2") (pinfunction "2_2") (pintype "passive"))
      (node (ref "IC72") (pin "2") (pinfunction "2_2") (pintype "passive"))
    )
    (net (code "717") (name "Net-(IC69-Pad3)") (class "Default")
      (node (ref "IC69") (pin "3") (pinfunction "3_3") (pintype "passive"))
      (node (ref "IC70") (pin "3") (pinfunction "3_3") (pintype "passive"))
      (node (ref "IC71") (pin "3") (pinfunction "3_3") (pintype "passive"))
      (node (ref "IC72") (pin "3") (pinfunction "3_3") (pintype "passive"))
    )
    (net (code "718") (name "Net-(IC69-Pad4)") (class "Default")
      (node (ref "IC69") (pin "4") (pinfunction "4_4") (pintype "passive"))
      (node (ref "IC70") (pin "4") (pinfunction "4_4") (pintype "passive"))
      (node (ref "IC71") (pin "4") (pinfunction "4_4") (pintype "passive"))
      (node (ref "IC72") (pin "4") (pinfunction "4_4") (pintype "passive"))
    )
    (net (code "719") (name "Net-(IC69-Pad5)") (class "Default")
      (node (ref "IC69") (pin "5") (pinfunction "5_5") (pintype "passive"))
      (node (ref "IC70") (pin "5") (pinfunction "5_5") (pintype "passive"))
      (node (ref "IC71") (pin "5") (pinfunction "5_5") (pintype "passive"))
      (node (ref "IC72") (pin "5") (pinfunction "5_5") (pintype "passive"))
    )
    (net (code "720") (name "Net-(IC69-Pad6)") (class "Default")
      (node (ref "IC69") (pin "6") (pinfunction "6_6") (pintype "passive"))
      (node (ref "IC70") (pin "6") (pinfunction "6_6") (pintype "passive"))
      (node (ref "IC71") (pin "6") (pinfunction "6_6") (pintype "passive"))
      (node (ref "IC72") (pin "6") (pinfunction "6_6") (pintype "passive"))
    )
    (net (code "721") (name "Net-(IC69-Pad7)") (class "Default")
      (node (ref "IC69") (pin "7") (pinfunction "7_7") (pintype "passive"))
      (node (ref "IC70") (pin "7") (pinfunction "7_7") (pintype "passive"))
      (node (ref "IC71") (pin "7") (pinfunction "7_7") (pintype "passive"))
      (node (ref "IC72") (pin "7") (pinfunction "7_7") (pintype "passive"))
    )
    (net (code "722") (name "Net-(IC69-Pad8)") (class "Default")
      (node (ref "IC69") (pin "8") (pinfunction "8_8") (pintype "passive"))
      (node (ref "IC70") (pin "8") (pinfunction "8_8") (pintype "passive"))
      (node (ref "IC71") (pin "8") (pinfunction "8_8") (pintype "passive"))
      (node (ref "IC72") (pin "8") (pinfunction "8_8") (pintype "passive"))
    )
    (net (code "723") (name "Net-(IC69-Pad9)") (class "Default")
      (node (ref "IC69") (pin "9") (pinfunction "9_9") (pintype "passive"))
      (node (ref "IC70") (pin "9") (pinfunction "9_9") (pintype "passive"))
      (node (ref "IC71") (pin "9") (pinfunction "9_9") (pintype "passive"))
      (node (ref "IC72") (pin "9") (pinfunction "9_9") (pintype "passive"))
    )
    (net (code "724") (name "Net-(IC69-Pad10)") (class "Default")
      (node (ref "IC69") (pin "10") (pinfunction "10_10") (pintype "passive"))
      (node (ref "IC70") (pin "10") (pinfunction "10_10") (pintype "passive"))
      (node (ref "IC71") (pin "10") (pinfunction "10_10") (pintype "passive"))
      (node (ref "IC72") (pin "10") (pinfunction "10_10") (pintype "passive"))
    )
    (net (code "725") (name "Net-(IC69-Pad11)") (class "Default")
      (node (ref "IC69") (pin "11") (pinfunction "11_11") (pintype "passive"))
      (node (ref "IC70") (pin "11") (pinfunction "11_11") (pintype "passive"))
      (node (ref "IC71") (pin "11") (pinfunction "11_11") (pintype "passive"))
      (node (ref "IC72") (pin "11") (pinfunction "11_11") (pintype "passive"))
    )
    (net (code "726") (name "Net-(IC69-Pad12)") (class "Default")
      (node (ref "IC69") (pin "12") (pinfunction "12_12") (pintype "passive"))
      (node (ref "IC70") (pin "12") (pinfunction "12_12") (pintype "passive"))
      (node (ref "IC71") (pin "12") (pinfunction "12_12") (pintype "passive"))
      (node (ref "IC72") (pin "12") (pinfunction "12_12") (pintype "passive"))
    )
    (net (code "727") (name "Net-(IC69-Pad13)") (class "Default")
      (node (ref "IC69") (pin "13") (pinfunction "13_13") (pintype "passive"))
      (node (ref "IC70") (pin "13") (pinfunction "13_13") (pintype "passive"))
      (node (ref "IC71") (pin "13") (pinfunction "13_13") (pintype "passive"))
      (node (ref "IC72") (pin "13") (pinfunction "13_13") (pintype "passive"))
    )
    (net (code "728") (name "Net-(IC69-Pad14)") (class "Default")
      (node (ref "IC69") (pin "14") (pinfunction "14_14") (pintype "passive"))
      (node (ref "IC70") (pin "14") (pinfunction "14_14") (pintype "passive"))
      (node (ref "IC71") (pin "14") (pinfunction "14_14") (pintype "passive"))
      (node (ref "IC72") (pin "14") (pinfunction "14_14") (pintype "passive"))
    )
    (net (code "729") (name "Net-(IC69-Pad15)") (class "Default")
      (node (ref "IC69") (pin "15") (pinfunction "15_15") (pintype "passive"))
      (node (ref "IC70") (pin "15") (pinfunction "15_15") (pintype "passive"))
      (node (ref "IC71") (pin "15") (pinfunction "15_15") (pintype "passive"))
      (node (ref "IC72") (pin "15") (pinfunction "15_15") (pintype "passive"))
    )
    (net (code "730") (name "Net-(IC69-Pad16)") (class "Default")
      (node (ref "IC69") (pin "16") (pinfunction "16_16") (pintype "passive"))
      (node (ref "IC70") (pin "16") (pinfunction "16_16") (pintype "passive"))
      (node (ref "IC71") (pin "16") (pinfunction "16_16") (pintype "passive"))
      (node (ref "IC72") (pin "16") (pinfunction "16_16") (pintype "passive"))
    )
    (net (code "731") (name "Net-(IC69-Pad17)") (class "Default")
      (node (ref "IC69") (pin "17") (pinfunction "17_17") (pintype "passive"))
      (node (ref "IC70") (pin "17") (pinfunction "17_17") (pintype "passive"))
      (node (ref "IC71") (pin "17") (pinfunction "17_17") (pintype "passive"))
      (node (ref "IC72") (pin "17") (pinfunction "17_17") (pintype "passive"))
    )
    (net (code "732") (name "Net-(IC69-Pad18)") (class "Default")
      (node (ref "IC69") (pin "18") (pinfunction "18_18") (pintype "passive"))
      (node (ref "IC70") (pin "18") (pinfunction "18_18") (pintype "passive"))
      (node (ref "IC71") (pin "18") (pinfunction "18_18") (pintype "passive"))
      (node (ref "IC72") (pin "18") (pinfunction "18_18") (pintype "passive"))
    )
    (net (code "733") (name "Net-(IC69-Pad19)") (class "Default")
      (node (ref "IC69") (pin "19") (pinfunction "19_19") (pintype "passive"))
      (node (ref "IC70") (pin "19") (pinfunction "19_19") (pintype "passive"))
      (node (ref "IC71") (pin "19") (pinfunction "19_19") (pintype "passive"))
      (node (ref "IC72") (pin "19") (pinfunction "19_19") (pintype "passive"))
    )
    (net (code "734") (name "Net-(IC69-Pad20)") (class "Default")
      (node (ref "IC69") (pin "20") (pinfunction "20_20") (pintype "passive"))
      (node (ref "IC70") (pin "20") (pinfunction "20_20") (pintype "passive"))
      (node (ref "IC71") (pin "20") (pinfunction "20_20") (pintype "passive"))
      (node (ref "IC72") (pin "20") (pinfunction "20_20") (pintype "passive"))
    )
    (net (code "735") (name "Net-(IC69-Pad21)") (class "Default")
      (node (ref "IC69") (pin "21") (pinfunction "21_21") (pintype "passive"))
      (node (ref "IC70") (pin "21") (pinfunction "21_21") (pintype "passive"))
      (node (ref "IC71") (pin "21") (pinfunction "21_21") (pintype "passive"))
      (node (ref "IC72") (pin "21") (pinfunction "21_21") (pintype "passive"))
    )
    (net (code "736") (name "Net-(IC69-Pad22)") (class "Default")
      (node (ref "IC69") (pin "22") (pinfunction "22_22") (pintype "passive"))
      (node (ref "IC70") (pin "22") (pinfunction "22_22") (pintype "passive"))
      (node (ref "IC71") (pin "22") (pinfunction "22_22") (pintype "passive"))
      (node (ref "IC72") (pin "22") (pinfunction "22_22") (pintype "passive"))
    )
    (net (code "737") (name "Net-(IC69-Pad23)") (class "Default")
      (node (ref "IC69") (pin "23") (pinfunction "23_23") (pintype "passive"))
      (node (ref "IC70") (pin "23") (pinfunction "23_23") (pintype "passive"))
      (node (ref "IC71") (pin "23") (pinfunction "23_23") (pintype "passive"))
      (node (ref "IC72") (pin "23") (pinfunction "23_23") (pintype "passive"))
    )
    (net (code "738") (name "Net-(IC69-Pad24)") (class "Default")
      (node (ref "IC69") (pin "24") (pinfunction "24_24") (pintype "passive"))
      (node (ref "IC70") (pin "24") (pinfunction "24_24") (pintype "passive"))
      (node (ref "IC71") (pin "24") (pinfunction "24_24") (pintype "passive"))
      (node (ref "IC72") (pin "24") (pinfunction "24_24") (pintype "passive"))
    )
    (net (code "739") (name "Net-(IC69-Pad25)") (class "Default")
      (node (ref "IC69") (pin "25") (pinfunction "25_25") (pintype "passive"))
      (node (ref "IC70") (pin "25") (pinfunction "25_25") (pintype "passive"))
      (node (ref "IC71") (pin "25") (pinfunction "25_25") (pintype "passive"))
      (node (ref "IC72") (pin "25") (pinfunction "25_25") (pintype "passive"))
    )
    (net (code "740") (name "Net-(IC69-Pad26)") (class "Default")
      (node (ref "IC69") (pin "26") (pinfunction "26_26") (pintype "passive"))
      (node (ref "IC70") (pin "26") (pinfunction "26_26") (pintype "passive"))
      (node (ref "IC71") (pin "26") (pinfunction "26_26") (pintype "passive"))
      (node (ref "IC72") (pin "26") (pinfunction "26_26") (pintype "passive"))
    )
    (net (code "741") (name "Net-(IC69-Pad27)") (class "Default")
      (node (ref "IC69") (pin "27") (pinfunction "27_27") (pintype "passive"))
      (node (ref "IC70") (pin "27") (pinfunction "27_27") (pintype "passive"))
      (node (ref "IC71") (pin "27") (pinfunction "27_27") (pintype "passive"))
      (node (ref "IC72") (pin "27") (pinfunction "27_27") (pintype "passive"))
    )
    (net (code "742") (name "Net-(IC69-Pad28)") (class "Default")
      (node (ref "IC69") (pin "28") (pinfunction "28_28") (pintype "passive"))
      (node (ref "IC70") (pin "28") (pinfunction "28_28") (pintype "passive"))
      (node (ref "IC71") (pin "28") (pinfunction "28_28") (pintype "passive"))
      (node (ref "IC72") (pin "28") (pinfunction "28_28") (pintype "passive"))
    )
    (net (code "743") (name "Net-(IC69-Pad29)") (class "Default")
      (node (ref "IC69") (pin "29") (pinfunction "29_29") (pintype "passive"))
      (node (ref "IC70") (pin "29") (pinfunction "29_29") (pintype "passive"))
      (node (ref "IC71") (pin "29") (pinfunction "29_29") (pintype "passive"))
      (node (ref "IC72") (pin "29") (pinfunction "29_29") (pintype "passive"))
    )
    (net (code "744") (name "Net-(IC69-Pad30)") (class "Default")
      (node (ref "IC69") (pin "30") (pinfunction "30_30") (pintype "passive"))
      (node (ref "IC70") (pin "30") (pinfunction "30_30") (pintype "passive"))
      (node (ref "IC71") (pin "30") (pinfunction "30_30") (pintype "passive"))
      (node (ref "IC72") (pin "30") (pinfunction "30_30") (pintype "passive"))
    )
    (net (code "745") (name "Net-(IC69-Pad31)") (class "Default")
      (node (ref "IC69") (pin "31") (pinfunction "31_31") (pintype "passive"))
      (node (ref "IC70") (pin "31") (pinfunction "31_31") (pintype "passive"))
      (node (ref "IC71") (pin "31") (pinfunction "31_31") (pintype "passive"))
      (node (ref "IC72") (pin "31") (pinfunction "31_31") (pintype "passive"))
    )
    (net (code "746") (name "Net-(IC69-Pad32)") (class "Default")
      (node (ref "IC69") (pin "32") (pinfunction "32_32") (pintype "passive"))
      (node (ref "IC70") (pin "32") (pinfunction "32_32") (pintype "passive"))
      (node (ref "IC71") (pin "32") (pinfunction "32_32") (pintype "passive"))
      (node (ref "IC72") (pin "32") (pinfunction "32_32") (pintype "passive"))
    )
    (net (code "747") (name "Net-(IC69-Pad33)") (class "Default")
      (node (ref "IC69") (pin "33") (pinfunction "33_33") (pintype "passive"))
      (node (ref "IC70") (pin "33") (pinfunction "33_33") (pintype "passive"))
      (node (ref "IC71") (pin "33") (pinfunction "33_33") (pintype "passive"))
      (node (ref "IC72") (pin "33") (pinfunction "33_33") (pintype "passive"))
    )
    (net (code "748") (name "Net-(IC69-Pad34)") (class "Default")
      (node (ref "IC69") (pin "34") (pinfunction "34_34") (pintype "passive"))
      (node (ref "IC70") (pin "34") (pinfunction "34_34") (pintype "passive"))
      (node (ref "IC71") (pin "34") (pinfunction "34_34") (pintype "passive"))
      (node (ref "IC72") (pin "34") (pinfunction "34_34") (pintype "passive"))
    )
    (net (code "749") (name "Net-(IC69-Pad35)") (class "Default")
      (node (ref "IC69") (pin "35") (pinfunction "35_35") (pintype "passive"))
      (node (ref "IC70") (pin "35") (pinfunction "35_35") (pintype "passive"))
      (node (ref "IC71") (pin "35") (pinfunction "35_35") (pintype "passive"))
      (node (ref "IC72") (pin "35") (pinfunction "35_35") (pintype "passive"))
    )
    (net (code "750") (name "Net-(IC69-Pad36)") (class "Default")
      (node (ref "IC69") (pin "36") (pinfunction "36_36") (pintype "passive"))
      (node (ref "IC70") (pin "36") (pinfunction "36_36") (pintype "passive"))
      (node (ref "IC71") (pin "36") (pinfunction "36_36") (pintype "passive"))
      (node (ref "IC72") (pin "36") (pinfunction "36_36") (pintype "passive"))
    )
    (net (code "751") (name "Net-(IC69-Pad37)") (class "Default")
      (node (ref "IC69") (pin "37") (pinfunction "37_37") (pintype "passive"))
      (node (ref "IC70") (pin "37") (pinfunction "37_37") (pintype "passive"))
      (node (ref "IC71") (pin "37") (pinfunction "37_37") (pintype "passive"))
      (node (ref "IC72") (pin "37") (pinfunction "37_37") (pintype "passive"))
    )
    (net (code "752") (name "Net-(IC69-Pad38)") (class "Default")
      (node (ref "IC69") (pin "38") (pinfunction "38_38") (pintype "passive"))
      (node (ref "IC70") (pin "38") (pinfunction "38_38") (pintype "passive"))
      (node (ref "IC71") (pin "38") (pinfunction "38_38") (pintype "passive"))
      (node (ref "IC72") (pin "38") (pinfunction "38_38") (pintype "passive"))
    )
    (net (code "753") (name "Net-(IC69-Pad39)") (class "Default")
      (node (ref "IC69") (pin "39") (pinfunction "39_39") (pintype "passive"))
      (node (ref "IC70") (pin "39") (pinfunction "39_39") (pintype "passive"))
      (node (ref "IC71") (pin "39") (pinfunction "39_39") (pintype "passive"))
      (node (ref "IC72") (pin "39") (pinfunction "39_39") (pintype "passive"))
    )
    (net (code "754") (name "Net-(IC69-Pad40)") (class "Default")
      (node (ref "IC69") (pin "40") (pinfunction "40_40") (pintype "passive"))
      (node (ref "IC70") (pin "40") (pinfunction "40_40") (pintype "passive"))
      (node (ref "IC71") (pin "40") (pinfunction "40_40") (pintype "passive"))
      (node (ref "IC72") (pin "40") (pinfunction "40_40") (pintype "passive"))
    )
    (net (code "755") (name "Net-(IC69-Pad41)") (class "Default")
      (node (ref "IC69") (pin "41") (pinfunction "41_41") (pintype "passive"))
      (node (ref "IC70") (pin "41") (pinfunction "41_41") (pintype "passive"))
      (node (ref "IC71") (pin "41") (pinfunction "41_41") (pintype "passive"))
      (node (ref "IC72") (pin "41") (pinfunction "41_41") (pintype "passive"))
    )
    (net (code "756") (name "Net-(IC69-Pad42)") (class "Default")
      (node (ref "IC69") (pin "42") (pinfunction "42_42") (pintype "passive"))
      (node (ref "IC70") (pin "42") (pinfunction "42_42") (pintype "passive"))
      (node (ref "IC71") (pin "42") (pinfunction "42_42") (pintype "passive"))
      (node (ref "IC72") (pin "42") (pinfunction "42_42") (pintype "passive"))
    )
    (net (code "757") (name "Net-(IC73-Pad1)") (class "Default")
      (node (ref "IC73") (pin "1") (pinfunction "1_1") (pintype "passive"))
      (node (ref "IC74") (pin "1") (pinfunction "1_1") (pintype "passive"))
      (node (ref "IC75") (pin "1") (pinfunction "1_1") (pintype "passive"))
      (node (ref "IC76") (pin "1") (pinfunction "1_1") (pintype "passive"))
    )
    (net (code "758") (name "Net-(IC73-Pad2)") (class "Default")
      (node (ref "IC73") (pin "2") (pinfunction "2_2") (pintype "passive"))
      (node (ref "IC74") (pin "2") (pinfunction "2_2") (pintype "passive"))
      (node (ref "IC75") (pin "2") (pinfunction "2_2") (pintype "passive"))
      (node (ref "IC76") (pin "2") (pinfunction "2_2") (pintype "passive"))
    )
    (net (code "759") (name "Net-(IC73-Pad3)") (class "Default")
      (node (ref "IC73") (pin "3") (pinfunction "3_3") (pintype "passive"))
      (node (ref "IC74") (pin "3") (pinfunction "3_3") (pintype "passive"))
      (node (ref "IC75") (pin "3") (pinfunction "3_3") (pintype "passive"))
      (node (ref "IC76") (pin "3") (pinfunction "3_3") (pintype "passive"))
    )
    (net (code "760") (name "Net-(IC73-Pad4)") (class "Default")
      (node (ref "IC73") (pin "4") (pinfunction "4_4") (pintype "passive"))
      (node (ref "IC74") (pin "4") (pinfunction "4_4") (pintype "passive"))
      (node (ref "IC75") (pin "4") (pinfunction "4_4") (pintype "passive"))
      (node (ref "IC76") (pin "4") (pinfunction "4_4") (pintype "passive"))
    )
    (net (code "761") (name "Net-(IC73-Pad5)") (class "Default")
      (node (ref "IC73") (pin "5") (pinfunction "5_5") (pintype "passive"))
      (node (ref "IC74") (pin "5") (pinfunction "5_5") (pintype "passive"))
      (node (ref "IC75") (pin "5") (pinfunction "5_5") (pintype "passive"))
      (node (ref "IC76") (pin "5") (pinfunction "5_5") (pintype "passive"))
    )
    (net (code "762") (name "Net-(IC73-Pad6)") (class "Default")
      (node (ref "IC73") (pin "6") (pinfunction "6_6") (pintype "passive"))
      (node (ref "IC74") (pin "6") (pinfunction "6_6") (pintype "passive"))
      (node (ref "IC75") (pin "6") (pinfunction "6_6") (pintype "passive"))
      (node (ref "IC76") (pin "6") (pinfunction "6_6") (pintype "passive"))
    )
    (net (code "763") (name "Net-(IC73-Pad7)") (class "Default")
      (node (ref "IC73") (pin "7") (pinfunction "7_7") (pintype "passive"))
      (node (ref "IC74") (pin "7") (pinfunction "7_7") (pintype "passive"))
      (node (ref "IC75") (pin "7") (pinfunction "7_7") (pintype "passive"))
      (node (ref "IC76") (pin "7") (pinfunction "7_7") (pintype "passive"))
    )
    (net (code "764") (name "Net-(IC73-Pad8)") (class "Default")
      (node (ref "IC73") (pin "8") (pinfunction "8_8") (pintype "passive"))
      (node (ref "IC74") (pin "8") (pinfunction "8_8") (pintype "passive"))
      (node (ref "IC75") (pin "8") (pinfunction "8_8") (pintype "passive"))
      (node (ref "IC76") (pin "8") (pinfunction "8_8") (pintype "passive"))
    )
    (net (code "765") (name "Net-(IC73-Pad9)") (class "Default")
      (node (ref "IC73") (pin "9") (pinfunction "9_9") (pintype "passive"))
      (node (ref "IC74") (pin "9") (pinfunction "9_9") (pintype "passive"))
      (node (ref "IC75") (pin "9") (pinfunction "9_9") (pintype "passive"))
      (node (ref "IC76") (pin "9") (pinfunction "9_9") (pintype "passive"))
    )
    (net (code "766") (name "Net-(IC73-Pad10)") (class "Default")
      (node (ref "IC73") (pin "10") (pinfunction "10_10") (pintype "passive"))
      (node (ref "IC74") (pin "10") (pinfunction "10_10") (pintype "passive"))
      (node (ref "IC75") (pin "10") (pinfunction "10_10") (pintype "passive"))
      (node (ref "IC76") (pin "10") (pinfunction "10_10") (pintype "passive"))
    )
    (net (code "767") (name "Net-(IC73-Pad11)") (class "Default")
      (node (ref "IC73") (pin "11") (pinfunction "11_11") (pintype "passive"))
      (node (ref "IC74") (pin "11") (pinfunction "11_11") (pintype "passive"))
      (node (ref "IC75") (pin "11") (pinfunction "11_11") (pintype "passive"))
      (node (ref "IC76") (pin "11") (pinfunction "11_11") (pintype "passive"))
    )
    (net (code "768") (name "Net-(IC73-Pad12)") (class "Default")
      (node (ref "IC73") (pin "12") (pinfunction "12_12") (pintype "passive"))
      (node (ref "IC74") (pin "12") (pinfunction "12_12") (pintype "passive"))
      (node (ref "IC75") (pin "12") (pinfunction "12_12") (pintype "passive"))
      (node (ref "IC76") (pin "12") (pinfunction "12_12") (pintype "passive"))
    )
    (net (code "769") (name "Net-(IC73-Pad13)") (class "Default")
      (node (ref "IC73") (pin "13") (pinfunction "13_13") (pintype "passive"))
      (node (ref "IC74") (pin "13") (pinfunction "13_13") (pintype "passive"))
      (node (ref "IC75") (pin "13") (pinfunction "13_13") (pintype "passive"))
      (node (ref "IC76") (pin "13") (pinfunction "13_13") (pintype "passive"))
    )
    (net (code "770") (name "Net-(IC73-Pad14)") (class "Default")
      (node (ref "IC73") (pin "14") (pinfunction "14_14") (pintype "passive"))
      (node (ref "IC74") (pin "14") (pinfunction "14_14") (pintype "passive"))
      (node (ref "IC75") (pin "14") (pinfunction "14_14") (pintype "passive"))
      (node (ref "IC76") (pin "14") (pinfunction "14_14") (pintype "passive"))
    )
    (net (code "771") (name "Net-(IC73-Pad15)") (class "Default")
      (node (ref "IC73") (pin "15") (pinfunction "15_15") (pintype "passive"))
      (node (ref "IC74") (pin "15") (pinfunction "15_15") (pintype "passive"))
      (node (ref "IC75") (pin "15") (pinfunction "15_15") (pintype "passive"))
      (node (ref "IC76") (pin "15") (pinfunction "15_15") (pintype "passive"))
    )
    (net (code "772") (name "Net-(IC73-Pad16)") (class "Default")
      (node (ref "IC73") (pin "16") (pinfunction "16_16") (pintype "passive"))
      (node (ref "IC74") (pin "16") (pinfunction "16_16") (pintype "passive"))
      (node (ref "IC75") (pin "16") (pinfunction "16_16") (pintype "passive"))
      (node (ref "IC76") (pin "16") (pinfunction "16_16") (pintype "passive"))
    )
    (net (code "773") (name "Net-(IC73-Pad17)") (class "Default")
      (node (ref "IC73") (pin "17") (pinfunction "17_17") (pintype "passive"))
      (node (ref "IC74") (pin "17") (pinfunction "17_17") (pintype "passive"))
      (node (ref "IC75") (pin "17") (pinfunction "17_17") (pintype "passive"))
      (node (ref "IC76") (pin "17") (pinfunction "17_17") (pintype "passive"))
    )
    (net (code "774") (name "Net-(IC73-Pad18)") (class "Default")
      (node (ref "IC73") (pin "18") (pinfunction "18_18") (pintype "passive"))
      (node (ref "IC74") (pin "18") (pinfunction "18_18") (pintype "passive"))
      (node (ref "IC75") (pin "18") (pinfunction "18_18") (pintype "passive"))
      (node (ref "IC76") (pin "18") (pinfunction "18_18") (pintype "passive"))
    )
    (net (code "775") (name "Net-(IC73-Pad19)") (class "Default")
      (node (ref "IC73") (pin "19") (pinfunction "19_19") (pintype "passive"))
      (node (ref "IC74") (pin "19") (pinfunction "19_19") (pintype "passive"))
      (node (ref "IC75") (pin "19") (pinfunction "19_19") (pintype "passive"))
      (node (ref "IC76") (pin "19") (pinfunction "19_19") (pintype "passive"))
    )
    (net (code "776") (name "Net-(IC73-Pad20)") (class "Default")
      (node (ref "IC73") (pin "20") (pinfunction "20_20") (pintype "passive"))
      (node (ref "IC74") (pin "20") (pinfunction "20_20") (pintype "passive"))
      (node (ref "IC75") (pin "20") (pinfunction "20_20") (pintype "passive"))
      (node (ref "IC76") (pin "20") (pinfunction "20_20") (pintype "passive"))
    )
    (net (code "777") (name "Net-(IC73-Pad21)") (class "Default")
      (node (ref "IC73") (pin "21") (pinfunction "21_21") (pintype "passive"))
      (node (ref "IC74") (pin "21") (pinfunction "21_21") (pintype "passive"))
      (node (ref "IC75") (pin "21") (pinfunction "21_21") (pintype "passive"))
      (node (ref "IC76") (pin "21") (pinfunction "21_21") (pintype "passive"))
    )
    (net (code "778") (name "Net-(IC73-Pad22)") (class "Default")
      (node (ref "IC73") (pin "22") (pinfunction "22_22") (pintype "passive"))
      (node (ref "IC74") (pin "22") (pinfunction "22_22") (pintype "passive"))
      (node (ref "IC75") (pin "22") (pinfunction "22_22") (pintype "passive"))
      (node (ref "IC76") (pin "22") (pinfunction "22_22") (pintype "passive"))
    )
    (net (code "779") (name "Net-(IC73-Pad23)") (class "Default")
      (node (ref "IC73") (pin "23") (pinfunction "23_23") (pintype "passive"))
      (node (ref "IC74") (pin "23") (pinfunction "23_23") (pintype "passive"))
      (node (ref "IC75") (pin "23") (pinfunction "23_23") (pintype "passive"))
      (node (ref "IC76") (pin "23") (pinfunction "23_23") (pintype "passive"))
    )
    (net (code "780") (name "Net-(IC73-Pad24)") (class "Default")
      (node (ref "IC73") (pin "24") (pinfunction "24_24") (pintype "passive"))
      (node (ref "IC74") (pin "24") (pinfunction "24_24") (pintype "passive"))
      (node (ref "IC75") (pin "24") (pinfunction "24_24") (pintype "passive"))
      (node (ref "IC76") (pin "24") (pinfunction "24_24") (pintype "passive"))
    )
    (net (code "781") (name "Net-(IC73-Pad25)") (class "Default")
      (node (ref "IC73") (pin "25") (pinfunction "25_25") (pintype "passive"))
      (node (ref "IC74") (pin "25") (pinfunction "25_25") (pintype "passive"))
      (node (ref "IC75") (pin "25") (pinfunction "25_25") (pintype "passive"))
      (node (ref "IC76") (pin "25") (pinfunction "25_25") (pintype "passive"))
    )
    (net (code "782") (name "Net-(IC73-Pad26)") (class "Default")
      (node (ref "IC73") (pin "26") (pinfunction "26_26") (pintype "passive"))
      (node (ref "IC74") (pin "26") (pinfunction "26_26") (pintype "passive"))
      (node (ref "IC75") (pin "26") (pinfunction "26_26") (pintype "passive"))
      (node (ref "IC76") (pin "26") (pinfunction "26_26") (pintype "passive"))
    )
    (net (code "783") (name "Net-(IC73-Pad27)") (class "Default")
      (node (ref "IC73") (pin "27") (pinfunction "27_27") (pintype "passive"))
      (node (ref "IC74") (pin "27") (pinfunction "27_27") (pintype "passive"))
      (node (ref "IC75") (pin "27") (pinfunction "27_27") (pintype "passive"))
      (node (ref "IC76") (pin "27") (pinfunction "27_27") (pintype "passive"))
    )
    (net (code "784") (name "Net-(IC73-Pad28)") (class "Default")
      (node (ref "IC73") (pin "28") (pinfunction "28_28") (pintype "passive"))
      (node (ref "IC74") (pin "28") (pinfunction "28_28") (pintype "passive"))
      (node (ref "IC75") (pin "28") (pinfunction "28_28") (pintype "passive"))
      (node (ref "IC76") (pin "28") (pinfunction "28_28") (pintype "passive"))
    )
    (net (code "785") (name "Net-(IC73-Pad29)") (class "Default")
      (node (ref "IC73") (pin "29") (pinfunction "29_29") (pintype "passive"))
      (node (ref "IC74") (pin "29") (pinfunction "29_29") (pintype "passive"))
      (node (ref "IC75") (pin "29") (pinfunction "29_29") (pintype "passive"))
      (node (ref "IC76") (pin "29") (pinfunction "29_29") (pintype "passive"))
    )
    (net (code "786") (name "Net-(IC73-Pad30)") (class "Default")
      (node (ref "IC73") (pin "30") (pinfunction "30_30") (pintype "passive"))
      (node (ref "IC74") (pin "30") (pinfunction "30_30") (pintype "passive"))
      (node (ref "IC75") (pin "30") (pinfunction "30_30") (pintype "passive"))
      (node (ref "IC76") (pin "30") (pinfunction "30_30") (pintype "passive"))
    )
    (net (code "787") (name "Net-(IC73-Pad31)") (class "Default")
      (node (ref "IC73") (pin "31") (pinfunction "31_31") (pintype "passive"))
      (node (ref "IC74") (pin "31") (pinfunction "31_31") (pintype "passive"))
      (node (ref "IC75") (pin "31") (pinfunction "31_31") (pintype "passive"))
      (node (ref "IC76") (pin "31") (pinfunction "31_31") (pintype "passive"))
    )
    (net (code "788") (name "Net-(IC73-Pad32)") (class "Default")
      (node (ref "IC73") (pin "32") (pinfunction "32_32") (pintype "passive"))
      (node (ref "IC74") (pin "32") (pinfunction "32_32") (pintype "passive"))
      (node (ref "IC75") (pin "32") (pinfunction "32_32") (pintype "passive"))
      (node (ref "IC76") (pin "32") (pinfunction "32_32") (pintype "passive"))
    )
    (net (code "789") (name "Net-(IC73-Pad33)") (class "Default")
      (node (ref "IC73") (pin "33") (pinfunction "33_33") (pintype "passive"))
      (node (ref "IC74") (pin "33") (pinfunction "33_33") (pintype "passive"))
      (node (ref "IC75") (pin "33") (pinfunction "33_33") (pintype "passive"))
      (node (ref "IC76") (pin "33") (pinfunction "33_33") (pintype "passive"))
    )
    (net (code "790") (name "Net-(IC73-Pad34)") (class "Default")
      (node (ref "IC73") (pin "34") (pinfunction "34_34") (pintype "passive"))
      (node (ref "IC74") (pin "34") (pinfunction "34_34") (pintype "passive"))
      (node (ref "IC75") (pin "34") (pinfunction "34_34") (pintype "passive"))
      (node (ref "IC76") (pin "34") (pinfunction "34_34") (pintype "passive"))
    )
    (net (code "791") (name "Net-(IC73-Pad35)") (class "Default")
      (node (ref "IC73") (pin "35") (pinfunction "35_35") (pintype "passive"))
      (node (ref "IC74") (pin "35") (pinfunction "35_35") (pintype "passive"))
      (node (ref "IC75") (pin "35") (pinfunction "35_35") (pintype "passive"))
      (node (ref "IC76") (pin "35") (pinfunction "35_35") (pintype "passive"))
    )
    (net (code "792") (name "Net-(IC73-Pad36)") (class "Default")
      (node (ref "IC73") (pin "36") (pinfunction "36_36") (pintype "passive"))
      (node (ref "IC74") (pin "36") (pinfunction "36_36") (pintype "passive"))
      (node (ref "IC75") (pin "36") (pinfunction "36_36") (pintype "passive"))
      (node (ref "IC76") (pin "36") (pinfunction "36_36") (pintype "passive"))
    )
    (net (code "793") (name "Net-(IC73-Pad37)") (class "Default")
      (node (ref "IC73") (pin "37") (pinfunction "37_37") (pintype "passive"))
      (node (ref "IC74") (pin "37") (pinfunction "37_37") (pintype "passive"))
      (node (ref "IC75") (pin "37") (pinfunction "37_37") (pintype "passive"))
      (node (ref "IC76") (pin "37") (pinfunction "37_37") (pintype "passive"))
    )
    (net (code "794") (name "Net-(IC73-Pad38)") (class "Default")
      (node (ref "IC73") (pin "38") (pinfunction "38_38") (pintype "passive"))
      (node (ref "IC74") (pin "38") (pinfunction "38_38") (pintype "passive"))
      (node (ref "IC75") (pin "38") (pinfunction "38_38") (pintype "passive"))
      (node (ref "IC76") (pin "38") (pinfunction "38_38") (pintype "passive"))
    )
    (net (code "795") (name "Net-(IC73-Pad39)") (class "Default")
      (node (ref "IC73") (pin "39") (pinfunction "39_39") (pintype "passive"))
      (node (ref "IC74") (pin "39") (pinfunction "39_39") (pintype "passive"))
      (node (ref "IC75") (pin "39") (pinfunction "39_39") (pintype "passive"))
      (node (ref "IC76") (pin "39") (pinfunction "39_39") (pintype "passive"))
    )
    (net (code "796") (name "Net-(IC73-Pad40)") (class "Default")
      (node (ref "IC73") (pin "40") (pinfunction "40_40") (pintype "passive"))
      (node (ref "IC74") (pin "40") (pinfunction "40_40") (pintype "passive"))
      (node (ref "IC75") (pin "40") (pinfunction "40_40") (pintype "passive"))
      (node (ref "IC76") (pin "40") (pinfunction "40_40") (pintype "passive"))
    )
    (net (code "797") (name "Net-(IC73-Pad41)") (class "Default")
      (node (ref "IC73") (pin "41") (pinfunction "41_41") (pintype "passive"))
      (node (ref "IC74") (pin "41") (pinfunction "41_41") (pintype "passive"))
      (node (ref "IC75") (pin "41") (pinfunction "41_41") (pintype "passive"))
      (node (ref "IC76") (pin "41") (pinfunction "41_41") (pintype "passive"))
    )
    (net (code "798") (name "Net-(IC73-Pad42)") (class "Default")
      (node (ref "IC73") (pin "42") (pinfunction "42_42") (pintype "passive"))
      (node (ref "IC74") (pin "42") (pinfunction "42_42") (pintype "passive"))
      (node (ref "IC75") (pin "42") (pinfunction "42_42") (pintype "passive"))
      (node (ref "IC76") (pin "42") (pinfunction "42_42") (pintype "passive"))
    )
    (net (code "799") (name "Net-(IC77-Pad1)") (class "Default")
      (node (ref "IC77") (pin "1") (pinfunction "1_1") (pintype "passive"))
      (node (ref "IC78") (pin "1") (pinfunction "1_1") (pintype "passive"))
      (node (ref "IC79") (pin "1") (pinfunction "1_1") (pintype "passive"))
      (node (ref "IC80") (pin "1") (pinfunction "1_1") (pintype "passive"))
    )
    (net (code "800") (name "Net-(IC77-Pad2)") (class "Default")
      (node (ref "IC77") (pin "2") (pinfunction "2_2") (pintype "passive"))
      (node (ref "IC78") (pin "2") (pinfunction "2_2") (pintype "passive"))
      (node (ref "IC79") (pin "2") (pinfunction "2_2") (pintype "passive"))
      (node (ref "IC80") (pin "2") (pinfunction "2_2") (pintype "passive"))
    )
    (net (code "801") (name "Net-(IC77-Pad3)") (class "Default")
      (node (ref "IC77") (pin "3") (pinfunction "3_3") (pintype "passive"))
      (node (ref "IC78") (pin "3") (pinfunction "3_3") (pintype "passive"))
      (node (ref "IC79") (pin "3") (pinfunction "3_3") (pintype "passive"))
      (node (ref "IC80") (pin "3") (pinfunction "3_3") (pintype "passive"))
    )
    (net (code "802") (name "Net-(IC77-Pad4)") (class "Default")
      (node (ref "IC77") (pin "4") (pinfunction "4_4") (pintype "passive"))
      (node (ref "IC78") (pin "4") (pinfunction "4_4") (pintype "passive"))
      (node (ref "IC79") (pin "4") (pinfunction "4_4") (pintype "passive"))
      (node (ref "IC80") (pin "4") (pinfunction "4_4") (pintype "passive"))
    )
    (net (code "803") (name "Net-(IC77-Pad5)") (class "Default")
      (node (ref "IC77") (pin "5") (pinfunction "5_5") (pintype "passive"))
      (node (ref "IC78") (pin "5") (pinfunction "5_5") (pintype "passive"))
      (node (ref "IC79") (pin "5") (pinfunction "5_5") (pintype "passive"))
      (node (ref "IC80") (pin "5") (pinfunction "5_5") (pintype "passive"))
    )
    (net (code "804") (name "Net-(IC77-Pad6)") (class "Default")
      (node (ref "IC77") (pin "6") (pinfunction "6_6") (pintype "passive"))
      (node (ref "IC78") (pin "6") (pinfunction "6_6") (pintype "passive"))
      (node (ref "IC79") (pin "6") (pinfunction "6_6") (pintype "passive"))
      (node (ref "IC80") (pin "6") (pinfunction "6_6") (pintype "passive"))
    )
    (net (code "805") (name "Net-(IC77-Pad7)") (class "Default")
      (node (ref "IC77") (pin "7") (pinfunction "7_7") (pintype "passive"))
      (node (ref "IC78") (pin "7") (pinfunction "7_7") (pintype "passive"))
      (node (ref "IC79") (pin "7") (pinfunction "7_7") (pintype "passive"))
      (node (ref "IC80") (pin "7") (pinfunction "7_7") (pintype "passive"))
    )
    (net (code "806") (name "Net-(IC77-Pad8)") (class "Default")
      (node (ref "IC77") (pin "8") (pinfunction "8_8") (pintype "passive"))
      (node (ref "IC78") (pin "8") (pinfunction "8_8") (pintype "passive"))
      (node (ref "IC79") (pin "8") (pinfunction "8_8") (pintype "passive"))
      (node (ref "IC80") (pin "8") (pinfunction "8_8") (pintype "passive"))
    )
    (net (code "807") (name "Net-(IC77-Pad9)") (class "Default")
      (node (ref "IC77") (pin "9") (pinfunction "9_9") (pintype "passive"))
      (node (ref "IC78") (pin "9") (pinfunction "9_9") (pintype "passive"))
      (node (ref "IC79") (pin "9") (pinfunction "9_9") (pintype "passive"))
      (node (ref "IC80") (pin "9") (pinfunction "9_9") (pintype "passive"))
    )
    (net (code "808") (name "Net-(IC77-Pad10)") (class "Default")
      (node (ref "IC77") (pin "10") (pinfunction "10_10") (pintype "passive"))
      (node (ref "IC78") (pin "10") (pinfunction "10_10") (pintype "passive"))
      (node (ref "IC79") (pin "10") (pinfunction "10_10") (pintype "passive"))
      (node (ref "IC80") (pin "10") (pinfunction "10_10") (pintype "passive"))
    )
    (net (code "809") (name "Net-(IC77-Pad11)") (class "Default")
      (node (ref "IC77") (pin "11") (pinfunction "11_11") (pintype "passive"))
      (node (ref "IC78") (pin "11") (pinfunction "11_11") (pintype "passive"))
      (node (ref "IC79") (pin "11") (pinfunction "11_11") (pintype "passive"))
      (node (ref "IC80") (pin "11") (pinfunction "11_11") (pintype "passive"))
    )
    (net (code "810") (name "Net-(IC77-Pad12)") (class "Default")
      (node (ref "IC77") (pin "12") (pinfunction "12_12") (pintype "passive"))
      (node (ref "IC78") (pin "12") (pinfunction "12_12") (pintype "passive"))
      (node (ref "IC79") (pin "12") (pinfunction "12_12") (pintype "passive"))
      (node (ref "IC80") (pin "12") (pinfunction "12_12") (pintype "passive"))
    )
    (net (code "811") (name "Net-(IC77-Pad13)") (class "Default")
      (node (ref "IC77") (pin "13") (pinfunction "13_13") (pintype "passive"))
      (node (ref "IC78") (pin "13") (pinfunction "13_13") (pintype "passive"))
      (node (ref "IC79") (pin "13") (pinfunction "13_13") (pintype "passive"))
      (node (ref "IC80") (pin "13") (pinfunction "13_13") (pintype "passive"))
    )
    (net (code "812") (name "Net-(IC77-Pad14)") (class "Default")
      (node (ref "IC77") (pin "14") (pinfunction "14_14") (pintype "passive"))
      (node (ref "IC78") (pin "14") (pinfunction "14_14") (pintype "passive"))
      (node (ref "IC79") (pin "14") (pinfunction "14_14") (pintype "passive"))
      (node (ref "IC80") (pin "14") (pinfunction "14_14") (pintype "passive"))
    )
    (net (code "813") (name "Net-(IC77-Pad15)") (class "Default")
      (node (ref "IC77") (pin "15") (pinfunction "15_15") (pintype "passive"))
      (node (ref "IC78") (pin "15") (pinfunction "15_15") (pintype "passive"))
      (node (ref "IC79") (pin "15") (pinfunction "15_15") (pintype "passive"))
      (node (ref "IC80") (pin "15") (pinfunction "15_15") (pintype "passive"))
    )
    (net (code "814") (name "Net-(IC77-Pad16)") (class "Default")
      (node (ref "IC77") (pin "16") (pinfunction "16_16") (pintype "passive"))
      (node (ref "IC78") (pin "16") (pinfunction "16_16") (pintype "passive"))
      (node (ref "IC79") (pin "16") (pinfunction "16_16") (pintype "passive"))
      (node (ref "IC80") (pin "16") (pinfunction "16_16") (pintype "passive"))
    )
    (net (code "815") (name "Net-(IC77-Pad17)") (class "Default")
      (node (ref "IC77") (pin "17") (pinfunction "17_17") (pintype "passive"))
      (node (ref "IC78") (pin "17") (pinfunction "17_17") (pintype "passive"))
      (node (ref "IC79") (pin "17") (pinfunction "17_17") (pintype "passive"))
      (node (ref "IC80") (pin "17") (pinfunction "17_17") (pintype "passive"))
    )
    (net (code "816") (name "Net-(IC77-Pad18)") (class "Default")
      (node (ref "IC77") (pin "18") (pinfunction "18_18") (pintype "passive"))
      (node (ref "IC78") (pin "18") (pinfunction "18_18") (pintype "passive"))
      (node (ref "IC79") (pin "18") (pinfunction "18_18") (pintype "passive"))
      (node (ref "IC80") (pin "18") (pinfunction "18_18") (pintype "passive"))
    )
    (net (code "817") (name "Net-(IC77-Pad19)") (class "Default")
      (node (ref "IC77") (pin "19") (pinfunction "19_19") (pintype "passive"))
      (node (ref "IC78") (pin "19") (pinfunction "19_19") (pintype "passive"))
      (node (ref "IC79") (pin "19") (pinfunction "19_19") (pintype "passive"))
      (node (ref "IC80") (pin "19") (pinfunction "19_19") (pintype "passive"))
    )
    (net (code "818") (name "Net-(IC77-Pad20)") (class "Default")
      (node (ref "IC77") (pin "20") (pinfunction "20_20") (pintype "passive"))
      (node (ref "IC78") (pin "20") (pinfunction "20_20") (pintype "passive"))
      (node (ref "IC79") (pin "20") (pinfunction "20_20") (pintype "passive"))
      (node (ref "IC80") (pin "20") (pinfunction "20_20") (pintype "passive"))
    )
    (net (code "819") (name "Net-(IC77-Pad21)") (class "Default")
      (node (ref "IC77") (pin "21") (pinfunction "21_21") (pintype "passive"))
      (node (ref "IC78") (pin "21") (pinfunction "21_21") (pintype "passive"))
      (node (ref "IC79") (pin "21") (pinfunction "21_21") (pintype "passive"))
      (node (ref "IC80") (pin "21") (pinfunction "21_21") (pintype "passive"))
    )
    (net (code "820") (name "Net-(IC77-Pad22)") (class "Default")
      (node (ref "IC77") (pin "22") (pinfunction "22_22") (pintype "passive"))
      (node (ref "IC78") (pin "22") (pinfunction "22_22") (pintype "passive"))
      (node (ref "IC79") (pin "22") (pinfunction "22_22") (pintype "passive"))
      (node (ref "IC80") (pin "22") (pinfunction "22_22") (pintype "passive"))
    )
    (net (code "821") (name "Net-(IC77-Pad23)") (class "Default")
      (node (ref "IC77") (pin "23") (pinfunction "23_23") (pintype "passive"))
      (node (ref "IC78") (pin "23") (pinfunction "23_23") (pintype "passive"))
      (node (ref "IC79") (pin "23") (pinfunction "23_23") (pintype "passive"))
      (node (ref "IC80") (pin "23") (pinfunction "23_23") (pintype "passive"))
    )
    (net (code "822") (name "Net-(IC77-Pad24)") (class "Default")
      (node (ref "IC77") (pin "24") (pinfunction "24_24") (pintype "passive"))
      (node (ref "IC78") (pin "24") (pinfunction "24_24") (pintype "passive"))
      (node (ref "IC79") (pin "24") (pinfunction "24_24") (pintype "passive"))
      (node (ref "IC80") (pin "24") (pinfunction "24_24") (pintype "passive"))
    )
    (net (code "823") (name "Net-(IC77-Pad25)") (class "Default")
      (node (ref "IC77") (pin "25") (pinfunction "25_25") (pintype "passive"))
      (node (ref "IC78") (pin "25") (pinfunction "25_25") (pintype "passive"))
      (node (ref "IC79") (pin "25") (pinfunction "25_25") (pintype "passive"))
      (node (ref "IC80") (pin "25") (pinfunction "25_25") (pintype "passive"))
    )
    (net (code "824") (name "Net-(IC77-Pad26)") (class "Default")
      (node (ref "IC77") (pin "26") (pinfunction "26_26") (pintype "passive"))
      (node (ref "IC78") (pin "26") (pinfunction "26_26") (pintype "passive"))
      (node (ref "IC79") (pin "26") (pinfunction "26_26") (pintype "passive"))
      (node (ref "IC80") (pin "26") (pinfunction "26_26") (pintype "passive"))
    )
    (net (code "825") (name "Net-(IC77-Pad27)") (class "Default")
      (node (ref "IC77") (pin "27") (pinfunction "27_27") (pintype "passive"))
      (node (ref "IC78") (pin "27") (pinfunction "27_27") (pintype "passive"))
      (node (ref "IC79") (pin "27") (pinfunction "27_27") (pintype "passive"))
      (node (ref "IC80") (pin "27") (pinfunction "27_27") (pintype "passive"))
    )
    (net (code "826") (name "Net-(IC77-Pad28)") (class "Default")
      (node (ref "IC77") (pin "28") (pinfunction "28_28") (pintype "passive"))
      (node (ref "IC78") (pin "28") (pinfunction "28_28") (pintype "passive"))
      (node (ref "IC79") (pin "28") (pinfunction "28_28") (pintype "passive"))
      (node (ref "IC80") (pin "28") (pinfunction "28_28") (pintype "passive"))
    )
    (net (code "827") (name "Net-(IC77-Pad29)") (class "Default")
      (node (ref "IC77") (pin "29") (pinfunction "29_29") (pintype "passive"))
      (node (ref "IC78") (pin "29") (pinfunction "29_29") (pintype "passive"))
      (node (ref "IC79") (pin "29") (pinfunction "29_29") (pintype "passive"))
      (node (ref "IC80") (pin "29") (pinfunction "29_29") (pintype "passive"))
    )
    (net (code "828") (name "Net-(IC77-Pad30)") (class "Default")
      (node (ref "IC77") (pin "30") (pinfunction "30_30") (pintype "passive"))
      (node (ref "IC78") (pin "30") (pinfunction "30_30") (pintype "passive"))
      (node (ref "IC79") (pin "30") (pinfunction "30_30") (pintype "passive"))
      (node (ref "IC80") (pin "30") (pinfunction "30_30") (pintype "passive"))
    )
    (net (code "829") (name "Net-(IC77-Pad31)") (class "Default")
      (node (ref "IC77") (pin "31") (pinfunction "31_31") (pintype "passive"))
      (node (ref "IC78") (pin "31") (pinfunction "31_31") (pintype "passive"))
      (node (ref "IC79") (pin "31") (pinfunction "31_31") (pintype "passive"))
      (node (ref "IC80") (pin "31") (pinfunction "31_31") (pintype "passive"))
    )
    (net (code "830") (name "Net-(IC77-Pad32)") (class "Default")
      (node (ref "IC77") (pin "32") (pinfunction "32_32") (pintype "passive"))
      (node (ref "IC78") (pin "32") (pinfunction "32_32") (pintype "passive"))
      (node (ref "IC79") (pin "32") (pinfunction "32_32") (pintype "passive"))
      (node (ref "IC80") (pin "32") (pinfunction "32_32") (pintype "passive"))
    )
    (net (code "831") (name "Net-(IC77-Pad33)") (class "Default")
      (node (ref "IC77") (pin "33") (pinfunction "33_33") (pintype "passive"))
      (node (ref "IC78") (pin "33") (pinfunction "33_33") (pintype "passive"))
      (node (ref "IC79") (pin "33") (pinfunction "33_33") (pintype "passive"))
      (node (ref "IC80") (pin "33") (pinfunction "33_33") (pintype "passive"))
    )
    (net (code "832") (name "Net-(IC77-Pad34)") (class "Default")
      (node (ref "IC77") (pin "34") (pinfunction "34_34") (pintype "passive"))
      (node (ref "IC78") (pin "34") (pinfunction "34_34") (pintype "passive"))
      (node (ref "IC79") (pin "34") (pinfunction "34_34") (pintype "passive"))
      (node (ref "IC80") (pin "34") (pinfunction "34_34") (pintype "passive"))
    )
    (net (code "833") (name "Net-(IC77-Pad35)") (class "Default")
      (node (ref "IC77") (pin "35") (pinfunction "35_35") (pintype "passive"))
      (node (ref "IC78") (pin "35") (pinfunction "35_35") (pintype "passive"))
      (node (ref "IC79") (pin "35") (pinfunction "35_35") (pintype "passive"))
      (node (ref "IC80") (pin "35") (pinfunction "35_35") (pintype "passive"))
    )
    (net (code "834") (name "Net-(IC77-Pad36)") (class "Default")
      (node (ref "IC77") (pin "36") (pinfunction "36_36") (pintype "passive"))
      (node (ref "IC78") (pin "36") (pinfunction "36_36") (pintype "passive"))
      (node (ref "IC79") (pin "36") (pinfunction "36_36") (pintype "passive"))
      (node (ref "IC80") (pin "36") (pinfunction "36_36") (pintype "passive"))
    )
    (net (code "835") (name "Net-(IC77-Pad37)") (class "Default")
      (node (ref "IC77") (pin "37") (pinfunction "37_37") (pintype "passive"))
      (node (ref "IC78") (pin "37") (pinfunction "37_37") (pintype "passive"))
      (node (ref "IC79") (pin "37") (pinfunction "37_37") (pintype "passive"))
      (node (ref "IC80") (pin "37") (pinfunction "37_37") (pintype "passive"))
    )
    (net (code "836") (name "Net-(IC77-Pad38)") (class "Default")
      (node (ref "IC77") (pin "38") (pinfunction "38_38") (pintype "passive"))
      (node (ref "IC78") (pin "38") (pinfunction "38_38") (pintype "passive"))
      (node (ref "IC79") (pin "38") (pinfunction "38_38") (pintype "passive"))
      (node (ref "IC80") (pin "38") (pinfunction "38_38") (pintype "passive"))
    )
    (net (code "837") (name "Net-(IC77-Pad39)") (class "Default")
      (node (ref "IC77") (pin "39") (pinfunction "39_39") (pintype "passive"))
      (node (ref "IC78") (pin "39") (pinfunction "39_39") (pintype "passive"))
      (node (ref "IC79") (pin "39") (pinfunction "39_39") (pintype "passive"))
      (node (ref "IC80") (pin "39") (pinfunction "39_39") (pintype "passive"))
    )
    (net (code "838") (name "Net-(IC77-Pad40)") (class "Default")
      (node (ref "IC77") (pin "40") (pinfunction "40_40") (pintype "passive"))
      (node (ref "IC78") (pin "40") (pinfunction "40_40") (pintype "passive"))
      (node (ref "IC79") (pin "40") (pinfunction "40_40") (pintype "passive"))
      (node (ref "IC80") (pin "40") (pinfunction "40_40") (pintype "passive"))
    )
    (net (code "839") (name "Net-(IC77-Pad41)") (class "Default")
      (node (ref "IC77") (pin "41") (pinfunction "41_41") (pintype "passive"))
      (node (ref "IC78") (pin "41") (pinfunction "41_41") (pintype "passive"))
      (node (ref "IC79") (pin "41") (pinfunction "41_41") (pintype "passive"))
      (node (ref "IC80") (pin "41") (pinfunction "41_41") (pintype "passive"))
    )
    (net (code "840") (name "Net-(IC77-Pad42)") (class "Default")
      (node (ref "IC77") (pin "42") (pinfunction "42_42") (pintype "passive"))
      (node (ref "IC78") (pin "42") (pinfunction "42_42") (pintype "passive"))
      (node (ref "IC79") (pin "42") (pinfunction "42_42") (pintype "passive"))
      (node (ref "IC80") (pin "42") (pinfunction "42_42") (pintype "passive"))
    )
    (net (code "841") (name "Net-(IC81-Pad1)") (class "Default")
      (node (ref "IC81") (pin "1") (pinfunction "1_1") (pintype "passive"))
      (node (ref "IC82") (pin "1") (pinfunction "1_1") (pintype "passive"))
      (node (ref "IC83") (pin "1") (pinfunction "1_1") (pintype "passive"))
      (node (ref "IC84") (pin "1") (pinfunction "1_1") (pintype "passive"))
    )
    (net (code "842") (name "Net-(IC81-Pad2)") (class "Default")
      (node (ref "IC81") (pin "2") (pinfunction "2_2") (pintype "passive"))
      (node (ref "IC82") (pin "2") (pinfunction "2_2") (pintype "passive"))
      (node (ref "IC83") (pin "2") (pinfunction "2_2") (pintype "passive"))
      (node (ref "IC84") (pin "2") (pinfunction "2_2") (pintype "passive"))
    )
    (net (code "843") (name "Net-(IC81-Pad3)") (class "Default")
      (node (ref "IC81") (pin "3") (pinfunction "3_3") (pintype "passive"))
      (node (ref "IC82") (pin "3") (pinfunction "3_3") (pintype "passive"))
      (node (ref "IC83") (pin "3") (pinfunction "3_3") (pintype "passive"))
      (node (ref "IC84") (pin "3") (pinfunction "3_3") (pintype "passive"))
    )
    (net (code "844") (name "Net-(IC81-Pad4)") (class "Default")
      (node (ref "IC81") (pin "4") (pinfunction "4_4") (pintype "passive"))
      (node (ref "IC82") (pin "4") (pinfunction "4_4") (pintype "passive"))
      (node (ref "IC83") (pin "4") (pinfunction "4_4") (pintype "passive"))
      (node (ref "IC84") (pin "4") (pinfunction "4_4") (pintype "passive"))
    )
    (net (code "845") (name "Net-(IC81-Pad5)") (class "Default")
      (node (ref "IC81") (pin "5") (pinfunction "5_5") (pintype "passive"))
      (node (ref "IC82") (pin "5") (pinfunction "5_5") (pintype "passive"))
      (node (ref "IC83") (pin "5") (pinfunction "5_5") (pintype "passive"))
      (node (ref "IC84") (pin "5") (pinfunction "5_5") (pintype "passive"))
    )
    (net (code "846") (name "Net-(IC81-Pad6)") (class "Default")
      (node (ref "IC81") (pin "6") (pinfunction "6_6") (pintype "passive"))
      (node (ref "IC82") (pin "6") (pinfunction "6_6") (pintype "passive"))
      (node (ref "IC83") (pin "6") (pinfunction "6_6") (pintype "passive"))
      (node (ref "IC84") (pin "6") (pinfunction "6_6") (pintype "passive"))
    )
    (net (code "847") (name "Net-(IC81-Pad7)") (class "Default")
      (node (ref "IC81") (pin "7") (pinfunction "7_7") (pintype "passive"))
      (node (ref "IC82") (pin "7") (pinfunction "7_7") (pintype "passive"))
      (node (ref "IC83") (pin "7") (pinfunction "7_7") (pintype "passive"))
      (node (ref "IC84") (pin "7") (pinfunction "7_7") (pintype "passive"))
    )
    (net (code "848") (name "Net-(IC81-Pad8)") (class "Default")
      (node (ref "IC81") (pin "8") (pinfunction "8_8") (pintype "passive"))
      (node (ref "IC82") (pin "8") (pinfunction "8_8") (pintype "passive"))
      (node (ref "IC83") (pin "8") (pinfunction "8_8") (pintype "passive"))
      (node (ref "IC84") (pin "8") (pinfunction "8_8") (pintype "passive"))
    )
    (net (code "849") (name "Net-(IC81-Pad9)") (class "Default")
      (node (ref "IC81") (pin "9") (pinfunction "9_9") (pintype "passive"))
      (node (ref "IC82") (pin "9") (pinfunction "9_9") (pintype "passive"))
      (node (ref "IC83") (pin "9") (pinfunction "9_9") (pintype "passive"))
      (node (ref "IC84") (pin "9") (pinfunction "9_9") (pintype "passive"))
    )
    (net (code "850") (name "Net-(IC81-Pad10)") (class "Default")
      (node (ref "IC81") (pin "10") (pinfunction "10_10") (pintype "passive"))
      (node (ref "IC82") (pin "10") (pinfunction "10_10") (pintype "passive"))
      (node (ref "IC83") (pin "10") (pinfunction "10_10") (pintype "passive"))
      (node (ref "IC84") (pin "10") (pinfunction "10_10") (pintype "passive"))
    )
    (net (code "851") (name "Net-(IC81-Pad11)") (class "Default")
      (node (ref "IC81") (pin "11") (pinfunction "11_11") (pintype "passive"))
      (node (ref "IC82") (pin "11") (pinfunction "11_11") (pintype "passive"))
      (node (ref "IC83") (pin "11") (pinfunction "11_11") (pintype "passive"))
      (node (ref "IC84") (pin "11") (pinfunction "11_11") (pintype "passive"))
    )
    (net (code "852") (name "Net-(IC81-Pad12)") (class "Default")
      (node (ref "IC81") (pin "12") (pinfunction "12_12") (pintype "passive"))
      (node (ref "IC82") (pin "12") (pinfunction "12_12") (pintype "passive"))
      (node (ref "IC83") (pin "12") (pinfunction "12_12") (pintype "passive"))
      (node (ref "IC84") (pin "12") (pinfunction "12_12") (pintype "passive"))
    )
    (net (code "853") (name "Net-(IC81-Pad13)") (class "Default")
      (node (ref "IC81") (pin "13") (pinfunction "13_13") (pintype "passive"))
      (node (ref "IC82") (pin "13") (pinfunction "13_13") (pintype "passive"))
      (node (ref "IC83") (pin "13") (pinfunction "13_13") (pintype "passive"))
      (node (ref "IC84") (pin "13") (pinfunction "13_13") (pintype "passive"))
    )
    (net (code "854") (name "Net-(IC81-Pad14)") (class "Default")
      (node (ref "IC81") (pin "14") (pinfunction "14_14") (pintype "passive"))
      (node (ref "IC82") (pin "14") (pinfunction "14_14") (pintype "passive"))
      (node (ref "IC83") (pin "14") (pinfunction "14_14") (pintype "passive"))
      (node (ref "IC84") (pin "14") (pinfunction "14_14") (pintype "passive"))
    )
    (net (code "855") (name "Net-(IC81-Pad15)") (class "Default")
      (node (ref "IC81") (pin "15") (pinfunction "15_15") (pintype "passive"))
      (node (ref "IC82") (pin "15") (pinfunction "15_15") (pintype "passive"))
      (node (ref "IC83") (pin "15") (pinfunction "15_15") (pintype "passive"))
      (node (ref "IC84") (pin "15") (pinfunction "15_15") (pintype "passive"))
    )
    (net (code "856") (name "Net-(IC81-Pad16)") (class "Default")
      (node (ref "IC81") (pin "16") (pinfunction "16_16") (pintype "passive"))
      (node (ref "IC82") (pin "16") (pinfunction "16_16") (pintype "passive"))
      (node (ref "IC83") (pin "16") (pinfunction "16_16") (pintype "passive"))
      (node (ref "IC84") (pin "16") (pinfunction "16_16") (pintype "passive"))
    )
    (net (code "857") (name "Net-(IC81-Pad17)") (class "Default")
      (node (ref "IC81") (pin "17") (pinfunction "17_17") (pintype "passive"))
      (node (ref "IC82") (pin "17") (pinfunction "17_17") (pintype "passive"))
      (node (ref "IC83") (pin "17") (pinfunction "17_17") (pintype "passive"))
      (node (ref "IC84") (pin "17") (pinfunction "17_17") (pintype "passive"))
    )
    (net (code "858") (name "Net-(IC81-Pad18)") (class "Default")
      (node (ref "IC81") (pin "18") (pinfunction "18_18") (pintype "passive"))
      (node (ref "IC82") (pin "18") (pinfunction "18_18") (pintype "passive"))
      (node (ref "IC83") (pin "18") (pinfunction "18_18") (pintype "passive"))
      (node (ref "IC84") (pin "18") (pinfunction "18_18") (pintype "passive"))
    )
    (net (code "859") (name "Net-(IC81-Pad19)") (class "Default")
      (node (ref "IC81") (pin "19") (pinfunction "19_19") (pintype "passive"))
      (node (ref "IC82") (pin "19") (pinfunction "19_19") (pintype "passive"))
      (node (ref "IC83") (pin "19") (pinfunction "19_19") (pintype "passive"))
      (node (ref "IC84") (pin "19") (pinfunction "19_19") (pintype "passive"))
    )
    (net (code "860") (name "Net-(IC81-Pad20)") (class "Default")
      (node (ref "IC81") (pin "20") (pinfunction "20_20") (pintype "passive"))
      (node (ref "IC82") (pin "20") (pinfunction "20_20") (pintype "passive"))
      (node (ref "IC83") (pin "20") (pinfunction "20_20") (pintype "passive"))
      (node (ref "IC84") (pin "20") (pinfunction "20_20") (pintype "passive"))
    )
    (net (code "861") (name "Net-(IC81-Pad21)") (class "Default")
      (node (ref "IC81") (pin "21") (pinfunction "21_21") (pintype "passive"))
      (node (ref "IC82") (pin "21") (pinfunction "21_21") (pintype "passive"))
      (node (ref "IC83") (pin "21") (pinfunction "21_21") (pintype "passive"))
      (node (ref "IC84") (pin "21") (pinfunction "21_21") (pintype "passive"))
    )
    (net (code "862") (name "Net-(IC81-Pad22)") (class "Default")
      (node (ref "IC81") (pin "22") (pinfunction "22_22") (pintype "passive"))
      (node (ref "IC82") (pin "22") (pinfunction "22_22") (pintype "passive"))
      (node (ref "IC83") (pin "22") (pinfunction "22_22") (pintype "passive"))
      (node (ref "IC84") (pin "22") (pinfunction "22_22") (pintype "passive"))
    )
    (net (code "863") (name "Net-(IC81-Pad23)") (class "Default")
      (node (ref "IC81") (pin "23") (pinfunction "23_23") (pintype "passive"))
      (node (ref "IC82") (pin "23") (pinfunction "23_23") (pintype "passive"))
      (node (ref "IC83") (pin "23") (pinfunction "23_23") (pintype "passive"))
      (node (ref "IC84") (pin "23") (pinfunction "23_23") (pintype "passive"))
    )
    (net (code "864") (name "Net-(IC81-Pad24)") (class "Default")
      (node (ref "IC81") (pin "24") (pinfunction "24_24") (pintype "passive"))
      (node (ref "IC82") (pin "24") (pinfunction "24_24") (pintype "passive"))
      (node (ref "IC83") (pin "24") (pinfunction "24_24") (pintype "passive"))
      (node (ref "IC84") (pin "24") (pinfunction "24_24") (pintype "passive"))
    )
    (net (code "865") (name "Net-(IC81-Pad25)") (class "Default")
      (node (ref "IC81") (pin "25") (pinfunction "25_25") (pintype "passive"))
      (node (ref "IC82") (pin "25") (pinfunction "25_25") (pintype "passive"))
      (node (ref "IC83") (pin "25") (pinfunction "25_25") (pintype "passive"))
      (node (ref "IC84") (pin "25") (pinfunction "25_25") (pintype "passive"))
    )
    (net (code "866") (name "Net-(IC81-Pad26)") (class "Default")
      (node (ref "IC81") (pin "26") (pinfunction "26_26") (pintype "passive"))
      (node (ref "IC82") (pin "26") (pinfunction "26_26") (pintype "passive"))
      (node (ref "IC83") (pin "26") (pinfunction "26_26") (pintype "passive"))
      (node (ref "IC84") (pin "26") (pinfunction "26_26") (pintype "passive"))
    )
    (net (code "867") (name "Net-(IC81-Pad27)") (class "Default")
      (node (ref "IC81") (pin "27") (pinfunction "27_27") (pintype "passive"))
      (node (ref "IC82") (pin "27") (pinfunction "27_27") (pintype "passive"))
      (node (ref "IC83") (pin "27") (pinfunction "27_27") (pintype "passive"))
      (node (ref "IC84") (pin "27") (pinfunction "27_27") (pintype "passive"))
    )
    (net (code "868") (name "Net-(IC81-Pad28)") (class "Default")
      (node (ref "IC81") (pin "28") (pinfunction "28_28") (pintype "passive"))
      (node (ref "IC82") (pin "28") (pinfunction "28_28") (pintype "passive"))
      (node (ref "IC83") (pin "28") (pinfunction "28_28") (pintype "passive"))
      (node (ref "IC84") (pin "28") (pinfunction "28_28") (pintype "passive"))
    )
    (net (code "869") (name "Net-(IC81-Pad29)") (class "Default")
      (node (ref "IC81") (pin "29") (pinfunction "29_29") (pintype "passive"))
      (node (ref "IC82") (pin "29") (pinfunction "29_29") (pintype "passive"))
      (node (ref "IC83") (pin "29") (pinfunction "29_29") (pintype "passive"))
      (node (ref "IC84") (pin "29") (pinfunction "29_29") (pintype "passive"))
    )
    (net (code "870") (name "Net-(IC81-Pad30)") (class "Default")
      (node (ref "IC81") (pin "30") (pinfunction "30_30") (pintype "passive"))
      (node (ref "IC82") (pin "30") (pinfunction "30_30") (pintype "passive"))
      (node (ref "IC83") (pin "30") (pinfunction "30_30") (pintype "passive"))
      (node (ref "IC84") (pin "30") (pinfunction "30_30") (pintype "passive"))
    )
    (net (code "871") (name "Net-(IC81-Pad31)") (class "Default")
      (node (ref "IC81") (pin "31") (pinfunction "31_31") (pintype "passive"))
      (node (ref "IC82") (pin "31") (pinfunction "31_31") (pintype "passive"))
      (node (ref "IC83") (pin "31") (pinfunction "31_31") (pintype "passive"))
      (node (ref "IC84") (pin "31") (pinfunction "31_31") (pintype "passive"))
    )
    (net (code "872") (name "Net-(IC81-Pad32)") (class "Default")
      (node (ref "IC81") (pin "32") (pinfunction "32_32") (pintype "passive"))
      (node (ref "IC82") (pin "32") (pinfunction "32_32") (pintype "passive"))
      (node (ref "IC83") (pin "32") (pinfunction "32_32") (pintype "passive"))
      (node (ref "IC84") (pin "32") (pinfunction "32_32") (pintype "passive"))
    )
    (net (code "873") (name "Net-(IC81-Pad33)") (class "Default")
      (node (ref "IC81") (pin "33") (pinfunction "33_33") (pintype "passive"))
      (node (ref "IC82") (pin "33") (pinfunction "33_33") (pintype "passive"))
      (node (ref "IC83") (pin "33") (pinfunction "33_33") (pintype "passive"))
      (node (ref "IC84") (pin "33") (pinfunction "33_33") (pintype "passive"))
    )
    (net (code "874") (name "Net-(IC81-Pad34)") (class "Default")
      (node (ref "IC81") (pin "34") (pinfunction "34_34") (pintype "passive"))
      (node (ref "IC82") (pin "34") (pinfunction "34_34") (pintype "passive"))
      (node (ref "IC83") (pin "34") (pinfunction "34_34") (pintype "passive"))
      (node (ref "IC84") (pin "34") (pinfunction "34_34") (pintype "passive"))
    )
    (net (code "875") (name "Net-(IC81-Pad35)") (class "Default")
      (node (ref "IC81") (pin "35") (pinfunction "35_35") (pintype "passive"))
      (node (ref "IC82") (pin "35") (pinfunction "35_35") (pintype "passive"))
      (node (ref "IC83") (pin "35") (pinfunction "35_35") (pintype "passive"))
      (node (ref "IC84") (pin "35") (pinfunction "35_35") (pintype "passive"))
    )
    (net (code "876") (name "Net-(IC81-Pad36)") (class "Default")
      (node (ref "IC81") (pin "36") (pinfunction "36_36") (pintype "passive"))
      (node (ref "IC82") (pin "36") (pinfunction "36_36") (pintype "passive"))
      (node (ref "IC83") (pin "36") (pinfunction "36_36") (pintype "passive"))
      (node (ref "IC84") (pin "36") (pinfunction "36_36") (pintype "passive"))
    )
    (net (code "877") (name "Net-(IC81-Pad37)") (class "Default")
      (node (ref "IC81") (pin "37") (pinfunction "37_37") (pintype "passive"))
      (node (ref "IC82") (pin "37") (pinfunction "37_37") (pintype "passive"))
      (node (ref "IC83") (pin "37") (pinfunction "37_37") (pintype "passive"))
      (node (ref "IC84") (pin "37") (pinfunction "37_37") (pintype "passive"))
    )
    (net (code "878") (name "Net-(IC81-Pad38)") (class "Default")
      (node (ref "IC81") (pin "38") (pinfunction "38_38") (pintype "passive"))
      (node (ref "IC82") (pin "38") (pinfunction "38_38") (pintype "passive"))
      (node (ref "IC83") (pin "38") (pinfunction "38_38") (pintype "passive"))
      (node (ref "IC84") (pin "38") (pinfunction "38_38") (pintype "passive"))
    )
    (net (code "879") (name "Net-(IC81-Pad39)") (class "Default")
      (node (ref "IC81") (pin "39") (pinfunction "39_39") (pintype "passive"))
      (node (ref "IC82") (pin "39") (pinfunction "39_39") (pintype "passive"))
      (node (ref "IC83") (pin "39") (pinfunction "39_39") (pintype "passive"))
      (node (ref "IC84") (pin "39") (pinfunction "39_39") (pintype "passive"))
    )
    (net (code "880") (name "Net-(IC81-Pad40)") (class "Default")
      (node (ref "IC81") (pin "40") (pinfunction "40_40") (pintype "passive"))
      (node (ref "IC82") (pin "40") (pinfunction "40_40") (pintype "passive"))
      (node (ref "IC83") (pin "40") (pinfunction "40_40") (pintype "passive"))
      (node (ref "IC84") (pin "40") (pinfunction "40_40") (pintype "passive"))
    )
    (net (code "881") (name "Net-(IC81-Pad41)") (class "Default")
      (node (ref "IC81") (pin "41") (pinfunction "41_41") (pintype "passive"))
      (node (ref "IC82") (pin "41") (pinfunction "41_41") (pintype "passive"))
      (node (ref "IC83") (pin "41") (pinfunction "41_41") (pintype "passive"))
      (node (ref "IC84") (pin "41") (pinfunction "41_41") (pintype "passive"))
    )
    (net (code "882") (name "Net-(IC81-Pad42)") (class "Default")
      (node (ref "IC81") (pin "42") (pinfunction "42_42") (pintype "passive"))
      (node (ref "IC82") (pin "42") (pinfunction "42_42") (pintype "passive"))
      (node (ref "IC83") (pin "42") (pinfunction "42_42") (pintype "passive"))
      (node (ref "IC84") (pin "42") (pinfunction "42_42") (pintype "passive"))
    )
    (net (code "883") (name "Net-(IC85-Pad1)") (class "Default")
      (node (ref "IC85") (pin "1") (pinfunction "1_1") (pintype "passive"))
      (node (ref "IC86") (pin "1") (pinfunction "1_1") (pintype "passive"))
      (node (ref "IC87") (pin "1") (pinfunction "1_1") (pintype "passive"))
      (node (ref "IC88") (pin "1") (pinfunction "1_1") (pintype "passive"))
    )
    (net (code "884") (name "Net-(IC85-Pad2)") (class "Default")
      (node (ref "IC85") (pin "2") (pinfunction "2_2") (pintype "passive"))
      (node (ref "IC86") (pin "2") (pinfunction "2_2") (pintype "passive"))
      (node (ref "IC87") (pin "2") (pinfunction "2_2") (pintype "passive"))
      (node (ref "IC88") (pin "2") (pinfunction "2_2") (pintype "passive"))
    )
    (net (code "885") (name "Net-(IC85-Pad3)") (class "Default")
      (node (ref "IC85") (pin "3") (pinfunction "3_3") (pintype "passive"))
      (node (ref "IC86") (pin "3") (pinfunction "3_3") (pintype "passive"))
      (node (ref "IC87") (pin "3") (pinfunction "3_3") (pintype "passive"))
      (node (ref "IC88") (pin "3") (pinfunction "3_3") (pintype "passive"))
    )
    (net (code "886") (name "Net-(IC85-Pad4)") (class "Default")
      (node (ref "IC85") (pin "4") (pinfunction "4_4") (pintype "passive"))
      (node (ref "IC86") (pin "4") (pinfunction "4_4") (pintype "passive"))
      (node (ref "IC87") (pin "4") (pinfunction "4_4") (pintype "passive"))
      (node (ref "IC88") (pin "4") (pinfunction "4_4") (pintype "passive"))
    )
    (net (code "887") (name "Net-(IC85-Pad5)") (class "Default")
      (node (ref "IC85") (pin "5") (pinfunction "5_5") (pintype "passive"))
      (node (ref "IC86") (pin "5") (pinfunction "5_5") (pintype "passive"))
      (node (ref "IC87") (pin "5") (pinfunction "5_5") (pintype "passive"))
      (node (ref "IC88") (pin "5") (pinfunction "5_5") (pintype "passive"))
    )
    (net (code "888") (name "Net-(IC85-Pad6)") (class "Default")
      (node (ref "IC85") (pin "6") (pinfunction "6_6") (pintype "passive"))
      (node (ref "IC86") (pin "6") (pinfunction "6_6") (pintype "passive"))
      (node (ref "IC87") (pin "6") (pinfunction "6_6") (pintype "passive"))
      (node (ref "IC88") (pin "6") (pinfunction "6_6") (pintype "passive"))
    )
    (net (code "889") (name "Net-(IC85-Pad7)") (class "Default")
      (node (ref "IC85") (pin "7") (pinfunction "7_7") (pintype "passive"))
      (node (ref "IC86") (pin "7") (pinfunction "7_7") (pintype "passive"))
      (node (ref "IC87") (pin "7") (pinfunction "7_7") (pintype "passive"))
      (node (ref "IC88") (pin "7") (pinfunction "7_7") (pintype "passive"))
    )
    (net (code "890") (name "Net-(IC85-Pad8)") (class "Default")
      (node (ref "IC85") (pin "8") (pinfunction "8_8") (pintype "passive"))
      (node (ref "IC86") (pin "8") (pinfunction "8_8") (pintype "passive"))
      (node (ref "IC87") (pin "8") (pinfunction "8_8") (pintype "passive"))
      (node (ref "IC88") (pin "8") (pinfunction "8_8") (pintype "passive"))
    )
    (net (code "891") (name "Net-(IC85-Pad9)") (class "Default")
      (node (ref "IC85") (pin "9") (pinfunction "9_9") (pintype "passive"))
      (node (ref "IC86") (pin "9") (pinfunction "9_9") (pintype "passive"))
      (node (ref "IC87") (pin "9") (pinfunction "9_9") (pintype "passive"))
      (node (ref "IC88") (pin "9") (pinfunction "9_9") (pintype "passive"))
    )
    (net (code "892") (name "Net-(IC85-Pad10)") (class "Default")
      (node (ref "IC85") (pin "10") (pinfunction "10_10") (pintype "passive"))
      (node (ref "IC86") (pin "10") (pinfunction "10_10") (pintype "passive"))
      (node (ref "IC87") (pin "10") (pinfunction "10_10") (pintype "passive"))
      (node (ref "IC88") (pin "10") (pinfunction "10_10") (pintype "passive"))
    )
    (net (code "893") (name "Net-(IC85-Pad11)") (class "Default")
      (node (ref "IC85") (pin "11") (pinfunction "11_11") (pintype "passive"))
      (node (ref "IC86") (pin "11") (pinfunction "11_11") (pintype "passive"))
      (node (ref "IC87") (pin "11") (pinfunction "11_11") (pintype "passive"))
      (node (ref "IC88") (pin "11") (pinfunction "11_11") (pintype "passive"))
    )
    (net (code "894") (name "Net-(IC85-Pad12)") (class "Default")
      (node (ref "IC85") (pin "12") (pinfunction "12_12") (pintype "passive"))
      (node (ref "IC86") (pin "12") (pinfunction "12_12") (pintype "passive"))
      (node (ref "IC87") (pin "12") (pinfunction "12_12") (pintype "passive"))
      (node (ref "IC88") (pin "12") (pinfunction "12_12") (pintype "passive"))
    )
    (net (code "895") (name "Net-(IC85-Pad13)") (class "Default")
      (node (ref "IC85") (pin "13") (pinfunction "13_13") (pintype "passive"))
      (node (ref "IC86") (pin "13") (pinfunction "13_13") (pintype "passive"))
      (node (ref "IC87") (pin "13") (pinfunction "13_13") (pintype "passive"))
      (node (ref "IC88") (pin "13") (pinfunction "13_13") (pintype "passive"))
    )
    (net (code "896") (name "Net-(IC85-Pad14)") (class "Default")
      (node (ref "IC85") (pin "14") (pinfunction "14_14") (pintype "passive"))
      (node (ref "IC86") (pin "14") (pinfunction "14_14") (pintype "passive"))
      (node (ref "IC87") (pin "14") (pinfunction "14_14") (pintype "passive"))
      (node (ref "IC88") (pin "14") (pinfunction "14_14") (pintype "passive"))
    )
    (net (code "897") (name "Net-(IC85-Pad15)") (class "Default")
      (node (ref "IC85") (pin "15") (pinfunction "15_15") (pintype "passive"))
      (node (ref "IC86") (pin "15") (pinfunction "15_15") (pintype "passive"))
      (node (ref "IC87") (pin "15") (pinfunction "15_15") (pintype "passive"))
      (node (ref "IC88") (pin "15") (pinfunction "15_15") (pintype "passive"))
    )
    (net (code "898") (name "Net-(IC85-Pad16)") (class "Default")
      (node (ref "IC85") (pin "16") (pinfunction "16_16") (pintype "passive"))
      (node (ref "IC86") (pin "16") (pinfunction "16_16") (pintype "passive"))
      (node (ref "IC87") (pin "16") (pinfunction "16_16") (pintype "passive"))
      (node (ref "IC88") (pin "16") (pinfunction "16_16") (pintype "passive"))
    )
    (net (code "899") (name "Net-(IC85-Pad17)") (class "Default")
      (node (ref "IC85") (pin "17") (pinfunction "17_17") (pintype "passive"))
      (node (ref "IC86") (pin "17") (pinfunction "17_17") (pintype "passive"))
      (node (ref "IC87") (pin "17") (pinfunction "17_17") (pintype "passive"))
      (node (ref "IC88") (pin "17") (pinfunction "17_17") (pintype "passive"))
    )
    (net (code "900") (name "Net-(IC85-Pad18)") (class "Default")
      (node (ref "IC85") (pin "18") (pinfunction "18_18") (pintype "passive"))
      (node (ref "IC86") (pin "18") (pinfunction "18_18") (pintype "passive"))
      (node (ref "IC87") (pin "18") (pinfunction "18_18") (pintype "passive"))
      (node (ref "IC88") (pin "18") (pinfunction "18_18") (pintype "passive"))
    )
    (net (code "901") (name "Net-(IC85-Pad19)") (class "Default")
      (node (ref "IC85") (pin "19") (pinfunction "19_19") (pintype "passive"))
      (node (ref "IC86") (pin "19") (pinfunction "19_19") (pintype "passive"))
      (node (ref "IC87") (pin "19") (pinfunction "19_19") (pintype "passive"))
      (node (ref "IC88") (pin "19") (pinfunction "19_19") (pintype "passive"))
    )
    (net (code "902") (name "Net-(IC85-Pad20)") (class "Default")
      (node (ref "IC85") (pin "20") (pinfunction "20_20") (pintype "passive"))
      (node (ref "IC86") (pin "20") (pinfunction "20_20") (pintype "passive"))
      (node (ref "IC87") (pin "20") (pinfunction "20_20") (pintype "passive"))
      (node (ref "IC88") (pin "20") (pinfunction "20_20") (pintype "passive"))
    )
    (net (code "903") (name "Net-(IC85-Pad21)") (class "Default")
      (node (ref "IC85") (pin "21") (pinfunction "21_21") (pintype "passive"))
      (node (ref "IC86") (pin "21") (pinfunction "21_21") (pintype "passive"))
      (node (ref "IC87") (pin "21") (pinfunction "21_21") (pintype "passive"))
      (node (ref "IC88") (pin "21") (pinfunction "21_21") (pintype "passive"))
    )
    (net (code "904") (name "Net-(IC85-Pad22)") (class "Default")
      (node (ref "IC85") (pin "22") (pinfunction "22_22") (pintype "passive"))
      (node (ref "IC86") (pin "22") (pinfunction "22_22") (pintype "passive"))
      (node (ref "IC87") (pin "22") (pinfunction "22_22") (pintype "passive"))
      (node (ref "IC88") (pin "22") (pinfunction "22_22") (pintype "passive"))
    )
    (net (code "905") (name "Net-(IC85-Pad23)") (class "Default")
      (node (ref "IC85") (pin "23") (pinfunction "23_23") (pintype "passive"))
      (node (ref "IC86") (pin "23") (pinfunction "23_23") (pintype "passive"))
      (node (ref "IC87") (pin "23") (pinfunction "23_23") (pintype "passive"))
      (node (ref "IC88") (pin "23") (pinfunction "23_23") (pintype "passive"))
    )
    (net (code "906") (name "Net-(IC85-Pad24)") (class "Default")
      (node (ref "IC85") (pin "24") (pinfunction "24_24") (pintype "passive"))
      (node (ref "IC86") (pin "24") (pinfunction "24_24") (pintype "passive"))
      (node (ref "IC87") (pin "24") (pinfunction "24_24") (pintype "passive"))
      (node (ref "IC88") (pin "24") (pinfunction "24_24") (pintype "passive"))
    )
    (net (code "907") (name "Net-(IC85-Pad25)") (class "Default")
      (node (ref "IC85") (pin "25") (pinfunction "25_25") (pintype "passive"))
      (node (ref "IC86") (pin "25") (pinfunction "25_25") (pintype "passive"))
      (node (ref "IC87") (pin "25") (pinfunction "25_25") (pintype "passive"))
      (node (ref "IC88") (pin "25") (pinfunction "25_25") (pintype "passive"))
    )
    (net (code "908") (name "Net-(IC85-Pad26)") (class "Default")
      (node (ref "IC85") (pin "26") (pinfunction "26_26") (pintype "passive"))
      (node (ref "IC86") (pin "26") (pinfunction "26_26") (pintype "passive"))
      (node (ref "IC87") (pin "26") (pinfunction "26_26") (pintype "passive"))
      (node (ref "IC88") (pin "26") (pinfunction "26_26") (pintype "passive"))
    )
    (net (code "909") (name "Net-(IC85-Pad27)") (class "Default")
      (node (ref "IC85") (pin "27") (pinfunction "27_27") (pintype "passive"))
      (node (ref "IC86") (pin "27") (pinfunction "27_27") (pintype "passive"))
      (node (ref "IC87") (pin "27") (pinfunction "27_27") (pintype "passive"))
      (node (ref "IC88") (pin "27") (pinfunction "27_27") (pintype "passive"))
    )
    (net (code "910") (name "Net-(IC85-Pad28)") (class "Default")
      (node (ref "IC85") (pin "28") (pinfunction "28_28") (pintype "passive"))
      (node (ref "IC86") (pin "28") (pinfunction "28_28") (pintype "passive"))
      (node (ref "IC87") (pin "28") (pinfunction "28_28") (pintype "passive"))
      (node (ref "IC88") (pin "28") (pinfunction "28_28") (pintype "passive"))
    )
    (net (code "911") (name "Net-(IC85-Pad29)") (class "Default")
      (node (ref "IC85") (pin "29") (pinfunction "29_29") (pintype "passive"))
      (node (ref "IC86") (pin "29") (pinfunction "29_29") (pintype "passive"))
      (node (ref "IC87") (pin "29") (pinfunction "29_29") (pintype "passive"))
      (node (ref "IC88") (pin "29") (pinfunction "29_29") (pintype "passive"))
    )
    (net (code "912") (name "Net-(IC85-Pad30)") (class "Default")
      (node (ref "IC85") (pin "30") (pinfunction "30_30") (pintype "passive"))
      (node (ref "IC86") (pin "30") (pinfunction "30_30") (pintype "passive"))
      (node (ref "IC87") (pin "30") (pinfunction "30_30") (pintype "passive"))
      (node (ref "IC88") (pin "30") (pinfunction "30_30") (pintype "passive"))
    )
    (net (code "913") (name "Net-(IC85-Pad31)") (class "Default")
      (node (ref "IC85") (pin "31") (pinfunction "31_31") (pintype "passive"))
      (node (ref "IC86") (pin "31") (pinfunction "31_31") (pintype "passive"))
      (node (ref "IC87") (pin "31") (pinfunction "31_31") (pintype "passive"))
      (node (ref "IC88") (pin "31") (pinfunction "31_31") (pintype "passive"))
    )
    (net (code "914") (name "Net-(IC85-Pad32)") (class "Default")
      (node (ref "IC85") (pin "32") (pinfunction "32_32") (pintype "passive"))
      (node (ref "IC86") (pin "32") (pinfunction "32_32") (pintype "passive"))
      (node (ref "IC87") (pin "32") (pinfunction "32_32") (pintype "passive"))
      (node (ref "IC88") (pin "32") (pinfunction "32_32") (pintype "passive"))
    )
    (net (code "915") (name "Net-(IC85-Pad33)") (class "Default")
      (node (ref "IC85") (pin "33") (pinfunction "33_33") (pintype "passive"))
      (node (ref "IC86") (pin "33") (pinfunction "33_33") (pintype "passive"))
      (node (ref "IC87") (pin "33") (pinfunction "33_33") (pintype "passive"))
      (node (ref "IC88") (pin "33") (pinfunction "33_33") (pintype "passive"))
    )
    (net (code "916") (name "Net-(IC85-Pad34)") (class "Default")
      (node (ref "IC85") (pin "34") (pinfunction "34_34") (pintype "passive"))
      (node (ref "IC86") (pin "34") (pinfunction "34_34") (pintype "passive"))
      (node (ref "IC87") (pin "34") (pinfunction "34_34") (pintype "passive"))
      (node (ref "IC88") (pin "34") (pinfunction "34_34") (pintype "passive"))
    )
    (net (code "917") (name "Net-(IC85-Pad35)") (class "Default")
      (node (ref "IC85") (pin "35") (pinfunction "35_35") (pintype "passive"))
      (node (ref "IC86") (pin "35") (pinfunction "35_35") (pintype "passive"))
      (node (ref "IC87") (pin "35") (pinfunction "35_35") (pintype "passive"))
      (node (ref "IC88") (pin "35") (pinfunction "35_35") (pintype "passive"))
    )
    (net (code "918") (name "Net-(IC85-Pad36)") (class "Default")
      (node (ref "IC85") (pin "36") (pinfunction "36_36") (pintype "passive"))
      (node (ref "IC86") (pin "36") (pinfunction "36_36") (pintype "passive"))
      (node (ref "IC87") (pin "36") (pinfunction "36_36") (pintype "passive"))
      (node (ref "IC88") (pin "36") (pinfunction "36_36") (pintype "passive"))
    )
    (net (code "919") (name "Net-(IC85-Pad37)") (class "Default")
      (node (ref "IC85") (pin "37") (pinfunction "37_37") (pintype "passive"))
      (node (ref "IC86") (pin "37") (pinfunction "37_37") (pintype "passive"))
      (node (ref "IC87") (pin "37") (pinfunction "37_37") (pintype "passive"))
      (node (ref "IC88") (pin "37") (pinfunction "37_37") (pintype "passive"))
    )
    (net (code "920") (name "Net-(IC85-Pad38)") (class "Default")
      (node (ref "IC85") (pin "38") (pinfunction "38_38") (pintype "passive"))
      (node (ref "IC86") (pin "38") (pinfunction "38_38") (pintype "passive"))
      (node (ref "IC87") (pin "38") (pinfunction "38_38") (pintype "passive"))
      (node (ref "IC88") (pin "38") (pinfunction "38_38") (pintype "passive"))
    )
    (net (code "921") (name "Net-(IC85-Pad39)") (class "Default")
      (node (ref "IC85") (pin "39") (pinfunction "39_39") (pintype "passive"))
      (node (ref "IC86") (pin "39") (pinfunction "39_39") (pintype "passive"))
      (node (ref "IC87") (pin "39") (pinfunction "39_39") (pintype "passive"))
      (node (ref "IC88") (pin "39") (pinfunction "39_39") (pintype "passive"))
    )
    (net (code "922") (name "Net-(IC85-Pad40)") (class "Default")
      (node (ref "IC85") (pin "40") (pinfunction "40_40") (pintype "passive"))
      (node (ref "IC86") (pin "40") (pinfunction "40_40") (pintype "passive"))
      (node (ref "IC87") (pin "40") (pinfunction "40_40") (pintype "passive"))
      (node (ref "IC88") (pin "40") (pinfunction "40_40") (pintype "passive"))
    )
    (net (code "923") (name "Net-(IC85-Pad41)") (class "Default")
      (node (ref "IC85") (pin "41") (pinfunction "41_41") (pintype "passive"))
      (node (ref "IC86") (pin "41") (pinfunction "41_41") (pintype "passive"))
      (node (ref "IC87") (pin "41") (pinfunction "41_41") (pintype "passive"))
      (node (ref "IC88") (pin "41") (pinfunction "41_41") (pintype "passive"))
    )
    (net (code "924") (name "Net-(IC85-Pad42)") (class "Default")
      (node (ref "IC85") (pin "42") (pinfunction "42_42") (pintype "passive"))
      (node (ref "IC86") (pin "42") (pinfunction "42_42") (pintype "passive"))
      (node (ref "IC87") (pin "42") (pinfunction "42_42") (pintype "passive"))
      (node (ref "IC88") (pin "42") (pinfunction "42_42") (pintype "passive"))
    )
    (net (code "925") (name "Net-(IC89-Pad1)") (class "Default")
      (node (ref "IC89") (pin "1") (pinfunction "1_1") (pintype "passive"))
      (node (ref "IC90") (pin "1") (pinfunction "1_1") (pintype "passive"))
      (node (ref "IC91") (pin "1") (pinfunction "1_1") (pintype "passive"))
      (node (ref "IC92") (pin "1") (pinfunction "1_1") (pintype "passive"))
    )
    (net (code "926") (name "Net-(IC89-Pad2)") (class "Default")
      (node (ref "IC89") (pin "2") (pinfunction "2_2") (pintype "passive"))
      (node (ref "IC90") (pin "2") (pinfunction "2_2") (pintype "passive"))
      (node (ref "IC91") (pin "2") (pinfunction "2_2") (pintype "passive"))
      (node (ref "IC92") (pin "2") (pinfunction "2_2") (pintype "passive"))
    )
    (net (code "927") (name "Net-(IC89-Pad3)") (class "Default")
      (node (ref "IC89") (pin "3") (pinfunction "3_3") (pintype "passive"))
      (node (ref "IC90") (pin "3") (pinfunction "3_3") (pintype "passive"))
      (node (ref "IC91") (pin "3") (pinfunction "3_3") (pintype "passive"))
      (node (ref "IC92") (pin "3") (pinfunction "3_3") (pintype "passive"))
    )
    (net (code "928") (name "Net-(IC89-Pad4)") (class "Default")
      (node (ref "IC89") (pin "4") (pinfunction "4_4") (pintype "passive"))
      (node (ref "IC90") (pin "4") (pinfunction "4_4") (pintype "passive"))
      (node (ref "IC91") (pin "4") (pinfunction "4_4") (pintype "passive"))
      (node (ref "IC92") (pin "4") (pinfunction "4_4") (pintype "passive"))
    )
    (net (code "929") (name "Net-(IC89-Pad5)") (class "Default")
      (node (ref "IC89") (pin "5") (pinfunction "5_5") (pintype "passive"))
      (node (ref "IC90") (pin "5") (pinfunction "5_5") (pintype "passive"))
      (node (ref "IC91") (pin "5") (pinfunction "5_5") (pintype "passive"))
      (node (ref "IC92") (pin "5") (pinfunction "5_5") (pintype "passive"))
    )
    (net (code "930") (name "Net-(IC89-Pad6)") (class "Default")
      (node (ref "IC89") (pin "6") (pinfunction "6_6") (pintype "passive"))
      (node (ref "IC90") (pin "6") (pinfunction "6_6") (pintype "passive"))
      (node (ref "IC91") (pin "6") (pinfunction "6_6") (pintype "passive"))
      (node (ref "IC92") (pin "6") (pinfunction "6_6") (pintype "passive"))
    )
    (net (code "931") (name "Net-(IC89-Pad7)") (class "Default")
      (node (ref "IC89") (pin "7") (pinfunction "7_7") (pintype "passive"))
      (node (ref "IC90") (pin "7") (pinfunction "7_7") (pintype "passive"))
      (node (ref "IC91") (pin "7") (pinfunction "7_7") (pintype "passive"))
      (node (ref "IC92") (pin "7") (pinfunction "7_7") (pintype "passive"))
    )
    (net (code "932") (name "Net-(IC89-Pad8)") (class "Default")
      (node (ref "IC89") (pin "8") (pinfunction "8_8") (pintype "passive"))
      (node (ref "IC90") (pin "8") (pinfunction "8_8") (pintype "passive"))
      (node (ref "IC91") (pin "8") (pinfunction "8_8") (pintype "passive"))
      (node (ref "IC92") (pin "8") (pinfunction "8_8") (pintype "passive"))
    )
    (net (code "933") (name "Net-(IC89-Pad9)") (class "Default")
      (node (ref "IC89") (pin "9") (pinfunction "9_9") (pintype "passive"))
      (node (ref "IC90") (pin "9") (pinfunction "9_9") (pintype "passive"))
      (node (ref "IC91") (pin "9") (pinfunction "9_9") (pintype "passive"))
      (node (ref "IC92") (pin "9") (pinfunction "9_9") (pintype "passive"))
    )
    (net (code "934") (name "Net-(IC89-Pad10)") (class "Default")
      (node (ref "IC89") (pin "10") (pinfunction "10_10") (pintype "passive"))
      (node (ref "IC90") (pin "10") (pinfunction "10_10") (pintype "passive"))
      (node (ref "IC91") (pin "10") (pinfunction "10_10") (pintype "passive"))
      (node (ref "IC92") (pin "10") (pinfunction "10_10") (pintype "passive"))
    )
    (net (code "935") (name "Net-(IC89-Pad11)") (class "Default")
      (node (ref "IC89") (pin "11") (pinfunction "11_11") (pintype "passive"))
      (node (ref "IC90") (pin "11") (pinfunction "11_11") (pintype "passive"))
      (node (ref "IC91") (pin "11") (pinfunction "11_11") (pintype "passive"))
      (node (ref "IC92") (pin "11") (pinfunction "11_11") (pintype "passive"))
    )
    (net (code "936") (name "Net-(IC89-Pad12)") (class "Default")
      (node (ref "IC89") (pin "12") (pinfunction "12_12") (pintype "passive"))
      (node (ref "IC90") (pin "12") (pinfunction "12_12") (pintype "passive"))
      (node (ref "IC91") (pin "12") (pinfunction "12_12") (pintype "passive"))
      (node (ref "IC92") (pin "12") (pinfunction "12_12") (pintype "passive"))
    )
    (net (code "937") (name "Net-(IC89-Pad13)") (class "Default")
      (node (ref "IC89") (pin "13") (pinfunction "13_13") (pintype "passive"))
      (node (ref "IC90") (pin "13") (pinfunction "13_13") (pintype "passive"))
      (node (ref "IC91") (pin "13") (pinfunction "13_13") (pintype "passive"))
      (node (ref "IC92") (pin "13") (pinfunction "13_13") (pintype "passive"))
    )
    (net (code "938") (name "Net-(IC89-Pad14)") (class "Default")
      (node (ref "IC89") (pin "14") (pinfunction "14_14") (pintype "passive"))
      (node (ref "IC90") (pin "14") (pinfunction "14_14") (pintype "passive"))
      (node (ref "IC91") (pin "14") (pinfunction "14_14") (pintype "passive"))
      (node (ref "IC92") (pin "14") (pinfunction "14_14") (pintype "passive"))
    )
    (net (code "939") (name "Net-(IC89-Pad15)") (class "Default")
      (node (ref "IC89") (pin "15") (pinfunction "15_15") (pintype "passive"))
      (node (ref "IC90") (pin "15") (pinfunction "15_15") (pintype "passive"))
      (node (ref "IC91") (pin "15") (pinfunction "15_15") (pintype "passive"))
      (node (ref "IC92") (pin "15") (pinfunction "15_15") (pintype "passive"))
    )
    (net (code "940") (name "Net-(IC89-Pad16)") (class "Default")
      (node (ref "IC89") (pin "16") (pinfunction "16_16") (pintype "passive"))
      (node (ref "IC90") (pin "16") (pinfunction "16_16") (pintype "passive"))
      (node (ref "IC91") (pin "16") (pinfunction "16_16") (pintype "passive"))
      (node (ref "IC92") (pin "16") (pinfunction "16_16") (pintype "passive"))
    )
    (net (code "941") (name "Net-(IC89-Pad17)") (class "Default")
      (node (ref "IC89") (pin "17") (pinfunction "17_17") (pintype "passive"))
      (node (ref "IC90") (pin "17") (pinfunction "17_17") (pintype "passive"))
      (node (ref "IC91") (pin "17") (pinfunction "17_17") (pintype "passive"))
      (node (ref "IC92") (pin "17") (pinfunction "17_17") (pintype "passive"))
    )
    (net (code "942") (name "Net-(IC89-Pad18)") (class "Default")
      (node (ref "IC89") (pin "18") (pinfunction "18_18") (pintype "passive"))
      (node (ref "IC90") (pin "18") (pinfunction "18_18") (pintype "passive"))
      (node (ref "IC91") (pin "18") (pinfunction "18_18") (pintype "passive"))
      (node (ref "IC92") (pin "18") (pinfunction "18_18") (pintype "passive"))
    )
    (net (code "943") (name "Net-(IC89-Pad19)") (class "Default")
      (node (ref "IC89") (pin "19") (pinfunction "19_19") (pintype "passive"))
      (node (ref "IC90") (pin "19") (pinfunction "19_19") (pintype "passive"))
      (node (ref "IC91") (pin "19") (pinfunction "19_19") (pintype "passive"))
      (node (ref "IC92") (pin "19") (pinfunction "19_19") (pintype "passive"))
    )
    (net (code "944") (name "Net-(IC89-Pad20)") (class "Default")
      (node (ref "IC89") (pin "20") (pinfunction "20_20") (pintype "passive"))
      (node (ref "IC90") (pin "20") (pinfunction "20_20") (pintype "passive"))
      (node (ref "IC91") (pin "20") (pinfunction "20_20") (pintype "passive"))
      (node (ref "IC92") (pin "20") (pinfunction "20_20") (pintype "passive"))
    )
    (net (code "945") (name "Net-(IC89-Pad21)") (class "Default")
      (node (ref "IC89") (pin "21") (pinfunction "21_21") (pintype "passive"))
      (node (ref "IC90") (pin "21") (pinfunction "21_21") (pintype "passive"))
      (node (ref "IC91") (pin "21") (pinfunction "21_21") (pintype "passive"))
      (node (ref "IC92") (pin "21") (pinfunction "21_21") (pintype "passive"))
    )
    (net (code "946") (name "Net-(IC89-Pad22)") (class "Default")
      (node (ref "IC89") (pin "22") (pinfunction "22_22") (pintype "passive"))
      (node (ref "IC90") (pin "22") (pinfunction "22_22") (pintype "passive"))
      (node (ref "IC91") (pin "22") (pinfunction "22_22") (pintype "passive"))
      (node (ref "IC92") (pin "22") (pinfunction "22_22") (pintype "passive"))
    )
    (net (code "947") (name "Net-(IC89-Pad23)") (class "Default")
      (node (ref "IC89") (pin "23") (pinfunction "23_23") (pintype "passive"))
      (node (ref "IC90") (pin "23") (pinfunction "23_23") (pintype "passive"))
      (node (ref "IC91") (pin "23") (pinfunction "23_23") (pintype "passive"))
      (node (ref "IC92") (pin "23") (pinfunction "23_23") (pintype "passive"))
    )
    (net (code "948") (name "Net-(IC89-Pad24)") (class "Default")
      (node (ref "IC89") (pin "24") (pinfunction "24_24") (pintype "passive"))
      (node (ref "IC90") (pin "24") (pinfunction "24_24") (pintype "passive"))
      (node (ref "IC91") (pin "24") (pinfunction "24_24") (pintype "passive"))
      (node (ref "IC92") (pin "24") (pinfunction "24_24") (pintype "passive"))
    )
    (net (code "949") (name "Net-(IC89-Pad25)") (class "Default")
      (node (ref "IC89") (pin "25") (pinfunction "25_25") (pintype "passive"))
      (node (ref "IC90") (pin "25") (pinfunction "25_25") (pintype "passive"))
      (node (ref "IC91") (pin "25") (pinfunction "25_25") (pintype "passive"))
      (node (ref "IC92") (pin "25") (pinfunction "25_25") (pintype "passive"))
    )
    (net (code "950") (name "Net-(IC89-Pad26)") (class "Default")
      (node (ref "IC89") (pin "26") (pinfunction "26_26") (pintype "passive"))
      (node (ref "IC90") (pin "26") (pinfunction "26_26") (pintype "passive"))
      (node (ref "IC91") (pin "26") (pinfunction "26_26") (pintype "passive"))
      (node (ref "IC92") (pin "26") (pinfunction "26_26") (pintype "passive"))
    )
    (net (code "951") (name "Net-(IC89-Pad27)") (class "Default")
      (node (ref "IC89") (pin "27") (pinfunction "27_27") (pintype "passive"))
      (node (ref "IC90") (pin "27") (pinfunction "27_27") (pintype "passive"))
      (node (ref "IC91") (pin "27") (pinfunction "27_27") (pintype "passive"))
      (node (ref "IC92") (pin "27") (pinfunction "27_27") (pintype "passive"))
    )
    (net (code "952") (name "Net-(IC89-Pad28)") (class "Default")
      (node (ref "IC89") (pin "28") (pinfunction "28_28") (pintype "passive"))
      (node (ref "IC90") (pin "28") (pinfunction "28_28") (pintype "passive"))
      (node (ref "IC91") (pin "28") (pinfunction "28_28") (pintype "passive"))
      (node (ref "IC92") (pin "28") (pinfunction "28_28") (pintype "passive"))
    )
    (net (code "953") (name "Net-(IC89-Pad29)") (class "Default")
      (node (ref "IC89") (pin "29") (pinfunction "29_29") (pintype "passive"))
      (node (ref "IC90") (pin "29") (pinfunction "29_29") (pintype "passive"))
      (node (ref "IC91") (pin "29") (pinfunction "29_29") (pintype "passive"))
      (node (ref "IC92") (pin "29") (pinfunction "29_29") (pintype "passive"))
    )
    (net (code "954") (name "Net-(IC89-Pad30)") (class "Default")
      (node (ref "IC89") (pin "30") (pinfunction "30_30") (pintype "passive"))
      (node (ref "IC90") (pin "30") (pinfunction "30_30") (pintype "passive"))
      (node (ref "IC91") (pin "30") (pinfunction "30_30") (pintype "passive"))
      (node (ref "IC92") (pin "30") (pinfunction "30_30") (pintype "passive"))
    )
    (net (code "955") (name "Net-(IC89-Pad31)") (class "Default")
      (node (ref "IC89") (pin "31") (pinfunction "31_31") (pintype "passive"))
      (node (ref "IC90") (pin "31") (pinfunction "31_31") (pintype "passive"))
      (node (ref "IC91") (pin "31") (pinfunction "31_31") (pintype "passive"))
      (node (ref "IC92") (pin "31") (pinfunction "31_31") (pintype "passive"))
    )
    (net (code "956") (name "Net-(IC89-Pad32)") (class "Default")
      (node (ref "IC89") (pin "32") (pinfunction "32_32") (pintype "passive"))
      (node (ref "IC90") (pin "32") (pinfunction "32_32") (pintype "passive"))
      (node (ref "IC91") (pin "32") (pinfunction "32_32") (pintype "passive"))
      (node (ref "IC92") (pin "32") (pinfunction "32_32") (pintype "passive"))
    )
    (net (code "957") (name "Net-(SV1-1)") (class "Default")
      (node (ref "SV1") (pin "A") (pinfunction "1_A") (pintype "bidirectional"))
      (node (ref "U$2") (pin "1") (pinfunction "1_1") (pintype "passive"))
    )
    (net (code "958") (name "Net-(SV1-2)") (class "Default")
      (node (ref "SV1") (pin "B") (pinfunction "2_B") (pintype "bidirectional"))
      (node (ref "U$4") (pin "1") (pinfunction "1_1") (pintype "passive"))
    )
    (net (code "959") (name "Net-(SV1-3)") (class "Default")
      (node (ref "SV1") (pin "C") (pinfunction "3_C") (pintype "bidirectional"))
      (node (ref "U$2") (pin "2") (pinfunction "2_2") (pintype "passive"))
    )
    (net (code "960") (name "Net-(SV1-4)") (class "Default")
      (node (ref "SV1") (pin "D") (pinfunction "4_D") (pintype "bidirectional"))
      (node (ref "U$4") (pin "2") (pinfunction "2_2") (pintype "passive"))
    )
    (net (code "961") (name "Net-(SV1-5)") (class "Default")
      (node (ref "SV1") (pin "E") (pinfunction "5_E") (pintype "bidirectional"))
      (node (ref "U$2") (pin "3") (pinfunction "3_3") (pintype "passive"))
    )
    (net (code "962") (name "Net-(SV1-6)") (class "Default")
      (node (ref "SV1") (pin "F") (pinfunction "6_F") (pintype "bidirectional"))
      (node (ref "U$4") (pin "3") (pinfunction "3_3") (pintype "passive"))
    )
    (net (code "963") (name "Net-(SV1-7)") (class "Default")
      (node (ref "SV1") (pin "H") (pinfunction "7_H") (pintype "bidirectional"))
      (node (ref "U$2") (pin "4") (pinfunction "4_4") (pintype "passive"))
    )
    (net (code "964") (name "Net-(SV1-8)") (class "Default")
      (node (ref "SV1") (pin "J") (pinfunction "8_J") (pintype "bidirectional"))
      (node (ref "U$4") (pin "4") (pinfunction "4_4") (pintype "passive"))
    )
    (net (code "965") (name "Net-(SV1-9)") (class "Default")
      (node (ref "SV1") (pin "K") (pinfunction "9_K") (pintype "bidirectional"))
      (node (ref "U$2") (pin "5") (pinfunction "5_5") (pintype "passive"))
    )
    (net (code "966") (name "Net-(SV1-10)") (class "Default")
      (node (ref "SV1") (pin "L") (pinfunction "10_L") (pintype "bidirectional"))
      (node (ref "U$4") (pin "5") (pinfunction "5_5") (pintype "passive"))
    )
    (net (code "967") (name "Net-(SV1-11)") (class "Default")
      (node (ref "SV1") (pin "M") (pinfunction "11_M") (pintype "bidirectional"))
      (node (ref "U$2") (pin "6") (pinfunction "6_6") (pintype "passive"))
    )
    (net (code "968") (name "Net-(SV1-12)") (class "Default")
      (node (ref "SV1") (pin "N") (pinfunction "12_N") (pintype "bidirectional"))
      (node (ref "U$4") (pin "6") (pinfunction "6_6") (pintype "passive"))
    )
    (net (code "969") (name "Net-(SV1-13)") (class "Default")
      (node (ref "SV1") (pin "P") (pinfunction "13_P") (pintype "bidirectional"))
      (node (ref "U$2") (pin "7") (pinfunction "7_7") (pintype "passive"))
    )
    (net (code "970") (name "Net-(SV1-14)") (class "Default")
      (node (ref "SV1") (pin "R") (pinfunction "14_R") (pintype "bidirectional"))
      (node (ref "U$4") (pin "7") (pinfunction "7_7") (pintype "passive"))
    )
    (net (code "971") (name "Net-(SV1-15)") (class "Default")
      (node (ref "SV1") (pin "S") (pinfunction "15_S") (pintype "bidirectional"))
      (node (ref "U$2") (pin "8") (pinfunction "8_8") (pintype "passive"))
    )
    (net (code "972") (name "Net-(SV1-16)") (class "Default")
      (node (ref "SV1") (pin "T") (pinfunction "16_T") (pintype "bidirectional"))
      (node (ref "U$4") (pin "8") (pinfunction "8_8") (pintype "passive"))
    )
    (net (code "973") (name "Net-(SV1-17)") (class "Default")
      (node (ref "SV1") (pin "U") (pinfunction "17_U") (pintype "bidirectional"))
      (node (ref "U$2") (pin "9") (pinfunction "9_9") (pintype "passive"))
    )
    (net (code "974") (name "Net-(SV1-18)") (class "Default")
      (node (ref "SV1") (pin "V") (pinfunction "18_V") (pintype "bidirectional"))
      (node (ref "U$4") (pin "9") (pinfunction "9_9") (pintype "passive"))
    )
    (net (code "975") (name "Net-(SV1-19)") (class "Default")
      (node (ref "SV1") (pin "W") (pinfunction "19_W") (pintype "bidirectional"))
      (node (ref "U$2") (pin "10") (pinfunction "10_10") (pintype "passive"))
    )
    (net (code "976") (name "Net-(SV1-20)") (class "Default")
      (node (ref "SV1") (pin "X") (pinfunction "20_X") (pintype "bidirectional"))
      (node (ref "U$4") (pin "10") (pinfunction "10_10") (pintype "passive"))
    )
    (net (code "977") (name "Net-(SV1-21)") (class "Default")
      (node (ref "SV1") (pin "Y") (pinfunction "21_Y") (pintype "bidirectional"))
      (node (ref "U$2") (pin "11") (pinfunction "11_11") (pintype "passive"))
    )
    (net (code "978") (name "Net-(SV1-22)") (class "Default")
      (node (ref "SV1") (pin "Z") (pinfunction "22_Z") (pintype "bidirectional"))
      (node (ref "U$4") (pin "11") (pinfunction "11_11") (pintype "passive"))
    )
    (net (code "979") (name "Net-(SV1-23)") (class "Default")
      (node (ref "SV1") (pin "AA") (pinfunction "23_AA") (pintype "bidirectional"))
      (node (ref "U$2") (pin "12") (pinfunction "12_12") (pintype "passive"))
    )
    (net (code "980") (name "Net-(SV1-24)") (class "Default")
      (node (ref "SV1") (pin "BB") (pinfunction "24_BB") (pintype "bidirectional"))
      (node (ref "U$4") (pin "12") (pinfunction "12_12") (pintype "passive"))
    )
    (net (code "981") (name "Net-(SV1-25)") (class "Default")
      (node (ref "SV1") (pin "CC") (pinfunction "25_CC") (pintype "bidirectional"))
      (node (ref "U$2") (pin "13") (pinfunction "13_13") (pintype "passive"))
    )
    (net (code "982") (name "Net-(SV1-26)") (class "Default")
      (node (ref "SV1") (pin "DD") (pinfunction "26_DD") (pintype "bidirectional"))
      (node (ref "U$4") (pin "13") (pinfunction "13_13") (pintype "passive"))
    )
    (net (code "983") (name "Net-(SV1-27)") (class "Default")
      (node (ref "SV1") (pin "EE") (pinfunction "27_EE") (pintype "bidirectional"))
      (node (ref "U$2") (pin "14") (pinfunction "14_14") (pintype "passive"))
    )
    (net (code "984") (name "Net-(SV1-28)") (class "Default")
      (node (ref "SV1") (pin "FF") (pinfunction "28_FF") (pintype "bidirectional"))
      (node (ref "U$4") (pin "14") (pinfunction "14_14") (pintype "passive"))
    )
    (net (code "985") (name "Net-(SV1-29)") (class "Default")
      (node (ref "SV1") (pin "HH") (pinfunction "29_HH") (pintype "bidirectional"))
      (node (ref "U$2") (pin "15") (pinfunction "15_15") (pintype "passive"))
    )
    (net (code "986") (name "Net-(SV1-30)") (class "Default")
      (node (ref "SV1") (pin "JJ") (pinfunction "30_JJ") (pintype "bidirectional"))
      (node (ref "U$4") (pin "15") (pinfunction "15_15") (pintype "passive"))
    )
    (net (code "987") (name "Net-(SV1-31)") (class "Default")
      (node (ref "SV1") (pin "KK") (pinfunction "31_KK") (pintype "bidirectional"))
      (node (ref "U$2") (pin "16") (pinfunction "16_16") (pintype "passive"))
    )
    (net (code "988") (name "Net-(SV1-32)") (class "Default")
      (node (ref "SV1") (pin "LL") (pinfunction "32_LL") (pintype "bidirectional"))
      (node (ref "U$4") (pin "16") (pinfunction "16_16") (pintype "passive"))
    )
    (net (code "989") (name "Net-(SV1-33)") (class "Default")
      (node (ref "SV1") (pin "MM") (pinfunction "33_MM") (pintype "bidirectional"))
      (node (ref "U$2") (pin "17") (pinfunction "17_17") (pintype "passive"))
    )
    (net (code "990") (name "Net-(SV1-34)") (class "Default")
      (node (ref "SV1") (pin "NN") (pinfunction "34_NN") (pintype "bidirectional"))
      (node (ref "U$4") (pin "17") (pinfunction "17_17") (pintype "passive"))
    )
    (net (code "991") (name "Net-(SV1-35)") (class "Default")
      (node (ref "SV1") (pin "PP") (pinfunction "35_PP") (pintype "bidirectional"))
      (node (ref "U$2") (pin "18") (pinfunction "18_18") (pintype "passive"))
    )
    (net (code "992") (name "Net-(SV1-36)") (class "Default")
      (node (ref "SV1") (pin "RR") (pinfunction "36_RR") (pintype "bidirectional"))
      (node (ref "U$4") (pin "18") (pinfunction "18_18") (pintype "passive"))
    )
    (net (code "993") (name "Net-(SV1-37)") (class "Default")
      (node (ref "SV1") (pin "SS") (pinfunction "37_SS") (pintype "bidirectional"))
      (node (ref "U$2") (pin "19") (pinfunction "19_19") (pintype "passive"))
    )
    (net (code "994") (name "Net-(SV1-38)") (class "Default")
      (node (ref "SV1") (pin "TT") (pinfunction "38_TT") (pintype "bidirectional"))
      (node (ref "U$4") (pin "19") (pinfunction "19_19") (pintype "passive"))
    )
    (net (code "995") (name "Net-(SV1-39)") (class "Default")
      (node (ref "SV1") (pin "UU") (pinfunction "39_UU") (pintype "bidirectional"))
      (node (ref "U$2") (pin "20") (pinfunction "20_20") (pintype "passive"))
    )
    (net (code "996") (name "Net-(SV1-40)") (class "Default")
      (node (ref "SV1") (pin "VV") (pinfunction "40_VV") (pintype "bidirectional"))
      (node (ref "U$4") (pin "20") (pinfunction "20_20") (pintype "passive"))
    )
    (net (code "997") (name "Net-(U$1A-1)") (class "Default")
      (node (ref "U$1") (pin "AA1") (pinfunction "1_AA1") (pintype "bidirectional"))
      (node (ref "U$3") (pin "1") (pinfunction "1_1") (pintype "passive"))
    )
    (net (code "998") (name "Net-(U$1AA-1)") (class "Default")
      (node (ref "U$1") (pin "AR1") (pinfunction "1_AR1") (pintype "bidirectional"))
      (node (ref "U$3") (pin "14") (pinfunction "14_14") (pintype "passive"))
    )
    (net (code "999") (name "Net-(U$1AB-1)") (class "Default")
      (node (ref "U$1") (pin "AR2") (pinfunction "1_AR2") (pintype "bidirectional"))
      (node (ref "U$5") (pin "14") (pinfunction "14_14") (pintype "passive"))
    )
    (net (code "1000") (name "Net-(U$1AC-1)") (class "Default")
      (node (ref "U$1") (pin "AS1") (pinfunction "1_AS1") (pintype "bidirectional"))
      (node (ref "U$3") (pin "15") (pinfunction "15_15") (pintype "passive"))
    )
    (net (code "1001") (name "Net-(U$1AD-1)") (class "Default")
      (node (ref "U$1") (pin "AS2") (pinfunction "1_AS2") (pintype "bidirectional"))
      (node (ref "U$5") (pin "15") (pinfunction "15_15") (pintype "passive"))
    )
    (net (code "1002") (name "Net-(U$1AE-1)") (class "Default")
      (node (ref "U$1") (pin "AT1") (pinfunction "1_AT1") (pintype "bidirectional"))
      (node (ref "U$3") (pin "16") (pinfunction "16_16") (pintype "passive"))
    )
    (net (code "1003") (name "Net-(U$1AF-1)") (class "Default")
      (node (ref "U$1") (pin "AT2") (pinfunction "1_AT2") (pintype "bidirectional"))
      (node (ref "U$5") (pin "16") (pinfunction "16_16") (pintype "passive"))
    )
    (net (code "1004") (name "Net-(U$1AG-1)") (class "Default")
      (node (ref "U$1") (pin "AU1") (pinfunction "1_AU1") (pintype "bidirectional"))
      (node (ref "U$3") (pin "17") (pinfunction "17_17") (pintype "passive"))
    )
    (net (code "1005") (name "Net-(U$1AH-1)") (class "Default")
      (node (ref "U$1") (pin "AU2") (pinfunction "1_AU2") (pintype "bidirectional"))
      (node (ref "U$5") (pin "17") (pinfunction "17_17") (pintype "passive"))
    )
    (net (code "1006") (name "Net-(U$1AI-1)") (class "Default")
      (node (ref "U$1") (pin "AV1") (pinfunction "1_AV1") (pintype "bidirectional"))
      (node (ref "U$3") (pin "18") (pinfunction "18_18") (pintype "passive"))
    )
    (net (code "1007") (name "Net-(U$1AJ-1)") (class "Default")
      (node (ref "U$1") (pin "AV2") (pinfunction "1_AV2") (pintype "bidirectional"))
      (node (ref "U$5") (pin "18") (pinfunction "18_18") (pintype "passive"))
    )
    (net (code "1008") (name "Net-(U$1AK-1)") (class "Default")
      (node (ref "U$1") (pin "BA1") (pinfunction "1_BA1") (pintype "bidirectional"))
      (node (ref "U$6") (pin "1") (pinfunction "1_1") (pintype "passive"))
    )
    (net (code "1009") (name "Net-(U$1AL-1)") (class "Default")
      (node (ref "U$1") (pin "BA2") (pinfunction "1_BA2") (pintype "bidirectional"))
      (node (ref "U$7") (pin "1") (pinfunction "1_1") (pintype "passive"))
    )
    (net (code "1010") (name "Net-(U$1AM-1)") (class "Default")
      (node (ref "U$1") (pin "BB1") (pinfunction "1_BB1") (pintype "bidirectional"))
      (node (ref "U$6") (pin "2") (pinfunction "2_2") (pintype "passive"))
    )
    (net (code "1011") (name "Net-(U$1AN-1)") (class "Default")
      (node (ref "U$1") (pin "BB2") (pinfunction "1_BB2") (pintype "bidirectional"))
      (node (ref "U$7") (pin "2") (pinfunction "2_2") (pintype "passive"))
    )
    (net (code "1012") (name "Net-(U$1AO-1)") (class "Default")
      (node (ref "U$1") (pin "BC1") (pinfunction "1_BC1") (pintype "bidirectional"))
      (node (ref "U$6") (pin "3") (pinfunction "3_3") (pintype "passive"))
    )
    (net (code "1013") (name "Net-(U$1AP-1)") (class "Default")
      (node (ref "U$1") (pin "BC2") (pinfunction "1_BC2") (pintype "bidirectional"))
      (node (ref "U$7") (pin "3") (pinfunction "3_3") (pintype "passive"))
    )
    (net (code "1014") (name "Net-(U$1AQ-1)") (class "Default")
      (node (ref "U$1") (pin "BD1") (pinfunction "1_BD1") (pintype "bidirectional"))
      (node (ref "U$6") (pin "4") (pinfunction "4_4") (pintype "passive"))
    )
    (net (code "1015") (name "Net-(U$1AR-1)") (class "Default")
      (node (ref "U$1") (pin "BD2") (pinfunction "1_BD2") (pintype "bidirectional"))
      (node (ref "U$7") (pin "4") (pinfunction "4_4") (pintype "passive"))
    )
    (net (code "1016") (name "Net-(U$1AS-1)") (class "Default")
      (node (ref "U$1") (pin "BE1") (pinfunction "1_BE1") (pintype "bidirectional"))
      (node (ref "U$6") (pin "5") (pinfunction "5_5") (pintype "passive"))
    )
    (net (code "1017") (name "Net-(U$1AT-1)") (class "Default")
      (node (ref "U$1") (pin "BE2") (pinfunction "1_BE2") (pintype "bidirectional"))
      (node (ref "U$7") (pin "5") (pinfunction "5_5") (pintype "passive"))
    )
    (net (code "1018") (name "Net-(U$1AU-1)") (class "Default")
      (node (ref "U$1") (pin "BF1") (pinfunction "1_BF1") (pintype "bidirectional"))
      (node (ref "U$6") (pin "6") (pinfunction "6_6") (pintype "passive"))
    )
    (net (code "1019") (name "Net-(U$1AV-1)") (class "Default")
      (node (ref "U$1") (pin "BF2") (pinfunction "1_BF2") (pintype "bidirectional"))
      (node (ref "U$7") (pin "6") (pinfunction "6_6") (pintype "passive"))
    )
    (net (code "1020") (name "Net-(U$1AW-1)") (class "Default")
      (node (ref "U$1") (pin "BH1") (pinfunction "1_BH1") (pintype "bidirectional"))
      (node (ref "U$6") (pin "7") (pinfunction "7_7") (pintype "passive"))
    )
    (net (code "1021") (name "Net-(U$1AX-1)") (class "Default")
      (node (ref "U$1") (pin "BH2") (pinfunction "1_BH2") (pintype "bidirectional"))
      (node (ref "U$7") (pin "7") (pinfunction "7_7") (pintype "passive"))
    )
    (net (code "1022") (name "Net-(U$1AY-1)") (class "Default")
      (node (ref "U$1") (pin "BJ1") (pinfunction "1_BJ1") (pintype "bidirectional"))
      (node (ref "U$6") (pin "8") (pinfunction "8_8") (pintype "passive"))
    )
    (net (code "1023") (name "Net-(U$1AZ-1)") (class "Default")
      (node (ref "U$1") (pin "BJ2") (pinfunction "1_BJ2") (pintype "bidirectional"))
      (node (ref "U$7") (pin "8") (pinfunction "8_8") (pintype "passive"))
    )
    (net (code "1024") (name "Net-(U$1B-1)") (class "Default")
      (node (ref "U$1") (pin "AA2") (pinfunction "1_AA2") (pintype "bidirectional"))
      (node (ref "U$5") (pin "1") (pinfunction "1_1") (pintype "passive"))
    )
    (net (code "1025") (name "Net-(U$1BA-1)") (class "Default")
      (node (ref "U$1") (pin "BK1") (pinfunction "1_BK1") (pintype "bidirectional"))
      (node (ref "U$6") (pin "9") (pinfunction "9_9") (pintype "passive"))
    )
    (net (code "1026") (name "Net-(U$1BB-1)") (class "Default")
      (node (ref "U$1") (pin "BK2") (pinfunction "1_BK2") (pintype "bidirectional"))
      (node (ref "U$7") (pin "9") (pinfunction "9_9") (pintype "passive"))
    )
    (net (code "1027") (name "Net-(U$1BC-1)") (class "Default")
      (node (ref "U$1") (pin "BL1") (pinfunction "1_BL1") (pintype "bidirectional"))
      (node (ref "U$6") (pin "10") (pinfunction "10_10") (pintype "passive"))
    )
    (net (code "1028") (name "Net-(U$1BD-1)") (class "Default")
      (node (ref "U$1") (pin "BL2") (pinfunction "1_BL2") (pintype "bidirectional"))
      (node (ref "U$7") (pin "10") (pinfunction "10_10") (pintype "passive"))
    )
    (net (code "1029") (name "Net-(U$1BE-1)") (class "Default")
      (node (ref "U$1") (pin "BM1") (pinfunction "1_BM1") (pintype "bidirectional"))
      (node (ref "U$6") (pin "11") (pinfunction "11_11") (pintype "passive"))
    )
    (net (code "1030") (name "Net-(U$1BF-1)") (class "Default")
      (node (ref "U$1") (pin "BM2") (pinfunction "1_BM2") (pintype "bidirectional"))
      (node (ref "U$7") (pin "11") (pinfunction "11_11") (pintype "passive"))
    )
    (net (code "1031") (name "Net-(U$1BG-1)") (class "Default")
      (node (ref "U$1") (pin "BN1") (pinfunction "1_BN1") (pintype "bidirectional"))
      (node (ref "U$6") (pin "12") (pinfunction "12_12") (pintype "passive"))
    )
    (net (code "1032") (name "Net-(U$1BH-1)") (class "Default")
      (node (ref "U$1") (pin "BN2") (pinfunction "1_BN2") (pintype "bidirectional"))
      (node (ref "U$7") (pin "12") (pinfunction "12_12") (pintype "passive"))
    )
    (net (code "1033") (name "Net-(U$1BI-1)") (class "Default")
      (node (ref "U$1") (pin "BP1") (pinfunction "1_BP1") (pintype "bidirectional"))
      (node (ref "U$6") (pin "13") (pinfunction "13_13") (pintype "passive"))
    )
    (net (code "1034") (name "Net-(U$1BJ-1)") (class "Default")
      (node (ref "U$1") (pin "BP2") (pinfunction "1_BP2") (pintype "bidirectional"))
      (node (ref "U$7") (pin "13") (pinfunction "13_13") (pintype "passive"))
    )
    (net (code "1035") (name "Net-(U$1BK-1)") (class "Default")
      (node (ref "U$1") (pin "BR1") (pinfunction "1_BR1") (pintype "bidirectional"))
      (node (ref "U$6") (pin "14") (pinfunction "14_14") (pintype "passive"))
    )
    (net (code "1036") (name "Net-(U$1BL-1)") (class "Default")
      (node (ref "U$1") (pin "BR2") (pinfunction "1_BR2") (pintype "bidirectional"))
      (node (ref "U$7") (pin "14") (pinfunction "14_14") (pintype "passive"))
    )
    (net (code "1037") (name "Net-(U$1BM-1)") (class "Default")
      (node (ref "U$1") (pin "BS1") (pinfunction "1_BS1") (pintype "bidirectional"))
      (node (ref "U$6") (pin "15") (pinfunction "15_15") (pintype "passive"))
    )
    (net (code "1038") (name "Net-(U$1BN-1)") (class "Default")
      (node (ref "U$1") (pin "BS2") (pinfunction "1_BS2") (pintype "bidirectional"))
      (node (ref "U$7") (pin "15") (pinfunction "15_15") (pintype "passive"))
    )
    (net (code "1039") (name "Net-(U$1BO-1)") (class "Default")
      (node (ref "U$1") (pin "BT1") (pinfunction "1_BT1") (pintype "bidirectional"))
      (node (ref "U$6") (pin "16") (pinfunction "16_16") (pintype "passive"))
    )
    (net (code "1040") (name "Net-(U$1BP-1)") (class "Default")
      (node (ref "U$1") (pin "BT2") (pinfunction "1_BT2") (pintype "bidirectional"))
      (node (ref "U$7") (pin "16") (pinfunction "16_16") (pintype "passive"))
    )
    (net (code "1041") (name "Net-(U$1BQ-1)") (class "Default")
      (node (ref "U$1") (pin "BU1") (pinfunction "1_BU1") (pintype "bidirectional"))
      (node (ref "U$6") (pin "17") (pinfunction "17_17") (pintype "passive"))
    )
    (net (code "1042") (name "Net-(U$1BR-1)") (class "Default")
      (node (ref "U$1") (pin "BU2") (pinfunction "1_BU2") (pintype "bidirectional"))
      (node (ref "U$7") (pin "17") (pinfunction "17_17") (pintype "passive"))
    )
    (net (code "1043") (name "Net-(U$1BS-1)") (class "Default")
      (node (ref "U$1") (pin "BV1") (pinfunction "1_BV1") (pintype "bidirectional"))
      (node (ref "U$6") (pin "18") (pinfunction "18_18") (pintype "passive"))
    )
    (net (code "1044") (name "Net-(U$1BT-1)") (class "Default")
      (node (ref "U$1") (pin "BV2") (pinfunction "1_BV2") (pintype "bidirectional"))
      (node (ref "U$7") (pin "18") (pinfunction "18_18") (pintype "passive"))
    )
    (net (code "1045") (name "Net-(U$1BU-1)") (class "Default")
      (node (ref "U$1") (pin "CA1") (pinfunction "1_CA1") (pintype "bidirectional"))
      (node (ref "U$9") (pin "1") (pinfunction "1_1") (pintype "passive"))
    )
    (net (code "1046") (name "Net-(U$1BV-1)") (class "Default")
      (node (ref "U$1") (pin "CA2") (pinfunction "1_CA2") (pintype "bidirectional"))
      (node (ref "U$10") (pin "1") (pinfunction "1_1") (pintype "passive"))
    )
    (net (code "1047") (name "Net-(U$1BW-1)") (class "Default")
      (node (ref "U$1") (pin "CB1") (pinfunction "1_CB1") (pintype "bidirectional"))
      (node (ref "U$9") (pin "2") (pinfunction "2_2") (pintype "passive"))
    )
    (net (code "1048") (name "Net-(U$1BX-1)") (class "Default")
      (node (ref "U$1") (pin "CB2") (pinfunction "1_CB2") (pintype "bidirectional"))
      (node (ref "U$10") (pin "2") (pinfunction "2_2") (pintype "passive"))
    )
    (net (code "1049") (name "Net-(U$1BY-1)") (class "Default")
      (node (ref "U$1") (pin "CC1") (pinfunction "1_CC1") (pintype "bidirectional"))
      (node (ref "U$9") (pin "3") (pinfunction "3_3") (pintype "passive"))
    )
    (net (code "1050") (name "Net-(U$1BZ-1)") (class "Default")
      (node (ref "U$1") (pin "CC2") (pinfunction "1_CC2") (pintype "bidirectional"))
      (node (ref "U$10") (pin "3") (pinfunction "3_3") (pintype "passive"))
    )
    (net (code "1051") (name "Net-(U$1C-1)") (class "Default")
      (node (ref "U$1") (pin "AB1") (pinfunction "1_AB1") (pintype "bidirectional"))
      (node (ref "U$3") (pin "2") (pinfunction "2_2") (pintype "passive"))
    )
    (net (code "1052") (name "Net-(U$1CA-1)") (class "Default")
      (node (ref "U$1") (pin "CD1") (pinfunction "1_CD1") (pintype "bidirectional"))
      (node (ref "U$9") (pin "4") (pinfunction "4_4") (pintype "passive"))
    )
    (net (code "1053") (name "Net-(U$1CB-1)") (class "Default")
      (node (ref "U$1") (pin "CD2") (pinfunction "1_CD2") (pintype "bidirectional"))
      (node (ref "U$10") (pin "4") (pinfunction "4_4") (pintype "passive"))
    )
    (net (code "1054") (name "Net-(U$1CC-1)") (class "Default")
      (node (ref "U$1") (pin "CE1") (pinfunction "1_CE1") (pintype "bidirectional"))
      (node (ref "U$9") (pin "5") (pinfunction "5_5") (pintype "passive"))
    )
    (net (code "1055") (name "Net-(U$1CD-1)") (class "Default")
      (node (ref "U$1") (pin "CE2") (pinfunction "1_CE2") (pintype "bidirectional"))
      (node (ref "U$10") (pin "5") (pinfunction "5_5") (pintype "passive"))
    )
    (net (code "1056") (name "Net-(U$1CE-1)") (class "Default")
      (node (ref "U$1") (pin "CF1") (pinfunction "1_CF1") (pintype "bidirectional"))
      (node (ref "U$9") (pin "6") (pinfunction "6_6") (pintype "passive"))
    )
    (net (code "1057") (name "Net-(U$1CF-1)") (class "Default")
      (node (ref "U$1") (pin "CF2") (pinfunction "1_CF2") (pintype "bidirectional"))
      (node (ref "U$10") (pin "6") (pinfunction "6_6") (pintype "passive"))
    )
    (net (code "1058") (name "Net-(U$1CG-1)") (class "Default")
      (node (ref "U$1") (pin "CH1") (pinfunction "1_CH1") (pintype "bidirectional"))
      (node (ref "U$9") (pin "7") (pinfunction "7_7") (pintype "passive"))
    )
    (net (code "1059") (name "Net-(U$1CH-1)") (class "Default")
      (node (ref "U$1") (pin "CH2") (pinfunction "1_CH2") (pintype "bidirectional"))
      (node (ref "U$10") (pin "7") (pinfunction "7_7") (pintype "passive"))
    )
    (net (code "1060") (name "Net-(U$1CI-1)") (class "Default")
      (node (ref "U$1") (pin "CJ1") (pinfunction "1_CJ1") (pintype "bidirectional"))
      (node (ref "U$9") (pin "8") (pinfunction "8_8") (pintype "passive"))
    )
    (net (code "1061") (name "Net-(U$1CJ-1)") (class "Default")
      (node (ref "U$1") (pin "CJ2") (pinfunction "1_CJ2") (pintype "bidirectional"))
      (node (ref "U$10") (pin "8") (pinfunction "8_8") (pintype "passive"))
    )
    (net (code "1062") (name "Net-(U$1CK-1)") (class "Default")
      (node (ref "U$1") (pin "CK1") (pinfunction "1_CK1") (pintype "bidirectional"))
      (node (ref "U$9") (pin "9") (pinfunction "9_9") (pintype "passive"))
    )
    (net (code "1063") (name "Net-(U$1CL-1)") (class "Default")
      (node (ref "U$1") (pin "CK2") (pinfunction "1_CK2") (pintype "bidirectional"))
      (node (ref "U$10") (pin "9") (pinfunction "9_9") (pintype "passive"))
    )
    (net (code "1064") (name "Net-(U$1CM-1)") (class "Default")
      (node (ref "U$1") (pin "CL1") (pinfunction "1_CL1") (pintype "bidirectional"))
      (node (ref "U$9") (pin "10") (pinfunction "10_10") (pintype "passive"))
    )
    (net (code "1065") (name "Net-(U$1CN-1)") (class "Default")
      (node (ref "U$1") (pin "CL2") (pinfunction "1_CL2") (pintype "bidirectional"))
      (node (ref "U$10") (pin "10") (pinfunction "10_10") (pintype "passive"))
    )
    (net (code "1066") (name "Net-(U$1CO-1)") (class "Default")
      (node (ref "U$1") (pin "CM1") (pinfunction "1_CM1") (pintype "bidirectional"))
      (node (ref "U$9") (pin "11") (pinfunction "11_11") (pintype "passive"))
    )
    (net (code "1067") (name "Net-(U$1CP-1)") (class "Default")
      (node (ref "U$1") (pin "CM2") (pinfunction "1_CM2") (pintype "bidirectional"))
      (node (ref "U$10") (pin "11") (pinfunction "11_11") (pintype "passive"))
    )
    (net (code "1068") (name "Net-(U$1CQ-1)") (class "Default")
      (node (ref "U$1") (pin "CN1") (pinfunction "1_CN1") (pintype "bidirectional"))
      (node (ref "U$9") (pin "12") (pinfunction "12_12") (pintype "passive"))
    )
    (net (code "1069") (name "Net-(U$1CR-1)") (class "Default")
      (node (ref "U$1") (pin "CN2") (pinfunction "1_CN2") (pintype "bidirectional"))
      (node (ref "U$10") (pin "12") (pinfunction "12_12") (pintype "passive"))
    )
    (net (code "1070") (name "Net-(U$1CS-1)") (class "Default")
      (node (ref "U$1") (pin "CP1") (pinfunction "1_CP1") (pintype "bidirectional"))
      (node (ref "U$9") (pin "13") (pinfunction "13_13") (pintype "passive"))
    )
    (net (code "1071") (name "Net-(U$1CT-1)") (class "Default")
      (node (ref "U$1") (pin "CP2") (pinfunction "1_CP2") (pintype "bidirectional"))
      (node (ref "U$10") (pin "13") (pinfunction "13_13") (pintype "passive"))
    )
    (net (code "1072") (name "Net-(U$1CU-1)") (class "Default")
      (node (ref "U$1") (pin "CR1") (pinfunction "1_CR1") (pintype "bidirectional"))
      (node (ref "U$9") (pin "14") (pinfunction "14_14") (pintype "passive"))
    )
    (net (code "1073") (name "Net-(U$1CV-1)") (class "Default")
      (node (ref "U$1") (pin "CR2") (pinfunction "1_CR2") (pintype "bidirectional"))
      (node (ref "U$10") (pin "14") (pinfunction "14_14") (pintype "passive"))
    )
    (net (code "1074") (name "Net-(U$1CW-1)") (class "Default")
      (node (ref "U$1") (pin "CS1") (pinfunction "1_CS1") (pintype "bidirectional"))
      (node (ref "U$9") (pin "15") (pinfunction "15_15") (pintype "passive"))
    )
    (net (code "1075") (name "Net-(U$1CX-1)") (class "Default")
      (node (ref "U$1") (pin "CS2") (pinfunction "1_CS2") (pintype "bidirectional"))
      (node (ref "U$10") (pin "15") (pinfunction "15_15") (pintype "passive"))
    )
    (net (code "1076") (name "Net-(U$1CY-1)") (class "Default")
      (node (ref "U$1") (pin "CT1") (pinfunction "1_CT1") (pintype "bidirectional"))
      (node (ref "U$9") (pin "16") (pinfunction "16_16") (pintype "passive"))
    )
    (net (code "1077") (name "Net-(U$1CZ-1)") (class "Default")
      (node (ref "U$1") (pin "CT2") (pinfunction "1_CT2") (pintype "bidirectional"))
      (node (ref "U$10") (pin "16") (pinfunction "16_16") (pintype "passive"))
    )
    (net (code "1078") (name "Net-(U$1D-1)") (class "Default")
      (node (ref "U$1") (pin "AB2") (pinfunction "1_AB2") (pintype "bidirectional"))
      (node (ref "U$5") (pin "2") (pinfunction "2_2") (pintype "passive"))
    )
    (net (code "1079") (name "Net-(U$1DA-1)") (class "Default")
      (node (ref "U$1") (pin "CU1") (pinfunction "1_CU1") (pintype "bidirectional"))
      (node (ref "U$9") (pin "17") (pinfunction "17_17") (pintype "passive"))
    )
    (net (code "1080") (name "Net-(U$1DB-1)") (class "Default")
      (node (ref "U$1") (pin "CU2") (pinfunction "1_CU2") (pintype "bidirectional"))
      (node (ref "U$10") (pin "17") (pinfunction "17_17") (pintype "passive"))
    )
    (net (code "1081") (name "Net-(U$1DC-1)") (class "Default")
      (node (ref "U$1") (pin "CV1") (pinfunction "1_CV1") (pintype "bidirectional"))
      (node (ref "U$9") (pin "18") (pinfunction "18_18") (pintype "passive"))
    )
    (net (code "1082") (name "Net-(U$1DD-1)") (class "Default")
      (node (ref "U$1") (pin "CV2") (pinfunction "1_CV2") (pintype "bidirectional"))
      (node (ref "U$10") (pin "18") (pinfunction "18_18") (pintype "passive"))
    )
    (net (code "1083") (name "Net-(U$1DE-1)") (class "Default")
      (node (ref "U$1") (pin "DA1") (pinfunction "1_DA1") (pintype "bidirectional"))
      (node (ref "U$11") (pin "1") (pinfunction "1_1") (pintype "passive"))
    )
    (net (code "1084") (name "Net-(U$1DF-1)") (class "Default")
      (node (ref "U$1") (pin "DA2") (pinfunction "1_DA2") (pintype "bidirectional"))
      (node (ref "U$12") (pin "1") (pinfunction "1_1") (pintype "passive"))
    )
    (net (code "1085") (name "Net-(U$1DG-1)") (class "Default")
      (node (ref "U$1") (pin "DB1") (pinfunction "1_DB1") (pintype "bidirectional"))
      (node (ref "U$11") (pin "2") (pinfunction "2_2") (pintype "passive"))
    )
    (net (code "1086") (name "Net-(U$1DH-1)") (class "Default")
      (node (ref "U$1") (pin "DB2") (pinfunction "1_DB2") (pintype "bidirectional"))
      (node (ref "U$12") (pin "2") (pinfunction "2_2") (pintype "passive"))
    )
    (net (code "1087") (name "Net-(U$1DI-1)") (class "Default")
      (node (ref "U$1") (pin "DC1") (pinfunction "1_DC1") (pintype "bidirectional"))
      (node (ref "U$11") (pin "3") (pinfunction "3_3") (pintype "passive"))
    )
    (net (code "1088") (name "Net-(U$1DJ-1)") (class "Default")
      (node (ref "U$1") (pin "DC2") (pinfunction "1_DC2") (pintype "bidirectional"))
      (node (ref "U$12") (pin "3") (pinfunction "3_3") (pintype "passive"))
    )
    (net (code "1089") (name "Net-(U$1DK-1)") (class "Default")
      (node (ref "U$1") (pin "DD1") (pinfunction "1_DD1") (pintype "bidirectional"))
      (node (ref "U$11") (pin "4") (pinfunction "4_4") (pintype "passive"))
    )
    (net (code "1090") (name "Net-(U$1DL-1)") (class "Default")
      (node (ref "U$1") (pin "DD2") (pinfunction "1_DD2") (pintype "bidirectional"))
      (node (ref "U$12") (pin "4") (pinfunction "4_4") (pintype "passive"))
    )
    (net (code "1091") (name "Net-(U$1DM-1)") (class "Default")
      (node (ref "U$1") (pin "DE1") (pinfunction "1_DE1") (pintype "bidirectional"))
      (node (ref "U$11") (pin "5") (pinfunction "5_5") (pintype "passive"))
    )
    (net (code "1092") (name "Net-(U$1DN-1)") (class "Default")
      (node (ref "U$1") (pin "DE2") (pinfunction "1_DE2") (pintype "bidirectional"))
      (node (ref "U$12") (pin "5") (pinfunction "5_5") (pintype "passive"))
    )
    (net (code "1093") (name "Net-(U$1DO-1)") (class "Default")
      (node (ref "U$1") (pin "DF1") (pinfunction "1_DF1") (pintype "bidirectional"))
      (node (ref "U$11") (pin "6") (pinfunction "6_6") (pintype "passive"))
    )
    (net (code "1094") (name "Net-(U$1DP-1)") (class "Default")
      (node (ref "U$1") (pin "DF2") (pinfunction "1_DF2") (pintype "bidirectional"))
      (node (ref "U$12") (pin "6") (pinfunction "6_6") (pintype "passive"))
    )
    (net (code "1095") (name "Net-(U$1DQ-1)") (class "Default")
      (node (ref "U$1") (pin "DH1") (pinfunction "1_DH1") (pintype "bidirectional"))
      (node (ref "U$11") (pin "7") (pinfunction "7_7") (pintype "passive"))
    )
    (net (code "1096") (name "Net-(U$1DR-1)") (class "Default")
      (node (ref "U$1") (pin "DH2") (pinfunction "1_DH2") (pintype "bidirectional"))
      (node (ref "U$12") (pin "7") (pinfunction "7_7") (pintype "passive"))
    )
    (net (code "1097") (name "Net-(U$1DS-1)") (class "Default")
      (node (ref "U$1") (pin "DJ1") (pinfunction "1_DJ1") (pintype "bidirectional"))
      (node (ref "U$11") (pin "8") (pinfunction "8_8") (pintype "passive"))
    )
    (net (code "1098") (name "Net-(U$1DT-1)") (class "Default")
      (node (ref "U$1") (pin "DJ2") (pinfunction "1_DJ2") (pintype "bidirectional"))
      (node (ref "U$12") (pin "8") (pinfunction "8_8") (pintype "passive"))
    )
    (net (code "1099") (name "Net-(U$1DU-1)") (class "Default")
      (node (ref "U$1") (pin "DK1") (pinfunction "1_DK1") (pintype "bidirectional"))
      (node (ref "U$11") (pin "9") (pinfunction "9_9") (pintype "passive"))
    )
    (net (code "1100") (name "Net-(U$1DV-1)") (class "Default")
      (node (ref "U$1") (pin "DK2") (pinfunction "1_DK2") (pintype "bidirectional"))
      (node (ref "U$12") (pin "9") (pinfunction "9_9") (pintype "passive"))
    )
    (net (code "1101") (name "Net-(U$1DW-1)") (class "Default")
      (node (ref "U$1") (pin "DL1") (pinfunction "1_DL1") (pintype "bidirectional"))
      (node (ref "U$11") (pin "10") (pinfunction "10_10") (pintype "passive"))
    )
    (net (code "1102") (name "Net-(U$1DX-1)") (class "Default")
      (node (ref "U$1") (pin "DL2") (pinfunction "1_DL2") (pintype "bidirectional"))
      (node (ref "U$12") (pin "10") (pinfunction "10_10") (pintype "passive"))
    )
    (net (code "1103") (name "Net-(U$1DY-1)") (class "Default")
      (node (ref "U$1") (pin "DM1") (pinfunction "1_DM1") (pintype "bidirectional"))
      (node (ref "U$11") (pin "11") (pinfunction "11_11") (pintype "passive"))
    )
    (net (code "1104") (name "Net-(U$1DZ-1)") (class "Default")
      (node (ref "U$1") (pin "DM2") (pinfunction "1_DM2") (pintype "bidirectional"))
      (node (ref "U$12") (pin "11") (pinfunction "11_11") (pintype "passive"))
    )
    (net (code "1105") (name "Net-(U$1E-1)") (class "Default")
      (node (ref "U$1") (pin "AC1") (pinfunction "1_AC1") (pintype "bidirectional"))
      (node (ref "U$3") (pin "3") (pinfunction "3_3") (pintype "passive"))
    )
    (net (code "1106") (name "Net-(U$1EA-1)") (class "Default")
      (node (ref "U$1") (pin "DN1") (pinfunction "1_DN1") (pintype "bidirectional"))
      (node (ref "U$11") (pin "12") (pinfunction "12_12") (pintype "passive"))
    )
    (net (code "1107") (name "Net-(U$1EB-1)") (class "Default")
      (node (ref "U$1") (pin "DN2") (pinfunction "1_DN2") (pintype "bidirectional"))
      (node (ref "U$12") (pin "12") (pinfunction "12_12") (pintype "passive"))
    )
    (net (code "1108") (name "Net-(U$1EC-1)") (class "Default")
      (node (ref "U$1") (pin "DP1") (pinfunction "1_DP1") (pintype "bidirectional"))
      (node (ref "U$11") (pin "13") (pinfunction "13_13") (pintype "passive"))
    )
    (net (code "1109") (name "Net-(U$1ED-1)") (class "Default")
      (node (ref "U$1") (pin "DP2") (pinfunction "1_DP2") (pintype "bidirectional"))
      (node (ref "U$12") (pin "13") (pinfunction "13_13") (pintype "passive"))
    )
    (net (code "1110") (name "Net-(U$1EE-1)") (class "Default")
      (node (ref "U$1") (pin "DR1") (pinfunction "1_DR1") (pintype "bidirectional"))
      (node (ref "U$11") (pin "14") (pinfunction "14_14") (pintype "passive"))
    )
    (net (code "1111") (name "Net-(U$1EF-1)") (class "Default")
      (node (ref "U$1") (pin "DR2") (pinfunction "1_DR2") (pintype "bidirectional"))
      (node (ref "U$12") (pin "14") (pinfunction "14_14") (pintype "passive"))
    )
    (net (code "1112") (name "Net-(U$1EG-1)") (class "Default")
      (node (ref "U$1") (pin "DS1") (pinfunction "1_DS1") (pintype "bidirectional"))
      (node (ref "U$11") (pin "15") (pinfunction "15_15") (pintype "passive"))
    )
    (net (code "1113") (name "Net-(U$1EH-1)") (class "Default")
      (node (ref "U$1") (pin "DS2") (pinfunction "1_DS2") (pintype "bidirectional"))
      (node (ref "U$12") (pin "15") (pinfunction "15_15") (pintype "passive"))
    )
    (net (code "1114") (name "Net-(U$1EI-1)") (class "Default")
      (node (ref "U$1") (pin "DT1") (pinfunction "1_DT1") (pintype "bidirectional"))
      (node (ref "U$11") (pin "16") (pinfunction "16_16") (pintype "passive"))
    )
    (net (code "1115") (name "Net-(U$1EJ-1)") (class "Default")
      (node (ref "U$1") (pin "DT2") (pinfunction "1_DT2") (pintype "bidirectional"))
      (node (ref "U$12") (pin "16") (pinfunction "16_16") (pintype "passive"))
    )
    (net (code "1116") (name "Net-(U$1EK-1)") (class "Default")
      (node (ref "U$1") (pin "DU1") (pinfunction "1_DU1") (pintype "bidirectional"))
      (node (ref "U$11") (pin "17") (pinfunction "17_17") (pintype "passive"))
    )
    (net (code "1117") (name "Net-(U$1EL-1)") (class "Default")
      (node (ref "U$1") (pin "DU2") (pinfunction "1_DU2") (pintype "bidirectional"))
      (node (ref "U$12") (pin "17") (pinfunction "17_17") (pintype "passive"))
    )
    (net (code "1118") (name "Net-(U$1EM-1)") (class "Default")
      (node (ref "U$1") (pin "DV1") (pinfunction "1_DV1") (pintype "bidirectional"))
      (node (ref "U$11") (pin "18") (pinfunction "18_18") (pintype "passive"))
    )
    (net (code "1119") (name "Net-(U$1EN-1)") (class "Default")
      (node (ref "U$1") (pin "DV2") (pinfunction "1_DV2") (pintype "bidirectional"))
      (node (ref "U$12") (pin "18") (pinfunction "18_18") (pintype "passive"))
    )
    (net (code "1120") (name "Net-(U$1F-1)") (class "Default")
      (node (ref "U$1") (pin "AC2") (pinfunction "1_AC2") (pintype "bidirectional"))
      (node (ref "U$5") (pin "3") (pinfunction "3_3") (pintype "passive"))
    )
    (net (code "1121") (name "Net-(U$1G-1)") (class "Default")
      (node (ref "U$1") (pin "AD1") (pinfunction "1_AD1") (pintype "bidirectional"))
      (node (ref "U$3") (pin "4") (pinfunction "4_4") (pintype "passive"))
    )
    (net (code "1122") (name "Net-(U$1H-1)") (class "Default")
      (node (ref "U$1") (pin "AD2") (pinfunction "1_AD2") (pintype "bidirectional"))
      (node (ref "U$5") (pin "4") (pinfunction "4_4") (pintype "passive"))
    )
    (net (code "1123") (name "Net-(U$1I-1)") (class "Default")
      (node (ref "U$1") (pin "AE1") (pinfunction "1_AE1") (pintype "bidirectional"))
      (node (ref "U$3") (pin "5") (pinfunction "5_5") (pintype "passive"))
    )
    (net (code "1124") (name "Net-(U$1J-1)") (class "Default")
      (node (ref "U$1") (pin "AE2") (pinfunction "1_AE2") (pintype "bidirectional"))
      (node (ref "U$5") (pin "5") (pinfunction "5_5") (pintype "passive"))
    )
    (net (code "1125") (name "Net-(U$1K-1)") (class "Default")
      (node (ref "U$1") (pin "AF1") (pinfunction "1_AF1") (pintype "bidirectional"))
      (node (ref "U$3") (pin "6") (pinfunction "6_6") (pintype "passive"))
    )
    (net (code "1126") (name "Net-(U$1L-1)") (class "Default")
      (node (ref "U$1") (pin "AF2") (pinfunction "1_AF2") (pintype "bidirectional"))
      (node (ref "U$5") (pin "6") (pinfunction "6_6") (pintype "passive"))
    )
    (net (code "1127") (name "Net-(U$1M-1)") (class "Default")
      (node (ref "U$1") (pin "AH1") (pinfunction "1_AH1") (pintype "bidirectional"))
      (node (ref "U$3") (pin "7") (pinfunction "7_7") (pintype "passive"))
    )
    (net (code "1128") (name "Net-(U$1N-1)") (class "Default")
      (node (ref "U$1") (pin "AH2") (pinfunction "1_AH2") (pintype "bidirectional"))
      (node (ref "U$5") (pin "7") (pinfunction "7_7") (pintype "passive"))
    )
    (net (code "1129") (name "Net-(U$1O-1)") (class "Default")
      (node (ref "U$1") (pin "AJ1") (pinfunction "1_AJ1") (pintype "bidirectional"))
      (node (ref "U$3") (pin "8") (pinfunction "8_8") (pintype "passive"))
    )
    (net (code "1130") (name "Net-(U$1P-1)") (class "Default")
      (node (ref "U$1") (pin "AJ2") (pinfunction "1_AJ2") (pintype "bidirectional"))
      (node (ref "U$5") (pin "8") (pinfunction "8_8") (pintype "passive"))
    )
    (net (code "1131") (name "Net-(U$1Q-1)") (class "Default")
      (node (ref "U$1") (pin "AK1") (pinfunction "1_AK1") (pintype "bidirectional"))
      (node (ref "U$3") (pin "9") (pinfunction "9_9") (pintype "passive"))
    )
    (net (code "1132") (name "Net-(U$1R-1)") (class "Default")
      (node (ref "U$1") (pin "AK2") (pinfunction "1_AK2") (pintype "bidirectional"))
      (node (ref "U$5") (pin "9") (pinfunction "9_9") (pintype "passive"))
    )
    (net (code "1133") (name "Net-(U$1S-1)") (class "Default")
      (node (ref "U$1") (pin "AL1") (pinfunction "1_AL1") (pintype "bidirectional"))
      (node (ref "U$3") (pin "10") (pinfunction "10_10") (pintype "passive"))
    )
    (net (code "1134") (name "Net-(U$1T-1)") (class "Default")
      (node (ref "U$1") (pin "AL2") (pinfunction "1_AL2") (pintype "bidirectional"))
      (node (ref "U$5") (pin "10") (pinfunction "10_10") (pintype "passive"))
    )
    (net (code "1135") (name "Net-(U$1U-1)") (class "Default")
      (node (ref "U$1") (pin "AM1") (pinfunction "1_AM1") (pintype "bidirectional"))
      (node (ref "U$3") (pin "11") (pinfunction "11_11") (pintype "passive"))
    )
    (net (code "1136") (name "Net-(U$1V-1)") (class "Default")
      (node (ref "U$1") (pin "AM2") (pinfunction "1_AM2") (pintype "bidirectional"))
      (node (ref "U$5") (pin "11") (pinfunction "11_11") (pintype "passive"))
    )
    (net (code "1137") (name "Net-(U$1W-1)") (class "Default")
      (node (ref "U$1") (pin "AN1") (pinfunction "1_AN1") (pintype "bidirectional"))
      (node (ref "U$3") (pin "12") (pinfunction "12_12") (pintype "passive"))
    )
    (net (code "1138") (name "Net-(U$1X-1)") (class "Default")
      (node (ref "U$1") (pin "AN2") (pinfunction "1_AN2") (pintype "bidirectional"))
      (node (ref "U$5") (pin "12") (pinfunction "12_12") (pintype "passive"))
    )
    (net (code "1139") (name "Net-(U$1Y-1)") (class "Default")
      (node (ref "U$1") (pin "AP1") (pinfunction "1_AP1") (pintype "bidirectional"))
      (node (ref "U$3") (pin "13") (pinfunction "13_13") (pintype "passive"))
    )
    (net (code "1140") (name "Net-(U$1Z-1)") (class "Default")
      (node (ref "U$1") (pin "AP2") (pinfunction "1_AP2") (pintype "bidirectional"))
      (node (ref "U$5") (pin "13") (pinfunction "13_13") (pintype "passive"))
    )
  )
)
